# GridSeed_Rev04.net
KiCad netlist of a schematic drawn in Altium Designer
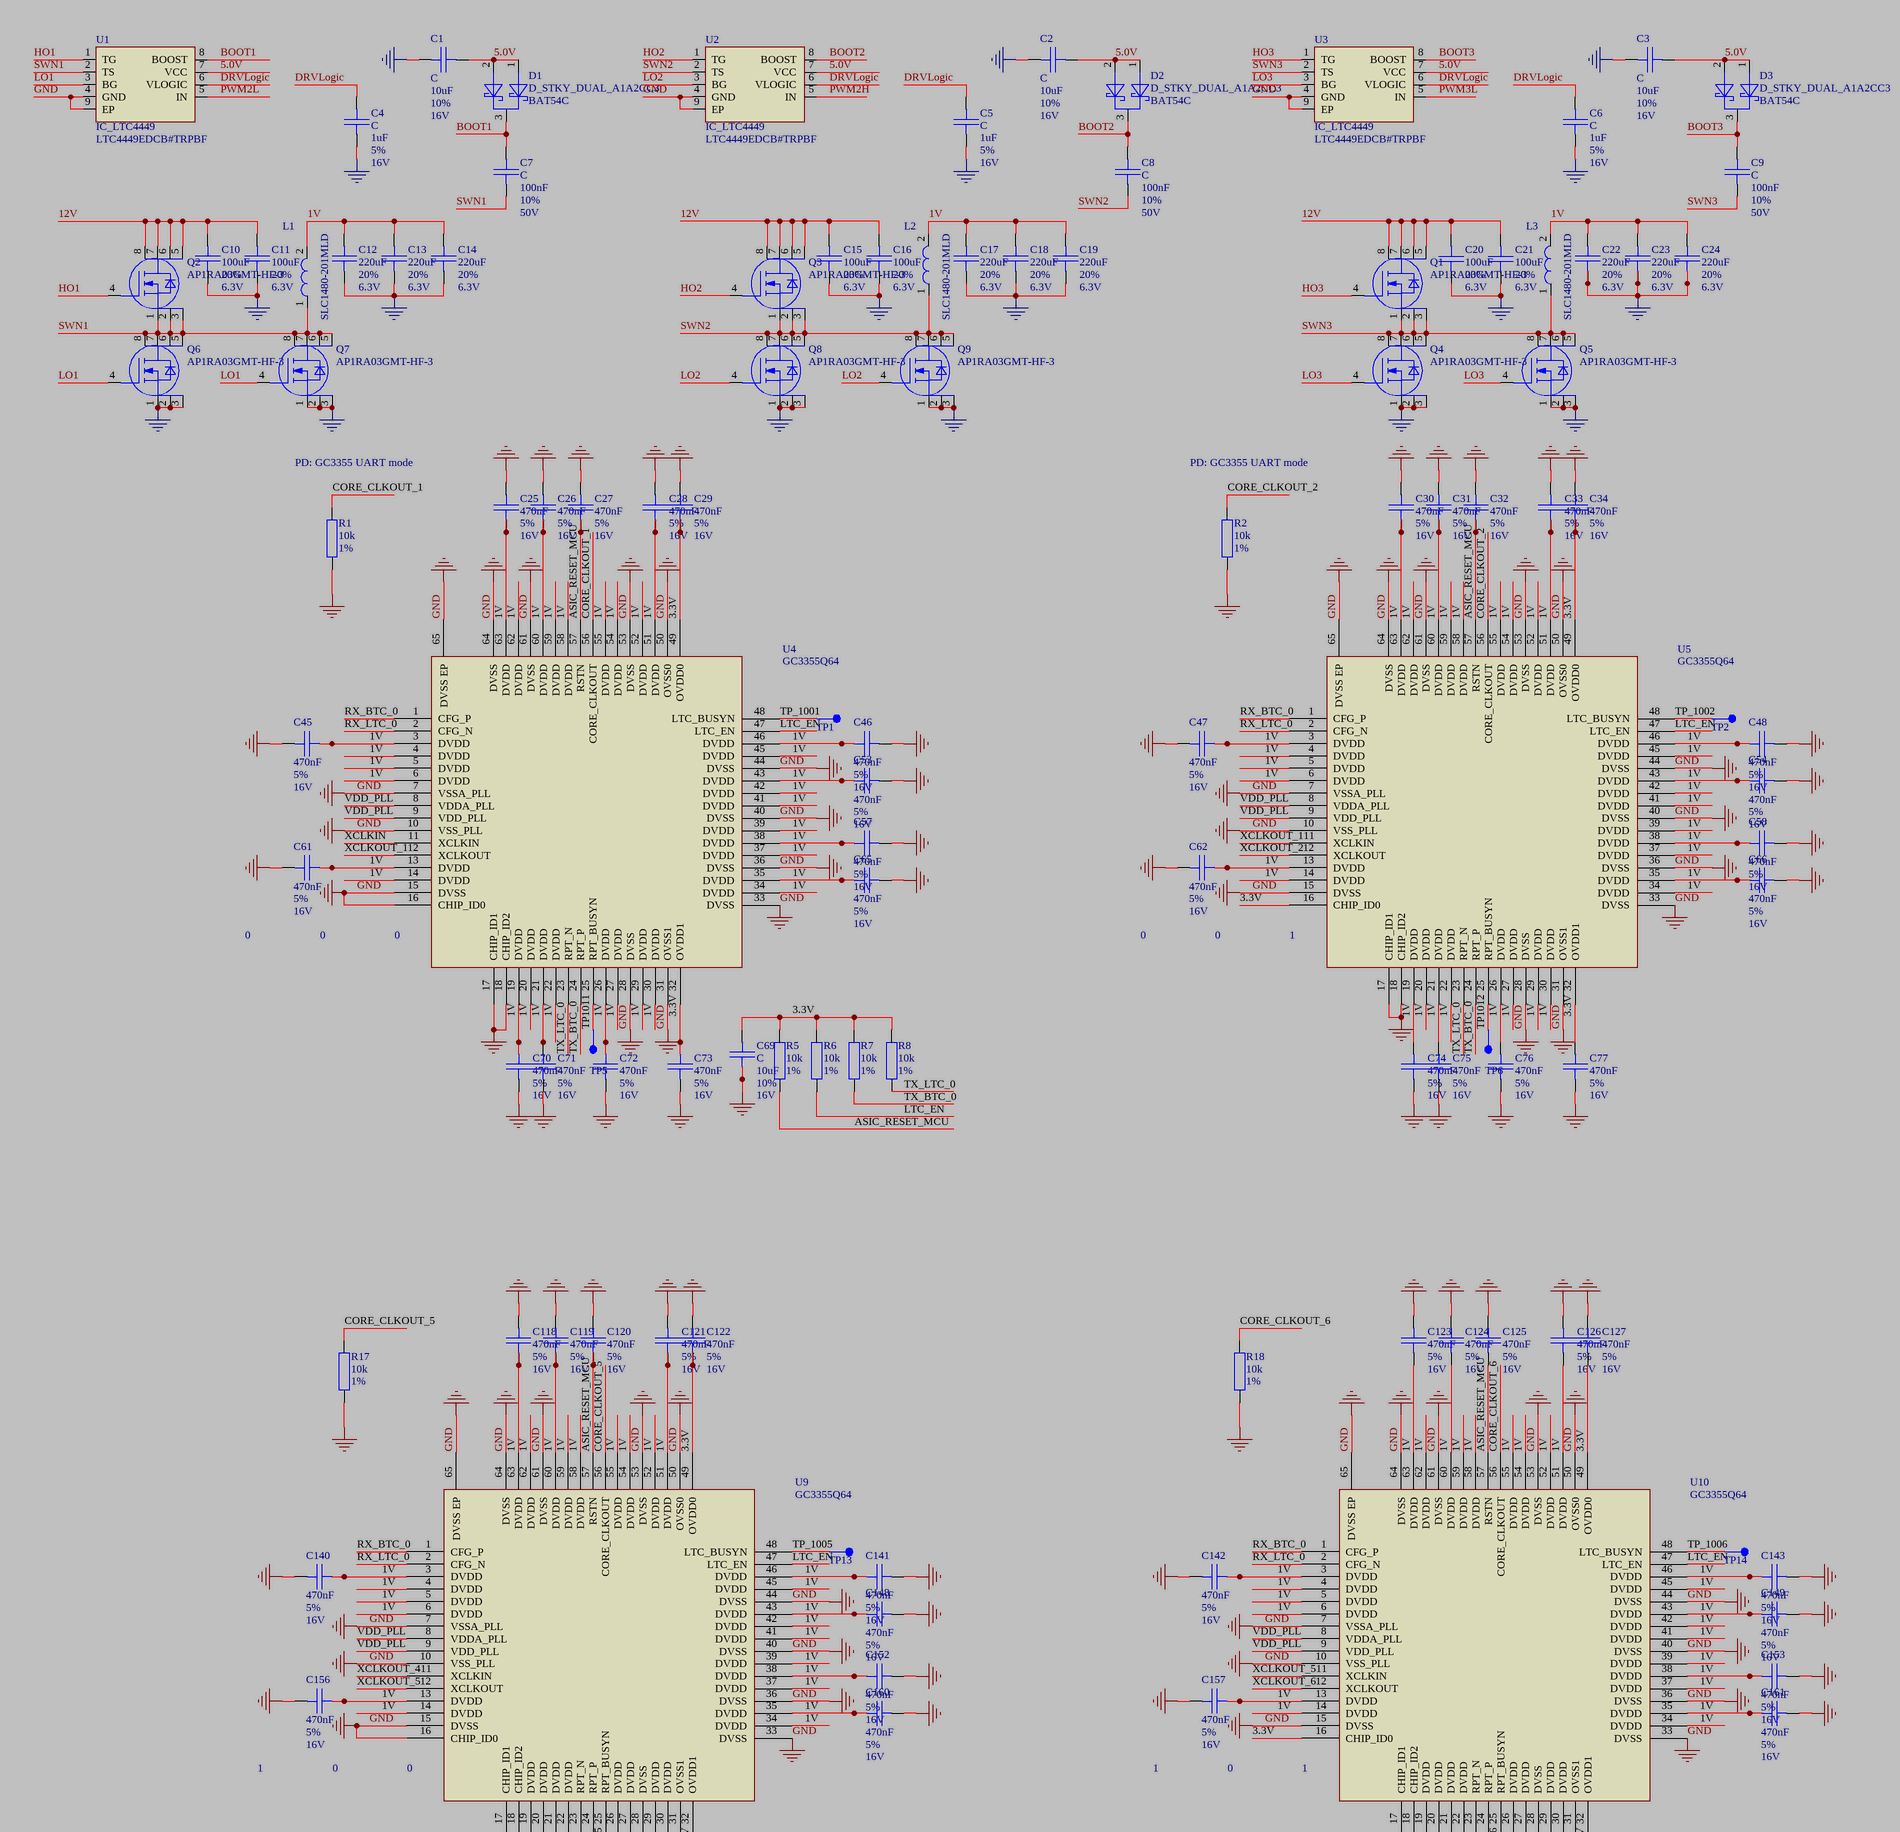
[diagram p0: GridSeed_Rev04.SchDoc, top left]
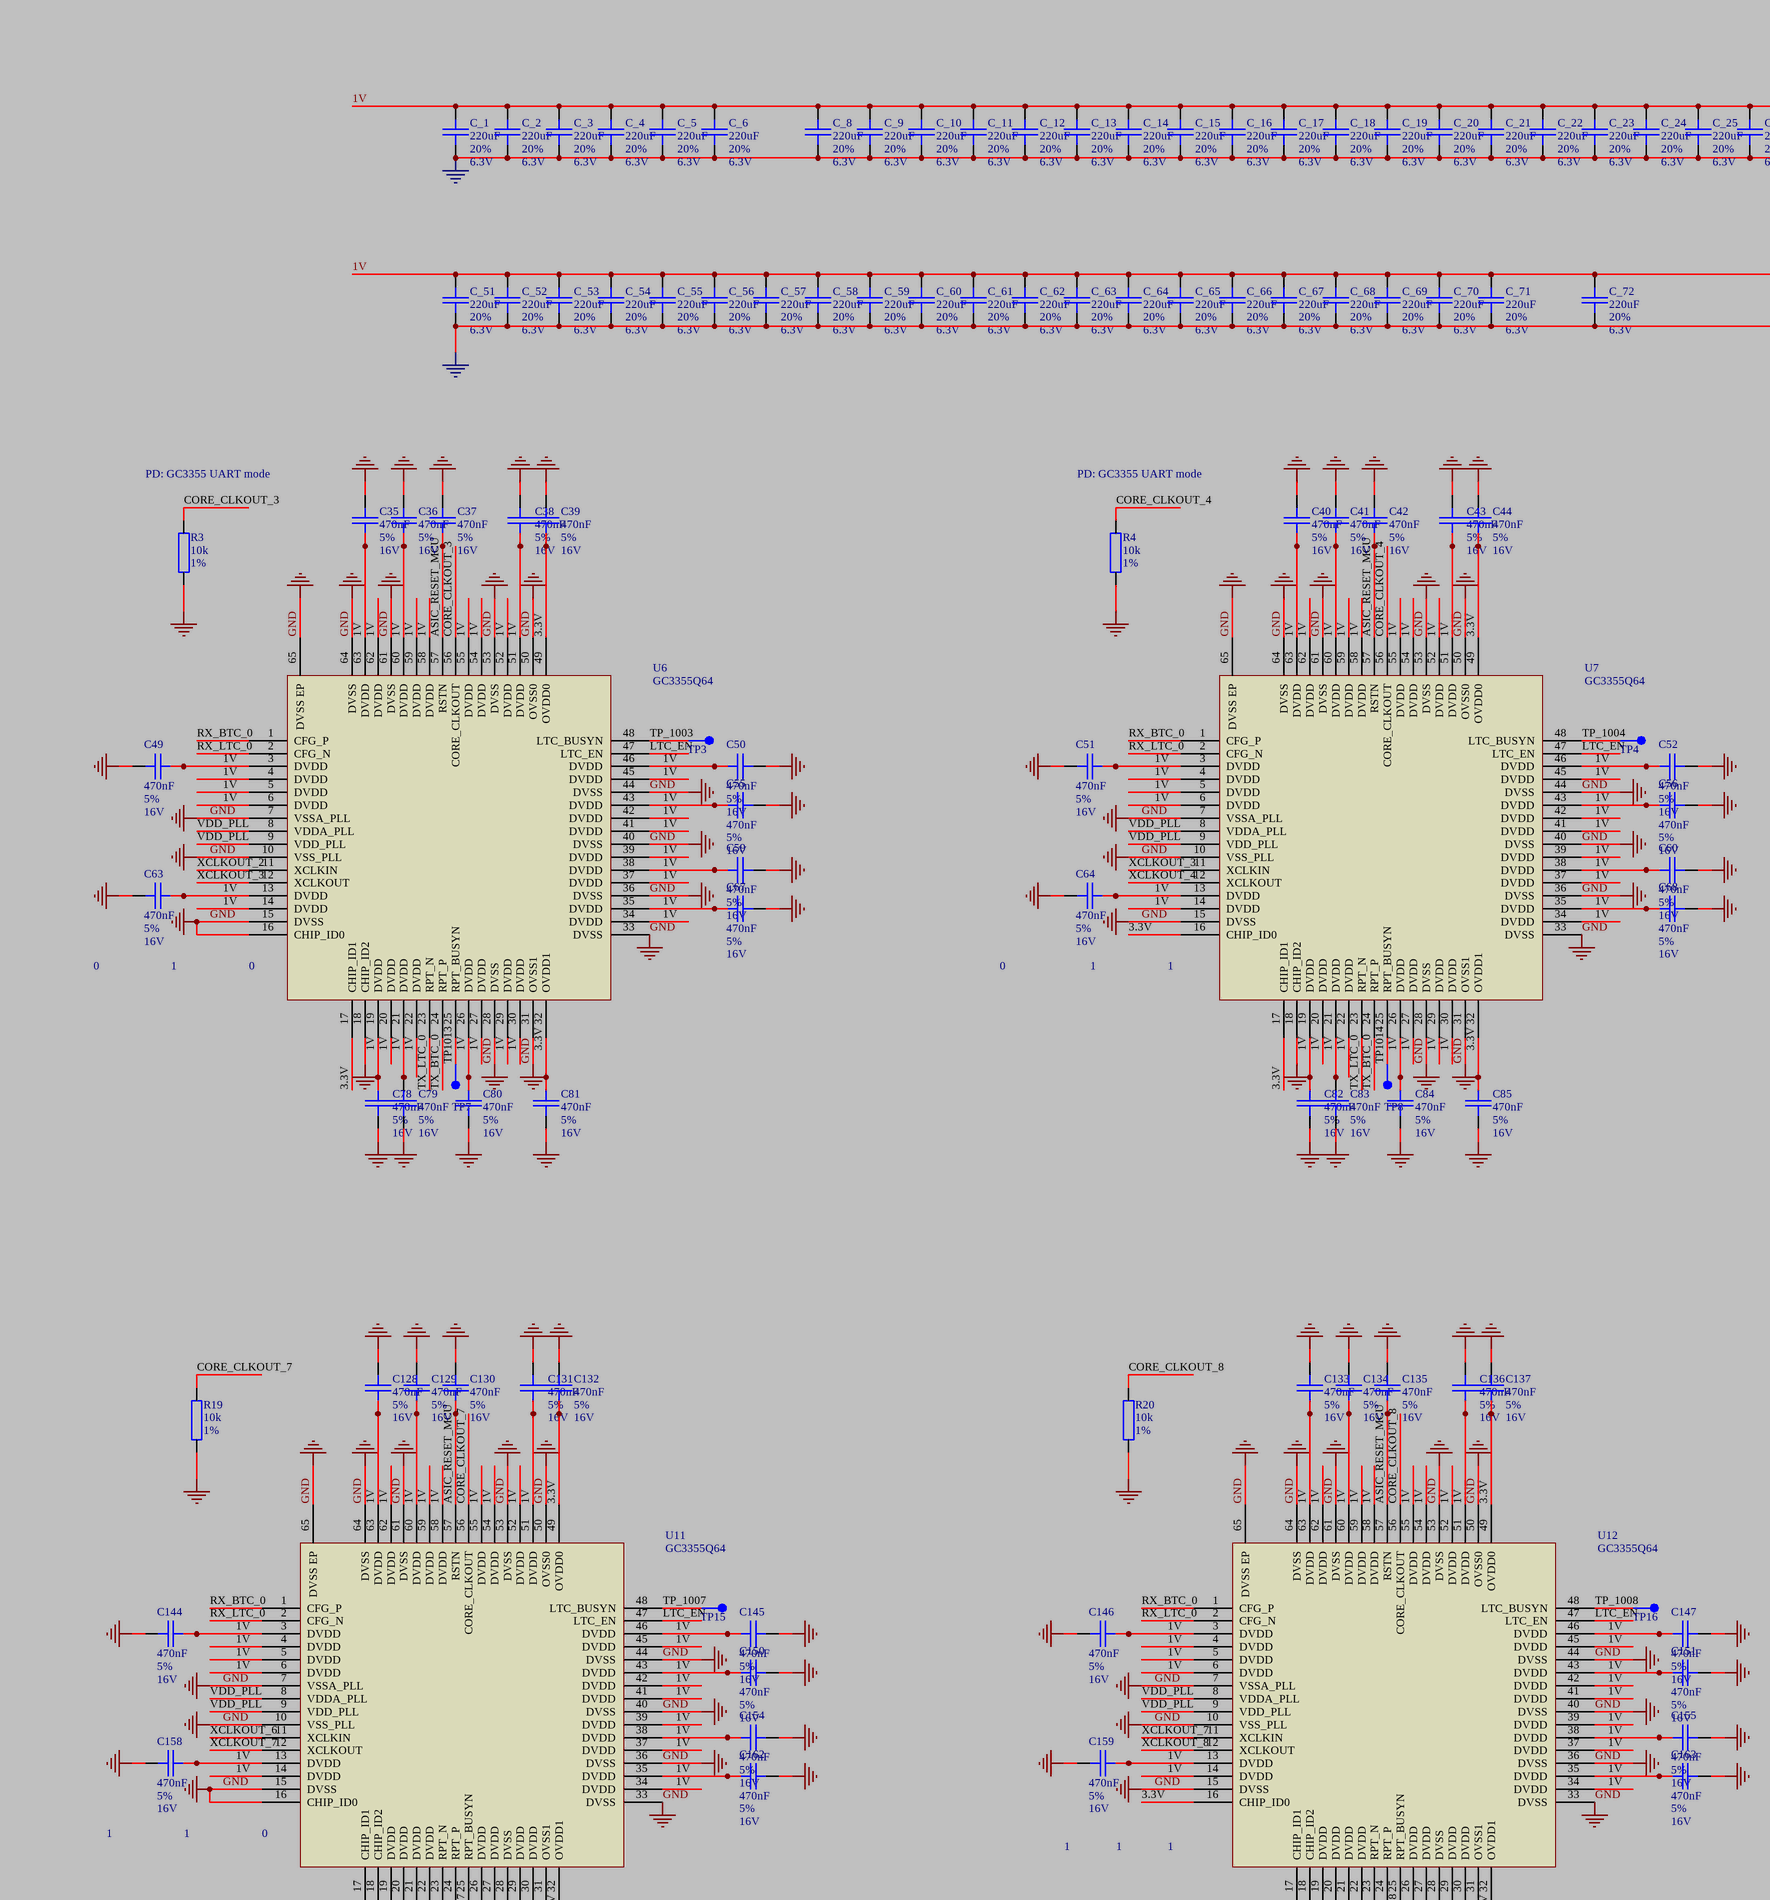
[diagram p1: GridSeed_Rev04.SchDoc, top middle]
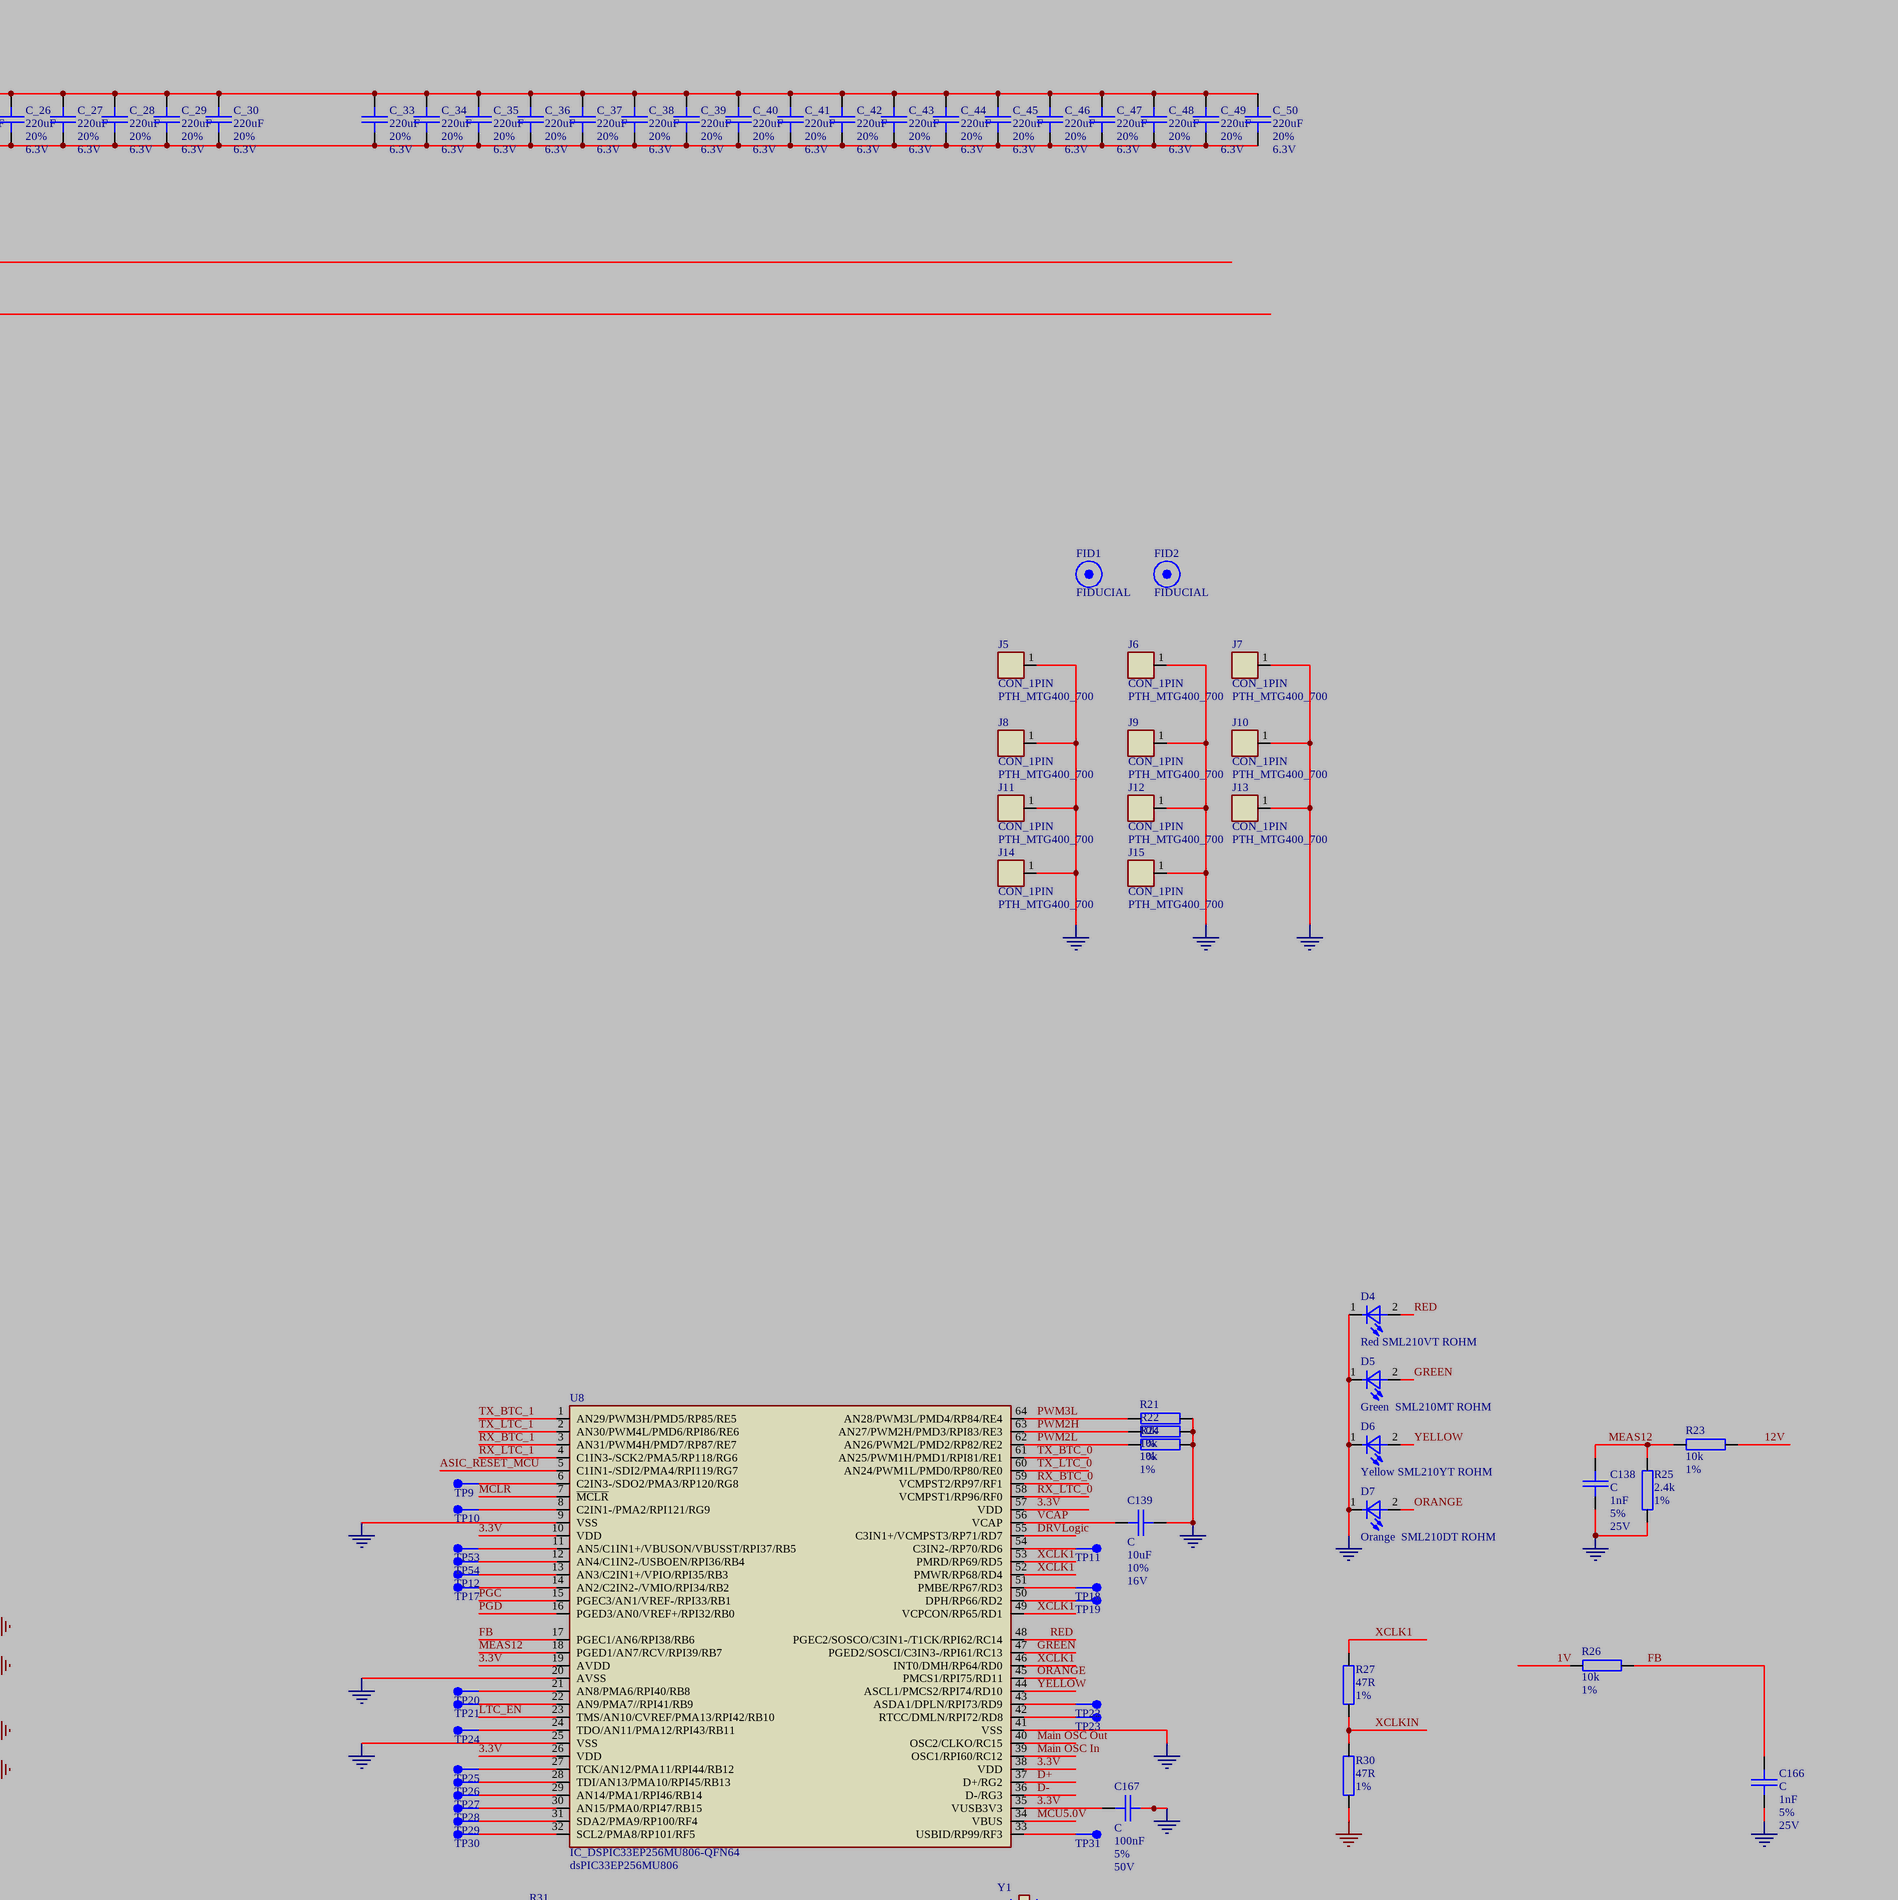
[diagram p2: GridSeed_Rev04.SchDoc, top right]
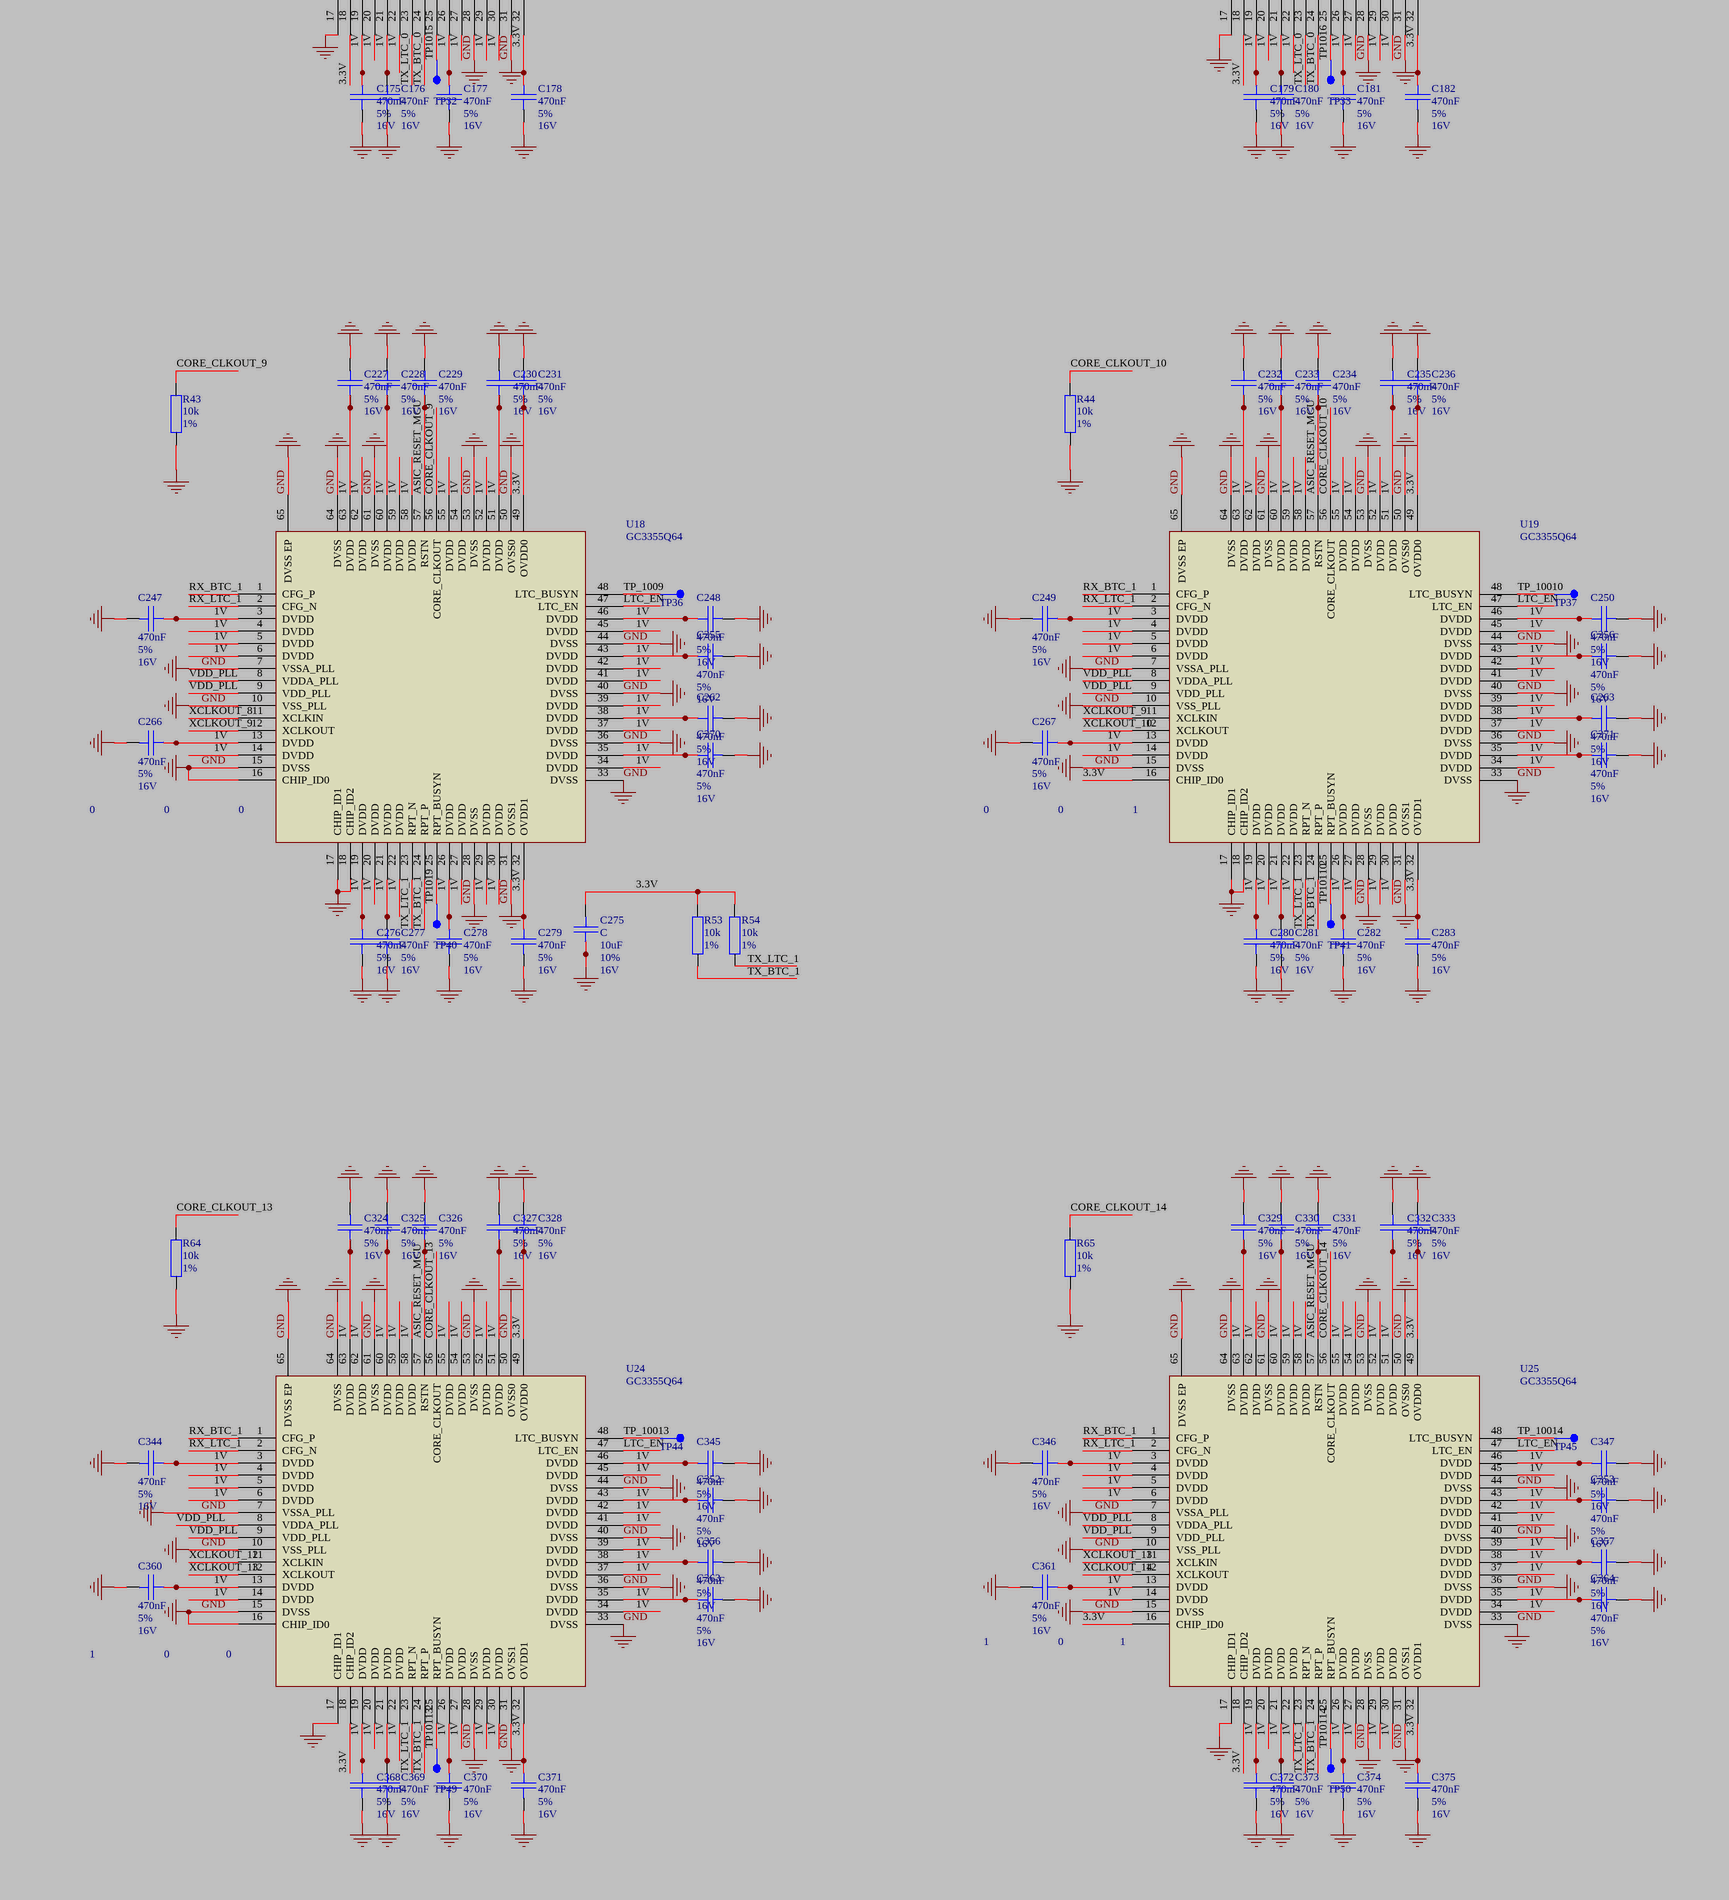
[diagram p3: GridSeed_Rev04.SchDoc, bottom left]
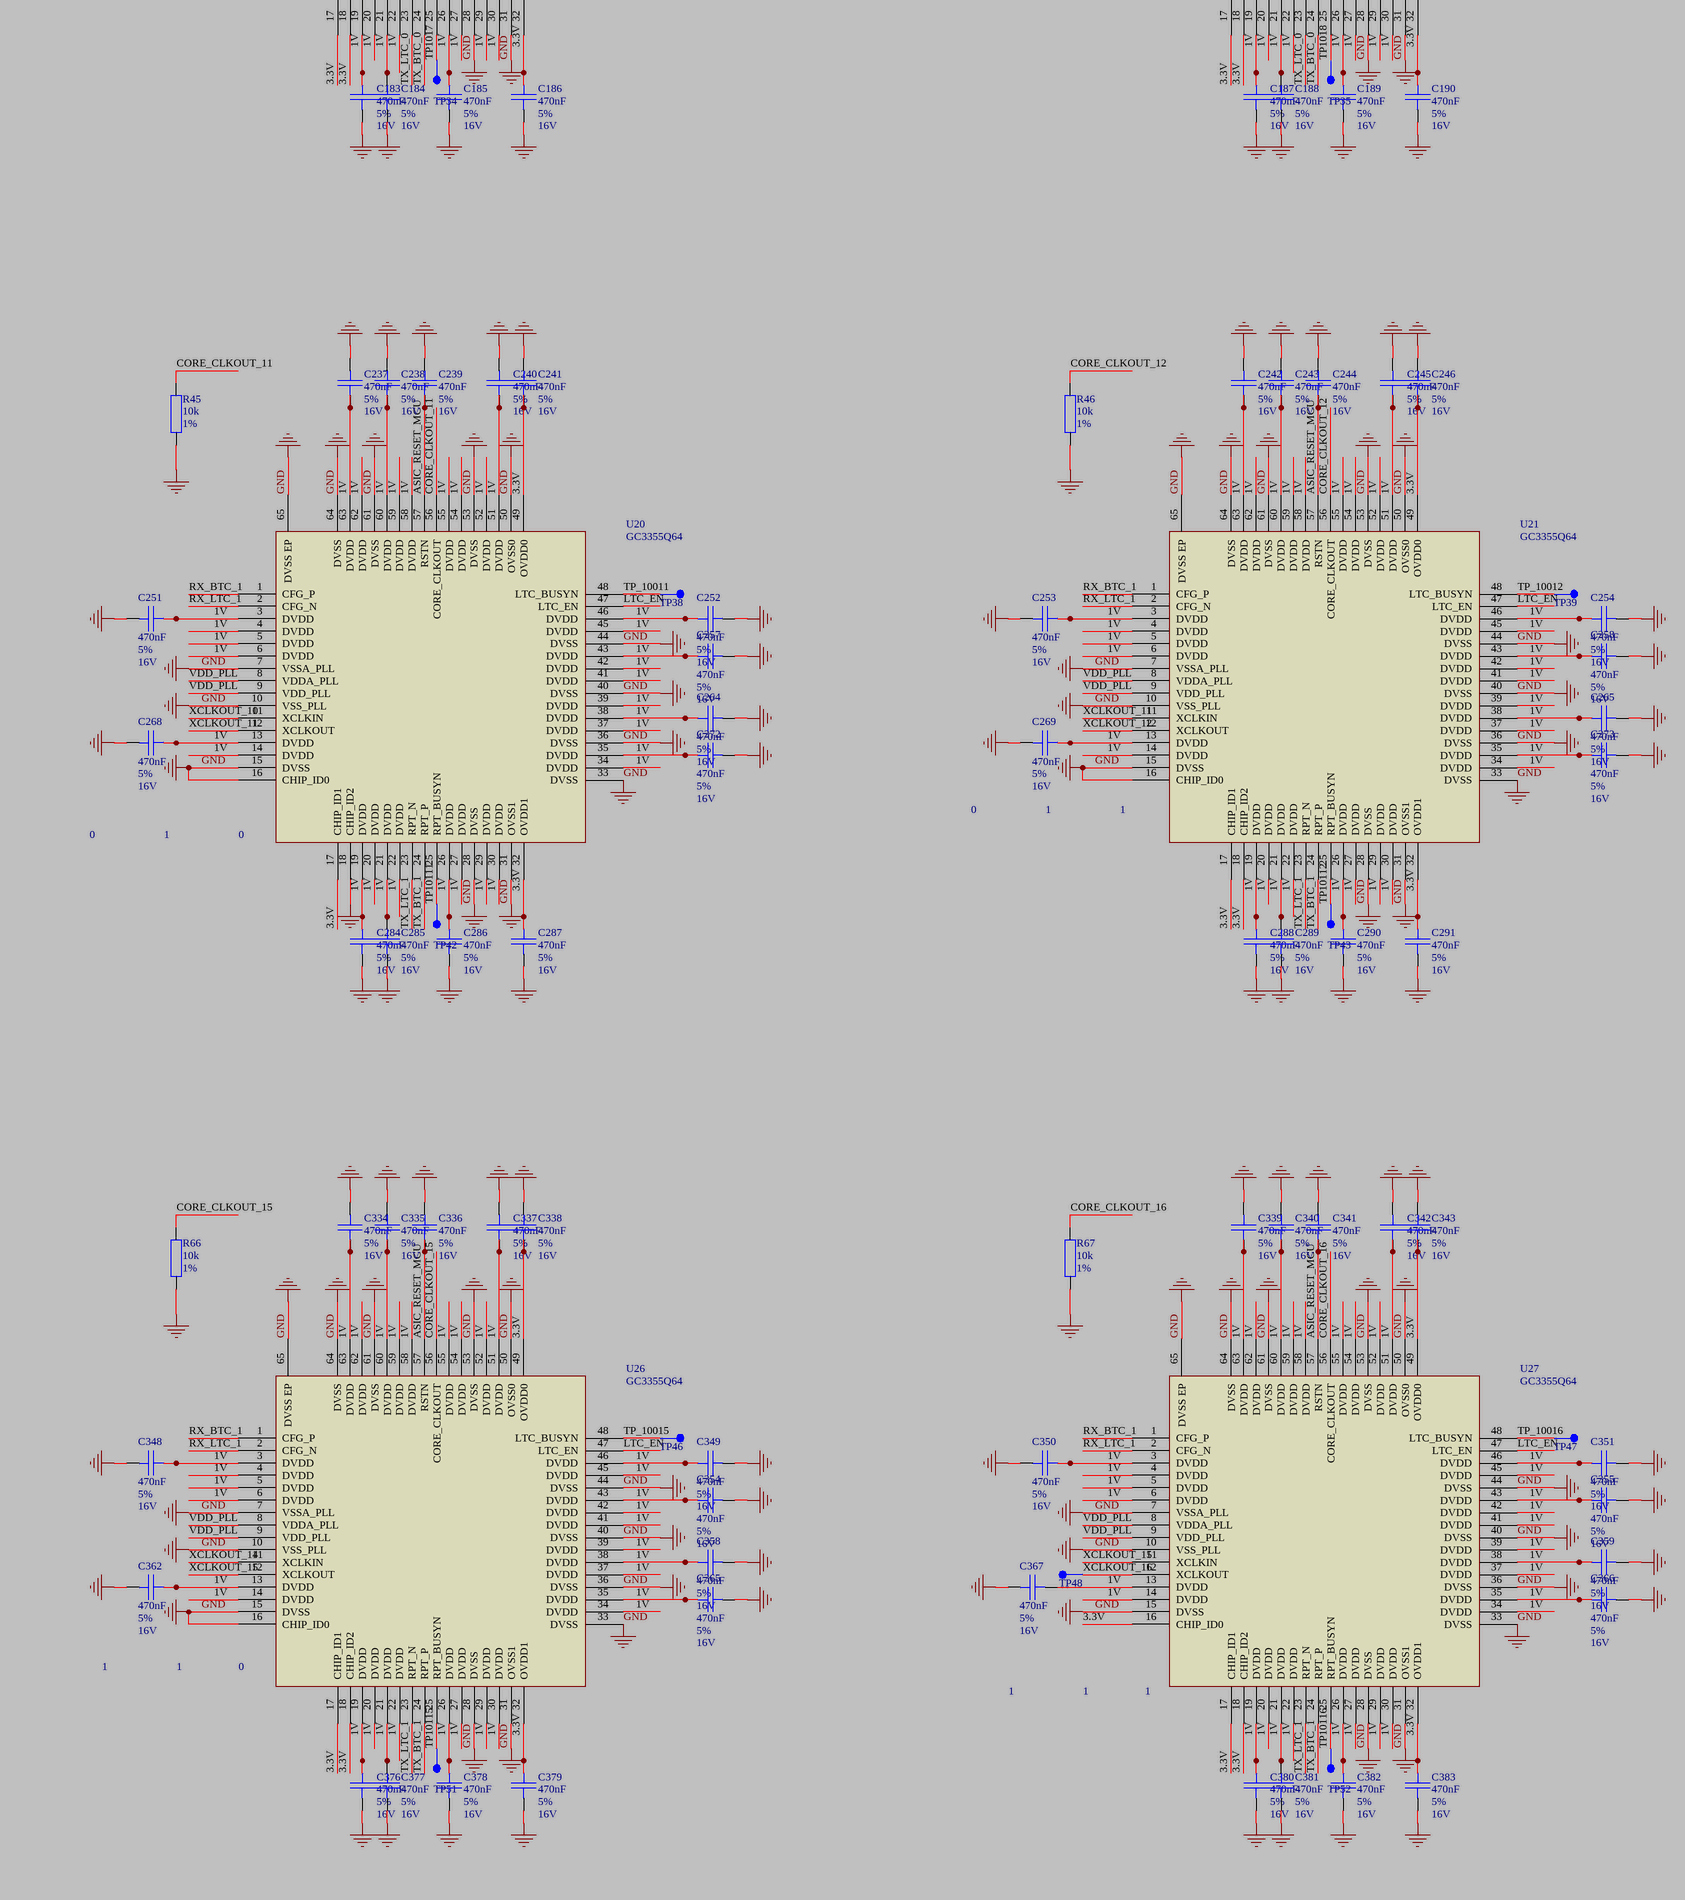
[diagram p4: GridSeed_Rev04.SchDoc, bottom middle]
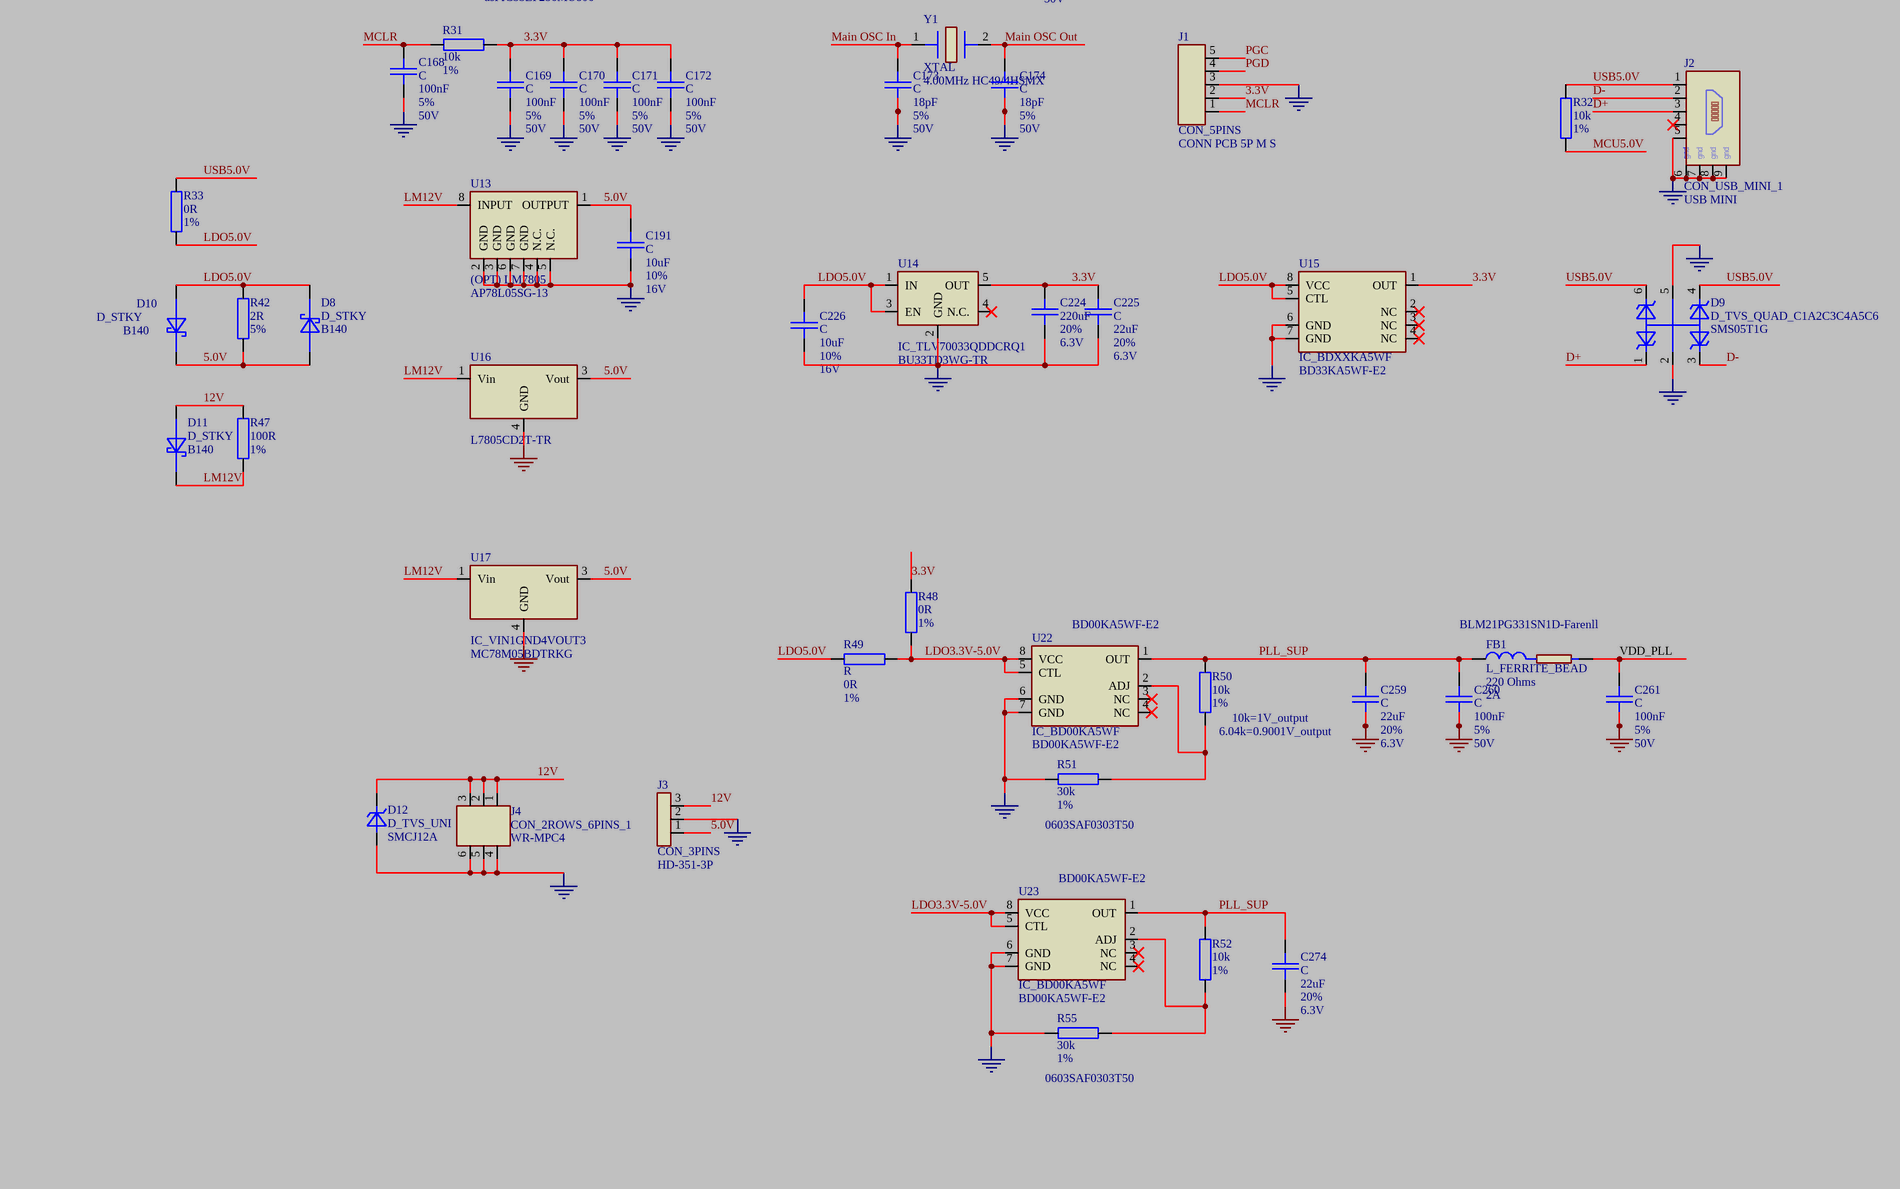
[diagram p5: GridSeed_Rev04.SchDoc, bottom right]

(export (version "E")
  (design (tool "Eeschema 10.0.6"))
  (components
    (comp (ref "C1")
      (value "C")
      (footprint "SMD_0805_CAPC2012X145N")
      (fields
        (field (name "DB_PART_NUMBER") "CAP000043636")
        (field (name "DB_VALUE") "10uF")
        (field (name "DB_TOLERANCE") "10%")
        (field (name "DB_VOLTAGE") "16V")
        (field (name "DB_MANUFACTURER_PART") "KEMET    C0805C106K4PAC")
        (field (name "DB_APPROVED_BY") "ISHIDDEN=T")
      )
      (libsource (lib "Database_Libs1") (part "C"))
    )
    (comp (ref "C2")
      (value "C")
      (footprint "SMD_0805_CAPC2012X145N")
      (fields
        (field (name "DB_PART_NUMBER") "CAP000043636")
        (field (name "DB_VALUE") "10uF")
        (field (name "DB_TOLERANCE") "10%")
        (field (name "DB_VOLTAGE") "16V")
        (field (name "DB_MANUFACTURER_PART") "KEMET    C0805C106K4PAC")
        (field (name "DB_APPROVED_BY") "ISHIDDEN=T")
      )
      (libsource (lib "Database_Libs1") (part "C"))
    )
    (comp (ref "C3")
      (value "C")
      (footprint "SMD_0805_CAPC2012X145N")
      (fields
        (field (name "DB_PART_NUMBER") "CAP000043636")
        (field (name "DB_VALUE") "10uF")
        (field (name "DB_TOLERANCE") "10%")
        (field (name "DB_VOLTAGE") "16V")
        (field (name "DB_MANUFACTURER_PART") "KEMET    C0805C106K4PAC")
        (field (name "DB_APPROVED_BY") "ISHIDDEN=T")
      )
      (libsource (lib "Database_Libs1") (part "C"))
    )
    (comp (ref "C4")
      (value "C")
      (footprint "SMD_0805_CAPC2012X145N")
      (fields
        (field (name "DB_PART_NUMBER") "CAP000028589")
        (field (name "DB_VALUE") "1uF")
        (field (name "DB_TOLERANCE") "5%")
        (field (name "DB_VOLTAGE") "16V")
        (field (name "DB_MANUFACTURER_PART") "KEMET    C0805C105J4RAC")
        (field (name "DB_APPROVED_BY") "ISHIDDEN=T")
      )
      (libsource (lib "Database_Libs1") (part "C"))
    )
    (comp (ref "C5")
      (value "C")
      (footprint "SMD_0805_CAPC2012X145N")
      (fields
        (field (name "DB_PART_NUMBER") "CAP000028589")
        (field (name "DB_VALUE") "1uF")
        (field (name "DB_TOLERANCE") "5%")
        (field (name "DB_VOLTAGE") "16V")
        (field (name "DB_MANUFACTURER_PART") "KEMET    C0805C105J4RAC")
        (field (name "DB_APPROVED_BY") "ISHIDDEN=T")
      )
      (libsource (lib "Database_Libs1") (part "C"))
    )
    (comp (ref "C6")
      (value "C")
      (footprint "SMD_0805_CAPC2012X145N")
      (fields
        (field (name "DB_PART_NUMBER") "CAP000028589")
        (field (name "DB_VALUE") "1uF")
        (field (name "DB_TOLERANCE") "5%")
        (field (name "DB_VOLTAGE") "16V")
        (field (name "DB_MANUFACTURER_PART") "KEMET    C0805C105J4RAC")
        (field (name "DB_APPROVED_BY") "ISHIDDEN=T")
      )
      (libsource (lib "Database_Libs1") (part "C"))
    )
    (comp (ref "C7")
      (value "C")
      (footprint "SMD_0805_CAPC2012X145N")
      (fields
        (field (name "DB_PART_NUMBER") "CAP000027193")
        (field (name "DB_VALUE") "100nF")
        (field (name "DB_TOLERANCE") "10%")
        (field (name "DB_VOLTAGE") "50V")
        (field (name "DB_MANUFACTURER_PART") "KEMET    C0805C104K5RAC")
        (field (name "DB_APPROVED_BY") "ISHIDDEN=T")
      )
      (libsource (lib "Database_Libs1") (part "C"))
    )
    (comp (ref "C8")
      (value "C")
      (footprint "SMD_0805_CAPC2012X145N")
      (fields
        (field (name "DB_PART_NUMBER") "CAP000027193")
        (field (name "DB_VALUE") "100nF")
        (field (name "DB_TOLERANCE") "10%")
        (field (name "DB_VOLTAGE") "50V")
        (field (name "DB_MANUFACTURER_PART") "KEMET    C0805C104K5RAC")
        (field (name "DB_APPROVED_BY") "ISHIDDEN=T")
      )
      (libsource (lib "Database_Libs1") (part "C"))
    )
    (comp (ref "C9")
      (value "C")
      (footprint "SMD_0805_CAPC2012X145N")
      (fields
        (field (name "DB_PART_NUMBER") "CAP000027193")
        (field (name "DB_VALUE") "100nF")
        (field (name "DB_TOLERANCE") "10%")
        (field (name "DB_VOLTAGE") "50V")
        (field (name "DB_MANUFACTURER_PART") "KEMET    C0805C104K5RAC")
        (field (name "DB_APPROVED_BY") "ISHIDDEN=T")
      )
      (libsource (lib "Database_Libs1") (part "C"))
    )
    (comp (ref "C10")
      (value "C")
      (footprint "SMD_1210_CAPC3225X270N")
      (fields
        (field (name "DB_PART_NUMBER") "CAP000043701")
        (field (name "DB_VALUE") "100uF")
        (field (name "DB_TOLERANCE") "20%")
        (field (name "DB_VOLTAGE") "6.3V")
        (field (name "DB_MANUFACTURER_PART") "KEMET    C1210C107M9PAC")
        (field (name "DB_APPROVED_BY") "ISHIDDEN=T")
      )
      (libsource (lib "Database_Libs1") (part "C"))
    )
    (comp (ref "C11")
      (value "C")
      (footprint "SMD_1210_CAPC3225X270N")
      (fields
        (field (name "DB_PART_NUMBER") "CAP000043701")
        (field (name "DB_VALUE") "100uF")
        (field (name "DB_TOLERANCE") "20%")
        (field (name "DB_VOLTAGE") "6.3V")
        (field (name "DB_MANUFACTURER_PART") "KEMET    C1210C107M9PAC")
        (field (name "DB_APPROVED_BY") "ISHIDDEN=T")
      )
      (libsource (lib "Database_Libs1") (part "C"))
    )
    (comp (ref "C12")
      (value "C")
      (footprint "SMD_1210_CAPC3225X279N")
      (fields
        (field (name "DB_PART_NUMBER") "CAP000047355")
        (field (name "DB_VALUE") "220uF")
        (field (name "DB_TOLERANCE") "20%")
        (field (name "DB_VOLTAGE") "6.3V")
        (field (name "DB_MANUFACTURER_PART") "SAMSUNG    CL32A227MQVNNNE")
        (field (name "DB_APPROVED_BY") "VSN")
      )
      (libsource (lib "Database_Libs1") (part "C"))
    )
    (comp (ref "C13")
      (value "C")
      (footprint "SMD_1210_CAPC3225X279N")
      (fields
        (field (name "DB_PART_NUMBER") "CAP000047355")
        (field (name "DB_VALUE") "220uF")
        (field (name "DB_TOLERANCE") "20%")
        (field (name "DB_VOLTAGE") "6.3V")
        (field (name "DB_MANUFACTURER_PART") "SAMSUNG    CL32A227MQVNNNE")
        (field (name "DB_APPROVED_BY") "VSN")
      )
      (libsource (lib "Database_Libs1") (part "C"))
    )
    (comp (ref "C14")
      (value "C")
      (footprint "SMD_1210_CAPC3225X279N")
      (fields
        (field (name "DB_PART_NUMBER") "CAP000047355")
        (field (name "DB_VALUE") "220uF")
        (field (name "DB_TOLERANCE") "20%")
        (field (name "DB_VOLTAGE") "6.3V")
        (field (name "DB_MANUFACTURER_PART") "SAMSUNG    CL32A227MQVNNNE")
        (field (name "DB_APPROVED_BY") "VSN")
      )
      (libsource (lib "Database_Libs1") (part "C"))
    )
    (comp (ref "C15")
      (value "C")
      (footprint "SMD_1210_CAPC3225X270N")
      (fields
        (field (name "DB_PART_NUMBER") "CAP000043701")
        (field (name "DB_VALUE") "100uF")
        (field (name "DB_TOLERANCE") "20%")
        (field (name "DB_VOLTAGE") "6.3V")
        (field (name "DB_MANUFACTURER_PART") "KEMET    C1210C107M9PAC")
        (field (name "DB_APPROVED_BY") "ISHIDDEN=T")
      )
      (libsource (lib "Database_Libs1") (part "C"))
    )
    (comp (ref "C16")
      (value "C")
      (footprint "SMD_1210_CAPC3225X270N")
      (fields
        (field (name "DB_PART_NUMBER") "CAP000043701")
        (field (name "DB_VALUE") "100uF")
        (field (name "DB_TOLERANCE") "20%")
        (field (name "DB_VOLTAGE") "6.3V")
        (field (name "DB_MANUFACTURER_PART") "KEMET    C1210C107M9PAC")
        (field (name "DB_APPROVED_BY") "ISHIDDEN=T")
      )
      (libsource (lib "Database_Libs1") (part "C"))
    )
    (comp (ref "C17")
      (value "C")
      (footprint "SMD_1210_CAPC3225X279N")
      (fields
        (field (name "DB_PART_NUMBER") "CAP000047355")
        (field (name "DB_VALUE") "220uF")
        (field (name "DB_TOLERANCE") "20%")
        (field (name "DB_VOLTAGE") "6.3V")
        (field (name "DB_MANUFACTURER_PART") "SAMSUNG    CL32A227MQVNNNE")
        (field (name "DB_APPROVED_BY") "VSN")
      )
      (libsource (lib "Database_Libs1") (part "C"))
    )
    (comp (ref "C18")
      (value "C")
      (footprint "SMD_1210_CAPC3225X279N")
      (fields
        (field (name "DB_PART_NUMBER") "CAP000047355")
        (field (name "DB_VALUE") "220uF")
        (field (name "DB_TOLERANCE") "20%")
        (field (name "DB_VOLTAGE") "6.3V")
        (field (name "DB_MANUFACTURER_PART") "SAMSUNG    CL32A227MQVNNNE")
        (field (name "DB_APPROVED_BY") "VSN")
      )
      (libsource (lib "Database_Libs1") (part "C"))
    )
    (comp (ref "C19")
      (value "C")
      (footprint "SMD_1210_CAPC3225X279N")
      (fields
        (field (name "DB_PART_NUMBER") "CAP000047355")
        (field (name "DB_VALUE") "220uF")
        (field (name "DB_TOLERANCE") "20%")
        (field (name "DB_VOLTAGE") "6.3V")
        (field (name "DB_MANUFACTURER_PART") "SAMSUNG    CL32A227MQVNNNE")
        (field (name "DB_APPROVED_BY") "VSN")
      )
      (libsource (lib "Database_Libs1") (part "C"))
    )
    (comp (ref "C20")
      (value "C")
      (footprint "SMD_1210_CAPC3225X270N")
      (fields
        (field (name "DB_PART_NUMBER") "CAP000043701")
        (field (name "DB_VALUE") "100uF")
        (field (name "DB_TOLERANCE") "20%")
        (field (name "DB_VOLTAGE") "6.3V")
        (field (name "DB_MANUFACTURER_PART") "KEMET    C1210C107M9PAC")
        (field (name "DB_APPROVED_BY") "ISHIDDEN=T")
      )
      (libsource (lib "Database_Libs1") (part "C"))
    )
    (comp (ref "C21")
      (value "C")
      (footprint "SMD_1210_CAPC3225X270N")
      (fields
        (field (name "DB_PART_NUMBER") "CAP000043701")
        (field (name "DB_VALUE") "100uF")
        (field (name "DB_TOLERANCE") "20%")
        (field (name "DB_VOLTAGE") "6.3V")
        (field (name "DB_MANUFACTURER_PART") "KEMET    C1210C107M9PAC")
        (field (name "DB_APPROVED_BY") "ISHIDDEN=T")
      )
      (libsource (lib "Database_Libs1") (part "C"))
    )
    (comp (ref "C22")
      (value "C")
      (footprint "SMD_1210_CAPC3225X279N")
      (fields
        (field (name "DB_PART_NUMBER") "CAP000047355")
        (field (name "DB_VALUE") "220uF")
        (field (name "DB_TOLERANCE") "20%")
        (field (name "DB_VOLTAGE") "6.3V")
        (field (name "DB_MANUFACTURER_PART") "SAMSUNG    CL32A227MQVNNNE")
        (field (name "DB_APPROVED_BY") "VSN")
      )
      (libsource (lib "Database_Libs1") (part "C"))
    )
    (comp (ref "C23")
      (value "C")
      (footprint "SMD_1210_CAPC3225X279N")
      (fields
        (field (name "DB_PART_NUMBER") "CAP000047355")
        (field (name "DB_VALUE") "220uF")
        (field (name "DB_TOLERANCE") "20%")
        (field (name "DB_VOLTAGE") "6.3V")
        (field (name "DB_MANUFACTURER_PART") "SAMSUNG    CL32A227MQVNNNE")
        (field (name "DB_APPROVED_BY") "VSN")
      )
      (libsource (lib "Database_Libs1") (part "C"))
    )
    (comp (ref "C24")
      (value "C")
      (footprint "SMD_1210_CAPC3225X279N")
      (fields
        (field (name "DB_PART_NUMBER") "CAP000047355")
        (field (name "DB_VALUE") "220uF")
        (field (name "DB_TOLERANCE") "20%")
        (field (name "DB_VOLTAGE") "6.3V")
        (field (name "DB_MANUFACTURER_PART") "SAMSUNG    CL32A227MQVNNNE")
        (field (name "DB_APPROVED_BY") "VSN")
      )
      (libsource (lib "Database_Libs1") (part "C"))
    )
    (comp (ref "C25")
      (value "C")
      (footprint "SMD_0603_CAPC1608X95N")
      (fields
        (field (name "DB_PART_NUMBER") "CAP000028169")
        (field (name "DB_VALUE") "470nF")
        (field (name "DB_TOLERANCE") "5%")
        (field (name "DB_VOLTAGE") "16V")
        (field (name "DB_MANUFACTURER_PART") "KEMET    C0603C474J4RAC")
        (field (name "DB_APPROVED_BY") "ISHIDDEN=T")
      )
      (libsource (lib "Database_Libs1") (part "C"))
    )
    (comp (ref "C26")
      (value "C")
      (footprint "SMD_0603_CAPC1608X95N")
      (fields
        (field (name "DB_PART_NUMBER") "CAP000028169")
        (field (name "DB_VALUE") "470nF")
        (field (name "DB_TOLERANCE") "5%")
        (field (name "DB_VOLTAGE") "16V")
        (field (name "DB_MANUFACTURER_PART") "KEMET    C0603C474J4RAC")
        (field (name "DB_APPROVED_BY") "ISHIDDEN=T")
      )
      (libsource (lib "Database_Libs1") (part "C"))
    )
    (comp (ref "C27")
      (value "C")
      (footprint "SMD_0603_CAPC1608X95N")
      (fields
        (field (name "DB_PART_NUMBER") "CAP000028169")
        (field (name "DB_VALUE") "470nF")
        (field (name "DB_TOLERANCE") "5%")
        (field (name "DB_VOLTAGE") "16V")
        (field (name "DB_MANUFACTURER_PART") "KEMET    C0603C474J4RAC")
        (field (name "DB_APPROVED_BY") "ISHIDDEN=T")
      )
      (libsource (lib "Database_Libs1") (part "C"))
    )
    (comp (ref "C28")
      (value "C")
      (footprint "SMD_0603_CAPC1608X95N")
      (fields
        (field (name "DB_PART_NUMBER") "CAP000028169")
        (field (name "DB_VALUE") "470nF")
        (field (name "DB_TOLERANCE") "5%")
        (field (name "DB_VOLTAGE") "16V")
        (field (name "DB_MANUFACTURER_PART") "KEMET    C0603C474J4RAC")
        (field (name "DB_APPROVED_BY") "ISHIDDEN=T")
      )
      (libsource (lib "Database_Libs1") (part "C"))
    )
    (comp (ref "C29")
      (value "C")
      (footprint "SMD_0603_CAPC1608X95N")
      (fields
        (field (name "DB_PART_NUMBER") "CAP000028169")
        (field (name "DB_VALUE") "470nF")
        (field (name "DB_TOLERANCE") "5%")
        (field (name "DB_VOLTAGE") "16V")
        (field (name "DB_MANUFACTURER_PART") "KEMET    C0603C474J4RAC")
        (field (name "DB_APPROVED_BY") "ISHIDDEN=T")
      )
      (libsource (lib "Database_Libs1") (part "C"))
    )
    (comp (ref "C30")
      (value "C")
      (footprint "SMD_0603_CAPC1608X95N")
      (fields
        (field (name "DB_PART_NUMBER") "CAP000028169")
        (field (name "DB_VALUE") "470nF")
        (field (name "DB_TOLERANCE") "5%")
        (field (name "DB_VOLTAGE") "16V")
        (field (name "DB_MANUFACTURER_PART") "KEMET    C0603C474J4RAC")
        (field (name "DB_APPROVED_BY") "ISHIDDEN=T")
      )
      (libsource (lib "Database_Libs1") (part "C"))
    )
    (comp (ref "C31")
      (value "C")
      (footprint "SMD_0603_CAPC1608X95N")
      (fields
        (field (name "DB_PART_NUMBER") "CAP000028169")
        (field (name "DB_VALUE") "470nF")
        (field (name "DB_TOLERANCE") "5%")
        (field (name "DB_VOLTAGE") "16V")
        (field (name "DB_MANUFACTURER_PART") "KEMET    C0603C474J4RAC")
        (field (name "DB_APPROVED_BY") "ISHIDDEN=T")
      )
      (libsource (lib "Database_Libs1") (part "C"))
    )
    (comp (ref "C32")
      (value "C")
      (footprint "SMD_0603_CAPC1608X95N")
      (fields
        (field (name "DB_PART_NUMBER") "CAP000028169")
        (field (name "DB_VALUE") "470nF")
        (field (name "DB_TOLERANCE") "5%")
        (field (name "DB_VOLTAGE") "16V")
        (field (name "DB_MANUFACTURER_PART") "KEMET    C0603C474J4RAC")
        (field (name "DB_APPROVED_BY") "ISHIDDEN=T")
      )
      (libsource (lib "Database_Libs1") (part "C"))
    )
    (comp (ref "C33")
      (value "C")
      (footprint "SMD_0603_CAPC1608X95N")
      (fields
        (field (name "DB_PART_NUMBER") "CAP000028169")
        (field (name "DB_VALUE") "470nF")
        (field (name "DB_TOLERANCE") "5%")
        (field (name "DB_VOLTAGE") "16V")
        (field (name "DB_MANUFACTURER_PART") "KEMET    C0603C474J4RAC")
        (field (name "DB_APPROVED_BY") "ISHIDDEN=T")
      )
      (libsource (lib "Database_Libs1") (part "C"))
    )
    (comp (ref "C34")
      (value "C")
      (footprint "SMD_0603_CAPC1608X95N")
      (fields
        (field (name "DB_PART_NUMBER") "CAP000028169")
        (field (name "DB_VALUE") "470nF")
        (field (name "DB_TOLERANCE") "5%")
        (field (name "DB_VOLTAGE") "16V")
        (field (name "DB_MANUFACTURER_PART") "KEMET    C0603C474J4RAC")
        (field (name "DB_APPROVED_BY") "ISHIDDEN=T")
      )
      (libsource (lib "Database_Libs1") (part "C"))
    )
    (comp (ref "C35")
      (value "C")
      (footprint "SMD_0603_CAPC1608X95N")
      (fields
        (field (name "DB_PART_NUMBER") "CAP000028169")
        (field (name "DB_VALUE") "470nF")
        (field (name "DB_TOLERANCE") "5%")
        (field (name "DB_VOLTAGE") "16V")
        (field (name "DB_MANUFACTURER_PART") "KEMET    C0603C474J4RAC")
        (field (name "DB_APPROVED_BY") "ISHIDDEN=T")
      )
      (libsource (lib "Database_Libs1") (part "C"))
    )
    (comp (ref "C36")
      (value "C")
      (footprint "SMD_0603_CAPC1608X95N")
      (fields
        (field (name "DB_PART_NUMBER") "CAP000028169")
        (field (name "DB_VALUE") "470nF")
        (field (name "DB_TOLERANCE") "5%")
        (field (name "DB_VOLTAGE") "16V")
        (field (name "DB_MANUFACTURER_PART") "KEMET    C0603C474J4RAC")
        (field (name "DB_APPROVED_BY") "ISHIDDEN=T")
      )
      (libsource (lib "Database_Libs1") (part "C"))
    )
    (comp (ref "C37")
      (value "C")
      (footprint "SMD_0603_CAPC1608X95N")
      (fields
        (field (name "DB_PART_NUMBER") "CAP000028169")
        (field (name "DB_VALUE") "470nF")
        (field (name "DB_TOLERANCE") "5%")
        (field (name "DB_VOLTAGE") "16V")
        (field (name "DB_MANUFACTURER_PART") "KEMET    C0603C474J4RAC")
        (field (name "DB_APPROVED_BY") "ISHIDDEN=T")
      )
      (libsource (lib "Database_Libs1") (part "C"))
    )
    (comp (ref "C38")
      (value "C")
      (footprint "SMD_0603_CAPC1608X95N")
      (fields
        (field (name "DB_PART_NUMBER") "CAP000028169")
        (field (name "DB_VALUE") "470nF")
        (field (name "DB_TOLERANCE") "5%")
        (field (name "DB_VOLTAGE") "16V")
        (field (name "DB_MANUFACTURER_PART") "KEMET    C0603C474J4RAC")
        (field (name "DB_APPROVED_BY") "ISHIDDEN=T")
      )
      (libsource (lib "Database_Libs1") (part "C"))
    )
    (comp (ref "C39")
      (value "C")
      (footprint "SMD_0603_CAPC1608X95N")
      (fields
        (field (name "DB_PART_NUMBER") "CAP000028169")
        (field (name "DB_VALUE") "470nF")
        (field (name "DB_TOLERANCE") "5%")
        (field (name "DB_VOLTAGE") "16V")
        (field (name "DB_MANUFACTURER_PART") "KEMET    C0603C474J4RAC")
        (field (name "DB_APPROVED_BY") "ISHIDDEN=T")
      )
      (libsource (lib "Database_Libs1") (part "C"))
    )
    (comp (ref "C40")
      (value "C")
      (footprint "SMD_0603_CAPC1608X95N")
      (fields
        (field (name "DB_PART_NUMBER") "CAP000028169")
        (field (name "DB_VALUE") "470nF")
        (field (name "DB_TOLERANCE") "5%")
        (field (name "DB_VOLTAGE") "16V")
        (field (name "DB_MANUFACTURER_PART") "KEMET    C0603C474J4RAC")
        (field (name "DB_APPROVED_BY") "ISHIDDEN=T")
      )
      (libsource (lib "Database_Libs1") (part "C"))
    )
    (comp (ref "C41")
      (value "C")
      (footprint "SMD_0603_CAPC1608X95N")
      (fields
        (field (name "DB_PART_NUMBER") "CAP000028169")
        (field (name "DB_VALUE") "470nF")
        (field (name "DB_TOLERANCE") "5%")
        (field (name "DB_VOLTAGE") "16V")
        (field (name "DB_MANUFACTURER_PART") "KEMET    C0603C474J4RAC")
        (field (name "DB_APPROVED_BY") "ISHIDDEN=T")
      )
      (libsource (lib "Database_Libs1") (part "C"))
    )
    (comp (ref "C42")
      (value "C")
      (footprint "SMD_0603_CAPC1608X95N")
      (fields
        (field (name "DB_PART_NUMBER") "CAP000028169")
        (field (name "DB_VALUE") "470nF")
        (field (name "DB_TOLERANCE") "5%")
        (field (name "DB_VOLTAGE") "16V")
        (field (name "DB_MANUFACTURER_PART") "KEMET    C0603C474J4RAC")
        (field (name "DB_APPROVED_BY") "ISHIDDEN=T")
      )
      (libsource (lib "Database_Libs1") (part "C"))
    )
    (comp (ref "C43")
      (value "C")
      (footprint "SMD_0603_CAPC1608X95N")
      (fields
        (field (name "DB_PART_NUMBER") "CAP000028169")
        (field (name "DB_VALUE") "470nF")
        (field (name "DB_TOLERANCE") "5%")
        (field (name "DB_VOLTAGE") "16V")
        (field (name "DB_MANUFACTURER_PART") "KEMET    C0603C474J4RAC")
        (field (name "DB_APPROVED_BY") "ISHIDDEN=T")
      )
      (libsource (lib "Database_Libs1") (part "C"))
    )
    (comp (ref "C44")
      (value "C")
      (footprint "SMD_0603_CAPC1608X95N")
      (fields
        (field (name "DB_PART_NUMBER") "CAP000028169")
        (field (name "DB_VALUE") "470nF")
        (field (name "DB_TOLERANCE") "5%")
        (field (name "DB_VOLTAGE") "16V")
        (field (name "DB_MANUFACTURER_PART") "KEMET    C0603C474J4RAC")
        (field (name "DB_APPROVED_BY") "ISHIDDEN=T")
      )
      (libsource (lib "Database_Libs1") (part "C"))
    )
    (comp (ref "C45")
      (value "C")
      (footprint "SMD_0603_CAPC1608X95N")
      (fields
        (field (name "DB_PART_NUMBER") "CAP000028169")
        (field (name "DB_VALUE") "470nF")
        (field (name "DB_TOLERANCE") "5%")
        (field (name "DB_VOLTAGE") "16V")
        (field (name "DB_MANUFACTURER_PART") "KEMET    C0603C474J4RAC")
        (field (name "DB_APPROVED_BY") "ISHIDDEN=T")
      )
      (libsource (lib "Database_Libs1") (part "C"))
    )
    (comp (ref "C46")
      (value "C")
      (footprint "SMD_0603_CAPC1608X95N")
      (fields
        (field (name "DB_PART_NUMBER") "CAP000028169")
        (field (name "DB_VALUE") "470nF")
        (field (name "DB_TOLERANCE") "5%")
        (field (name "DB_VOLTAGE") "16V")
        (field (name "DB_MANUFACTURER_PART") "KEMET    C0603C474J4RAC")
        (field (name "DB_APPROVED_BY") "ISHIDDEN=T")
      )
      (libsource (lib "Database_Libs1") (part "C"))
    )
    (comp (ref "C47")
      (value "C")
      (footprint "SMD_0603_CAPC1608X95N")
      (fields
        (field (name "DB_PART_NUMBER") "CAP000028169")
        (field (name "DB_VALUE") "470nF")
        (field (name "DB_TOLERANCE") "5%")
        (field (name "DB_VOLTAGE") "16V")
        (field (name "DB_MANUFACTURER_PART") "KEMET    C0603C474J4RAC")
        (field (name "DB_APPROVED_BY") "ISHIDDEN=T")
      )
      (libsource (lib "Database_Libs1") (part "C"))
    )
    (comp (ref "C48")
      (value "C")
      (footprint "SMD_0603_CAPC1608X95N")
      (fields
        (field (name "DB_PART_NUMBER") "CAP000028169")
        (field (name "DB_VALUE") "470nF")
        (field (name "DB_TOLERANCE") "5%")
        (field (name "DB_VOLTAGE") "16V")
        (field (name "DB_MANUFACTURER_PART") "KEMET    C0603C474J4RAC")
        (field (name "DB_APPROVED_BY") "ISHIDDEN=T")
      )
      (libsource (lib "Database_Libs1") (part "C"))
    )
    (comp (ref "C49")
      (value "C")
      (footprint "SMD_0603_CAPC1608X95N")
      (fields
        (field (name "DB_PART_NUMBER") "CAP000028169")
        (field (name "DB_VALUE") "470nF")
        (field (name "DB_TOLERANCE") "5%")
        (field (name "DB_VOLTAGE") "16V")
        (field (name "DB_MANUFACTURER_PART") "KEMET    C0603C474J4RAC")
        (field (name "DB_APPROVED_BY") "ISHIDDEN=T")
      )
      (libsource (lib "Database_Libs1") (part "C"))
    )
    (comp (ref "C50")
      (value "C")
      (footprint "SMD_0603_CAPC1608X95N")
      (fields
        (field (name "DB_PART_NUMBER") "CAP000028169")
        (field (name "DB_VALUE") "470nF")
        (field (name "DB_TOLERANCE") "5%")
        (field (name "DB_VOLTAGE") "16V")
        (field (name "DB_MANUFACTURER_PART") "KEMET    C0603C474J4RAC")
        (field (name "DB_APPROVED_BY") "ISHIDDEN=T")
      )
      (libsource (lib "Database_Libs1") (part "C"))
    )
    (comp (ref "C51")
      (value "C")
      (footprint "SMD_0603_CAPC1608X95N")
      (fields
        (field (name "DB_PART_NUMBER") "CAP000028169")
        (field (name "DB_VALUE") "470nF")
        (field (name "DB_TOLERANCE") "5%")
        (field (name "DB_VOLTAGE") "16V")
        (field (name "DB_MANUFACTURER_PART") "KEMET    C0603C474J4RAC")
        (field (name "DB_APPROVED_BY") "ISHIDDEN=T")
      )
      (libsource (lib "Database_Libs1") (part "C"))
    )
    (comp (ref "C52")
      (value "C")
      (footprint "SMD_0603_CAPC1608X95N")
      (fields
        (field (name "DB_PART_NUMBER") "CAP000028169")
        (field (name "DB_VALUE") "470nF")
        (field (name "DB_TOLERANCE") "5%")
        (field (name "DB_VOLTAGE") "16V")
        (field (name "DB_MANUFACTURER_PART") "KEMET    C0603C474J4RAC")
        (field (name "DB_APPROVED_BY") "ISHIDDEN=T")
      )
      (libsource (lib "Database_Libs1") (part "C"))
    )
    (comp (ref "C53")
      (value "C")
      (footprint "SMD_0603_CAPC1608X95N")
      (fields
        (field (name "DB_PART_NUMBER") "CAP000028169")
        (field (name "DB_VALUE") "470nF")
        (field (name "DB_TOLERANCE") "5%")
        (field (name "DB_VOLTAGE") "16V")
        (field (name "DB_MANUFACTURER_PART") "KEMET    C0603C474J4RAC")
        (field (name "DB_APPROVED_BY") "ISHIDDEN=T")
      )
      (libsource (lib "Database_Libs1") (part "C"))
    )
    (comp (ref "C54")
      (value "C")
      (footprint "SMD_0603_CAPC1608X95N")
      (fields
        (field (name "DB_PART_NUMBER") "CAP000028169")
        (field (name "DB_VALUE") "470nF")
        (field (name "DB_TOLERANCE") "5%")
        (field (name "DB_VOLTAGE") "16V")
        (field (name "DB_MANUFACTURER_PART") "KEMET    C0603C474J4RAC")
        (field (name "DB_APPROVED_BY") "ISHIDDEN=T")
      )
      (libsource (lib "Database_Libs1") (part "C"))
    )
    (comp (ref "C55")
      (value "C")
      (footprint "SMD_0603_CAPC1608X95N")
      (fields
        (field (name "DB_PART_NUMBER") "CAP000028169")
        (field (name "DB_VALUE") "470nF")
        (field (name "DB_TOLERANCE") "5%")
        (field (name "DB_VOLTAGE") "16V")
        (field (name "DB_MANUFACTURER_PART") "KEMET    C0603C474J4RAC")
        (field (name "DB_APPROVED_BY") "ISHIDDEN=T")
      )
      (libsource (lib "Database_Libs1") (part "C"))
    )
    (comp (ref "C56")
      (value "C")
      (footprint "SMD_0603_CAPC1608X95N")
      (fields
        (field (name "DB_PART_NUMBER") "CAP000028169")
        (field (name "DB_VALUE") "470nF")
        (field (name "DB_TOLERANCE") "5%")
        (field (name "DB_VOLTAGE") "16V")
        (field (name "DB_MANUFACTURER_PART") "KEMET    C0603C474J4RAC")
        (field (name "DB_APPROVED_BY") "ISHIDDEN=T")
      )
      (libsource (lib "Database_Libs1") (part "C"))
    )
    (comp (ref "C57")
      (value "C")
      (footprint "SMD_0603_CAPC1608X95N")
      (fields
        (field (name "DB_PART_NUMBER") "CAP000028169")
        (field (name "DB_VALUE") "470nF")
        (field (name "DB_TOLERANCE") "5%")
        (field (name "DB_VOLTAGE") "16V")
        (field (name "DB_MANUFACTURER_PART") "KEMET    C0603C474J4RAC")
        (field (name "DB_APPROVED_BY") "ISHIDDEN=T")
      )
      (libsource (lib "Database_Libs1") (part "C"))
    )
    (comp (ref "C58")
      (value "C")
      (footprint "SMD_0603_CAPC1608X95N")
      (fields
        (field (name "DB_PART_NUMBER") "CAP000028169")
        (field (name "DB_VALUE") "470nF")
        (field (name "DB_TOLERANCE") "5%")
        (field (name "DB_VOLTAGE") "16V")
        (field (name "DB_MANUFACTURER_PART") "KEMET    C0603C474J4RAC")
        (field (name "DB_APPROVED_BY") "ISHIDDEN=T")
      )
      (libsource (lib "Database_Libs1") (part "C"))
    )
    (comp (ref "C59")
      (value "C")
      (footprint "SMD_0603_CAPC1608X95N")
      (fields
        (field (name "DB_PART_NUMBER") "CAP000028169")
        (field (name "DB_VALUE") "470nF")
        (field (name "DB_TOLERANCE") "5%")
        (field (name "DB_VOLTAGE") "16V")
        (field (name "DB_MANUFACTURER_PART") "KEMET    C0603C474J4RAC")
        (field (name "DB_APPROVED_BY") "ISHIDDEN=T")
      )
      (libsource (lib "Database_Libs1") (part "C"))
    )
    (comp (ref "C60")
      (value "C")
      (footprint "SMD_0603_CAPC1608X95N")
      (fields
        (field (name "DB_PART_NUMBER") "CAP000028169")
        (field (name "DB_VALUE") "470nF")
        (field (name "DB_TOLERANCE") "5%")
        (field (name "DB_VOLTAGE") "16V")
        (field (name "DB_MANUFACTURER_PART") "KEMET    C0603C474J4RAC")
        (field (name "DB_APPROVED_BY") "ISHIDDEN=T")
      )
      (libsource (lib "Database_Libs1") (part "C"))
    )
    (comp (ref "C61")
      (value "C")
      (footprint "SMD_0603_CAPC1608X95N")
      (fields
        (field (name "DB_PART_NUMBER") "CAP000028169")
        (field (name "DB_VALUE") "470nF")
        (field (name "DB_TOLERANCE") "5%")
        (field (name "DB_VOLTAGE") "16V")
        (field (name "DB_MANUFACTURER_PART") "KEMET    C0603C474J4RAC")
        (field (name "DB_APPROVED_BY") "ISHIDDEN=T")
      )
      (libsource (lib "Database_Libs1") (part "C"))
    )
    (comp (ref "C62")
      (value "C")
      (footprint "SMD_0603_CAPC1608X95N")
      (fields
        (field (name "DB_PART_NUMBER") "CAP000028169")
        (field (name "DB_VALUE") "470nF")
        (field (name "DB_TOLERANCE") "5%")
        (field (name "DB_VOLTAGE") "16V")
        (field (name "DB_MANUFACTURER_PART") "KEMET    C0603C474J4RAC")
        (field (name "DB_APPROVED_BY") "ISHIDDEN=T")
      )
      (libsource (lib "Database_Libs1") (part "C"))
    )
    (comp (ref "C63")
      (value "C")
      (footprint "SMD_0603_CAPC1608X95N")
      (fields
        (field (name "DB_PART_NUMBER") "CAP000028169")
        (field (name "DB_VALUE") "470nF")
        (field (name "DB_TOLERANCE") "5%")
        (field (name "DB_VOLTAGE") "16V")
        (field (name "DB_MANUFACTURER_PART") "KEMET    C0603C474J4RAC")
        (field (name "DB_APPROVED_BY") "ISHIDDEN=T")
      )
      (libsource (lib "Database_Libs1") (part "C"))
    )
    (comp (ref "C64")
      (value "C")
      (footprint "SMD_0603_CAPC1608X95N")
      (fields
        (field (name "DB_PART_NUMBER") "CAP000028169")
        (field (name "DB_VALUE") "470nF")
        (field (name "DB_TOLERANCE") "5%")
        (field (name "DB_VOLTAGE") "16V")
        (field (name "DB_MANUFACTURER_PART") "KEMET    C0603C474J4RAC")
        (field (name "DB_APPROVED_BY") "ISHIDDEN=T")
      )
      (libsource (lib "Database_Libs1") (part "C"))
    )
    (comp (ref "C65")
      (value "C")
      (footprint "SMD_0603_CAPC1608X95N")
      (fields
        (field (name "DB_PART_NUMBER") "CAP000028169")
        (field (name "DB_VALUE") "470nF")
        (field (name "DB_TOLERANCE") "5%")
        (field (name "DB_VOLTAGE") "16V")
        (field (name "DB_MANUFACTURER_PART") "KEMET    C0603C474J4RAC")
        (field (name "DB_APPROVED_BY") "ISHIDDEN=T")
      )
      (libsource (lib "Database_Libs1") (part "C"))
    )
    (comp (ref "C66")
      (value "C")
      (footprint "SMD_0603_CAPC1608X95N")
      (fields
        (field (name "DB_PART_NUMBER") "CAP000028169")
        (field (name "DB_VALUE") "470nF")
        (field (name "DB_TOLERANCE") "5%")
        (field (name "DB_VOLTAGE") "16V")
        (field (name "DB_MANUFACTURER_PART") "KEMET    C0603C474J4RAC")
        (field (name "DB_APPROVED_BY") "ISHIDDEN=T")
      )
      (libsource (lib "Database_Libs1") (part "C"))
    )
    (comp (ref "C67")
      (value "C")
      (footprint "SMD_0603_CAPC1608X95N")
      (fields
        (field (name "DB_PART_NUMBER") "CAP000028169")
        (field (name "DB_VALUE") "470nF")
        (field (name "DB_TOLERANCE") "5%")
        (field (name "DB_VOLTAGE") "16V")
        (field (name "DB_MANUFACTURER_PART") "KEMET    C0603C474J4RAC")
        (field (name "DB_APPROVED_BY") "ISHIDDEN=T")
      )
      (libsource (lib "Database_Libs1") (part "C"))
    )
    (comp (ref "C68")
      (value "C")
      (footprint "SMD_0603_CAPC1608X95N")
      (fields
        (field (name "DB_PART_NUMBER") "CAP000028169")
        (field (name "DB_VALUE") "470nF")
        (field (name "DB_TOLERANCE") "5%")
        (field (name "DB_VOLTAGE") "16V")
        (field (name "DB_MANUFACTURER_PART") "KEMET    C0603C474J4RAC")
        (field (name "DB_APPROVED_BY") "ISHIDDEN=T")
      )
      (libsource (lib "Database_Libs1") (part "C"))
    )
    (comp (ref "C69")
      (value "C")
      (footprint "SMD_0805_CAPC2012X145N")
      (fields
        (field (name "DB_PART_NUMBER") "CAP000043636")
        (field (name "DB_VALUE") "10uF")
        (field (name "DB_TOLERANCE") "10%")
        (field (name "DB_VOLTAGE") "16V")
        (field (name "DB_MANUFACTURER_PART") "KEMET    C0805C106K4PAC")
        (field (name "DB_APPROVED_BY") "ISHIDDEN=T")
      )
      (libsource (lib "Database_Libs1") (part "C"))
    )
    (comp (ref "C70")
      (value "C")
      (footprint "SMD_0603_CAPC1608X95N")
      (fields
        (field (name "DB_PART_NUMBER") "CAP000028169")
        (field (name "DB_VALUE") "470nF")
        (field (name "DB_TOLERANCE") "5%")
        (field (name "DB_VOLTAGE") "16V")
        (field (name "DB_MANUFACTURER_PART") "KEMET    C0603C474J4RAC")
        (field (name "DB_APPROVED_BY") "ISHIDDEN=T")
      )
      (libsource (lib "Database_Libs1") (part "C"))
    )
    (comp (ref "C71")
      (value "C")
      (footprint "SMD_0603_CAPC1608X95N")
      (fields
        (field (name "DB_PART_NUMBER") "CAP000028169")
        (field (name "DB_VALUE") "470nF")
        (field (name "DB_TOLERANCE") "5%")
        (field (name "DB_VOLTAGE") "16V")
        (field (name "DB_MANUFACTURER_PART") "KEMET    C0603C474J4RAC")
        (field (name "DB_APPROVED_BY") "ISHIDDEN=T")
      )
      (libsource (lib "Database_Libs1") (part "C"))
    )
    (comp (ref "C72")
      (value "C")
      (footprint "SMD_0603_CAPC1608X95N")
      (fields
        (field (name "DB_PART_NUMBER") "CAP000028169")
        (field (name "DB_VALUE") "470nF")
        (field (name "DB_TOLERANCE") "5%")
        (field (name "DB_VOLTAGE") "16V")
        (field (name "DB_MANUFACTURER_PART") "KEMET    C0603C474J4RAC")
        (field (name "DB_APPROVED_BY") "ISHIDDEN=T")
      )
      (libsource (lib "Database_Libs1") (part "C"))
    )
    (comp (ref "C73")
      (value "C")
      (footprint "SMD_0603_CAPC1608X95N")
      (fields
        (field (name "DB_PART_NUMBER") "CAP000028169")
        (field (name "DB_VALUE") "470nF")
        (field (name "DB_TOLERANCE") "5%")
        (field (name "DB_VOLTAGE") "16V")
        (field (name "DB_MANUFACTURER_PART") "KEMET    C0603C474J4RAC")
        (field (name "DB_APPROVED_BY") "ISHIDDEN=T")
      )
      (libsource (lib "Database_Libs1") (part "C"))
    )
    (comp (ref "C74")
      (value "C")
      (footprint "SMD_0603_CAPC1608X95N")
      (fields
        (field (name "DB_PART_NUMBER") "CAP000028169")
        (field (name "DB_VALUE") "470nF")
        (field (name "DB_TOLERANCE") "5%")
        (field (name "DB_VOLTAGE") "16V")
        (field (name "DB_MANUFACTURER_PART") "KEMET    C0603C474J4RAC")
        (field (name "DB_APPROVED_BY") "ISHIDDEN=T")
      )
      (libsource (lib "Database_Libs1") (part "C"))
    )
    (comp (ref "C75")
      (value "C")
      (footprint "SMD_0603_CAPC1608X95N")
      (fields
        (field (name "DB_PART_NUMBER") "CAP000028169")
        (field (name "DB_VALUE") "470nF")
        (field (name "DB_TOLERANCE") "5%")
        (field (name "DB_VOLTAGE") "16V")
        (field (name "DB_MANUFACTURER_PART") "KEMET    C0603C474J4RAC")
        (field (name "DB_APPROVED_BY") "ISHIDDEN=T")
      )
      (libsource (lib "Database_Libs1") (part "C"))
    )
    (comp (ref "C76")
      (value "C")
      (footprint "SMD_0603_CAPC1608X95N")
      (fields
        (field (name "DB_PART_NUMBER") "CAP000028169")
        (field (name "DB_VALUE") "470nF")
        (field (name "DB_TOLERANCE") "5%")
        (field (name "DB_VOLTAGE") "16V")
        (field (name "DB_MANUFACTURER_PART") "KEMET    C0603C474J4RAC")
        (field (name "DB_APPROVED_BY") "ISHIDDEN=T")
      )
      (libsource (lib "Database_Libs1") (part "C"))
    )
    (comp (ref "C77")
      (value "C")
      (footprint "SMD_0603_CAPC1608X95N")
      (fields
        (field (name "DB_PART_NUMBER") "CAP000028169")
        (field (name "DB_VALUE") "470nF")
        (field (name "DB_TOLERANCE") "5%")
        (field (name "DB_VOLTAGE") "16V")
        (field (name "DB_MANUFACTURER_PART") "KEMET    C0603C474J4RAC")
        (field (name "DB_APPROVED_BY") "ISHIDDEN=T")
      )
      (libsource (lib "Database_Libs1") (part "C"))
    )
    (comp (ref "C78")
      (value "C")
      (footprint "SMD_0603_CAPC1608X95N")
      (fields
        (field (name "DB_PART_NUMBER") "CAP000028169")
        (field (name "DB_VALUE") "470nF")
        (field (name "DB_TOLERANCE") "5%")
        (field (name "DB_VOLTAGE") "16V")
        (field (name "DB_MANUFACTURER_PART") "KEMET    C0603C474J4RAC")
        (field (name "DB_APPROVED_BY") "ISHIDDEN=T")
      )
      (libsource (lib "Database_Libs1") (part "C"))
    )
    (comp (ref "C79")
      (value "C")
      (footprint "SMD_0603_CAPC1608X95N")
      (fields
        (field (name "DB_PART_NUMBER") "CAP000028169")
        (field (name "DB_VALUE") "470nF")
        (field (name "DB_TOLERANCE") "5%")
        (field (name "DB_VOLTAGE") "16V")
        (field (name "DB_MANUFACTURER_PART") "KEMET    C0603C474J4RAC")
        (field (name "DB_APPROVED_BY") "ISHIDDEN=T")
      )
      (libsource (lib "Database_Libs1") (part "C"))
    )
    (comp (ref "C80")
      (value "C")
      (footprint "SMD_0603_CAPC1608X95N")
      (fields
        (field (name "DB_PART_NUMBER") "CAP000028169")
        (field (name "DB_VALUE") "470nF")
        (field (name "DB_TOLERANCE") "5%")
        (field (name "DB_VOLTAGE") "16V")
        (field (name "DB_MANUFACTURER_PART") "KEMET    C0603C474J4RAC")
        (field (name "DB_APPROVED_BY") "ISHIDDEN=T")
      )
      (libsource (lib "Database_Libs1") (part "C"))
    )
    (comp (ref "C81")
      (value "C")
      (footprint "SMD_0603_CAPC1608X95N")
      (fields
        (field (name "DB_PART_NUMBER") "CAP000028169")
        (field (name "DB_VALUE") "470nF")
        (field (name "DB_TOLERANCE") "5%")
        (field (name "DB_VOLTAGE") "16V")
        (field (name "DB_MANUFACTURER_PART") "KEMET    C0603C474J4RAC")
        (field (name "DB_APPROVED_BY") "ISHIDDEN=T")
      )
      (libsource (lib "Database_Libs1") (part "C"))
    )
    (comp (ref "C82")
      (value "C")
      (footprint "SMD_0603_CAPC1608X95N")
      (fields
        (field (name "DB_PART_NUMBER") "CAP000028169")
        (field (name "DB_VALUE") "470nF")
        (field (name "DB_TOLERANCE") "5%")
        (field (name "DB_VOLTAGE") "16V")
        (field (name "DB_MANUFACTURER_PART") "KEMET    C0603C474J4RAC")
        (field (name "DB_APPROVED_BY") "ISHIDDEN=T")
      )
      (libsource (lib "Database_Libs1") (part "C"))
    )
    (comp (ref "C83")
      (value "C")
      (footprint "SMD_0603_CAPC1608X95N")
      (fields
        (field (name "DB_PART_NUMBER") "CAP000028169")
        (field (name "DB_VALUE") "470nF")
        (field (name "DB_TOLERANCE") "5%")
        (field (name "DB_VOLTAGE") "16V")
        (field (name "DB_MANUFACTURER_PART") "KEMET    C0603C474J4RAC")
        (field (name "DB_APPROVED_BY") "ISHIDDEN=T")
      )
      (libsource (lib "Database_Libs1") (part "C"))
    )
    (comp (ref "C84")
      (value "C")
      (footprint "SMD_0603_CAPC1608X95N")
      (fields
        (field (name "DB_PART_NUMBER") "CAP000028169")
        (field (name "DB_VALUE") "470nF")
        (field (name "DB_TOLERANCE") "5%")
        (field (name "DB_VOLTAGE") "16V")
        (field (name "DB_MANUFACTURER_PART") "KEMET    C0603C474J4RAC")
        (field (name "DB_APPROVED_BY") "ISHIDDEN=T")
      )
      (libsource (lib "Database_Libs1") (part "C"))
    )
    (comp (ref "C85")
      (value "C")
      (footprint "SMD_0603_CAPC1608X95N")
      (fields
        (field (name "DB_PART_NUMBER") "CAP000028169")
        (field (name "DB_VALUE") "470nF")
        (field (name "DB_TOLERANCE") "5%")
        (field (name "DB_VOLTAGE") "16V")
        (field (name "DB_MANUFACTURER_PART") "KEMET    C0603C474J4RAC")
        (field (name "DB_APPROVED_BY") "ISHIDDEN=T")
      )
      (libsource (lib "Database_Libs1") (part "C"))
    )
    (comp (ref "C118")
      (value "C")
      (footprint "SMD_0603_CAPC1608X95N")
      (fields
        (field (name "DB_PART_NUMBER") "CAP000028169")
        (field (name "DB_VALUE") "470nF")
        (field (name "DB_TOLERANCE") "5%")
        (field (name "DB_VOLTAGE") "16V")
        (field (name "DB_MANUFACTURER_PART") "KEMET    C0603C474J4RAC")
        (field (name "DB_APPROVED_BY") "ISHIDDEN=T")
      )
      (libsource (lib "Database_Libs1") (part "C"))
    )
    (comp (ref "C119")
      (value "C")
      (footprint "SMD_0603_CAPC1608X95N")
      (fields
        (field (name "DB_PART_NUMBER") "CAP000028169")
        (field (name "DB_VALUE") "470nF")
        (field (name "DB_TOLERANCE") "5%")
        (field (name "DB_VOLTAGE") "16V")
        (field (name "DB_MANUFACTURER_PART") "KEMET    C0603C474J4RAC")
        (field (name "DB_APPROVED_BY") "ISHIDDEN=T")
      )
      (libsource (lib "Database_Libs1") (part "C"))
    )
    (comp (ref "C120")
      (value "C")
      (footprint "SMD_0603_CAPC1608X95N")
      (fields
        (field (name "DB_PART_NUMBER") "CAP000028169")
        (field (name "DB_VALUE") "470nF")
        (field (name "DB_TOLERANCE") "5%")
        (field (name "DB_VOLTAGE") "16V")
        (field (name "DB_MANUFACTURER_PART") "KEMET    C0603C474J4RAC")
        (field (name "DB_APPROVED_BY") "ISHIDDEN=T")
      )
      (libsource (lib "Database_Libs1") (part "C"))
    )
    (comp (ref "C121")
      (value "C")
      (footprint "SMD_0603_CAPC1608X95N")
      (fields
        (field (name "DB_PART_NUMBER") "CAP000028169")
        (field (name "DB_VALUE") "470nF")
        (field (name "DB_TOLERANCE") "5%")
        (field (name "DB_VOLTAGE") "16V")
        (field (name "DB_MANUFACTURER_PART") "KEMET    C0603C474J4RAC")
        (field (name "DB_APPROVED_BY") "ISHIDDEN=T")
      )
      (libsource (lib "Database_Libs1") (part "C"))
    )
    (comp (ref "C122")
      (value "C")
      (footprint "SMD_0603_CAPC1608X95N")
      (fields
        (field (name "DB_PART_NUMBER") "CAP000028169")
        (field (name "DB_VALUE") "470nF")
        (field (name "DB_TOLERANCE") "5%")
        (field (name "DB_VOLTAGE") "16V")
        (field (name "DB_MANUFACTURER_PART") "KEMET    C0603C474J4RAC")
        (field (name "DB_APPROVED_BY") "ISHIDDEN=T")
      )
      (libsource (lib "Database_Libs1") (part "C"))
    )
    (comp (ref "C123")
      (value "C")
      (footprint "SMD_0603_CAPC1608X95N")
      (fields
        (field (name "DB_PART_NUMBER") "CAP000028169")
        (field (name "DB_VALUE") "470nF")
        (field (name "DB_TOLERANCE") "5%")
        (field (name "DB_VOLTAGE") "16V")
        (field (name "DB_MANUFACTURER_PART") "KEMET    C0603C474J4RAC")
        (field (name "DB_APPROVED_BY") "ISHIDDEN=T")
      )
      (libsource (lib "Database_Libs1") (part "C"))
    )
    (comp (ref "C124")
      (value "C")
      (footprint "SMD_0603_CAPC1608X95N")
      (fields
        (field (name "DB_PART_NUMBER") "CAP000028169")
        (field (name "DB_VALUE") "470nF")
        (field (name "DB_TOLERANCE") "5%")
        (field (name "DB_VOLTAGE") "16V")
        (field (name "DB_MANUFACTURER_PART") "KEMET    C0603C474J4RAC")
        (field (name "DB_APPROVED_BY") "ISHIDDEN=T")
      )
      (libsource (lib "Database_Libs1") (part "C"))
    )
    (comp (ref "C125")
      (value "C")
      (footprint "SMD_0603_CAPC1608X95N")
      (fields
        (field (name "DB_PART_NUMBER") "CAP000028169")
        (field (name "DB_VALUE") "470nF")
        (field (name "DB_TOLERANCE") "5%")
        (field (name "DB_VOLTAGE") "16V")
        (field (name "DB_MANUFACTURER_PART") "KEMET    C0603C474J4RAC")
        (field (name "DB_APPROVED_BY") "ISHIDDEN=T")
      )
      (libsource (lib "Database_Libs1") (part "C"))
    )
    (comp (ref "C126")
      (value "C")
      (footprint "SMD_0603_CAPC1608X95N")
      (fields
        (field (name "DB_PART_NUMBER") "CAP000028169")
        (field (name "DB_VALUE") "470nF")
        (field (name "DB_TOLERANCE") "5%")
        (field (name "DB_VOLTAGE") "16V")
        (field (name "DB_MANUFACTURER_PART") "KEMET    C0603C474J4RAC")
        (field (name "DB_APPROVED_BY") "ISHIDDEN=T")
      )
      (libsource (lib "Database_Libs1") (part "C"))
    )
    (comp (ref "C127")
      (value "C")
      (footprint "SMD_0603_CAPC1608X95N")
      (fields
        (field (name "DB_PART_NUMBER") "CAP000028169")
        (field (name "DB_VALUE") "470nF")
        (field (name "DB_TOLERANCE") "5%")
        (field (name "DB_VOLTAGE") "16V")
        (field (name "DB_MANUFACTURER_PART") "KEMET    C0603C474J4RAC")
        (field (name "DB_APPROVED_BY") "ISHIDDEN=T")
      )
      (libsource (lib "Database_Libs1") (part "C"))
    )
    (comp (ref "C128")
      (value "C")
      (footprint "SMD_0603_CAPC1608X95N")
      (fields
        (field (name "DB_PART_NUMBER") "CAP000028169")
        (field (name "DB_VALUE") "470nF")
        (field (name "DB_TOLERANCE") "5%")
        (field (name "DB_VOLTAGE") "16V")
        (field (name "DB_MANUFACTURER_PART") "KEMET    C0603C474J4RAC")
        (field (name "DB_APPROVED_BY") "ISHIDDEN=T")
      )
      (libsource (lib "Database_Libs1") (part "C"))
    )
    (comp (ref "C129")
      (value "C")
      (footprint "SMD_0603_CAPC1608X95N")
      (fields
        (field (name "DB_PART_NUMBER") "CAP000028169")
        (field (name "DB_VALUE") "470nF")
        (field (name "DB_TOLERANCE") "5%")
        (field (name "DB_VOLTAGE") "16V")
        (field (name "DB_MANUFACTURER_PART") "KEMET    C0603C474J4RAC")
        (field (name "DB_APPROVED_BY") "ISHIDDEN=T")
      )
      (libsource (lib "Database_Libs1") (part "C"))
    )
    (comp (ref "C130")
      (value "C")
      (footprint "SMD_0603_CAPC1608X95N")
      (fields
        (field (name "DB_PART_NUMBER") "CAP000028169")
        (field (name "DB_VALUE") "470nF")
        (field (name "DB_TOLERANCE") "5%")
        (field (name "DB_VOLTAGE") "16V")
        (field (name "DB_MANUFACTURER_PART") "KEMET    C0603C474J4RAC")
        (field (name "DB_APPROVED_BY") "ISHIDDEN=T")
      )
      (libsource (lib "Database_Libs1") (part "C"))
    )
    (comp (ref "C131")
      (value "C")
      (footprint "SMD_0603_CAPC1608X95N")
      (fields
        (field (name "DB_PART_NUMBER") "CAP000028169")
        (field (name "DB_VALUE") "470nF")
        (field (name "DB_TOLERANCE") "5%")
        (field (name "DB_VOLTAGE") "16V")
        (field (name "DB_MANUFACTURER_PART") "KEMET    C0603C474J4RAC")
        (field (name "DB_APPROVED_BY") "ISHIDDEN=T")
      )
      (libsource (lib "Database_Libs1") (part "C"))
    )
    (comp (ref "C132")
      (value "C")
      (footprint "SMD_0603_CAPC1608X95N")
      (fields
        (field (name "DB_PART_NUMBER") "CAP000028169")
        (field (name "DB_VALUE") "470nF")
        (field (name "DB_TOLERANCE") "5%")
        (field (name "DB_VOLTAGE") "16V")
        (field (name "DB_MANUFACTURER_PART") "KEMET    C0603C474J4RAC")
        (field (name "DB_APPROVED_BY") "ISHIDDEN=T")
      )
      (libsource (lib "Database_Libs1") (part "C"))
    )
    (comp (ref "C133")
      (value "C")
      (footprint "SMD_0603_CAPC1608X95N")
      (fields
        (field (name "DB_PART_NUMBER") "CAP000028169")
        (field (name "DB_VALUE") "470nF")
        (field (name "DB_TOLERANCE") "5%")
        (field (name "DB_VOLTAGE") "16V")
        (field (name "DB_MANUFACTURER_PART") "KEMET    C0603C474J4RAC")
        (field (name "DB_APPROVED_BY") "ISHIDDEN=T")
      )
      (libsource (lib "Database_Libs1") (part "C"))
    )
    (comp (ref "C134")
      (value "C")
      (footprint "SMD_0603_CAPC1608X95N")
      (fields
        (field (name "DB_PART_NUMBER") "CAP000028169")
        (field (name "DB_VALUE") "470nF")
        (field (name "DB_TOLERANCE") "5%")
        (field (name "DB_VOLTAGE") "16V")
        (field (name "DB_MANUFACTURER_PART") "KEMET    C0603C474J4RAC")
        (field (name "DB_APPROVED_BY") "ISHIDDEN=T")
      )
      (libsource (lib "Database_Libs1") (part "C"))
    )
    (comp (ref "C135")
      (value "C")
      (footprint "SMD_0603_CAPC1608X95N")
      (fields
        (field (name "DB_PART_NUMBER") "CAP000028169")
        (field (name "DB_VALUE") "470nF")
        (field (name "DB_TOLERANCE") "5%")
        (field (name "DB_VOLTAGE") "16V")
        (field (name "DB_MANUFACTURER_PART") "KEMET    C0603C474J4RAC")
        (field (name "DB_APPROVED_BY") "ISHIDDEN=T")
      )
      (libsource (lib "Database_Libs1") (part "C"))
    )
    (comp (ref "C136")
      (value "C")
      (footprint "SMD_0603_CAPC1608X95N")
      (fields
        (field (name "DB_PART_NUMBER") "CAP000028169")
        (field (name "DB_VALUE") "470nF")
        (field (name "DB_TOLERANCE") "5%")
        (field (name "DB_VOLTAGE") "16V")
        (field (name "DB_MANUFACTURER_PART") "KEMET    C0603C474J4RAC")
        (field (name "DB_APPROVED_BY") "ISHIDDEN=T")
      )
      (libsource (lib "Database_Libs1") (part "C"))
    )
    (comp (ref "C137")
      (value "C")
      (footprint "SMD_0603_CAPC1608X95N")
      (fields
        (field (name "DB_PART_NUMBER") "CAP000028169")
        (field (name "DB_VALUE") "470nF")
        (field (name "DB_TOLERANCE") "5%")
        (field (name "DB_VOLTAGE") "16V")
        (field (name "DB_MANUFACTURER_PART") "KEMET    C0603C474J4RAC")
        (field (name "DB_APPROVED_BY") "ISHIDDEN=T")
      )
      (libsource (lib "Database_Libs1") (part "C"))
    )
    (comp (ref "C138")
      (value "C")
      (footprint "SMD_0603_CAPC1608X95N")
      (fields
        (field (name "DB_PART_NUMBER") "CAP000024113")
        (field (name "DB_VALUE") "1nF")
        (field (name "DB_TOLERANCE") "5%")
        (field (name "DB_VOLTAGE") "25V")
        (field (name "DB_MANUFACTURER_PART") "KEMET    C0603C102J3RAC")
        (field (name "DB_APPROVED_BY") "ISHIDDEN=T")
      )
      (libsource (lib "Database_Libs1") (part "C"))
    )
    (comp (ref "C139")
      (value "C")
      (footprint "SMD_0805_CAPC2012X145N")
      (fields
        (field (name "DB_PART_NUMBER") "CAP000043636")
        (field (name "DB_VALUE") "10uF")
        (field (name "DB_TOLERANCE") "10%")
        (field (name "DB_VOLTAGE") "16V")
        (field (name "DB_MANUFACTURER_PART") "KEMET    C0805C106K4PAC")
        (field (name "DB_APPROVED_BY") "ISHIDDEN=T")
      )
      (libsource (lib "Database_Libs1") (part "C"))
    )
    (comp (ref "C140")
      (value "C")
      (footprint "SMD_0603_CAPC1608X95N")
      (fields
        (field (name "DB_PART_NUMBER") "CAP000028169")
        (field (name "DB_VALUE") "470nF")
        (field (name "DB_TOLERANCE") "5%")
        (field (name "DB_VOLTAGE") "16V")
        (field (name "DB_MANUFACTURER_PART") "KEMET    C0603C474J4RAC")
        (field (name "DB_APPROVED_BY") "ISHIDDEN=T")
      )
      (libsource (lib "Database_Libs1") (part "C"))
    )
    (comp (ref "C141")
      (value "C")
      (footprint "SMD_0603_CAPC1608X95N")
      (fields
        (field (name "DB_PART_NUMBER") "CAP000028169")
        (field (name "DB_VALUE") "470nF")
        (field (name "DB_TOLERANCE") "5%")
        (field (name "DB_VOLTAGE") "16V")
        (field (name "DB_MANUFACTURER_PART") "KEMET    C0603C474J4RAC")
        (field (name "DB_APPROVED_BY") "ISHIDDEN=T")
      )
      (libsource (lib "Database_Libs1") (part "C"))
    )
    (comp (ref "C142")
      (value "C")
      (footprint "SMD_0603_CAPC1608X95N")
      (fields
        (field (name "DB_PART_NUMBER") "CAP000028169")
        (field (name "DB_VALUE") "470nF")
        (field (name "DB_TOLERANCE") "5%")
        (field (name "DB_VOLTAGE") "16V")
        (field (name "DB_MANUFACTURER_PART") "KEMET    C0603C474J4RAC")
        (field (name "DB_APPROVED_BY") "ISHIDDEN=T")
      )
      (libsource (lib "Database_Libs1") (part "C"))
    )
    (comp (ref "C143")
      (value "C")
      (footprint "SMD_0603_CAPC1608X95N")
      (fields
        (field (name "DB_PART_NUMBER") "CAP000028169")
        (field (name "DB_VALUE") "470nF")
        (field (name "DB_TOLERANCE") "5%")
        (field (name "DB_VOLTAGE") "16V")
        (field (name "DB_MANUFACTURER_PART") "KEMET    C0603C474J4RAC")
        (field (name "DB_APPROVED_BY") "ISHIDDEN=T")
      )
      (libsource (lib "Database_Libs1") (part "C"))
    )
    (comp (ref "C144")
      (value "C")
      (footprint "SMD_0603_CAPC1608X95N")
      (fields
        (field (name "DB_PART_NUMBER") "CAP000028169")
        (field (name "DB_VALUE") "470nF")
        (field (name "DB_TOLERANCE") "5%")
        (field (name "DB_VOLTAGE") "16V")
        (field (name "DB_MANUFACTURER_PART") "KEMET    C0603C474J4RAC")
        (field (name "DB_APPROVED_BY") "ISHIDDEN=T")
      )
      (libsource (lib "Database_Libs1") (part "C"))
    )
    (comp (ref "C145")
      (value "C")
      (footprint "SMD_0603_CAPC1608X95N")
      (fields
        (field (name "DB_PART_NUMBER") "CAP000028169")
        (field (name "DB_VALUE") "470nF")
        (field (name "DB_TOLERANCE") "5%")
        (field (name "DB_VOLTAGE") "16V")
        (field (name "DB_MANUFACTURER_PART") "KEMET    C0603C474J4RAC")
        (field (name "DB_APPROVED_BY") "ISHIDDEN=T")
      )
      (libsource (lib "Database_Libs1") (part "C"))
    )
    (comp (ref "C146")
      (value "C")
      (footprint "SMD_0603_CAPC1608X95N")
      (fields
        (field (name "DB_PART_NUMBER") "CAP000028169")
        (field (name "DB_VALUE") "470nF")
        (field (name "DB_TOLERANCE") "5%")
        (field (name "DB_VOLTAGE") "16V")
        (field (name "DB_MANUFACTURER_PART") "KEMET    C0603C474J4RAC")
        (field (name "DB_APPROVED_BY") "ISHIDDEN=T")
      )
      (libsource (lib "Database_Libs1") (part "C"))
    )
    (comp (ref "C147")
      (value "C")
      (footprint "SMD_0603_CAPC1608X95N")
      (fields
        (field (name "DB_PART_NUMBER") "CAP000028169")
        (field (name "DB_VALUE") "470nF")
        (field (name "DB_TOLERANCE") "5%")
        (field (name "DB_VOLTAGE") "16V")
        (field (name "DB_MANUFACTURER_PART") "KEMET    C0603C474J4RAC")
        (field (name "DB_APPROVED_BY") "ISHIDDEN=T")
      )
      (libsource (lib "Database_Libs1") (part "C"))
    )
    (comp (ref "C148")
      (value "C")
      (footprint "SMD_0603_CAPC1608X95N")
      (fields
        (field (name "DB_PART_NUMBER") "CAP000028169")
        (field (name "DB_VALUE") "470nF")
        (field (name "DB_TOLERANCE") "5%")
        (field (name "DB_VOLTAGE") "16V")
        (field (name "DB_MANUFACTURER_PART") "KEMET    C0603C474J4RAC")
        (field (name "DB_APPROVED_BY") "ISHIDDEN=T")
      )
      (libsource (lib "Database_Libs1") (part "C"))
    )
    (comp (ref "C149")
      (value "C")
      (footprint "SMD_0603_CAPC1608X95N")
      (fields
        (field (name "DB_PART_NUMBER") "CAP000028169")
        (field (name "DB_VALUE") "470nF")
        (field (name "DB_TOLERANCE") "5%")
        (field (name "DB_VOLTAGE") "16V")
        (field (name "DB_MANUFACTURER_PART") "KEMET    C0603C474J4RAC")
        (field (name "DB_APPROVED_BY") "ISHIDDEN=T")
      )
      (libsource (lib "Database_Libs1") (part "C"))
    )
    (comp (ref "C150")
      (value "C")
      (footprint "SMD_0603_CAPC1608X95N")
      (fields
        (field (name "DB_PART_NUMBER") "CAP000028169")
        (field (name "DB_VALUE") "470nF")
        (field (name "DB_TOLERANCE") "5%")
        (field (name "DB_VOLTAGE") "16V")
        (field (name "DB_MANUFACTURER_PART") "KEMET    C0603C474J4RAC")
        (field (name "DB_APPROVED_BY") "ISHIDDEN=T")
      )
      (libsource (lib "Database_Libs1") (part "C"))
    )
    (comp (ref "C151")
      (value "C")
      (footprint "SMD_0603_CAPC1608X95N")
      (fields
        (field (name "DB_PART_NUMBER") "CAP000028169")
        (field (name "DB_VALUE") "470nF")
        (field (name "DB_TOLERANCE") "5%")
        (field (name "DB_VOLTAGE") "16V")
        (field (name "DB_MANUFACTURER_PART") "KEMET    C0603C474J4RAC")
        (field (name "DB_APPROVED_BY") "ISHIDDEN=T")
      )
      (libsource (lib "Database_Libs1") (part "C"))
    )
    (comp (ref "C152")
      (value "C")
      (footprint "SMD_0603_CAPC1608X95N")
      (fields
        (field (name "DB_PART_NUMBER") "CAP000028169")
        (field (name "DB_VALUE") "470nF")
        (field (name "DB_TOLERANCE") "5%")
        (field (name "DB_VOLTAGE") "16V")
        (field (name "DB_MANUFACTURER_PART") "KEMET    C0603C474J4RAC")
        (field (name "DB_APPROVED_BY") "ISHIDDEN=T")
      )
      (libsource (lib "Database_Libs1") (part "C"))
    )
    (comp (ref "C153")
      (value "C")
      (footprint "SMD_0603_CAPC1608X95N")
      (fields
        (field (name "DB_PART_NUMBER") "CAP000028169")
        (field (name "DB_VALUE") "470nF")
        (field (name "DB_TOLERANCE") "5%")
        (field (name "DB_VOLTAGE") "16V")
        (field (name "DB_MANUFACTURER_PART") "KEMET    C0603C474J4RAC")
        (field (name "DB_APPROVED_BY") "ISHIDDEN=T")
      )
      (libsource (lib "Database_Libs1") (part "C"))
    )
    (comp (ref "C154")
      (value "C")
      (footprint "SMD_0603_CAPC1608X95N")
      (fields
        (field (name "DB_PART_NUMBER") "CAP000028169")
        (field (name "DB_VALUE") "470nF")
        (field (name "DB_TOLERANCE") "5%")
        (field (name "DB_VOLTAGE") "16V")
        (field (name "DB_MANUFACTURER_PART") "KEMET    C0603C474J4RAC")
        (field (name "DB_APPROVED_BY") "ISHIDDEN=T")
      )
      (libsource (lib "Database_Libs1") (part "C"))
    )
    (comp (ref "C155")
      (value "C")
      (footprint "SMD_0603_CAPC1608X95N")
      (fields
        (field (name "DB_PART_NUMBER") "CAP000028169")
        (field (name "DB_VALUE") "470nF")
        (field (name "DB_TOLERANCE") "5%")
        (field (name "DB_VOLTAGE") "16V")
        (field (name "DB_MANUFACTURER_PART") "KEMET    C0603C474J4RAC")
        (field (name "DB_APPROVED_BY") "ISHIDDEN=T")
      )
      (libsource (lib "Database_Libs1") (part "C"))
    )
    (comp (ref "C156")
      (value "C")
      (footprint "SMD_0603_CAPC1608X95N")
      (fields
        (field (name "DB_PART_NUMBER") "CAP000028169")
        (field (name "DB_VALUE") "470nF")
        (field (name "DB_TOLERANCE") "5%")
        (field (name "DB_VOLTAGE") "16V")
        (field (name "DB_MANUFACTURER_PART") "KEMET    C0603C474J4RAC")
        (field (name "DB_APPROVED_BY") "ISHIDDEN=T")
      )
      (libsource (lib "Database_Libs1") (part "C"))
    )
    (comp (ref "C157")
      (value "C")
      (footprint "SMD_0603_CAPC1608X95N")
      (fields
        (field (name "DB_PART_NUMBER") "CAP000028169")
        (field (name "DB_VALUE") "470nF")
        (field (name "DB_TOLERANCE") "5%")
        (field (name "DB_VOLTAGE") "16V")
        (field (name "DB_MANUFACTURER_PART") "KEMET    C0603C474J4RAC")
        (field (name "DB_APPROVED_BY") "ISHIDDEN=T")
      )
      (libsource (lib "Database_Libs1") (part "C"))
    )
    (comp (ref "C158")
      (value "C")
      (footprint "SMD_0603_CAPC1608X95N")
      (fields
        (field (name "DB_PART_NUMBER") "CAP000028169")
        (field (name "DB_VALUE") "470nF")
        (field (name "DB_TOLERANCE") "5%")
        (field (name "DB_VOLTAGE") "16V")
        (field (name "DB_MANUFACTURER_PART") "KEMET    C0603C474J4RAC")
        (field (name "DB_APPROVED_BY") "ISHIDDEN=T")
      )
      (libsource (lib "Database_Libs1") (part "C"))
    )
    (comp (ref "C159")
      (value "C")
      (footprint "SMD_0603_CAPC1608X95N")
      (fields
        (field (name "DB_PART_NUMBER") "CAP000028169")
        (field (name "DB_VALUE") "470nF")
        (field (name "DB_TOLERANCE") "5%")
        (field (name "DB_VOLTAGE") "16V")
        (field (name "DB_MANUFACTURER_PART") "KEMET    C0603C474J4RAC")
        (field (name "DB_APPROVED_BY") "ISHIDDEN=T")
      )
      (libsource (lib "Database_Libs1") (part "C"))
    )
    (comp (ref "C160")
      (value "C")
      (footprint "SMD_0603_CAPC1608X95N")
      (fields
        (field (name "DB_PART_NUMBER") "CAP000028169")
        (field (name "DB_VALUE") "470nF")
        (field (name "DB_TOLERANCE") "5%")
        (field (name "DB_VOLTAGE") "16V")
        (field (name "DB_MANUFACTURER_PART") "KEMET    C0603C474J4RAC")
        (field (name "DB_APPROVED_BY") "ISHIDDEN=T")
      )
      (libsource (lib "Database_Libs1") (part "C"))
    )
    (comp (ref "C161")
      (value "C")
      (footprint "SMD_0603_CAPC1608X95N")
      (fields
        (field (name "DB_PART_NUMBER") "CAP000028169")
        (field (name "DB_VALUE") "470nF")
        (field (name "DB_TOLERANCE") "5%")
        (field (name "DB_VOLTAGE") "16V")
        (field (name "DB_MANUFACTURER_PART") "KEMET    C0603C474J4RAC")
        (field (name "DB_APPROVED_BY") "ISHIDDEN=T")
      )
      (libsource (lib "Database_Libs1") (part "C"))
    )
    (comp (ref "C162")
      (value "C")
      (footprint "SMD_0603_CAPC1608X95N")
      (fields
        (field (name "DB_PART_NUMBER") "CAP000028169")
        (field (name "DB_VALUE") "470nF")
        (field (name "DB_TOLERANCE") "5%")
        (field (name "DB_VOLTAGE") "16V")
        (field (name "DB_MANUFACTURER_PART") "KEMET    C0603C474J4RAC")
        (field (name "DB_APPROVED_BY") "ISHIDDEN=T")
      )
      (libsource (lib "Database_Libs1") (part "C"))
    )
    (comp (ref "C163")
      (value "C")
      (footprint "SMD_0603_CAPC1608X95N")
      (fields
        (field (name "DB_PART_NUMBER") "CAP000028169")
        (field (name "DB_VALUE") "470nF")
        (field (name "DB_TOLERANCE") "5%")
        (field (name "DB_VOLTAGE") "16V")
        (field (name "DB_MANUFACTURER_PART") "KEMET    C0603C474J4RAC")
        (field (name "DB_APPROVED_BY") "ISHIDDEN=T")
      )
      (libsource (lib "Database_Libs1") (part "C"))
    )
    (comp (ref "C166")
      (value "C")
      (footprint "SMD_0603_CAPC1608X95N")
      (fields
        (field (name "DB_PART_NUMBER") "CAP000024113")
        (field (name "DB_VALUE") "1nF")
        (field (name "DB_TOLERANCE") "5%")
        (field (name "DB_VOLTAGE") "25V")
        (field (name "DB_MANUFACTURER_PART") "KEMET    C0603C102J3RAC")
        (field (name "DB_APPROVED_BY") "ISHIDDEN=T")
      )
      (libsource (lib "Database_Libs1") (part "C"))
    )
    (comp (ref "C167")
      (value "C")
      (footprint "SMD_0603_CAPC1608X95N")
      (fields
        (field (name "DB_PART_NUMBER") "CAP000027136")
        (field (name "DB_VALUE") "100nF")
        (field (name "DB_TOLERANCE") "5%")
        (field (name "DB_VOLTAGE") "50V")
        (field (name "DB_MANUFACTURER_PART") "KEMET    C0603C104J5RAC")
        (field (name "DB_APPROVED_BY") "ISHIDDEN=T")
      )
      (libsource (lib "Database_Libs1") (part "C"))
    )
    (comp (ref "C168")
      (value "C")
      (footprint "SMD_0603_CAPC1608X95N")
      (fields
        (field (name "DB_PART_NUMBER") "CAP000027136")
        (field (name "DB_VALUE") "100nF")
        (field (name "DB_TOLERANCE") "5%")
        (field (name "DB_VOLTAGE") "50V")
        (field (name "DB_MANUFACTURER_PART") "KEMET    C0603C104J5RAC")
        (field (name "DB_APPROVED_BY") "ISHIDDEN=T")
      )
      (libsource (lib "Database_Libs1") (part "C"))
    )
    (comp (ref "C169")
      (value "C")
      (footprint "SMD_0603_CAPC1608X95N")
      (fields
        (field (name "DB_PART_NUMBER") "CAP000027136")
        (field (name "DB_VALUE") "100nF")
        (field (name "DB_TOLERANCE") "5%")
        (field (name "DB_VOLTAGE") "50V")
        (field (name "DB_MANUFACTURER_PART") "KEMET    C0603C104J5RAC")
        (field (name "DB_APPROVED_BY") "ISHIDDEN=T")
      )
      (libsource (lib "Database_Libs1") (part "C"))
    )
    (comp (ref "C170")
      (value "C")
      (footprint "SMD_0603_CAPC1608X95N")
      (fields
        (field (name "DB_PART_NUMBER") "CAP000027136")
        (field (name "DB_VALUE") "100nF")
        (field (name "DB_TOLERANCE") "5%")
        (field (name "DB_VOLTAGE") "50V")
        (field (name "DB_MANUFACTURER_PART") "KEMET    C0603C104J5RAC")
        (field (name "DB_APPROVED_BY") "ISHIDDEN=T")
      )
      (libsource (lib "Database_Libs1") (part "C"))
    )
    (comp (ref "C171")
      (value "C")
      (footprint "SMD_0603_CAPC1608X95N")
      (fields
        (field (name "DB_PART_NUMBER") "CAP000027136")
        (field (name "DB_VALUE") "100nF")
        (field (name "DB_TOLERANCE") "5%")
        (field (name "DB_VOLTAGE") "50V")
        (field (name "DB_MANUFACTURER_PART") "KEMET    C0603C104J5RAC")
        (field (name "DB_APPROVED_BY") "ISHIDDEN=T")
      )
      (libsource (lib "Database_Libs1") (part "C"))
    )
    (comp (ref "C172")
      (value "C")
      (footprint "SMD_0603_CAPC1608X95N")
      (fields
        (field (name "DB_PART_NUMBER") "CAP000027136")
        (field (name "DB_VALUE") "100nF")
        (field (name "DB_TOLERANCE") "5%")
        (field (name "DB_VOLTAGE") "50V")
        (field (name "DB_MANUFACTURER_PART") "KEMET    C0603C104J5RAC")
        (field (name "DB_APPROVED_BY") "ISHIDDEN=T")
      )
      (libsource (lib "Database_Libs1") (part "C"))
    )
    (comp (ref "C173")
      (value "C")
      (footprint "SMD_0603_CAPC1608X95N")
      (fields
        (field (name "DB_PART_NUMBER") "CAP000031922")
        (field (name "DB_VALUE") "18pF")
        (field (name "DB_TOLERANCE") "5%")
        (field (name "DB_VOLTAGE") "50V")
        (field (name "DB_MANUFACTURER_PART") "KEMET    C0603C180J5GAC")
        (field (name "DB_APPROVED_BY") "ISHIDDEN=T")
      )
      (libsource (lib "Database_Libs1") (part "C"))
    )
    (comp (ref "C174")
      (value "C")
      (footprint "SMD_0603_CAPC1608X95N")
      (fields
        (field (name "DB_PART_NUMBER") "CAP000031922")
        (field (name "DB_VALUE") "18pF")
        (field (name "DB_TOLERANCE") "5%")
        (field (name "DB_VOLTAGE") "50V")
        (field (name "DB_MANUFACTURER_PART") "KEMET    C0603C180J5GAC")
        (field (name "DB_APPROVED_BY") "ISHIDDEN=T")
      )
      (libsource (lib "Database_Libs1") (part "C"))
    )
    (comp (ref "C175")
      (value "C")
      (footprint "SMD_0603_CAPC1608X95N")
      (fields
        (field (name "DB_PART_NUMBER") "CAP000028169")
        (field (name "DB_VALUE") "470nF")
        (field (name "DB_TOLERANCE") "5%")
        (field (name "DB_VOLTAGE") "16V")
        (field (name "DB_MANUFACTURER_PART") "KEMET    C0603C474J4RAC")
        (field (name "DB_APPROVED_BY") "ISHIDDEN=T")
      )
      (libsource (lib "Database_Libs1") (part "C"))
    )
    (comp (ref "C176")
      (value "C")
      (footprint "SMD_0603_CAPC1608X95N")
      (fields
        (field (name "DB_PART_NUMBER") "CAP000028169")
        (field (name "DB_VALUE") "470nF")
        (field (name "DB_TOLERANCE") "5%")
        (field (name "DB_VOLTAGE") "16V")
        (field (name "DB_MANUFACTURER_PART") "KEMET    C0603C474J4RAC")
        (field (name "DB_APPROVED_BY") "ISHIDDEN=T")
      )
      (libsource (lib "Database_Libs1") (part "C"))
    )
    (comp (ref "C177")
      (value "C")
      (footprint "SMD_0603_CAPC1608X95N")
      (fields
        (field (name "DB_PART_NUMBER") "CAP000028169")
        (field (name "DB_VALUE") "470nF")
        (field (name "DB_TOLERANCE") "5%")
        (field (name "DB_VOLTAGE") "16V")
        (field (name "DB_MANUFACTURER_PART") "KEMET    C0603C474J4RAC")
        (field (name "DB_APPROVED_BY") "ISHIDDEN=T")
      )
      (libsource (lib "Database_Libs1") (part "C"))
    )
    (comp (ref "C178")
      (value "C")
      (footprint "SMD_0603_CAPC1608X95N")
      (fields
        (field (name "DB_PART_NUMBER") "CAP000028169")
        (field (name "DB_VALUE") "470nF")
        (field (name "DB_TOLERANCE") "5%")
        (field (name "DB_VOLTAGE") "16V")
        (field (name "DB_MANUFACTURER_PART") "KEMET    C0603C474J4RAC")
        (field (name "DB_APPROVED_BY") "ISHIDDEN=T")
      )
      (libsource (lib "Database_Libs1") (part "C"))
    )
    (comp (ref "C179")
      (value "C")
      (footprint "SMD_0603_CAPC1608X95N")
      (fields
        (field (name "DB_PART_NUMBER") "CAP000028169")
        (field (name "DB_VALUE") "470nF")
        (field (name "DB_TOLERANCE") "5%")
        (field (name "DB_VOLTAGE") "16V")
        (field (name "DB_MANUFACTURER_PART") "KEMET    C0603C474J4RAC")
        (field (name "DB_APPROVED_BY") "ISHIDDEN=T")
      )
      (libsource (lib "Database_Libs1") (part "C"))
    )
    (comp (ref "C180")
      (value "C")
      (footprint "SMD_0603_CAPC1608X95N")
      (fields
        (field (name "DB_PART_NUMBER") "CAP000028169")
        (field (name "DB_VALUE") "470nF")
        (field (name "DB_TOLERANCE") "5%")
        (field (name "DB_VOLTAGE") "16V")
        (field (name "DB_MANUFACTURER_PART") "KEMET    C0603C474J4RAC")
        (field (name "DB_APPROVED_BY") "ISHIDDEN=T")
      )
      (libsource (lib "Database_Libs1") (part "C"))
    )
    (comp (ref "C181")
      (value "C")
      (footprint "SMD_0603_CAPC1608X95N")
      (fields
        (field (name "DB_PART_NUMBER") "CAP000028169")
        (field (name "DB_VALUE") "470nF")
        (field (name "DB_TOLERANCE") "5%")
        (field (name "DB_VOLTAGE") "16V")
        (field (name "DB_MANUFACTURER_PART") "KEMET    C0603C474J4RAC")
        (field (name "DB_APPROVED_BY") "ISHIDDEN=T")
      )
      (libsource (lib "Database_Libs1") (part "C"))
    )
    (comp (ref "C182")
      (value "C")
      (footprint "SMD_0603_CAPC1608X95N")
      (fields
        (field (name "DB_PART_NUMBER") "CAP000028169")
        (field (name "DB_VALUE") "470nF")
        (field (name "DB_TOLERANCE") "5%")
        (field (name "DB_VOLTAGE") "16V")
        (field (name "DB_MANUFACTURER_PART") "KEMET    C0603C474J4RAC")
        (field (name "DB_APPROVED_BY") "ISHIDDEN=T")
      )
      (libsource (lib "Database_Libs1") (part "C"))
    )
    (comp (ref "C183")
      (value "C")
      (footprint "SMD_0603_CAPC1608X95N")
      (fields
        (field (name "DB_PART_NUMBER") "CAP000028169")
        (field (name "DB_VALUE") "470nF")
        (field (name "DB_TOLERANCE") "5%")
        (field (name "DB_VOLTAGE") "16V")
        (field (name "DB_MANUFACTURER_PART") "KEMET    C0603C474J4RAC")
        (field (name "DB_APPROVED_BY") "ISHIDDEN=T")
      )
      (libsource (lib "Database_Libs1") (part "C"))
    )
    (comp (ref "C184")
      (value "C")
      (footprint "SMD_0603_CAPC1608X95N")
      (fields
        (field (name "DB_PART_NUMBER") "CAP000028169")
        (field (name "DB_VALUE") "470nF")
        (field (name "DB_TOLERANCE") "5%")
        (field (name "DB_VOLTAGE") "16V")
        (field (name "DB_MANUFACTURER_PART") "KEMET    C0603C474J4RAC")
        (field (name "DB_APPROVED_BY") "ISHIDDEN=T")
      )
      (libsource (lib "Database_Libs1") (part "C"))
    )
    (comp (ref "C185")
      (value "C")
      (footprint "SMD_0603_CAPC1608X95N")
      (fields
        (field (name "DB_PART_NUMBER") "CAP000028169")
        (field (name "DB_VALUE") "470nF")
        (field (name "DB_TOLERANCE") "5%")
        (field (name "DB_VOLTAGE") "16V")
        (field (name "DB_MANUFACTURER_PART") "KEMET    C0603C474J4RAC")
        (field (name "DB_APPROVED_BY") "ISHIDDEN=T")
      )
      (libsource (lib "Database_Libs1") (part "C"))
    )
    (comp (ref "C186")
      (value "C")
      (footprint "SMD_0603_CAPC1608X95N")
      (fields
        (field (name "DB_PART_NUMBER") "CAP000028169")
        (field (name "DB_VALUE") "470nF")
        (field (name "DB_TOLERANCE") "5%")
        (field (name "DB_VOLTAGE") "16V")
        (field (name "DB_MANUFACTURER_PART") "KEMET    C0603C474J4RAC")
        (field (name "DB_APPROVED_BY") "ISHIDDEN=T")
      )
      (libsource (lib "Database_Libs1") (part "C"))
    )
    (comp (ref "C187")
      (value "C")
      (footprint "SMD_0603_CAPC1608X95N")
      (fields
        (field (name "DB_PART_NUMBER") "CAP000028169")
        (field (name "DB_VALUE") "470nF")
        (field (name "DB_TOLERANCE") "5%")
        (field (name "DB_VOLTAGE") "16V")
        (field (name "DB_MANUFACTURER_PART") "KEMET    C0603C474J4RAC")
        (field (name "DB_APPROVED_BY") "ISHIDDEN=T")
      )
      (libsource (lib "Database_Libs1") (part "C"))
    )
    (comp (ref "C188")
      (value "C")
      (footprint "SMD_0603_CAPC1608X95N")
      (fields
        (field (name "DB_PART_NUMBER") "CAP000028169")
        (field (name "DB_VALUE") "470nF")
        (field (name "DB_TOLERANCE") "5%")
        (field (name "DB_VOLTAGE") "16V")
        (field (name "DB_MANUFACTURER_PART") "KEMET    C0603C474J4RAC")
        (field (name "DB_APPROVED_BY") "ISHIDDEN=T")
      )
      (libsource (lib "Database_Libs1") (part "C"))
    )
    (comp (ref "C189")
      (value "C")
      (footprint "SMD_0603_CAPC1608X95N")
      (fields
        (field (name "DB_PART_NUMBER") "CAP000028169")
        (field (name "DB_VALUE") "470nF")
        (field (name "DB_TOLERANCE") "5%")
        (field (name "DB_VOLTAGE") "16V")
        (field (name "DB_MANUFACTURER_PART") "KEMET    C0603C474J4RAC")
        (field (name "DB_APPROVED_BY") "ISHIDDEN=T")
      )
      (libsource (lib "Database_Libs1") (part "C"))
    )
    (comp (ref "C190")
      (value "C")
      (footprint "SMD_0603_CAPC1608X95N")
      (fields
        (field (name "DB_PART_NUMBER") "CAP000028169")
        (field (name "DB_VALUE") "470nF")
        (field (name "DB_TOLERANCE") "5%")
        (field (name "DB_VOLTAGE") "16V")
        (field (name "DB_MANUFACTURER_PART") "KEMET    C0603C474J4RAC")
        (field (name "DB_APPROVED_BY") "ISHIDDEN=T")
      )
      (libsource (lib "Database_Libs1") (part "C"))
    )
    (comp (ref "C191")
      (value "C")
      (footprint "SMD_0805_CAPC2012X145N")
      (fields
        (field (name "DB_PART_NUMBER") "CAP000043636")
        (field (name "DB_VALUE") "10uF")
        (field (name "DB_TOLERANCE") "10%")
        (field (name "DB_VOLTAGE") "16V")
        (field (name "DB_MANUFACTURER_PART") "KEMET    C0805C106K4PAC")
        (field (name "DB_APPROVED_BY") "ISHIDDEN=T")
      )
      (libsource (lib "Database_Libs1") (part "C"))
    )
    (comp (ref "C224")
      (value "C")
      (footprint "SMD_1210_CAPC3225X279N")
      (fields
        (field (name "DB_PART_NUMBER") "CAP000047355")
        (field (name "DB_VALUE") "220uF")
        (field (name "DB_TOLERANCE") "20%")
        (field (name "DB_VOLTAGE") "6.3V")
        (field (name "DB_MANUFACTURER_PART") "SAMSUNG    CL32A227MQVNNNE")
        (field (name "DB_APPROVED_BY") "VSN")
      )
      (libsource (lib "Database_Libs1") (part "C"))
    )
    (comp (ref "C225")
      (value "C")
      (footprint "SMD_0805_CAPC2012X145N")
      (fields
        (field (name "DB_PART_NUMBER") "CAP000043686")
        (field (name "DB_VALUE") "22uF")
        (field (name "DB_TOLERANCE") "20%")
        (field (name "DB_VOLTAGE") "6.3V")
        (field (name "DB_MANUFACTURER_PART") "KEMET    C0805C226M9PAC")
        (field (name "DB_APPROVED_BY") "ISHIDDEN=T")
      )
      (libsource (lib "Database_Libs1") (part "C"))
    )
    (comp (ref "C226")
      (value "C")
      (footprint "SMD_0805_CAPC2012X145N")
      (fields
        (field (name "DB_PART_NUMBER") "CAP000043636")
        (field (name "DB_VALUE") "10uF")
        (field (name "DB_TOLERANCE") "10%")
        (field (name "DB_VOLTAGE") "16V")
        (field (name "DB_MANUFACTURER_PART") "KEMET    C0805C106K4PAC")
        (field (name "DB_APPROVED_BY") "ISHIDDEN=T")
      )
      (libsource (lib "Database_Libs1") (part "C"))
    )
    (comp (ref "C227")
      (value "C")
      (footprint "SMD_0603_CAPC1608X95N")
      (fields
        (field (name "DB_PART_NUMBER") "CAP000028169")
        (field (name "DB_VALUE") "470nF")
        (field (name "DB_TOLERANCE") "5%")
        (field (name "DB_VOLTAGE") "16V")
        (field (name "DB_MANUFACTURER_PART") "KEMET    C0603C474J4RAC")
        (field (name "DB_APPROVED_BY") "ISHIDDEN=T")
      )
      (libsource (lib "Database_Libs1") (part "C"))
    )
    (comp (ref "C228")
      (value "C")
      (footprint "SMD_0603_CAPC1608X95N")
      (fields
        (field (name "DB_PART_NUMBER") "CAP000028169")
        (field (name "DB_VALUE") "470nF")
        (field (name "DB_TOLERANCE") "5%")
        (field (name "DB_VOLTAGE") "16V")
        (field (name "DB_MANUFACTURER_PART") "KEMET    C0603C474J4RAC")
        (field (name "DB_APPROVED_BY") "ISHIDDEN=T")
      )
      (libsource (lib "Database_Libs1") (part "C"))
    )
    (comp (ref "C229")
      (value "C")
      (footprint "SMD_0603_CAPC1608X95N")
      (fields
        (field (name "DB_PART_NUMBER") "CAP000028169")
        (field (name "DB_VALUE") "470nF")
        (field (name "DB_TOLERANCE") "5%")
        (field (name "DB_VOLTAGE") "16V")
        (field (name "DB_MANUFACTURER_PART") "KEMET    C0603C474J4RAC")
        (field (name "DB_APPROVED_BY") "ISHIDDEN=T")
      )
      (libsource (lib "Database_Libs1") (part "C"))
    )
    (comp (ref "C230")
      (value "C")
      (footprint "SMD_0603_CAPC1608X95N")
      (fields
        (field (name "DB_PART_NUMBER") "CAP000028169")
        (field (name "DB_VALUE") "470nF")
        (field (name "DB_TOLERANCE") "5%")
        (field (name "DB_VOLTAGE") "16V")
        (field (name "DB_MANUFACTURER_PART") "KEMET    C0603C474J4RAC")
        (field (name "DB_APPROVED_BY") "ISHIDDEN=T")
      )
      (libsource (lib "Database_Libs1") (part "C"))
    )
    (comp (ref "C231")
      (value "C")
      (footprint "SMD_0603_CAPC1608X95N")
      (fields
        (field (name "DB_PART_NUMBER") "CAP000028169")
        (field (name "DB_VALUE") "470nF")
        (field (name "DB_TOLERANCE") "5%")
        (field (name "DB_VOLTAGE") "16V")
        (field (name "DB_MANUFACTURER_PART") "KEMET    C0603C474J4RAC")
        (field (name "DB_APPROVED_BY") "ISHIDDEN=T")
      )
      (libsource (lib "Database_Libs1") (part "C"))
    )
    (comp (ref "C232")
      (value "C")
      (footprint "SMD_0603_CAPC1608X95N")
      (fields
        (field (name "DB_PART_NUMBER") "CAP000028169")
        (field (name "DB_VALUE") "470nF")
        (field (name "DB_TOLERANCE") "5%")
        (field (name "DB_VOLTAGE") "16V")
        (field (name "DB_MANUFACTURER_PART") "KEMET    C0603C474J4RAC")
        (field (name "DB_APPROVED_BY") "ISHIDDEN=T")
      )
      (libsource (lib "Database_Libs1") (part "C"))
    )
    (comp (ref "C233")
      (value "C")
      (footprint "SMD_0603_CAPC1608X95N")
      (fields
        (field (name "DB_PART_NUMBER") "CAP000028169")
        (field (name "DB_VALUE") "470nF")
        (field (name "DB_TOLERANCE") "5%")
        (field (name "DB_VOLTAGE") "16V")
        (field (name "DB_MANUFACTURER_PART") "KEMET    C0603C474J4RAC")
        (field (name "DB_APPROVED_BY") "ISHIDDEN=T")
      )
      (libsource (lib "Database_Libs1") (part "C"))
    )
    (comp (ref "C234")
      (value "C")
      (footprint "SMD_0603_CAPC1608X95N")
      (fields
        (field (name "DB_PART_NUMBER") "CAP000028169")
        (field (name "DB_VALUE") "470nF")
        (field (name "DB_TOLERANCE") "5%")
        (field (name "DB_VOLTAGE") "16V")
        (field (name "DB_MANUFACTURER_PART") "KEMET    C0603C474J4RAC")
        (field (name "DB_APPROVED_BY") "ISHIDDEN=T")
      )
      (libsource (lib "Database_Libs1") (part "C"))
    )
    (comp (ref "C235")
      (value "C")
      (footprint "SMD_0603_CAPC1608X95N")
      (fields
        (field (name "DB_PART_NUMBER") "CAP000028169")
        (field (name "DB_VALUE") "470nF")
        (field (name "DB_TOLERANCE") "5%")
        (field (name "DB_VOLTAGE") "16V")
        (field (name "DB_MANUFACTURER_PART") "KEMET    C0603C474J4RAC")
        (field (name "DB_APPROVED_BY") "ISHIDDEN=T")
      )
      (libsource (lib "Database_Libs1") (part "C"))
    )
    (comp (ref "C236")
      (value "C")
      (footprint "SMD_0603_CAPC1608X95N")
      (fields
        (field (name "DB_PART_NUMBER") "CAP000028169")
        (field (name "DB_VALUE") "470nF")
        (field (name "DB_TOLERANCE") "5%")
        (field (name "DB_VOLTAGE") "16V")
        (field (name "DB_MANUFACTURER_PART") "KEMET    C0603C474J4RAC")
        (field (name "DB_APPROVED_BY") "ISHIDDEN=T")
      )
      (libsource (lib "Database_Libs1") (part "C"))
    )
    (comp (ref "C237")
      (value "C")
      (footprint "SMD_0603_CAPC1608X95N")
      (fields
        (field (name "DB_PART_NUMBER") "CAP000028169")
        (field (name "DB_VALUE") "470nF")
        (field (name "DB_TOLERANCE") "5%")
        (field (name "DB_VOLTAGE") "16V")
        (field (name "DB_MANUFACTURER_PART") "KEMET    C0603C474J4RAC")
        (field (name "DB_APPROVED_BY") "ISHIDDEN=T")
      )
      (libsource (lib "Database_Libs1") (part "C"))
    )
    (comp (ref "C238")
      (value "C")
      (footprint "SMD_0603_CAPC1608X95N")
      (fields
        (field (name "DB_PART_NUMBER") "CAP000028169")
        (field (name "DB_VALUE") "470nF")
        (field (name "DB_TOLERANCE") "5%")
        (field (name "DB_VOLTAGE") "16V")
        (field (name "DB_MANUFACTURER_PART") "KEMET    C0603C474J4RAC")
        (field (name "DB_APPROVED_BY") "ISHIDDEN=T")
      )
      (libsource (lib "Database_Libs1") (part "C"))
    )
    (comp (ref "C239")
      (value "C")
      (footprint "SMD_0603_CAPC1608X95N")
      (fields
        (field (name "DB_PART_NUMBER") "CAP000028169")
        (field (name "DB_VALUE") "470nF")
        (field (name "DB_TOLERANCE") "5%")
        (field (name "DB_VOLTAGE") "16V")
        (field (name "DB_MANUFACTURER_PART") "KEMET    C0603C474J4RAC")
        (field (name "DB_APPROVED_BY") "ISHIDDEN=T")
      )
      (libsource (lib "Database_Libs1") (part "C"))
    )
    (comp (ref "C240")
      (value "C")
      (footprint "SMD_0603_CAPC1608X95N")
      (fields
        (field (name "DB_PART_NUMBER") "CAP000028169")
        (field (name "DB_VALUE") "470nF")
        (field (name "DB_TOLERANCE") "5%")
        (field (name "DB_VOLTAGE") "16V")
        (field (name "DB_MANUFACTURER_PART") "KEMET    C0603C474J4RAC")
        (field (name "DB_APPROVED_BY") "ISHIDDEN=T")
      )
      (libsource (lib "Database_Libs1") (part "C"))
    )
    (comp (ref "C241")
      (value "C")
      (footprint "SMD_0603_CAPC1608X95N")
      (fields
        (field (name "DB_PART_NUMBER") "CAP000028169")
        (field (name "DB_VALUE") "470nF")
        (field (name "DB_TOLERANCE") "5%")
        (field (name "DB_VOLTAGE") "16V")
        (field (name "DB_MANUFACTURER_PART") "KEMET    C0603C474J4RAC")
        (field (name "DB_APPROVED_BY") "ISHIDDEN=T")
      )
      (libsource (lib "Database_Libs1") (part "C"))
    )
    (comp (ref "C242")
      (value "C")
      (footprint "SMD_0603_CAPC1608X95N")
      (fields
        (field (name "DB_PART_NUMBER") "CAP000028169")
        (field (name "DB_VALUE") "470nF")
        (field (name "DB_TOLERANCE") "5%")
        (field (name "DB_VOLTAGE") "16V")
        (field (name "DB_MANUFACTURER_PART") "KEMET    C0603C474J4RAC")
        (field (name "DB_APPROVED_BY") "ISHIDDEN=T")
      )
      (libsource (lib "Database_Libs1") (part "C"))
    )
    (comp (ref "C243")
      (value "C")
      (footprint "SMD_0603_CAPC1608X95N")
      (fields
        (field (name "DB_PART_NUMBER") "CAP000028169")
        (field (name "DB_VALUE") "470nF")
        (field (name "DB_TOLERANCE") "5%")
        (field (name "DB_VOLTAGE") "16V")
        (field (name "DB_MANUFACTURER_PART") "KEMET    C0603C474J4RAC")
        (field (name "DB_APPROVED_BY") "ISHIDDEN=T")
      )
      (libsource (lib "Database_Libs1") (part "C"))
    )
    (comp (ref "C244")
      (value "C")
      (footprint "SMD_0603_CAPC1608X95N")
      (fields
        (field (name "DB_PART_NUMBER") "CAP000028169")
        (field (name "DB_VALUE") "470nF")
        (field (name "DB_TOLERANCE") "5%")
        (field (name "DB_VOLTAGE") "16V")
        (field (name "DB_MANUFACTURER_PART") "KEMET    C0603C474J4RAC")
        (field (name "DB_APPROVED_BY") "ISHIDDEN=T")
      )
      (libsource (lib "Database_Libs1") (part "C"))
    )
    (comp (ref "C245")
      (value "C")
      (footprint "SMD_0603_CAPC1608X95N")
      (fields
        (field (name "DB_PART_NUMBER") "CAP000028169")
        (field (name "DB_VALUE") "470nF")
        (field (name "DB_TOLERANCE") "5%")
        (field (name "DB_VOLTAGE") "16V")
        (field (name "DB_MANUFACTURER_PART") "KEMET    C0603C474J4RAC")
        (field (name "DB_APPROVED_BY") "ISHIDDEN=T")
      )
      (libsource (lib "Database_Libs1") (part "C"))
    )
    (comp (ref "C246")
      (value "C")
      (footprint "SMD_0603_CAPC1608X95N")
      (fields
        (field (name "DB_PART_NUMBER") "CAP000028169")
        (field (name "DB_VALUE") "470nF")
        (field (name "DB_TOLERANCE") "5%")
        (field (name "DB_VOLTAGE") "16V")
        (field (name "DB_MANUFACTURER_PART") "KEMET    C0603C474J4RAC")
        (field (name "DB_APPROVED_BY") "ISHIDDEN=T")
      )
      (libsource (lib "Database_Libs1") (part "C"))
    )
    (comp (ref "C247")
      (value "C")
      (footprint "SMD_0603_CAPC1608X95N")
      (fields
        (field (name "DB_PART_NUMBER") "CAP000028169")
        (field (name "DB_VALUE") "470nF")
        (field (name "DB_TOLERANCE") "5%")
        (field (name "DB_VOLTAGE") "16V")
        (field (name "DB_MANUFACTURER_PART") "KEMET    C0603C474J4RAC")
        (field (name "DB_APPROVED_BY") "ISHIDDEN=T")
      )
      (libsource (lib "Database_Libs1") (part "C"))
    )
    (comp (ref "C248")
      (value "C")
      (footprint "SMD_0603_CAPC1608X95N")
      (fields
        (field (name "DB_PART_NUMBER") "CAP000028169")
        (field (name "DB_VALUE") "470nF")
        (field (name "DB_TOLERANCE") "5%")
        (field (name "DB_VOLTAGE") "16V")
        (field (name "DB_MANUFACTURER_PART") "KEMET    C0603C474J4RAC")
        (field (name "DB_APPROVED_BY") "ISHIDDEN=T")
      )
      (libsource (lib "Database_Libs1") (part "C"))
    )
    (comp (ref "C249")
      (value "C")
      (footprint "SMD_0603_CAPC1608X95N")
      (fields
        (field (name "DB_PART_NUMBER") "CAP000028169")
        (field (name "DB_VALUE") "470nF")
        (field (name "DB_TOLERANCE") "5%")
        (field (name "DB_VOLTAGE") "16V")
        (field (name "DB_MANUFACTURER_PART") "KEMET    C0603C474J4RAC")
        (field (name "DB_APPROVED_BY") "ISHIDDEN=T")
      )
      (libsource (lib "Database_Libs1") (part "C"))
    )
    (comp (ref "C250")
      (value "C")
      (footprint "SMD_0603_CAPC1608X95N")
      (fields
        (field (name "DB_PART_NUMBER") "CAP000028169")
        (field (name "DB_VALUE") "470nF")
        (field (name "DB_TOLERANCE") "5%")
        (field (name "DB_VOLTAGE") "16V")
        (field (name "DB_MANUFACTURER_PART") "KEMET    C0603C474J4RAC")
        (field (name "DB_APPROVED_BY") "ISHIDDEN=T")
      )
      (libsource (lib "Database_Libs1") (part "C"))
    )
    (comp (ref "C251")
      (value "C")
      (footprint "SMD_0603_CAPC1608X95N")
      (fields
        (field (name "DB_PART_NUMBER") "CAP000028169")
        (field (name "DB_VALUE") "470nF")
        (field (name "DB_TOLERANCE") "5%")
        (field (name "DB_VOLTAGE") "16V")
        (field (name "DB_MANUFACTURER_PART") "KEMET    C0603C474J4RAC")
        (field (name "DB_APPROVED_BY") "ISHIDDEN=T")
      )
      (libsource (lib "Database_Libs1") (part "C"))
    )
    (comp (ref "C252")
      (value "C")
      (footprint "SMD_0603_CAPC1608X95N")
      (fields
        (field (name "DB_PART_NUMBER") "CAP000028169")
        (field (name "DB_VALUE") "470nF")
        (field (name "DB_TOLERANCE") "5%")
        (field (name "DB_VOLTAGE") "16V")
        (field (name "DB_MANUFACTURER_PART") "KEMET    C0603C474J4RAC")
        (field (name "DB_APPROVED_BY") "ISHIDDEN=T")
      )
      (libsource (lib "Database_Libs1") (part "C"))
    )
    (comp (ref "C253")
      (value "C")
      (footprint "SMD_0603_CAPC1608X95N")
      (fields
        (field (name "DB_PART_NUMBER") "CAP000028169")
        (field (name "DB_VALUE") "470nF")
        (field (name "DB_TOLERANCE") "5%")
        (field (name "DB_VOLTAGE") "16V")
        (field (name "DB_MANUFACTURER_PART") "KEMET    C0603C474J4RAC")
        (field (name "DB_APPROVED_BY") "ISHIDDEN=T")
      )
      (libsource (lib "Database_Libs1") (part "C"))
    )
    (comp (ref "C254")
      (value "C")
      (footprint "SMD_0603_CAPC1608X95N")
      (fields
        (field (name "DB_PART_NUMBER") "CAP000028169")
        (field (name "DB_VALUE") "470nF")
        (field (name "DB_TOLERANCE") "5%")
        (field (name "DB_VOLTAGE") "16V")
        (field (name "DB_MANUFACTURER_PART") "KEMET    C0603C474J4RAC")
        (field (name "DB_APPROVED_BY") "ISHIDDEN=T")
      )
      (libsource (lib "Database_Libs1") (part "C"))
    )
    (comp (ref "C255")
      (value "C")
      (footprint "SMD_0603_CAPC1608X95N")
      (fields
        (field (name "DB_PART_NUMBER") "CAP000028169")
        (field (name "DB_VALUE") "470nF")
        (field (name "DB_TOLERANCE") "5%")
        (field (name "DB_VOLTAGE") "16V")
        (field (name "DB_MANUFACTURER_PART") "KEMET    C0603C474J4RAC")
        (field (name "DB_APPROVED_BY") "ISHIDDEN=T")
      )
      (libsource (lib "Database_Libs1") (part "C"))
    )
    (comp (ref "C256")
      (value "C")
      (footprint "SMD_0603_CAPC1608X95N")
      (fields
        (field (name "DB_PART_NUMBER") "CAP000028169")
        (field (name "DB_VALUE") "470nF")
        (field (name "DB_TOLERANCE") "5%")
        (field (name "DB_VOLTAGE") "16V")
        (field (name "DB_MANUFACTURER_PART") "KEMET    C0603C474J4RAC")
        (field (name "DB_APPROVED_BY") "ISHIDDEN=T")
      )
      (libsource (lib "Database_Libs1") (part "C"))
    )
    (comp (ref "C257")
      (value "C")
      (footprint "SMD_0603_CAPC1608X95N")
      (fields
        (field (name "DB_PART_NUMBER") "CAP000028169")
        (field (name "DB_VALUE") "470nF")
        (field (name "DB_TOLERANCE") "5%")
        (field (name "DB_VOLTAGE") "16V")
        (field (name "DB_MANUFACTURER_PART") "KEMET    C0603C474J4RAC")
        (field (name "DB_APPROVED_BY") "ISHIDDEN=T")
      )
      (libsource (lib "Database_Libs1") (part "C"))
    )
    (comp (ref "C258")
      (value "C")
      (footprint "SMD_0603_CAPC1608X95N")
      (fields
        (field (name "DB_PART_NUMBER") "CAP000028169")
        (field (name "DB_VALUE") "470nF")
        (field (name "DB_TOLERANCE") "5%")
        (field (name "DB_VOLTAGE") "16V")
        (field (name "DB_MANUFACTURER_PART") "KEMET    C0603C474J4RAC")
        (field (name "DB_APPROVED_BY") "ISHIDDEN=T")
      )
      (libsource (lib "Database_Libs1") (part "C"))
    )
    (comp (ref "C259")
      (value "C")
      (footprint "SMD_0805_CAPC2012X145N")
      (fields
        (field (name "DB_PART_NUMBER") "CAP000043686")
        (field (name "DB_VALUE") "22uF")
        (field (name "DB_TOLERANCE") "20%")
        (field (name "DB_VOLTAGE") "6.3V")
        (field (name "DB_MANUFACTURER_PART") "KEMET    C0805C226M9PAC")
        (field (name "DB_APPROVED_BY") "ISHIDDEN=T")
      )
      (libsource (lib "Database_Libs1") (part "C"))
    )
    (comp (ref "C260")
      (value "C")
      (footprint "SMD_0603_CAPC1608X95N")
      (fields
        (field (name "DB_PART_NUMBER") "CAP000027136")
        (field (name "DB_VALUE") "100nF")
        (field (name "DB_TOLERANCE") "5%")
        (field (name "DB_VOLTAGE") "50V")
        (field (name "DB_MANUFACTURER_PART") "KEMET    C0603C104J5RAC")
        (field (name "DB_APPROVED_BY") "ISHIDDEN=T")
      )
      (libsource (lib "Database_Libs1") (part "C"))
    )
    (comp (ref "C261")
      (value "C")
      (footprint "SMD_0603_CAPC1608X95N")
      (fields
        (field (name "DB_PART_NUMBER") "CAP000027136")
        (field (name "DB_VALUE") "100nF")
        (field (name "DB_TOLERANCE") "5%")
        (field (name "DB_VOLTAGE") "50V")
        (field (name "DB_MANUFACTURER_PART") "KEMET    C0603C104J5RAC")
        (field (name "DB_APPROVED_BY") "ISHIDDEN=T")
      )
      (libsource (lib "Database_Libs1") (part "C"))
    )
    (comp (ref "C262")
      (value "C")
      (footprint "SMD_0603_CAPC1608X95N")
      (fields
        (field (name "DB_PART_NUMBER") "CAP000028169")
        (field (name "DB_VALUE") "470nF")
        (field (name "DB_TOLERANCE") "5%")
        (field (name "DB_VOLTAGE") "16V")
        (field (name "DB_MANUFACTURER_PART") "KEMET    C0603C474J4RAC")
        (field (name "DB_APPROVED_BY") "ISHIDDEN=T")
      )
      (libsource (lib "Database_Libs1") (part "C"))
    )
    (comp (ref "C263")
      (value "C")
      (footprint "SMD_0603_CAPC1608X95N")
      (fields
        (field (name "DB_PART_NUMBER") "CAP000028169")
        (field (name "DB_VALUE") "470nF")
        (field (name "DB_TOLERANCE") "5%")
        (field (name "DB_VOLTAGE") "16V")
        (field (name "DB_MANUFACTURER_PART") "KEMET    C0603C474J4RAC")
        (field (name "DB_APPROVED_BY") "ISHIDDEN=T")
      )
      (libsource (lib "Database_Libs1") (part "C"))
    )
    (comp (ref "C264")
      (value "C")
      (footprint "SMD_0603_CAPC1608X95N")
      (fields
        (field (name "DB_PART_NUMBER") "CAP000028169")
        (field (name "DB_VALUE") "470nF")
        (field (name "DB_TOLERANCE") "5%")
        (field (name "DB_VOLTAGE") "16V")
        (field (name "DB_MANUFACTURER_PART") "KEMET    C0603C474J4RAC")
        (field (name "DB_APPROVED_BY") "ISHIDDEN=T")
      )
      (libsource (lib "Database_Libs1") (part "C"))
    )
    (comp (ref "C265")
      (value "C")
      (footprint "SMD_0603_CAPC1608X95N")
      (fields
        (field (name "DB_PART_NUMBER") "CAP000028169")
        (field (name "DB_VALUE") "470nF")
        (field (name "DB_TOLERANCE") "5%")
        (field (name "DB_VOLTAGE") "16V")
        (field (name "DB_MANUFACTURER_PART") "KEMET    C0603C474J4RAC")
        (field (name "DB_APPROVED_BY") "ISHIDDEN=T")
      )
      (libsource (lib "Database_Libs1") (part "C"))
    )
    (comp (ref "C266")
      (value "C")
      (footprint "SMD_0603_CAPC1608X95N")
      (fields
        (field (name "DB_PART_NUMBER") "CAP000028169")
        (field (name "DB_VALUE") "470nF")
        (field (name "DB_TOLERANCE") "5%")
        (field (name "DB_VOLTAGE") "16V")
        (field (name "DB_MANUFACTURER_PART") "KEMET    C0603C474J4RAC")
        (field (name "DB_APPROVED_BY") "ISHIDDEN=T")
      )
      (libsource (lib "Database_Libs1") (part "C"))
    )
    (comp (ref "C267")
      (value "C")
      (footprint "SMD_0603_CAPC1608X95N")
      (fields
        (field (name "DB_PART_NUMBER") "CAP000028169")
        (field (name "DB_VALUE") "470nF")
        (field (name "DB_TOLERANCE") "5%")
        (field (name "DB_VOLTAGE") "16V")
        (field (name "DB_MANUFACTURER_PART") "KEMET    C0603C474J4RAC")
        (field (name "DB_APPROVED_BY") "ISHIDDEN=T")
      )
      (libsource (lib "Database_Libs1") (part "C"))
    )
    (comp (ref "C268")
      (value "C")
      (footprint "SMD_0603_CAPC1608X95N")
      (fields
        (field (name "DB_PART_NUMBER") "CAP000028169")
        (field (name "DB_VALUE") "470nF")
        (field (name "DB_TOLERANCE") "5%")
        (field (name "DB_VOLTAGE") "16V")
        (field (name "DB_MANUFACTURER_PART") "KEMET    C0603C474J4RAC")
        (field (name "DB_APPROVED_BY") "ISHIDDEN=T")
      )
      (libsource (lib "Database_Libs1") (part "C"))
    )
    (comp (ref "C269")
      (value "C")
      (footprint "SMD_0603_CAPC1608X95N")
      (fields
        (field (name "DB_PART_NUMBER") "CAP000028169")
        (field (name "DB_VALUE") "470nF")
        (field (name "DB_TOLERANCE") "5%")
        (field (name "DB_VOLTAGE") "16V")
        (field (name "DB_MANUFACTURER_PART") "KEMET    C0603C474J4RAC")
        (field (name "DB_APPROVED_BY") "ISHIDDEN=T")
      )
      (libsource (lib "Database_Libs1") (part "C"))
    )
    (comp (ref "C270")
      (value "C")
      (footprint "SMD_0603_CAPC1608X95N")
      (fields
        (field (name "DB_PART_NUMBER") "CAP000028169")
        (field (name "DB_VALUE") "470nF")
        (field (name "DB_TOLERANCE") "5%")
        (field (name "DB_VOLTAGE") "16V")
        (field (name "DB_MANUFACTURER_PART") "KEMET    C0603C474J4RAC")
        (field (name "DB_APPROVED_BY") "ISHIDDEN=T")
      )
      (libsource (lib "Database_Libs1") (part "C"))
    )
    (comp (ref "C271")
      (value "C")
      (footprint "SMD_0603_CAPC1608X95N")
      (fields
        (field (name "DB_PART_NUMBER") "CAP000028169")
        (field (name "DB_VALUE") "470nF")
        (field (name "DB_TOLERANCE") "5%")
        (field (name "DB_VOLTAGE") "16V")
        (field (name "DB_MANUFACTURER_PART") "KEMET    C0603C474J4RAC")
        (field (name "DB_APPROVED_BY") "ISHIDDEN=T")
      )
      (libsource (lib "Database_Libs1") (part "C"))
    )
    (comp (ref "C272")
      (value "C")
      (footprint "SMD_0603_CAPC1608X95N")
      (fields
        (field (name "DB_PART_NUMBER") "CAP000028169")
        (field (name "DB_VALUE") "470nF")
        (field (name "DB_TOLERANCE") "5%")
        (field (name "DB_VOLTAGE") "16V")
        (field (name "DB_MANUFACTURER_PART") "KEMET    C0603C474J4RAC")
        (field (name "DB_APPROVED_BY") "ISHIDDEN=T")
      )
      (libsource (lib "Database_Libs1") (part "C"))
    )
    (comp (ref "C273")
      (value "C")
      (footprint "SMD_0603_CAPC1608X95N")
      (fields
        (field (name "DB_PART_NUMBER") "CAP000028169")
        (field (name "DB_VALUE") "470nF")
        (field (name "DB_TOLERANCE") "5%")
        (field (name "DB_VOLTAGE") "16V")
        (field (name "DB_MANUFACTURER_PART") "KEMET    C0603C474J4RAC")
        (field (name "DB_APPROVED_BY") "ISHIDDEN=T")
      )
      (libsource (lib "Database_Libs1") (part "C"))
    )
    (comp (ref "C274")
      (value "C")
      (footprint "SMD_0805_CAPC2012X145N")
      (fields
        (field (name "DB_PART_NUMBER") "CAP000043686")
        (field (name "DB_VALUE") "22uF")
        (field (name "DB_TOLERANCE") "20%")
        (field (name "DB_VOLTAGE") "6.3V")
        (field (name "DB_MANUFACTURER_PART") "KEMET    C0805C226M9PAC")
        (field (name "DB_APPROVED_BY") "ISHIDDEN=T")
      )
      (libsource (lib "Database_Libs1") (part "C"))
    )
    (comp (ref "C275")
      (value "C")
      (footprint "SMD_0805_CAPC2012X145N")
      (fields
        (field (name "DB_PART_NUMBER") "CAP000043636")
        (field (name "DB_VALUE") "10uF")
        (field (name "DB_TOLERANCE") "10%")
        (field (name "DB_VOLTAGE") "16V")
        (field (name "DB_MANUFACTURER_PART") "KEMET    C0805C106K4PAC")
        (field (name "DB_APPROVED_BY") "ISHIDDEN=T")
      )
      (libsource (lib "Database_Libs1") (part "C"))
    )
    (comp (ref "C276")
      (value "C")
      (footprint "SMD_0603_CAPC1608X95N")
      (fields
        (field (name "DB_PART_NUMBER") "CAP000028169")
        (field (name "DB_VALUE") "470nF")
        (field (name "DB_TOLERANCE") "5%")
        (field (name "DB_VOLTAGE") "16V")
        (field (name "DB_MANUFACTURER_PART") "KEMET    C0603C474J4RAC")
        (field (name "DB_APPROVED_BY") "ISHIDDEN=T")
      )
      (libsource (lib "Database_Libs1") (part "C"))
    )
    (comp (ref "C277")
      (value "C")
      (footprint "SMD_0603_CAPC1608X95N")
      (fields
        (field (name "DB_PART_NUMBER") "CAP000028169")
        (field (name "DB_VALUE") "470nF")
        (field (name "DB_TOLERANCE") "5%")
        (field (name "DB_VOLTAGE") "16V")
        (field (name "DB_MANUFACTURER_PART") "KEMET    C0603C474J4RAC")
        (field (name "DB_APPROVED_BY") "ISHIDDEN=T")
      )
      (libsource (lib "Database_Libs1") (part "C"))
    )
    (comp (ref "C278")
      (value "C")
      (footprint "SMD_0603_CAPC1608X95N")
      (fields
        (field (name "DB_PART_NUMBER") "CAP000028169")
        (field (name "DB_VALUE") "470nF")
        (field (name "DB_TOLERANCE") "5%")
        (field (name "DB_VOLTAGE") "16V")
        (field (name "DB_MANUFACTURER_PART") "KEMET    C0603C474J4RAC")
        (field (name "DB_APPROVED_BY") "ISHIDDEN=T")
      )
      (libsource (lib "Database_Libs1") (part "C"))
    )
    (comp (ref "C279")
      (value "C")
      (footprint "SMD_0603_CAPC1608X95N")
      (fields
        (field (name "DB_PART_NUMBER") "CAP000028169")
        (field (name "DB_VALUE") "470nF")
        (field (name "DB_TOLERANCE") "5%")
        (field (name "DB_VOLTAGE") "16V")
        (field (name "DB_MANUFACTURER_PART") "KEMET    C0603C474J4RAC")
        (field (name "DB_APPROVED_BY") "ISHIDDEN=T")
      )
      (libsource (lib "Database_Libs1") (part "C"))
    )
    (comp (ref "C280")
      (value "C")
      (footprint "SMD_0603_CAPC1608X95N")
      (fields
        (field (name "DB_PART_NUMBER") "CAP000028169")
        (field (name "DB_VALUE") "470nF")
        (field (name "DB_TOLERANCE") "5%")
        (field (name "DB_VOLTAGE") "16V")
        (field (name "DB_MANUFACTURER_PART") "KEMET    C0603C474J4RAC")
        (field (name "DB_APPROVED_BY") "ISHIDDEN=T")
      )
      (libsource (lib "Database_Libs1") (part "C"))
    )
    (comp (ref "C281")
      (value "C")
      (footprint "SMD_0603_CAPC1608X95N")
      (fields
        (field (name "DB_PART_NUMBER") "CAP000028169")
        (field (name "DB_VALUE") "470nF")
        (field (name "DB_TOLERANCE") "5%")
        (field (name "DB_VOLTAGE") "16V")
        (field (name "DB_MANUFACTURER_PART") "KEMET    C0603C474J4RAC")
        (field (name "DB_APPROVED_BY") "ISHIDDEN=T")
      )
      (libsource (lib "Database_Libs1") (part "C"))
    )
    (comp (ref "C282")
      (value "C")
      (footprint "SMD_0603_CAPC1608X95N")
      (fields
        (field (name "DB_PART_NUMBER") "CAP000028169")
        (field (name "DB_VALUE") "470nF")
        (field (name "DB_TOLERANCE") "5%")
        (field (name "DB_VOLTAGE") "16V")
        (field (name "DB_MANUFACTURER_PART") "KEMET    C0603C474J4RAC")
        (field (name "DB_APPROVED_BY") "ISHIDDEN=T")
      )
      (libsource (lib "Database_Libs1") (part "C"))
    )
    (comp (ref "C283")
      (value "C")
      (footprint "SMD_0603_CAPC1608X95N")
      (fields
        (field (name "DB_PART_NUMBER") "CAP000028169")
        (field (name "DB_VALUE") "470nF")
        (field (name "DB_TOLERANCE") "5%")
        (field (name "DB_VOLTAGE") "16V")
        (field (name "DB_MANUFACTURER_PART") "KEMET    C0603C474J4RAC")
        (field (name "DB_APPROVED_BY") "ISHIDDEN=T")
      )
      (libsource (lib "Database_Libs1") (part "C"))
    )
    (comp (ref "C284")
      (value "C")
      (footprint "SMD_0603_CAPC1608X95N")
      (fields
        (field (name "DB_PART_NUMBER") "CAP000028169")
        (field (name "DB_VALUE") "470nF")
        (field (name "DB_TOLERANCE") "5%")
        (field (name "DB_VOLTAGE") "16V")
        (field (name "DB_MANUFACTURER_PART") "KEMET    C0603C474J4RAC")
        (field (name "DB_APPROVED_BY") "ISHIDDEN=T")
      )
      (libsource (lib "Database_Libs1") (part "C"))
    )
    (comp (ref "C285")
      (value "C")
      (footprint "SMD_0603_CAPC1608X95N")
      (fields
        (field (name "DB_PART_NUMBER") "CAP000028169")
        (field (name "DB_VALUE") "470nF")
        (field (name "DB_TOLERANCE") "5%")
        (field (name "DB_VOLTAGE") "16V")
        (field (name "DB_MANUFACTURER_PART") "KEMET    C0603C474J4RAC")
        (field (name "DB_APPROVED_BY") "ISHIDDEN=T")
      )
      (libsource (lib "Database_Libs1") (part "C"))
    )
    (comp (ref "C286")
      (value "C")
      (footprint "SMD_0603_CAPC1608X95N")
      (fields
        (field (name "DB_PART_NUMBER") "CAP000028169")
        (field (name "DB_VALUE") "470nF")
        (field (name "DB_TOLERANCE") "5%")
        (field (name "DB_VOLTAGE") "16V")
        (field (name "DB_MANUFACTURER_PART") "KEMET    C0603C474J4RAC")
        (field (name "DB_APPROVED_BY") "ISHIDDEN=T")
      )
      (libsource (lib "Database_Libs1") (part "C"))
    )
    (comp (ref "C287")
      (value "C")
      (footprint "SMD_0603_CAPC1608X95N")
      (fields
        (field (name "DB_PART_NUMBER") "CAP000028169")
        (field (name "DB_VALUE") "470nF")
        (field (name "DB_TOLERANCE") "5%")
        (field (name "DB_VOLTAGE") "16V")
        (field (name "DB_MANUFACTURER_PART") "KEMET    C0603C474J4RAC")
        (field (name "DB_APPROVED_BY") "ISHIDDEN=T")
      )
      (libsource (lib "Database_Libs1") (part "C"))
    )
    (comp (ref "C288")
      (value "C")
      (footprint "SMD_0603_CAPC1608X95N")
      (fields
        (field (name "DB_PART_NUMBER") "CAP000028169")
        (field (name "DB_VALUE") "470nF")
        (field (name "DB_TOLERANCE") "5%")
        (field (name "DB_VOLTAGE") "16V")
        (field (name "DB_MANUFACTURER_PART") "KEMET    C0603C474J4RAC")
        (field (name "DB_APPROVED_BY") "ISHIDDEN=T")
      )
      (libsource (lib "Database_Libs1") (part "C"))
    )
    (comp (ref "C289")
      (value "C")
      (footprint "SMD_0603_CAPC1608X95N")
      (fields
        (field (name "DB_PART_NUMBER") "CAP000028169")
        (field (name "DB_VALUE") "470nF")
        (field (name "DB_TOLERANCE") "5%")
        (field (name "DB_VOLTAGE") "16V")
        (field (name "DB_MANUFACTURER_PART") "KEMET    C0603C474J4RAC")
        (field (name "DB_APPROVED_BY") "ISHIDDEN=T")
      )
      (libsource (lib "Database_Libs1") (part "C"))
    )
    (comp (ref "C290")
      (value "C")
      (footprint "SMD_0603_CAPC1608X95N")
      (fields
        (field (name "DB_PART_NUMBER") "CAP000028169")
        (field (name "DB_VALUE") "470nF")
        (field (name "DB_TOLERANCE") "5%")
        (field (name "DB_VOLTAGE") "16V")
        (field (name "DB_MANUFACTURER_PART") "KEMET    C0603C474J4RAC")
        (field (name "DB_APPROVED_BY") "ISHIDDEN=T")
      )
      (libsource (lib "Database_Libs1") (part "C"))
    )
    (comp (ref "C291")
      (value "C")
      (footprint "SMD_0603_CAPC1608X95N")
      (fields
        (field (name "DB_PART_NUMBER") "CAP000028169")
        (field (name "DB_VALUE") "470nF")
        (field (name "DB_TOLERANCE") "5%")
        (field (name "DB_VOLTAGE") "16V")
        (field (name "DB_MANUFACTURER_PART") "KEMET    C0603C474J4RAC")
        (field (name "DB_APPROVED_BY") "ISHIDDEN=T")
      )
      (libsource (lib "Database_Libs1") (part "C"))
    )
    (comp (ref "C324")
      (value "C")
      (footprint "SMD_0603_CAPC1608X95N")
      (fields
        (field (name "DB_PART_NUMBER") "CAP000028169")
        (field (name "DB_VALUE") "470nF")
        (field (name "DB_TOLERANCE") "5%")
        (field (name "DB_VOLTAGE") "16V")
        (field (name "DB_MANUFACTURER_PART") "KEMET    C0603C474J4RAC")
        (field (name "DB_APPROVED_BY") "ISHIDDEN=T")
      )
      (libsource (lib "Database_Libs1") (part "C"))
    )
    (comp (ref "C325")
      (value "C")
      (footprint "SMD_0603_CAPC1608X95N")
      (fields
        (field (name "DB_PART_NUMBER") "CAP000028169")
        (field (name "DB_VALUE") "470nF")
        (field (name "DB_TOLERANCE") "5%")
        (field (name "DB_VOLTAGE") "16V")
        (field (name "DB_MANUFACTURER_PART") "KEMET    C0603C474J4RAC")
        (field (name "DB_APPROVED_BY") "ISHIDDEN=T")
      )
      (libsource (lib "Database_Libs1") (part "C"))
    )
    (comp (ref "C326")
      (value "C")
      (footprint "SMD_0603_CAPC1608X95N")
      (fields
        (field (name "DB_PART_NUMBER") "CAP000028169")
        (field (name "DB_VALUE") "470nF")
        (field (name "DB_TOLERANCE") "5%")
        (field (name "DB_VOLTAGE") "16V")
        (field (name "DB_MANUFACTURER_PART") "KEMET    C0603C474J4RAC")
        (field (name "DB_APPROVED_BY") "ISHIDDEN=T")
      )
      (libsource (lib "Database_Libs1") (part "C"))
    )
    (comp (ref "C327")
      (value "C")
      (footprint "SMD_0603_CAPC1608X95N")
      (fields
        (field (name "DB_PART_NUMBER") "CAP000028169")
        (field (name "DB_VALUE") "470nF")
        (field (name "DB_TOLERANCE") "5%")
        (field (name "DB_VOLTAGE") "16V")
        (field (name "DB_MANUFACTURER_PART") "KEMET    C0603C474J4RAC")
        (field (name "DB_APPROVED_BY") "ISHIDDEN=T")
      )
      (libsource (lib "Database_Libs1") (part "C"))
    )
    (comp (ref "C328")
      (value "C")
      (footprint "SMD_0603_CAPC1608X95N")
      (fields
        (field (name "DB_PART_NUMBER") "CAP000028169")
        (field (name "DB_VALUE") "470nF")
        (field (name "DB_TOLERANCE") "5%")
        (field (name "DB_VOLTAGE") "16V")
        (field (name "DB_MANUFACTURER_PART") "KEMET    C0603C474J4RAC")
        (field (name "DB_APPROVED_BY") "ISHIDDEN=T")
      )
      (libsource (lib "Database_Libs1") (part "C"))
    )
    (comp (ref "C329")
      (value "C")
      (footprint "SMD_0603_CAPC1608X95N")
      (fields
        (field (name "DB_PART_NUMBER") "CAP000028169")
        (field (name "DB_VALUE") "470nF")
        (field (name "DB_TOLERANCE") "5%")
        (field (name "DB_VOLTAGE") "16V")
        (field (name "DB_MANUFACTURER_PART") "KEMET    C0603C474J4RAC")
        (field (name "DB_APPROVED_BY") "ISHIDDEN=T")
      )
      (libsource (lib "Database_Libs1") (part "C"))
    )
    (comp (ref "C330")
      (value "C")
      (footprint "SMD_0603_CAPC1608X95N")
      (fields
        (field (name "DB_PART_NUMBER") "CAP000028169")
        (field (name "DB_VALUE") "470nF")
        (field (name "DB_TOLERANCE") "5%")
        (field (name "DB_VOLTAGE") "16V")
        (field (name "DB_MANUFACTURER_PART") "KEMET    C0603C474J4RAC")
        (field (name "DB_APPROVED_BY") "ISHIDDEN=T")
      )
      (libsource (lib "Database_Libs1") (part "C"))
    )
    (comp (ref "C331")
      (value "C")
      (footprint "SMD_0603_CAPC1608X95N")
      (fields
        (field (name "DB_PART_NUMBER") "CAP000028169")
        (field (name "DB_VALUE") "470nF")
        (field (name "DB_TOLERANCE") "5%")
        (field (name "DB_VOLTAGE") "16V")
        (field (name "DB_MANUFACTURER_PART") "KEMET    C0603C474J4RAC")
        (field (name "DB_APPROVED_BY") "ISHIDDEN=T")
      )
      (libsource (lib "Database_Libs1") (part "C"))
    )
    (comp (ref "C332")
      (value "C")
      (footprint "SMD_0603_CAPC1608X95N")
      (fields
        (field (name "DB_PART_NUMBER") "CAP000028169")
        (field (name "DB_VALUE") "470nF")
        (field (name "DB_TOLERANCE") "5%")
        (field (name "DB_VOLTAGE") "16V")
        (field (name "DB_MANUFACTURER_PART") "KEMET    C0603C474J4RAC")
        (field (name "DB_APPROVED_BY") "ISHIDDEN=T")
      )
      (libsource (lib "Database_Libs1") (part "C"))
    )
    (comp (ref "C333")
      (value "C")
      (footprint "SMD_0603_CAPC1608X95N")
      (fields
        (field (name "DB_PART_NUMBER") "CAP000028169")
        (field (name "DB_VALUE") "470nF")
        (field (name "DB_TOLERANCE") "5%")
        (field (name "DB_VOLTAGE") "16V")
        (field (name "DB_MANUFACTURER_PART") "KEMET    C0603C474J4RAC")
        (field (name "DB_APPROVED_BY") "ISHIDDEN=T")
      )
      (libsource (lib "Database_Libs1") (part "C"))
    )
    (comp (ref "C334")
      (value "C")
      (footprint "SMD_0603_CAPC1608X95N")
      (fields
        (field (name "DB_PART_NUMBER") "CAP000028169")
        (field (name "DB_VALUE") "470nF")
        (field (name "DB_TOLERANCE") "5%")
        (field (name "DB_VOLTAGE") "16V")
        (field (name "DB_MANUFACTURER_PART") "KEMET    C0603C474J4RAC")
        (field (name "DB_APPROVED_BY") "ISHIDDEN=T")
      )
      (libsource (lib "Database_Libs1") (part "C"))
    )
    (comp (ref "C335")
      (value "C")
      (footprint "SMD_0603_CAPC1608X95N")
      (fields
        (field (name "DB_PART_NUMBER") "CAP000028169")
        (field (name "DB_VALUE") "470nF")
        (field (name "DB_TOLERANCE") "5%")
        (field (name "DB_VOLTAGE") "16V")
        (field (name "DB_MANUFACTURER_PART") "KEMET    C0603C474J4RAC")
        (field (name "DB_APPROVED_BY") "ISHIDDEN=T")
      )
      (libsource (lib "Database_Libs1") (part "C"))
    )
    (comp (ref "C336")
      (value "C")
      (footprint "SMD_0603_CAPC1608X95N")
      (fields
        (field (name "DB_PART_NUMBER") "CAP000028169")
        (field (name "DB_VALUE") "470nF")
        (field (name "DB_TOLERANCE") "5%")
        (field (name "DB_VOLTAGE") "16V")
        (field (name "DB_MANUFACTURER_PART") "KEMET    C0603C474J4RAC")
        (field (name "DB_APPROVED_BY") "ISHIDDEN=T")
      )
      (libsource (lib "Database_Libs1") (part "C"))
    )
    (comp (ref "C337")
      (value "C")
      (footprint "SMD_0603_CAPC1608X95N")
      (fields
        (field (name "DB_PART_NUMBER") "CAP000028169")
        (field (name "DB_VALUE") "470nF")
        (field (name "DB_TOLERANCE") "5%")
        (field (name "DB_VOLTAGE") "16V")
        (field (name "DB_MANUFACTURER_PART") "KEMET    C0603C474J4RAC")
        (field (name "DB_APPROVED_BY") "ISHIDDEN=T")
      )
      (libsource (lib "Database_Libs1") (part "C"))
    )
    (comp (ref "C338")
      (value "C")
      (footprint "SMD_0603_CAPC1608X95N")
      (fields
        (field (name "DB_PART_NUMBER") "CAP000028169")
        (field (name "DB_VALUE") "470nF")
        (field (name "DB_TOLERANCE") "5%")
        (field (name "DB_VOLTAGE") "16V")
        (field (name "DB_MANUFACTURER_PART") "KEMET    C0603C474J4RAC")
        (field (name "DB_APPROVED_BY") "ISHIDDEN=T")
      )
      (libsource (lib "Database_Libs1") (part "C"))
    )
    (comp (ref "C339")
      (value "C")
      (footprint "SMD_0603_CAPC1608X95N")
      (fields
        (field (name "DB_PART_NUMBER") "CAP000028169")
        (field (name "DB_VALUE") "470nF")
        (field (name "DB_TOLERANCE") "5%")
        (field (name "DB_VOLTAGE") "16V")
        (field (name "DB_MANUFACTURER_PART") "KEMET    C0603C474J4RAC")
        (field (name "DB_APPROVED_BY") "ISHIDDEN=T")
      )
      (libsource (lib "Database_Libs1") (part "C"))
    )
    (comp (ref "C340")
      (value "C")
      (footprint "SMD_0603_CAPC1608X95N")
      (fields
        (field (name "DB_PART_NUMBER") "CAP000028169")
        (field (name "DB_VALUE") "470nF")
        (field (name "DB_TOLERANCE") "5%")
        (field (name "DB_VOLTAGE") "16V")
        (field (name "DB_MANUFACTURER_PART") "KEMET    C0603C474J4RAC")
        (field (name "DB_APPROVED_BY") "ISHIDDEN=T")
      )
      (libsource (lib "Database_Libs1") (part "C"))
    )
    (comp (ref "C341")
      (value "C")
      (footprint "SMD_0603_CAPC1608X95N")
      (fields
        (field (name "DB_PART_NUMBER") "CAP000028169")
        (field (name "DB_VALUE") "470nF")
        (field (name "DB_TOLERANCE") "5%")
        (field (name "DB_VOLTAGE") "16V")
        (field (name "DB_MANUFACTURER_PART") "KEMET    C0603C474J4RAC")
        (field (name "DB_APPROVED_BY") "ISHIDDEN=T")
      )
      (libsource (lib "Database_Libs1") (part "C"))
    )
    (comp (ref "C342")
      (value "C")
      (footprint "SMD_0603_CAPC1608X95N")
      (fields
        (field (name "DB_PART_NUMBER") "CAP000028169")
        (field (name "DB_VALUE") "470nF")
        (field (name "DB_TOLERANCE") "5%")
        (field (name "DB_VOLTAGE") "16V")
        (field (name "DB_MANUFACTURER_PART") "KEMET    C0603C474J4RAC")
        (field (name "DB_APPROVED_BY") "ISHIDDEN=T")
      )
      (libsource (lib "Database_Libs1") (part "C"))
    )
    (comp (ref "C343")
      (value "C")
      (footprint "SMD_0603_CAPC1608X95N")
      (fields
        (field (name "DB_PART_NUMBER") "CAP000028169")
        (field (name "DB_VALUE") "470nF")
        (field (name "DB_TOLERANCE") "5%")
        (field (name "DB_VOLTAGE") "16V")
        (field (name "DB_MANUFACTURER_PART") "KEMET    C0603C474J4RAC")
        (field (name "DB_APPROVED_BY") "ISHIDDEN=T")
      )
      (libsource (lib "Database_Libs1") (part "C"))
    )
    (comp (ref "C344")
      (value "C")
      (footprint "SMD_0603_CAPC1608X95N")
      (fields
        (field (name "DB_PART_NUMBER") "CAP000028169")
        (field (name "DB_VALUE") "470nF")
        (field (name "DB_TOLERANCE") "5%")
        (field (name "DB_VOLTAGE") "16V")
        (field (name "DB_MANUFACTURER_PART") "KEMET    C0603C474J4RAC")
        (field (name "DB_APPROVED_BY") "ISHIDDEN=T")
      )
      (libsource (lib "Database_Libs1") (part "C"))
    )
    (comp (ref "C345")
      (value "C")
      (footprint "SMD_0603_CAPC1608X95N")
      (fields
        (field (name "DB_PART_NUMBER") "CAP000028169")
        (field (name "DB_VALUE") "470nF")
        (field (name "DB_TOLERANCE") "5%")
        (field (name "DB_VOLTAGE") "16V")
        (field (name "DB_MANUFACTURER_PART") "KEMET    C0603C474J4RAC")
        (field (name "DB_APPROVED_BY") "ISHIDDEN=T")
      )
      (libsource (lib "Database_Libs1") (part "C"))
    )
    (comp (ref "C346")
      (value "C")
      (footprint "SMD_0603_CAPC1608X95N")
      (fields
        (field (name "DB_PART_NUMBER") "CAP000028169")
        (field (name "DB_VALUE") "470nF")
        (field (name "DB_TOLERANCE") "5%")
        (field (name "DB_VOLTAGE") "16V")
        (field (name "DB_MANUFACTURER_PART") "KEMET    C0603C474J4RAC")
        (field (name "DB_APPROVED_BY") "ISHIDDEN=T")
      )
      (libsource (lib "Database_Libs1") (part "C"))
    )
    (comp (ref "C347")
      (value "C")
      (footprint "SMD_0603_CAPC1608X95N")
      (fields
        (field (name "DB_PART_NUMBER") "CAP000028169")
        (field (name "DB_VALUE") "470nF")
        (field (name "DB_TOLERANCE") "5%")
        (field (name "DB_VOLTAGE") "16V")
        (field (name "DB_MANUFACTURER_PART") "KEMET    C0603C474J4RAC")
        (field (name "DB_APPROVED_BY") "ISHIDDEN=T")
      )
      (libsource (lib "Database_Libs1") (part "C"))
    )
    (comp (ref "C348")
      (value "C")
      (footprint "SMD_0603_CAPC1608X95N")
      (fields
        (field (name "DB_PART_NUMBER") "CAP000028169")
        (field (name "DB_VALUE") "470nF")
        (field (name "DB_TOLERANCE") "5%")
        (field (name "DB_VOLTAGE") "16V")
        (field (name "DB_MANUFACTURER_PART") "KEMET    C0603C474J4RAC")
        (field (name "DB_APPROVED_BY") "ISHIDDEN=T")
      )
      (libsource (lib "Database_Libs1") (part "C"))
    )
    (comp (ref "C349")
      (value "C")
      (footprint "SMD_0603_CAPC1608X95N")
      (fields
        (field (name "DB_PART_NUMBER") "CAP000028169")
        (field (name "DB_VALUE") "470nF")
        (field (name "DB_TOLERANCE") "5%")
        (field (name "DB_VOLTAGE") "16V")
        (field (name "DB_MANUFACTURER_PART") "KEMET    C0603C474J4RAC")
        (field (name "DB_APPROVED_BY") "ISHIDDEN=T")
      )
      (libsource (lib "Database_Libs1") (part "C"))
    )
    (comp (ref "C350")
      (value "C")
      (footprint "SMD_0603_CAPC1608X95N")
      (fields
        (field (name "DB_PART_NUMBER") "CAP000028169")
        (field (name "DB_VALUE") "470nF")
        (field (name "DB_TOLERANCE") "5%")
        (field (name "DB_VOLTAGE") "16V")
        (field (name "DB_MANUFACTURER_PART") "KEMET    C0603C474J4RAC")
        (field (name "DB_APPROVED_BY") "ISHIDDEN=T")
      )
      (libsource (lib "Database_Libs1") (part "C"))
    )
    (comp (ref "C351")
      (value "C")
      (footprint "SMD_0603_CAPC1608X95N")
      (fields
        (field (name "DB_PART_NUMBER") "CAP000028169")
        (field (name "DB_VALUE") "470nF")
        (field (name "DB_TOLERANCE") "5%")
        (field (name "DB_VOLTAGE") "16V")
        (field (name "DB_MANUFACTURER_PART") "KEMET    C0603C474J4RAC")
        (field (name "DB_APPROVED_BY") "ISHIDDEN=T")
      )
      (libsource (lib "Database_Libs1") (part "C"))
    )
    (comp (ref "C352")
      (value "C")
      (footprint "SMD_0603_CAPC1608X95N")
      (fields
        (field (name "DB_PART_NUMBER") "CAP000028169")
        (field (name "DB_VALUE") "470nF")
        (field (name "DB_TOLERANCE") "5%")
        (field (name "DB_VOLTAGE") "16V")
        (field (name "DB_MANUFACTURER_PART") "KEMET    C0603C474J4RAC")
        (field (name "DB_APPROVED_BY") "ISHIDDEN=T")
      )
      (libsource (lib "Database_Libs1") (part "C"))
    )
    (comp (ref "C353")
      (value "C")
      (footprint "SMD_0603_CAPC1608X95N")
      (fields
        (field (name "DB_PART_NUMBER") "CAP000028169")
        (field (name "DB_VALUE") "470nF")
        (field (name "DB_TOLERANCE") "5%")
        (field (name "DB_VOLTAGE") "16V")
        (field (name "DB_MANUFACTURER_PART") "KEMET    C0603C474J4RAC")
        (field (name "DB_APPROVED_BY") "ISHIDDEN=T")
      )
      (libsource (lib "Database_Libs1") (part "C"))
    )
    (comp (ref "C354")
      (value "C")
      (footprint "SMD_0603_CAPC1608X95N")
      (fields
        (field (name "DB_PART_NUMBER") "CAP000028169")
        (field (name "DB_VALUE") "470nF")
        (field (name "DB_TOLERANCE") "5%")
        (field (name "DB_VOLTAGE") "16V")
        (field (name "DB_MANUFACTURER_PART") "KEMET    C0603C474J4RAC")
        (field (name "DB_APPROVED_BY") "ISHIDDEN=T")
      )
      (libsource (lib "Database_Libs1") (part "C"))
    )
    (comp (ref "C355")
      (value "C")
      (footprint "SMD_0603_CAPC1608X95N")
      (fields
        (field (name "DB_PART_NUMBER") "CAP000028169")
        (field (name "DB_VALUE") "470nF")
        (field (name "DB_TOLERANCE") "5%")
        (field (name "DB_VOLTAGE") "16V")
        (field (name "DB_MANUFACTURER_PART") "KEMET    C0603C474J4RAC")
        (field (name "DB_APPROVED_BY") "ISHIDDEN=T")
      )
      (libsource (lib "Database_Libs1") (part "C"))
    )
    (comp (ref "C356")
      (value "C")
      (footprint "SMD_0603_CAPC1608X95N")
      (fields
        (field (name "DB_PART_NUMBER") "CAP000028169")
        (field (name "DB_VALUE") "470nF")
        (field (name "DB_TOLERANCE") "5%")
        (field (name "DB_VOLTAGE") "16V")
        (field (name "DB_MANUFACTURER_PART") "KEMET    C0603C474J4RAC")
        (field (name "DB_APPROVED_BY") "ISHIDDEN=T")
      )
      (libsource (lib "Database_Libs1") (part "C"))
    )
    (comp (ref "C357")
      (value "C")
      (footprint "SMD_0603_CAPC1608X95N")
      (fields
        (field (name "DB_PART_NUMBER") "CAP000028169")
        (field (name "DB_VALUE") "470nF")
        (field (name "DB_TOLERANCE") "5%")
        (field (name "DB_VOLTAGE") "16V")
        (field (name "DB_MANUFACTURER_PART") "KEMET    C0603C474J4RAC")
        (field (name "DB_APPROVED_BY") "ISHIDDEN=T")
      )
      (libsource (lib "Database_Libs1") (part "C"))
    )
    (comp (ref "C358")
      (value "C")
      (footprint "SMD_0603_CAPC1608X95N")
      (fields
        (field (name "DB_PART_NUMBER") "CAP000028169")
        (field (name "DB_VALUE") "470nF")
        (field (name "DB_TOLERANCE") "5%")
        (field (name "DB_VOLTAGE") "16V")
        (field (name "DB_MANUFACTURER_PART") "KEMET    C0603C474J4RAC")
        (field (name "DB_APPROVED_BY") "ISHIDDEN=T")
      )
      (libsource (lib "Database_Libs1") (part "C"))
    )
    (comp (ref "C359")
      (value "C")
      (footprint "SMD_0603_CAPC1608X95N")
      (fields
        (field (name "DB_PART_NUMBER") "CAP000028169")
        (field (name "DB_VALUE") "470nF")
        (field (name "DB_TOLERANCE") "5%")
        (field (name "DB_VOLTAGE") "16V")
        (field (name "DB_MANUFACTURER_PART") "KEMET    C0603C474J4RAC")
        (field (name "DB_APPROVED_BY") "ISHIDDEN=T")
      )
      (libsource (lib "Database_Libs1") (part "C"))
    )
    (comp (ref "C360")
      (value "C")
      (footprint "SMD_0603_CAPC1608X95N")
      (fields
        (field (name "DB_PART_NUMBER") "CAP000028169")
        (field (name "DB_VALUE") "470nF")
        (field (name "DB_TOLERANCE") "5%")
        (field (name "DB_VOLTAGE") "16V")
        (field (name "DB_MANUFACTURER_PART") "KEMET    C0603C474J4RAC")
        (field (name "DB_APPROVED_BY") "ISHIDDEN=T")
      )
      (libsource (lib "Database_Libs1") (part "C"))
    )
    (comp (ref "C361")
      (value "C")
      (footprint "SMD_0603_CAPC1608X95N")
      (fields
        (field (name "DB_PART_NUMBER") "CAP000028169")
        (field (name "DB_VALUE") "470nF")
        (field (name "DB_TOLERANCE") "5%")
        (field (name "DB_VOLTAGE") "16V")
        (field (name "DB_MANUFACTURER_PART") "KEMET    C0603C474J4RAC")
        (field (name "DB_APPROVED_BY") "ISHIDDEN=T")
      )
      (libsource (lib "Database_Libs1") (part "C"))
    )
    (comp (ref "C362")
      (value "C")
      (footprint "SMD_0603_CAPC1608X95N")
      (fields
        (field (name "DB_PART_NUMBER") "CAP000028169")
        (field (name "DB_VALUE") "470nF")
        (field (name "DB_TOLERANCE") "5%")
        (field (name "DB_VOLTAGE") "16V")
        (field (name "DB_MANUFACTURER_PART") "KEMET    C0603C474J4RAC")
        (field (name "DB_APPROVED_BY") "ISHIDDEN=T")
      )
      (libsource (lib "Database_Libs1") (part "C"))
    )
    (comp (ref "C363")
      (value "C")
      (footprint "SMD_0603_CAPC1608X95N")
      (fields
        (field (name "DB_PART_NUMBER") "CAP000028169")
        (field (name "DB_VALUE") "470nF")
        (field (name "DB_TOLERANCE") "5%")
        (field (name "DB_VOLTAGE") "16V")
        (field (name "DB_MANUFACTURER_PART") "KEMET    C0603C474J4RAC")
        (field (name "DB_APPROVED_BY") "ISHIDDEN=T")
      )
      (libsource (lib "Database_Libs1") (part "C"))
    )
    (comp (ref "C364")
      (value "C")
      (footprint "SMD_0603_CAPC1608X95N")
      (fields
        (field (name "DB_PART_NUMBER") "CAP000028169")
        (field (name "DB_VALUE") "470nF")
        (field (name "DB_TOLERANCE") "5%")
        (field (name "DB_VOLTAGE") "16V")
        (field (name "DB_MANUFACTURER_PART") "KEMET    C0603C474J4RAC")
        (field (name "DB_APPROVED_BY") "ISHIDDEN=T")
      )
      (libsource (lib "Database_Libs1") (part "C"))
    )
    (comp (ref "C365")
      (value "C")
      (footprint "SMD_0603_CAPC1608X95N")
      (fields
        (field (name "DB_PART_NUMBER") "CAP000028169")
        (field (name "DB_VALUE") "470nF")
        (field (name "DB_TOLERANCE") "5%")
        (field (name "DB_VOLTAGE") "16V")
        (field (name "DB_MANUFACTURER_PART") "KEMET    C0603C474J4RAC")
        (field (name "DB_APPROVED_BY") "ISHIDDEN=T")
      )
      (libsource (lib "Database_Libs1") (part "C"))
    )
    (comp (ref "C366")
      (value "C")
      (footprint "SMD_0603_CAPC1608X95N")
      (fields
        (field (name "DB_PART_NUMBER") "CAP000028169")
        (field (name "DB_VALUE") "470nF")
        (field (name "DB_TOLERANCE") "5%")
        (field (name "DB_VOLTAGE") "16V")
        (field (name "DB_MANUFACTURER_PART") "KEMET    C0603C474J4RAC")
        (field (name "DB_APPROVED_BY") "ISHIDDEN=T")
      )
      (libsource (lib "Database_Libs1") (part "C"))
    )
    (comp (ref "C367")
      (value "C")
      (footprint "SMD_0603_CAPC1608X95N")
      (fields
        (field (name "DB_PART_NUMBER") "CAP000028169")
        (field (name "DB_VALUE") "470nF")
        (field (name "DB_TOLERANCE") "5%")
        (field (name "DB_VOLTAGE") "16V")
        (field (name "DB_MANUFACTURER_PART") "KEMET    C0603C474J4RAC")
        (field (name "DB_APPROVED_BY") "ISHIDDEN=T")
      )
      (libsource (lib "Database_Libs1") (part "C"))
    )
    (comp (ref "C368")
      (value "C")
      (footprint "SMD_0603_CAPC1608X95N")
      (fields
        (field (name "DB_PART_NUMBER") "CAP000028169")
        (field (name "DB_VALUE") "470nF")
        (field (name "DB_TOLERANCE") "5%")
        (field (name "DB_VOLTAGE") "16V")
        (field (name "DB_MANUFACTURER_PART") "KEMET    C0603C474J4RAC")
        (field (name "DB_APPROVED_BY") "ISHIDDEN=T")
      )
      (libsource (lib "Database_Libs1") (part "C"))
    )
    (comp (ref "C369")
      (value "C")
      (footprint "SMD_0603_CAPC1608X95N")
      (fields
        (field (name "DB_PART_NUMBER") "CAP000028169")
        (field (name "DB_VALUE") "470nF")
        (field (name "DB_TOLERANCE") "5%")
        (field (name "DB_VOLTAGE") "16V")
        (field (name "DB_MANUFACTURER_PART") "KEMET    C0603C474J4RAC")
        (field (name "DB_APPROVED_BY") "ISHIDDEN=T")
      )
      (libsource (lib "Database_Libs1") (part "C"))
    )
    (comp (ref "C370")
      (value "C")
      (footprint "SMD_0603_CAPC1608X95N")
      (fields
        (field (name "DB_PART_NUMBER") "CAP000028169")
        (field (name "DB_VALUE") "470nF")
        (field (name "DB_TOLERANCE") "5%")
        (field (name "DB_VOLTAGE") "16V")
        (field (name "DB_MANUFACTURER_PART") "KEMET    C0603C474J4RAC")
        (field (name "DB_APPROVED_BY") "ISHIDDEN=T")
      )
      (libsource (lib "Database_Libs1") (part "C"))
    )
    (comp (ref "C371")
      (value "C")
      (footprint "SMD_0603_CAPC1608X95N")
      (fields
        (field (name "DB_PART_NUMBER") "CAP000028169")
        (field (name "DB_VALUE") "470nF")
        (field (name "DB_TOLERANCE") "5%")
        (field (name "DB_VOLTAGE") "16V")
        (field (name "DB_MANUFACTURER_PART") "KEMET    C0603C474J4RAC")
        (field (name "DB_APPROVED_BY") "ISHIDDEN=T")
      )
      (libsource (lib "Database_Libs1") (part "C"))
    )
    (comp (ref "C372")
      (value "C")
      (footprint "SMD_0603_CAPC1608X95N")
      (fields
        (field (name "DB_PART_NUMBER") "CAP000028169")
        (field (name "DB_VALUE") "470nF")
        (field (name "DB_TOLERANCE") "5%")
        (field (name "DB_VOLTAGE") "16V")
        (field (name "DB_MANUFACTURER_PART") "KEMET    C0603C474J4RAC")
        (field (name "DB_APPROVED_BY") "ISHIDDEN=T")
      )
      (libsource (lib "Database_Libs1") (part "C"))
    )
    (comp (ref "C373")
      (value "C")
      (footprint "SMD_0603_CAPC1608X95N")
      (fields
        (field (name "DB_PART_NUMBER") "CAP000028169")
        (field (name "DB_VALUE") "470nF")
        (field (name "DB_TOLERANCE") "5%")
        (field (name "DB_VOLTAGE") "16V")
        (field (name "DB_MANUFACTURER_PART") "KEMET    C0603C474J4RAC")
        (field (name "DB_APPROVED_BY") "ISHIDDEN=T")
      )
      (libsource (lib "Database_Libs1") (part "C"))
    )
    (comp (ref "C374")
      (value "C")
      (footprint "SMD_0603_CAPC1608X95N")
      (fields
        (field (name "DB_PART_NUMBER") "CAP000028169")
        (field (name "DB_VALUE") "470nF")
        (field (name "DB_TOLERANCE") "5%")
        (field (name "DB_VOLTAGE") "16V")
        (field (name "DB_MANUFACTURER_PART") "KEMET    C0603C474J4RAC")
        (field (name "DB_APPROVED_BY") "ISHIDDEN=T")
      )
      (libsource (lib "Database_Libs1") (part "C"))
    )
    (comp (ref "C375")
      (value "C")
      (footprint "SMD_0603_CAPC1608X95N")
      (fields
        (field (name "DB_PART_NUMBER") "CAP000028169")
        (field (name "DB_VALUE") "470nF")
        (field (name "DB_TOLERANCE") "5%")
        (field (name "DB_VOLTAGE") "16V")
        (field (name "DB_MANUFACTURER_PART") "KEMET    C0603C474J4RAC")
        (field (name "DB_APPROVED_BY") "ISHIDDEN=T")
      )
      (libsource (lib "Database_Libs1") (part "C"))
    )
    (comp (ref "C376")
      (value "C")
      (footprint "SMD_0603_CAPC1608X95N")
      (fields
        (field (name "DB_PART_NUMBER") "CAP000028169")
        (field (name "DB_VALUE") "470nF")
        (field (name "DB_TOLERANCE") "5%")
        (field (name "DB_VOLTAGE") "16V")
        (field (name "DB_MANUFACTURER_PART") "KEMET    C0603C474J4RAC")
        (field (name "DB_APPROVED_BY") "ISHIDDEN=T")
      )
      (libsource (lib "Database_Libs1") (part "C"))
    )
    (comp (ref "C377")
      (value "C")
      (footprint "SMD_0603_CAPC1608X95N")
      (fields
        (field (name "DB_PART_NUMBER") "CAP000028169")
        (field (name "DB_VALUE") "470nF")
        (field (name "DB_TOLERANCE") "5%")
        (field (name "DB_VOLTAGE") "16V")
        (field (name "DB_MANUFACTURER_PART") "KEMET    C0603C474J4RAC")
        (field (name "DB_APPROVED_BY") "ISHIDDEN=T")
      )
      (libsource (lib "Database_Libs1") (part "C"))
    )
    (comp (ref "C378")
      (value "C")
      (footprint "SMD_0603_CAPC1608X95N")
      (fields
        (field (name "DB_PART_NUMBER") "CAP000028169")
        (field (name "DB_VALUE") "470nF")
        (field (name "DB_TOLERANCE") "5%")
        (field (name "DB_VOLTAGE") "16V")
        (field (name "DB_MANUFACTURER_PART") "KEMET    C0603C474J4RAC")
        (field (name "DB_APPROVED_BY") "ISHIDDEN=T")
      )
      (libsource (lib "Database_Libs1") (part "C"))
    )
    (comp (ref "C379")
      (value "C")
      (footprint "SMD_0603_CAPC1608X95N")
      (fields
        (field (name "DB_PART_NUMBER") "CAP000028169")
        (field (name "DB_VALUE") "470nF")
        (field (name "DB_TOLERANCE") "5%")
        (field (name "DB_VOLTAGE") "16V")
        (field (name "DB_MANUFACTURER_PART") "KEMET    C0603C474J4RAC")
        (field (name "DB_APPROVED_BY") "ISHIDDEN=T")
      )
      (libsource (lib "Database_Libs1") (part "C"))
    )
    (comp (ref "C380")
      (value "C")
      (footprint "SMD_0603_CAPC1608X95N")
      (fields
        (field (name "DB_PART_NUMBER") "CAP000028169")
        (field (name "DB_VALUE") "470nF")
        (field (name "DB_TOLERANCE") "5%")
        (field (name "DB_VOLTAGE") "16V")
        (field (name "DB_MANUFACTURER_PART") "KEMET    C0603C474J4RAC")
        (field (name "DB_APPROVED_BY") "ISHIDDEN=T")
      )
      (libsource (lib "Database_Libs1") (part "C"))
    )
    (comp (ref "C381")
      (value "C")
      (footprint "SMD_0603_CAPC1608X95N")
      (fields
        (field (name "DB_PART_NUMBER") "CAP000028169")
        (field (name "DB_VALUE") "470nF")
        (field (name "DB_TOLERANCE") "5%")
        (field (name "DB_VOLTAGE") "16V")
        (field (name "DB_MANUFACTURER_PART") "KEMET    C0603C474J4RAC")
        (field (name "DB_APPROVED_BY") "ISHIDDEN=T")
      )
      (libsource (lib "Database_Libs1") (part "C"))
    )
    (comp (ref "C382")
      (value "C")
      (footprint "SMD_0603_CAPC1608X95N")
      (fields
        (field (name "DB_PART_NUMBER") "CAP000028169")
        (field (name "DB_VALUE") "470nF")
        (field (name "DB_TOLERANCE") "5%")
        (field (name "DB_VOLTAGE") "16V")
        (field (name "DB_MANUFACTURER_PART") "KEMET    C0603C474J4RAC")
        (field (name "DB_APPROVED_BY") "ISHIDDEN=T")
      )
      (libsource (lib "Database_Libs1") (part "C"))
    )
    (comp (ref "C383")
      (value "C")
      (footprint "SMD_0603_CAPC1608X95N")
      (fields
        (field (name "DB_PART_NUMBER") "CAP000028169")
        (field (name "DB_VALUE") "470nF")
        (field (name "DB_TOLERANCE") "5%")
        (field (name "DB_VOLTAGE") "16V")
        (field (name "DB_MANUFACTURER_PART") "KEMET    C0603C474J4RAC")
        (field (name "DB_APPROVED_BY") "ISHIDDEN=T")
      )
      (libsource (lib "Database_Libs1") (part "C"))
    )
    (comp (ref "C_1")
      (value "C")
      (footprint "SMD_1210_CAPC3225X279N")
      (fields
        (field (name "DB_PART_NUMBER") "CAP000047355")
        (field (name "DB_VALUE") "220uF")
        (field (name "DB_TOLERANCE") "20%")
        (field (name "DB_VOLTAGE") "6.3V")
        (field (name "DB_MANUFACTURER_PART") "SAMSUNG    CL32A227MQVNNNE")
        (field (name "DB_APPROVED_BY") "VSN")
      )
      (libsource (lib "Database_Libs1") (part "C"))
    )
    (comp (ref "C_2")
      (value "C")
      (footprint "SMD_1210_CAPC3225X279N")
      (fields
        (field (name "DB_PART_NUMBER") "CAP000047355")
        (field (name "DB_VALUE") "220uF")
        (field (name "DB_TOLERANCE") "20%")
        (field (name "DB_VOLTAGE") "6.3V")
        (field (name "DB_MANUFACTURER_PART") "SAMSUNG    CL32A227MQVNNNE")
        (field (name "DB_APPROVED_BY") "VSN")
      )
      (libsource (lib "Database_Libs1") (part "C"))
    )
    (comp (ref "C_3")
      (value "C")
      (footprint "SMD_1210_CAPC3225X279N")
      (fields
        (field (name "DB_PART_NUMBER") "CAP000047355")
        (field (name "DB_VALUE") "220uF")
        (field (name "DB_TOLERANCE") "20%")
        (field (name "DB_VOLTAGE") "6.3V")
        (field (name "DB_MANUFACTURER_PART") "SAMSUNG    CL32A227MQVNNNE")
        (field (name "DB_APPROVED_BY") "VSN")
      )
      (libsource (lib "Database_Libs1") (part "C"))
    )
    (comp (ref "C_4")
      (value "C")
      (footprint "SMD_1210_CAPC3225X279N")
      (fields
        (field (name "DB_PART_NUMBER") "CAP000047355")
        (field (name "DB_VALUE") "220uF")
        (field (name "DB_TOLERANCE") "20%")
        (field (name "DB_VOLTAGE") "6.3V")
        (field (name "DB_MANUFACTURER_PART") "SAMSUNG    CL32A227MQVNNNE")
        (field (name "DB_APPROVED_BY") "VSN")
      )
      (libsource (lib "Database_Libs1") (part "C"))
    )
    (comp (ref "C_5")
      (value "C")
      (footprint "SMD_1210_CAPC3225X279N")
      (fields
        (field (name "DB_PART_NUMBER") "CAP000047355")
        (field (name "DB_VALUE") "220uF")
        (field (name "DB_TOLERANCE") "20%")
        (field (name "DB_VOLTAGE") "6.3V")
        (field (name "DB_MANUFACTURER_PART") "SAMSUNG    CL32A227MQVNNNE")
        (field (name "DB_APPROVED_BY") "VSN")
      )
      (libsource (lib "Database_Libs1") (part "C"))
    )
    (comp (ref "C_6")
      (value "C")
      (footprint "SMD_1210_CAPC3225X279N")
      (fields
        (field (name "DB_PART_NUMBER") "CAP000047355")
        (field (name "DB_VALUE") "220uF")
        (field (name "DB_TOLERANCE") "20%")
        (field (name "DB_VOLTAGE") "6.3V")
        (field (name "DB_MANUFACTURER_PART") "SAMSUNG    CL32A227MQVNNNE")
        (field (name "DB_APPROVED_BY") "VSN")
      )
      (libsource (lib "Database_Libs1") (part "C"))
    )
    (comp (ref "C_8")
      (value "C")
      (footprint "SMD_1210_CAPC3225X279N")
      (fields
        (field (name "DB_PART_NUMBER") "CAP000047355")
        (field (name "DB_VALUE") "220uF")
        (field (name "DB_TOLERANCE") "20%")
        (field (name "DB_VOLTAGE") "6.3V")
        (field (name "DB_MANUFACTURER_PART") "SAMSUNG    CL32A227MQVNNNE")
        (field (name "DB_APPROVED_BY") "VSN")
      )
      (libsource (lib "Database_Libs1") (part "C"))
    )
    (comp (ref "C_9")
      (value "C")
      (footprint "SMD_1210_CAPC3225X279N")
      (fields
        (field (name "DB_PART_NUMBER") "CAP000047355")
        (field (name "DB_VALUE") "220uF")
        (field (name "DB_TOLERANCE") "20%")
        (field (name "DB_VOLTAGE") "6.3V")
        (field (name "DB_MANUFACTURER_PART") "SAMSUNG    CL32A227MQVNNNE")
        (field (name "DB_APPROVED_BY") "VSN")
      )
      (libsource (lib "Database_Libs1") (part "C"))
    )
    (comp (ref "C_10")
      (value "C")
      (footprint "SMD_1210_CAPC3225X279N")
      (fields
        (field (name "DB_PART_NUMBER") "CAP000047355")
        (field (name "DB_VALUE") "220uF")
        (field (name "DB_TOLERANCE") "20%")
        (field (name "DB_VOLTAGE") "6.3V")
        (field (name "DB_MANUFACTURER_PART") "SAMSUNG    CL32A227MQVNNNE")
        (field (name "DB_APPROVED_BY") "VSN")
      )
      (libsource (lib "Database_Libs1") (part "C"))
    )
    (comp (ref "C_11")
      (value "C")
      (footprint "SMD_1210_CAPC3225X279N")
      (fields
        (field (name "DB_PART_NUMBER") "CAP000047355")
        (field (name "DB_VALUE") "220uF")
        (field (name "DB_TOLERANCE") "20%")
        (field (name "DB_VOLTAGE") "6.3V")
        (field (name "DB_MANUFACTURER_PART") "SAMSUNG    CL32A227MQVNNNE")
        (field (name "DB_APPROVED_BY") "VSN")
      )
      (libsource (lib "Database_Libs1") (part "C"))
    )
    (comp (ref "C_12")
      (value "C")
      (footprint "SMD_1210_CAPC3225X279N")
      (fields
        (field (name "DB_PART_NUMBER") "CAP000047355")
        (field (name "DB_VALUE") "220uF")
        (field (name "DB_TOLERANCE") "20%")
        (field (name "DB_VOLTAGE") "6.3V")
        (field (name "DB_MANUFACTURER_PART") "SAMSUNG    CL32A227MQVNNNE")
        (field (name "DB_APPROVED_BY") "VSN")
      )
      (libsource (lib "Database_Libs1") (part "C"))
    )
    (comp (ref "C_13")
      (value "C")
      (footprint "SMD_1210_CAPC3225X279N")
      (fields
        (field (name "DB_PART_NUMBER") "CAP000047355")
        (field (name "DB_VALUE") "220uF")
        (field (name "DB_TOLERANCE") "20%")
        (field (name "DB_VOLTAGE") "6.3V")
        (field (name "DB_MANUFACTURER_PART") "SAMSUNG    CL32A227MQVNNNE")
        (field (name "DB_APPROVED_BY") "VSN")
      )
      (libsource (lib "Database_Libs1") (part "C"))
    )
    (comp (ref "C_14")
      (value "C")
      (footprint "SMD_1210_CAPC3225X279N")
      (fields
        (field (name "DB_PART_NUMBER") "CAP000047355")
        (field (name "DB_VALUE") "220uF")
        (field (name "DB_TOLERANCE") "20%")
        (field (name "DB_VOLTAGE") "6.3V")
        (field (name "DB_MANUFACTURER_PART") "SAMSUNG    CL32A227MQVNNNE")
        (field (name "DB_APPROVED_BY") "VSN")
      )
      (libsource (lib "Database_Libs1") (part "C"))
    )
    (comp (ref "C_15")
      (value "C")
      (footprint "SMD_1210_CAPC3225X279N")
      (fields
        (field (name "DB_PART_NUMBER") "CAP000047355")
        (field (name "DB_VALUE") "220uF")
        (field (name "DB_TOLERANCE") "20%")
        (field (name "DB_VOLTAGE") "6.3V")
        (field (name "DB_MANUFACTURER_PART") "SAMSUNG    CL32A227MQVNNNE")
        (field (name "DB_APPROVED_BY") "VSN")
      )
      (libsource (lib "Database_Libs1") (part "C"))
    )
    (comp (ref "C_16")
      (value "C")
      (footprint "SMD_1210_CAPC3225X279N")
      (fields
        (field (name "DB_PART_NUMBER") "CAP000047355")
        (field (name "DB_VALUE") "220uF")
        (field (name "DB_TOLERANCE") "20%")
        (field (name "DB_VOLTAGE") "6.3V")
        (field (name "DB_MANUFACTURER_PART") "SAMSUNG    CL32A227MQVNNNE")
        (field (name "DB_APPROVED_BY") "VSN")
      )
      (libsource (lib "Database_Libs1") (part "C"))
    )
    (comp (ref "C_17")
      (value "C")
      (footprint "SMD_1210_CAPC3225X279N")
      (fields
        (field (name "DB_PART_NUMBER") "CAP000047355")
        (field (name "DB_VALUE") "220uF")
        (field (name "DB_TOLERANCE") "20%")
        (field (name "DB_VOLTAGE") "6.3V")
        (field (name "DB_MANUFACTURER_PART") "SAMSUNG    CL32A227MQVNNNE")
        (field (name "DB_APPROVED_BY") "VSN")
      )
      (libsource (lib "Database_Libs1") (part "C"))
    )
    (comp (ref "C_18")
      (value "C")
      (footprint "SMD_1210_CAPC3225X279N")
      (fields
        (field (name "DB_PART_NUMBER") "CAP000047355")
        (field (name "DB_VALUE") "220uF")
        (field (name "DB_TOLERANCE") "20%")
        (field (name "DB_VOLTAGE") "6.3V")
        (field (name "DB_MANUFACTURER_PART") "SAMSUNG    CL32A227MQVNNNE")
        (field (name "DB_APPROVED_BY") "VSN")
      )
      (libsource (lib "Database_Libs1") (part "C"))
    )
    (comp (ref "C_19")
      (value "C")
      (footprint "SMD_1210_CAPC3225X279N")
      (fields
        (field (name "DB_PART_NUMBER") "CAP000047355")
        (field (name "DB_VALUE") "220uF")
        (field (name "DB_TOLERANCE") "20%")
        (field (name "DB_VOLTAGE") "6.3V")
        (field (name "DB_MANUFACTURER_PART") "SAMSUNG    CL32A227MQVNNNE")
        (field (name "DB_APPROVED_BY") "VSN")
      )
      (libsource (lib "Database_Libs1") (part "C"))
    )
    (comp (ref "C_20")
      (value "C")
      (footprint "SMD_1210_CAPC3225X279N")
      (fields
        (field (name "DB_PART_NUMBER") "CAP000047355")
        (field (name "DB_VALUE") "220uF")
        (field (name "DB_TOLERANCE") "20%")
        (field (name "DB_VOLTAGE") "6.3V")
        (field (name "DB_MANUFACTURER_PART") "SAMSUNG    CL32A227MQVNNNE")
        (field (name "DB_APPROVED_BY") "VSN")
      )
      (libsource (lib "Database_Libs1") (part "C"))
    )
    (comp (ref "C_21")
      (value "C")
      (footprint "SMD_1210_CAPC3225X279N")
      (fields
        (field (name "DB_PART_NUMBER") "CAP000047355")
        (field (name "DB_VALUE") "220uF")
        (field (name "DB_TOLERANCE") "20%")
        (field (name "DB_VOLTAGE") "6.3V")
        (field (name "DB_MANUFACTURER_PART") "SAMSUNG    CL32A227MQVNNNE")
        (field (name "DB_APPROVED_BY") "VSN")
      )
      (libsource (lib "Database_Libs1") (part "C"))
    )
    (comp (ref "C_22")
      (value "C")
      (footprint "SMD_1210_CAPC3225X279N")
      (fields
        (field (name "DB_PART_NUMBER") "CAP000047355")
        (field (name "DB_VALUE") "220uF")
        (field (name "DB_TOLERANCE") "20%")
        (field (name "DB_VOLTAGE") "6.3V")
        (field (name "DB_MANUFACTURER_PART") "SAMSUNG    CL32A227MQVNNNE")
        (field (name "DB_APPROVED_BY") "VSN")
      )
      (libsource (lib "Database_Libs1") (part "C"))
    )
    (comp (ref "C_23")
      (value "C")
      (footprint "SMD_1210_CAPC3225X279N")
      (fields
        (field (name "DB_PART_NUMBER") "CAP000047355")
        (field (name "DB_VALUE") "220uF")
        (field (name "DB_TOLERANCE") "20%")
        (field (name "DB_VOLTAGE") "6.3V")
        (field (name "DB_MANUFACTURER_PART") "SAMSUNG    CL32A227MQVNNNE")
        (field (name "DB_APPROVED_BY") "VSN")
      )
      (libsource (lib "Database_Libs1") (part "C"))
    )
    (comp (ref "C_24")
      (value "C")
      (footprint "SMD_1210_CAPC3225X279N")
      (fields
        (field (name "DB_PART_NUMBER") "CAP000047355")
        (field (name "DB_VALUE") "220uF")
        (field (name "DB_TOLERANCE") "20%")
        (field (name "DB_VOLTAGE") "6.3V")
        (field (name "DB_MANUFACTURER_PART") "SAMSUNG    CL32A227MQVNNNE")
        (field (name "DB_APPROVED_BY") "VSN")
      )
      (libsource (lib "Database_Libs1") (part "C"))
    )
    (comp (ref "C_25")
      (value "C")
      (footprint "SMD_1210_CAPC3225X279N")
      (fields
        (field (name "DB_PART_NUMBER") "CAP000047355")
        (field (name "DB_VALUE") "220uF")
        (field (name "DB_TOLERANCE") "20%")
        (field (name "DB_VOLTAGE") "6.3V")
        (field (name "DB_MANUFACTURER_PART") "SAMSUNG    CL32A227MQVNNNE")
        (field (name "DB_APPROVED_BY") "VSN")
      )
      (libsource (lib "Database_Libs1") (part "C"))
    )
    (comp (ref "C_26")
      (value "C")
      (footprint "SMD_1210_CAPC3225X279N")
      (fields
        (field (name "DB_PART_NUMBER") "CAP000047355")
        (field (name "DB_VALUE") "220uF")
        (field (name "DB_TOLERANCE") "20%")
        (field (name "DB_VOLTAGE") "6.3V")
        (field (name "DB_MANUFACTURER_PART") "SAMSUNG    CL32A227MQVNNNE")
        (field (name "DB_APPROVED_BY") "VSN")
      )
      (libsource (lib "Database_Libs1") (part "C"))
    )
    (comp (ref "C_27")
      (value "C")
      (footprint "SMD_1210_CAPC3225X279N")
      (fields
        (field (name "DB_PART_NUMBER") "CAP000047355")
        (field (name "DB_VALUE") "220uF")
        (field (name "DB_TOLERANCE") "20%")
        (field (name "DB_VOLTAGE") "6.3V")
        (field (name "DB_MANUFACTURER_PART") "SAMSUNG    CL32A227MQVNNNE")
        (field (name "DB_APPROVED_BY") "VSN")
      )
      (libsource (lib "Database_Libs1") (part "C"))
    )
    (comp (ref "C_28")
      (value "C")
      (footprint "SMD_1210_CAPC3225X279N")
      (fields
        (field (name "DB_PART_NUMBER") "CAP000047355")
        (field (name "DB_VALUE") "220uF")
        (field (name "DB_TOLERANCE") "20%")
        (field (name "DB_VOLTAGE") "6.3V")
        (field (name "DB_MANUFACTURER_PART") "SAMSUNG    CL32A227MQVNNNE")
        (field (name "DB_APPROVED_BY") "VSN")
      )
      (libsource (lib "Database_Libs1") (part "C"))
    )
    (comp (ref "C_29")
      (value "C")
      (footprint "SMD_1210_CAPC3225X279N")
      (fields
        (field (name "DB_PART_NUMBER") "CAP000047355")
        (field (name "DB_VALUE") "220uF")
        (field (name "DB_TOLERANCE") "20%")
        (field (name "DB_VOLTAGE") "6.3V")
        (field (name "DB_MANUFACTURER_PART") "SAMSUNG    CL32A227MQVNNNE")
        (field (name "DB_APPROVED_BY") "VSN")
      )
      (libsource (lib "Database_Libs1") (part "C"))
    )
    (comp (ref "C_30")
      (value "C")
      (footprint "SMD_1210_CAPC3225X279N")
      (fields
        (field (name "DB_PART_NUMBER") "CAP000047355")
        (field (name "DB_VALUE") "220uF")
        (field (name "DB_TOLERANCE") "20%")
        (field (name "DB_VOLTAGE") "6.3V")
        (field (name "DB_MANUFACTURER_PART") "SAMSUNG    CL32A227MQVNNNE")
        (field (name "DB_APPROVED_BY") "VSN")
      )
      (libsource (lib "Database_Libs1") (part "C"))
    )
    (comp (ref "C_33")
      (value "C")
      (footprint "SMD_1210_CAPC3225X279N")
      (fields
        (field (name "DB_PART_NUMBER") "CAP000047355")
        (field (name "DB_VALUE") "220uF")
        (field (name "DB_TOLERANCE") "20%")
        (field (name "DB_VOLTAGE") "6.3V")
        (field (name "DB_MANUFACTURER_PART") "SAMSUNG    CL32A227MQVNNNE")
        (field (name "DB_APPROVED_BY") "VSN")
      )
      (libsource (lib "Database_Libs1") (part "C"))
    )
    (comp (ref "C_34")
      (value "C")
      (footprint "SMD_1210_CAPC3225X279N")
      (fields
        (field (name "DB_PART_NUMBER") "CAP000047355")
        (field (name "DB_VALUE") "220uF")
        (field (name "DB_TOLERANCE") "20%")
        (field (name "DB_VOLTAGE") "6.3V")
        (field (name "DB_MANUFACTURER_PART") "SAMSUNG    CL32A227MQVNNNE")
        (field (name "DB_APPROVED_BY") "VSN")
      )
      (libsource (lib "Database_Libs1") (part "C"))
    )
    (comp (ref "C_35")
      (value "C")
      (footprint "SMD_1210_CAPC3225X279N")
      (fields
        (field (name "DB_PART_NUMBER") "CAP000047355")
        (field (name "DB_VALUE") "220uF")
        (field (name "DB_TOLERANCE") "20%")
        (field (name "DB_VOLTAGE") "6.3V")
        (field (name "DB_MANUFACTURER_PART") "SAMSUNG    CL32A227MQVNNNE")
        (field (name "DB_APPROVED_BY") "VSN")
      )
      (libsource (lib "Database_Libs1") (part "C"))
    )
    (comp (ref "C_36")
      (value "C")
      (footprint "SMD_1210_CAPC3225X279N")
      (fields
        (field (name "DB_PART_NUMBER") "CAP000047355")
        (field (name "DB_VALUE") "220uF")
        (field (name "DB_TOLERANCE") "20%")
        (field (name "DB_VOLTAGE") "6.3V")
        (field (name "DB_MANUFACTURER_PART") "SAMSUNG    CL32A227MQVNNNE")
        (field (name "DB_APPROVED_BY") "VSN")
      )
      (libsource (lib "Database_Libs1") (part "C"))
    )
    (comp (ref "C_37")
      (value "C")
      (footprint "SMD_1210_CAPC3225X279N")
      (fields
        (field (name "DB_PART_NUMBER") "CAP000047355")
        (field (name "DB_VALUE") "220uF")
        (field (name "DB_TOLERANCE") "20%")
        (field (name "DB_VOLTAGE") "6.3V")
        (field (name "DB_MANUFACTURER_PART") "SAMSUNG    CL32A227MQVNNNE")
        (field (name "DB_APPROVED_BY") "VSN")
      )
      (libsource (lib "Database_Libs1") (part "C"))
    )
    (comp (ref "C_38")
      (value "C")
      (footprint "SMD_1210_CAPC3225X279N")
      (fields
        (field (name "DB_PART_NUMBER") "CAP000047355")
        (field (name "DB_VALUE") "220uF")
        (field (name "DB_TOLERANCE") "20%")
        (field (name "DB_VOLTAGE") "6.3V")
        (field (name "DB_MANUFACTURER_PART") "SAMSUNG    CL32A227MQVNNNE")
        (field (name "DB_APPROVED_BY") "VSN")
      )
      (libsource (lib "Database_Libs1") (part "C"))
    )
    (comp (ref "C_39")
      (value "C")
      (footprint "SMD_1210_CAPC3225X279N")
      (fields
        (field (name "DB_PART_NUMBER") "CAP000047355")
        (field (name "DB_VALUE") "220uF")
        (field (name "DB_TOLERANCE") "20%")
        (field (name "DB_VOLTAGE") "6.3V")
        (field (name "DB_MANUFACTURER_PART") "SAMSUNG    CL32A227MQVNNNE")
        (field (name "DB_APPROVED_BY") "VSN")
      )
      (libsource (lib "Database_Libs1") (part "C"))
    )
    (comp (ref "C_40")
      (value "C")
      (footprint "SMD_1210_CAPC3225X279N")
      (fields
        (field (name "DB_PART_NUMBER") "CAP000047355")
        (field (name "DB_VALUE") "220uF")
        (field (name "DB_TOLERANCE") "20%")
        (field (name "DB_VOLTAGE") "6.3V")
        (field (name "DB_MANUFACTURER_PART") "SAMSUNG    CL32A227MQVNNNE")
        (field (name "DB_APPROVED_BY") "VSN")
      )
      (libsource (lib "Database_Libs1") (part "C"))
    )
    (comp (ref "C_41")
      (value "C")
      (footprint "SMD_1210_CAPC3225X279N")
      (fields
        (field (name "DB_PART_NUMBER") "CAP000047355")
        (field (name "DB_VALUE") "220uF")
        (field (name "DB_TOLERANCE") "20%")
        (field (name "DB_VOLTAGE") "6.3V")
        (field (name "DB_MANUFACTURER_PART") "SAMSUNG    CL32A227MQVNNNE")
        (field (name "DB_APPROVED_BY") "VSN")
      )
      (libsource (lib "Database_Libs1") (part "C"))
    )
    (comp (ref "C_42")
      (value "C")
      (footprint "SMD_1210_CAPC3225X279N")
      (fields
        (field (name "DB_PART_NUMBER") "CAP000047355")
        (field (name "DB_VALUE") "220uF")
        (field (name "DB_TOLERANCE") "20%")
        (field (name "DB_VOLTAGE") "6.3V")
        (field (name "DB_MANUFACTURER_PART") "SAMSUNG    CL32A227MQVNNNE")
        (field (name "DB_APPROVED_BY") "VSN")
      )
      (libsource (lib "Database_Libs1") (part "C"))
    )
    (comp (ref "C_43")
      (value "C")
      (footprint "SMD_1210_CAPC3225X279N")
      (fields
        (field (name "DB_PART_NUMBER") "CAP000047355")
        (field (name "DB_VALUE") "220uF")
        (field (name "DB_TOLERANCE") "20%")
        (field (name "DB_VOLTAGE") "6.3V")
        (field (name "DB_MANUFACTURER_PART") "SAMSUNG    CL32A227MQVNNNE")
        (field (name "DB_APPROVED_BY") "VSN")
      )
      (libsource (lib "Database_Libs1") (part "C"))
    )
    (comp (ref "C_44")
      (value "C")
      (footprint "SMD_1210_CAPC3225X279N")
      (fields
        (field (name "DB_PART_NUMBER") "CAP000047355")
        (field (name "DB_VALUE") "220uF")
        (field (name "DB_TOLERANCE") "20%")
        (field (name "DB_VOLTAGE") "6.3V")
        (field (name "DB_MANUFACTURER_PART") "SAMSUNG    CL32A227MQVNNNE")
        (field (name "DB_APPROVED_BY") "VSN")
      )
      (libsource (lib "Database_Libs1") (part "C"))
    )
    (comp (ref "C_45")
      (value "C")
      (footprint "SMD_1210_CAPC3225X279N")
      (fields
        (field (name "DB_PART_NUMBER") "CAP000047355")
        (field (name "DB_VALUE") "220uF")
        (field (name "DB_TOLERANCE") "20%")
        (field (name "DB_VOLTAGE") "6.3V")
        (field (name "DB_MANUFACTURER_PART") "SAMSUNG    CL32A227MQVNNNE")
        (field (name "DB_APPROVED_BY") "VSN")
      )
      (libsource (lib "Database_Libs1") (part "C"))
    )
    (comp (ref "C_46")
      (value "C")
      (footprint "SMD_1210_CAPC3225X279N")
      (fields
        (field (name "DB_PART_NUMBER") "CAP000047355")
        (field (name "DB_VALUE") "220uF")
        (field (name "DB_TOLERANCE") "20%")
        (field (name "DB_VOLTAGE") "6.3V")
        (field (name "DB_MANUFACTURER_PART") "SAMSUNG    CL32A227MQVNNNE")
        (field (name "DB_APPROVED_BY") "VSN")
      )
      (libsource (lib "Database_Libs1") (part "C"))
    )
    (comp (ref "C_47")
      (value "C")
      (footprint "SMD_1210_CAPC3225X279N")
      (fields
        (field (name "DB_PART_NUMBER") "CAP000047355")
        (field (name "DB_VALUE") "220uF")
        (field (name "DB_TOLERANCE") "20%")
        (field (name "DB_VOLTAGE") "6.3V")
        (field (name "DB_MANUFACTURER_PART") "SAMSUNG    CL32A227MQVNNNE")
        (field (name "DB_APPROVED_BY") "VSN")
      )
      (libsource (lib "Database_Libs1") (part "C"))
    )
    (comp (ref "C_48")
      (value "C")
      (footprint "SMD_1210_CAPC3225X279N")
      (fields
        (field (name "DB_PART_NUMBER") "CAP000047355")
        (field (name "DB_VALUE") "220uF")
        (field (name "DB_TOLERANCE") "20%")
        (field (name "DB_VOLTAGE") "6.3V")
        (field (name "DB_MANUFACTURER_PART") "SAMSUNG    CL32A227MQVNNNE")
        (field (name "DB_APPROVED_BY") "VSN")
      )
      (libsource (lib "Database_Libs1") (part "C"))
    )
    (comp (ref "C_49")
      (value "C")
      (footprint "SMD_1210_CAPC3225X279N")
      (fields
        (field (name "DB_PART_NUMBER") "CAP000047355")
        (field (name "DB_VALUE") "220uF")
        (field (name "DB_TOLERANCE") "20%")
        (field (name "DB_VOLTAGE") "6.3V")
        (field (name "DB_MANUFACTURER_PART") "SAMSUNG    CL32A227MQVNNNE")
        (field (name "DB_APPROVED_BY") "VSN")
      )
      (libsource (lib "Database_Libs1") (part "C"))
    )
    (comp (ref "C_50")
      (value "C")
      (footprint "SMD_1210_CAPC3225X279N")
      (fields
        (field (name "DB_PART_NUMBER") "CAP000047355")
        (field (name "DB_VALUE") "220uF")
        (field (name "DB_TOLERANCE") "20%")
        (field (name "DB_VOLTAGE") "6.3V")
        (field (name "DB_MANUFACTURER_PART") "SAMSUNG    CL32A227MQVNNNE")
        (field (name "DB_APPROVED_BY") "VSN")
      )
      (libsource (lib "Database_Libs1") (part "C"))
    )
    (comp (ref "C_51")
      (value "C")
      (footprint "SMD_1210_CAPC3225X279N")
      (fields
        (field (name "DB_PART_NUMBER") "CAP000047355")
        (field (name "DB_VALUE") "220uF")
        (field (name "DB_TOLERANCE") "20%")
        (field (name "DB_VOLTAGE") "6.3V")
        (field (name "DB_MANUFACTURER_PART") "SAMSUNG    CL32A227MQVNNNE")
        (field (name "DB_APPROVED_BY") "VSN")
      )
      (libsource (lib "Database_Libs1") (part "C"))
    )
    (comp (ref "C_52")
      (value "C")
      (footprint "SMD_1210_CAPC3225X279N")
      (fields
        (field (name "DB_PART_NUMBER") "CAP000047355")
        (field (name "DB_VALUE") "220uF")
        (field (name "DB_TOLERANCE") "20%")
        (field (name "DB_VOLTAGE") "6.3V")
        (field (name "DB_MANUFACTURER_PART") "SAMSUNG    CL32A227MQVNNNE")
        (field (name "DB_APPROVED_BY") "VSN")
      )
      (libsource (lib "Database_Libs1") (part "C"))
    )
    (comp (ref "C_53")
      (value "C")
      (footprint "SMD_1210_CAPC3225X279N")
      (fields
        (field (name "DB_PART_NUMBER") "CAP000047355")
        (field (name "DB_VALUE") "220uF")
        (field (name "DB_TOLERANCE") "20%")
        (field (name "DB_VOLTAGE") "6.3V")
        (field (name "DB_MANUFACTURER_PART") "SAMSUNG    CL32A227MQVNNNE")
        (field (name "DB_APPROVED_BY") "VSN")
      )
      (libsource (lib "Database_Libs1") (part "C"))
    )
    (comp (ref "C_54")
      (value "C")
      (footprint "SMD_1210_CAPC3225X279N")
      (fields
        (field (name "DB_PART_NUMBER") "CAP000047355")
        (field (name "DB_VALUE") "220uF")
        (field (name "DB_TOLERANCE") "20%")
        (field (name "DB_VOLTAGE") "6.3V")
        (field (name "DB_MANUFACTURER_PART") "SAMSUNG    CL32A227MQVNNNE")
        (field (name "DB_APPROVED_BY") "VSN")
      )
      (libsource (lib "Database_Libs1") (part "C"))
    )
    (comp (ref "C_55")
      (value "C")
      (footprint "SMD_1210_CAPC3225X279N")
      (fields
        (field (name "DB_PART_NUMBER") "CAP000047355")
        (field (name "DB_VALUE") "220uF")
        (field (name "DB_TOLERANCE") "20%")
        (field (name "DB_VOLTAGE") "6.3V")
        (field (name "DB_MANUFACTURER_PART") "SAMSUNG    CL32A227MQVNNNE")
        (field (name "DB_APPROVED_BY") "VSN")
      )
      (libsource (lib "Database_Libs1") (part "C"))
    )
    (comp (ref "C_56")
      (value "C")
      (footprint "SMD_1210_CAPC3225X279N")
      (fields
        (field (name "DB_PART_NUMBER") "CAP000047355")
        (field (name "DB_VALUE") "220uF")
        (field (name "DB_TOLERANCE") "20%")
        (field (name "DB_VOLTAGE") "6.3V")
        (field (name "DB_MANUFACTURER_PART") "SAMSUNG    CL32A227MQVNNNE")
        (field (name "DB_APPROVED_BY") "VSN")
      )
      (libsource (lib "Database_Libs1") (part "C"))
    )
    (comp (ref "C_57")
      (value "C")
      (footprint "SMD_1210_CAPC3225X279N")
      (fields
        (field (name "DB_PART_NUMBER") "CAP000047355")
        (field (name "DB_VALUE") "220uF")
        (field (name "DB_TOLERANCE") "20%")
        (field (name "DB_VOLTAGE") "6.3V")
        (field (name "DB_MANUFACTURER_PART") "SAMSUNG    CL32A227MQVNNNE")
        (field (name "DB_APPROVED_BY") "VSN")
      )
      (libsource (lib "Database_Libs1") (part "C"))
    )
    (comp (ref "C_58")
      (value "C")
      (footprint "SMD_1210_CAPC3225X279N")
      (fields
        (field (name "DB_PART_NUMBER") "CAP000047355")
        (field (name "DB_VALUE") "220uF")
        (field (name "DB_TOLERANCE") "20%")
        (field (name "DB_VOLTAGE") "6.3V")
        (field (name "DB_MANUFACTURER_PART") "SAMSUNG    CL32A227MQVNNNE")
        (field (name "DB_APPROVED_BY") "VSN")
      )
      (libsource (lib "Database_Libs1") (part "C"))
    )
    (comp (ref "C_59")
      (value "C")
      (footprint "SMD_1210_CAPC3225X279N")
      (fields
        (field (name "DB_PART_NUMBER") "CAP000047355")
        (field (name "DB_VALUE") "220uF")
        (field (name "DB_TOLERANCE") "20%")
        (field (name "DB_VOLTAGE") "6.3V")
        (field (name "DB_MANUFACTURER_PART") "SAMSUNG    CL32A227MQVNNNE")
        (field (name "DB_APPROVED_BY") "VSN")
      )
      (libsource (lib "Database_Libs1") (part "C"))
    )
    (comp (ref "C_60")
      (value "C")
      (footprint "SMD_1210_CAPC3225X279N")
      (fields
        (field (name "DB_PART_NUMBER") "CAP000047355")
        (field (name "DB_VALUE") "220uF")
        (field (name "DB_TOLERANCE") "20%")
        (field (name "DB_VOLTAGE") "6.3V")
        (field (name "DB_MANUFACTURER_PART") "SAMSUNG    CL32A227MQVNNNE")
        (field (name "DB_APPROVED_BY") "VSN")
      )
      (libsource (lib "Database_Libs1") (part "C"))
    )
    (comp (ref "C_61")
      (value "C")
      (footprint "SMD_1210_CAPC3225X279N")
      (fields
        (field (name "DB_PART_NUMBER") "CAP000047355")
        (field (name "DB_VALUE") "220uF")
        (field (name "DB_TOLERANCE") "20%")
        (field (name "DB_VOLTAGE") "6.3V")
        (field (name "DB_MANUFACTURER_PART") "SAMSUNG    CL32A227MQVNNNE")
        (field (name "DB_APPROVED_BY") "VSN")
      )
      (libsource (lib "Database_Libs1") (part "C"))
    )
    (comp (ref "C_62")
      (value "C")
      (footprint "SMD_1210_CAPC3225X279N")
      (fields
        (field (name "DB_PART_NUMBER") "CAP000047355")
        (field (name "DB_VALUE") "220uF")
        (field (name "DB_TOLERANCE") "20%")
        (field (name "DB_VOLTAGE") "6.3V")
        (field (name "DB_MANUFACTURER_PART") "SAMSUNG    CL32A227MQVNNNE")
        (field (name "DB_APPROVED_BY") "VSN")
      )
      (libsource (lib "Database_Libs1") (part "C"))
    )
    (comp (ref "C_63")
      (value "C")
      (footprint "SMD_1210_CAPC3225X279N")
      (fields
        (field (name "DB_PART_NUMBER") "CAP000047355")
        (field (name "DB_VALUE") "220uF")
        (field (name "DB_TOLERANCE") "20%")
        (field (name "DB_VOLTAGE") "6.3V")
        (field (name "DB_MANUFACTURER_PART") "SAMSUNG    CL32A227MQVNNNE")
        (field (name "DB_APPROVED_BY") "VSN")
      )
      (libsource (lib "Database_Libs1") (part "C"))
    )
    (comp (ref "C_64")
      (value "C")
      (footprint "SMD_1210_CAPC3225X279N")
      (fields
        (field (name "DB_PART_NUMBER") "CAP000047355")
        (field (name "DB_VALUE") "220uF")
        (field (name "DB_TOLERANCE") "20%")
        (field (name "DB_VOLTAGE") "6.3V")
        (field (name "DB_MANUFACTURER_PART") "SAMSUNG    CL32A227MQVNNNE")
        (field (name "DB_APPROVED_BY") "VSN")
      )
      (libsource (lib "Database_Libs1") (part "C"))
    )
    (comp (ref "C_65")
      (value "C")
      (footprint "SMD_1210_CAPC3225X279N")
      (fields
        (field (name "DB_PART_NUMBER") "CAP000047355")
        (field (name "DB_VALUE") "220uF")
        (field (name "DB_TOLERANCE") "20%")
        (field (name "DB_VOLTAGE") "6.3V")
        (field (name "DB_MANUFACTURER_PART") "SAMSUNG    CL32A227MQVNNNE")
        (field (name "DB_APPROVED_BY") "VSN")
      )
      (libsource (lib "Database_Libs1") (part "C"))
    )
    (comp (ref "C_66")
      (value "C")
      (footprint "SMD_1210_CAPC3225X279N")
      (fields
        (field (name "DB_PART_NUMBER") "CAP000047355")
        (field (name "DB_VALUE") "220uF")
        (field (name "DB_TOLERANCE") "20%")
        (field (name "DB_VOLTAGE") "6.3V")
        (field (name "DB_MANUFACTURER_PART") "SAMSUNG    CL32A227MQVNNNE")
        (field (name "DB_APPROVED_BY") "VSN")
      )
      (libsource (lib "Database_Libs1") (part "C"))
    )
    (comp (ref "C_67")
      (value "C")
      (footprint "SMD_1210_CAPC3225X279N")
      (fields
        (field (name "DB_PART_NUMBER") "CAP000047355")
        (field (name "DB_VALUE") "220uF")
        (field (name "DB_TOLERANCE") "20%")
        (field (name "DB_VOLTAGE") "6.3V")
        (field (name "DB_MANUFACTURER_PART") "SAMSUNG    CL32A227MQVNNNE")
        (field (name "DB_APPROVED_BY") "VSN")
      )
      (libsource (lib "Database_Libs1") (part "C"))
    )
    (comp (ref "C_68")
      (value "C")
      (footprint "SMD_1210_CAPC3225X279N")
      (fields
        (field (name "DB_PART_NUMBER") "CAP000047355")
        (field (name "DB_VALUE") "220uF")
        (field (name "DB_TOLERANCE") "20%")
        (field (name "DB_VOLTAGE") "6.3V")
        (field (name "DB_MANUFACTURER_PART") "SAMSUNG    CL32A227MQVNNNE")
        (field (name "DB_APPROVED_BY") "VSN")
      )
      (libsource (lib "Database_Libs1") (part "C"))
    )
    (comp (ref "C_69")
      (value "C")
      (footprint "SMD_1210_CAPC3225X279N")
      (fields
        (field (name "DB_PART_NUMBER") "CAP000047355")
        (field (name "DB_VALUE") "220uF")
        (field (name "DB_TOLERANCE") "20%")
        (field (name "DB_VOLTAGE") "6.3V")
        (field (name "DB_MANUFACTURER_PART") "SAMSUNG    CL32A227MQVNNNE")
        (field (name "DB_APPROVED_BY") "VSN")
      )
      (libsource (lib "Database_Libs1") (part "C"))
    )
    (comp (ref "C_70")
      (value "C")
      (footprint "SMD_1210_CAPC3225X279N")
      (fields
        (field (name "DB_PART_NUMBER") "CAP000047355")
        (field (name "DB_VALUE") "220uF")
        (field (name "DB_TOLERANCE") "20%")
        (field (name "DB_VOLTAGE") "6.3V")
        (field (name "DB_MANUFACTURER_PART") "SAMSUNG    CL32A227MQVNNNE")
        (field (name "DB_APPROVED_BY") "VSN")
      )
      (libsource (lib "Database_Libs1") (part "C"))
    )
    (comp (ref "C_71")
      (value "C")
      (footprint "SMD_1210_CAPC3225X279N")
      (fields
        (field (name "DB_PART_NUMBER") "CAP000047355")
        (field (name "DB_VALUE") "220uF")
        (field (name "DB_TOLERANCE") "20%")
        (field (name "DB_VOLTAGE") "6.3V")
        (field (name "DB_MANUFACTURER_PART") "SAMSUNG    CL32A227MQVNNNE")
        (field (name "DB_APPROVED_BY") "VSN")
      )
      (libsource (lib "Database_Libs1") (part "C"))
    )
    (comp (ref "C_72")
      (value "C")
      (footprint "SMD_1210_CAPC3225X279N")
      (fields
        (field (name "DB_PART_NUMBER") "CAP000047355")
        (field (name "DB_VALUE") "220uF")
        (field (name "DB_TOLERANCE") "20%")
        (field (name "DB_VOLTAGE") "6.3V")
        (field (name "DB_MANUFACTURER_PART") "SAMSUNG    CL32A227MQVNNNE")
        (field (name "DB_APPROVED_BY") "VSN")
      )
      (libsource (lib "Database_Libs1") (part "C"))
    )
    (comp (ref "D1")
      (value "D_STKY_DUAL_A1A2CC3")
      (footprint "SMD_SOT23_SOT95P240X120-3N")
      (fields
        (field (name "DB_PART_NUMBER") "DDE000000490")
        (field (name "DB_VALUE") "BAT54C")
        (field (name "DB_MANUFACTURER_PART") "Diodes        BAT54C")
        (field (name "DB_APPROVED_BY") "ISHIDDEN=T")
      )
      (libsource (lib "Database_Libs1") (part "D_STKY_DUAL_A1A2CC3"))
    )
    (comp (ref "D2")
      (value "D_STKY_DUAL_A1A2CC3")
      (footprint "SMD_SOT23_SOT95P240X120-3N")
      (fields
        (field (name "DB_PART_NUMBER") "DDE000000490")
        (field (name "DB_VALUE") "BAT54C")
        (field (name "DB_MANUFACTURER_PART") "Diodes        BAT54C")
        (field (name "DB_APPROVED_BY") "ISHIDDEN=T")
      )
      (libsource (lib "Database_Libs1") (part "D_STKY_DUAL_A1A2CC3"))
    )
    (comp (ref "D3")
      (value "D_STKY_DUAL_A1A2CC3")
      (footprint "SMD_SOT23_SOT95P240X120-3N")
      (fields
        (field (name "DB_PART_NUMBER") "DDE000000490")
        (field (name "DB_VALUE") "BAT54C")
        (field (name "DB_MANUFACTURER_PART") "Diodes        BAT54C")
        (field (name "DB_APPROVED_BY") "ISHIDDEN=T")
      )
      (libsource (lib "Database_Libs1") (part "D_STKY_DUAL_A1A2CC3"))
    )
    (comp (ref "D4")
      (value "Red SML210VT ROHM")
      (footprint "SMD_0805_LED2012X100N")
      (libsource (lib "EPIQ_DND_CIS_Library") (part "LED_2"))
    )
    (comp (ref "D5")
      (value "Green 	SML210MT ROHM")
      (footprint "SMD_0805_LED2012X100N")
      (libsource (lib "EPIQ_DND_CIS_Library") (part "LED_2"))
    )
    (comp (ref "D6")
      (value "Yellow SML210YT ROHM")
      (footprint "SMD_0805_LED2012X100N")
      (libsource (lib "EPIQ_DND_CIS_Library") (part "LED_2"))
    )
    (comp (ref "D7")
      (value "Orange 	SML210DT ROHM")
      (footprint "SMD_0805_LED2012X100N")
      (libsource (lib "EPIQ_DND_CIS_Library") (part "LED_2"))
    )
    (comp (ref "D8")
      (value "D_STKY")
      (footprint "SMD_DO214AC_SMA")
      (fields
        (field (name "DB_PART_NUMBER") "DDE000000580")
        (field (name "DB_VALUE") "B140")
        (field (name "DB_MANUFACTURER_PART") "Diodes        B140")
        (field (name "DB_APPROVED_BY") "ISHIDDEN=T")
      )
      (libsource (lib "Database_Libs1") (part "D_STKY"))
    )
    (comp (ref "D9")
      (value "D_TVS_QUAD_C1A2C3C4A5C6")
      (footprint "SMD_SOT457_SOT95P275X110-6N")
      (fields
        (field (name "DB_PART_NUMBER") "DDE000002846")
        (field (name "DB_VALUE") "SMS05T1G")
        (field (name "DB_MANUFACTURER_PART") "ON SEMICONDUCTOR        SMS05T1G")
        (field (name "DB_APPROVED_BY") "VSN")
      )
      (libsource (lib "Database_Libs1") (part "D_TVS_QUAD_C1A2C3C4A5C6"))
    )
    (comp (ref "D10")
      (value "D_STKY")
      (footprint "SMD_DO214AC_SMA")
      (fields
        (field (name "DB_PART_NUMBER") "DDE000000580")
        (field (name "DB_VALUE") "B140")
        (field (name "DB_MANUFACTURER_PART") "Diodes        B140")
        (field (name "DB_APPROVED_BY") "ISHIDDEN=T")
      )
      (libsource (lib "Database_Libs1") (part "D_STKY"))
    )
    (comp (ref "D11")
      (value "D_STKY")
      (footprint "SMD_DO214AC_SMA")
      (fields
        (field (name "DB_PART_NUMBER") "DDE000000580")
        (field (name "DB_VALUE") "B140")
        (field (name "DB_MANUFACTURER_PART") "Diodes        B140")
        (field (name "DB_APPROVED_BY") "ISHIDDEN=T")
      )
      (libsource (lib "Database_Libs1") (part "D_STKY"))
    )
    (comp (ref "D12")
      (value "D_TVS_UNI")
      (footprint "SMD_DO214AC_SMC")
      (fields
        (field (name "DB_PART_NUMBER") "DDE000001725")
        (field (name "DB_VALUE") "SMCJ12A")
        (field (name "DB_MANUFACTURER_PART") "Diodes        SMCJ12A")
        (field (name "DB_APPROVED_BY") "ISHIDDEN=T")
      )
      (libsource (lib "Database_Libs1") (part "D_TVS_UNI"))
    )
    (comp (ref "FB1")
      (value "L_FERRITE_BEAD")
      (footprint "SMD_0805_INDC2012X105N")
      (fields
        (field (name "DB_PART_NUMBER") "IND000000029")
        (field (name "DB_VALUE") "220 Ohms")
        (field (name "DB_CURRENT") "2A")
        (field (name "DB_MANUFACTURER_PART") "MURATA       BLM21PG221SN1D")
        (field (name "DB_APPROVED_BY") "VSN")
      )
      (libsource (lib "Database_Libs1") (part "L_FERRITE_BEAD"))
    )
    (comp (ref "FID1")
      (value "FIDUCIAL")
      (footprint "FID100X200")
      (fields
        (field (name "DB_PART_NUMBER") "FID000000001")
        (field (name "DB_MANUFACTURER_PART") "ISHIDDEN=T")
        (field (name "DB_APPROVED_BY") "ISHIDDEN=T")
      )
      (libsource (lib "Database_Libs1") (part "FIDUCIAL"))
    )
    (comp (ref "FID2")
      (value "FIDUCIAL")
      (footprint "FID100X200")
      (fields
        (field (name "DB_PART_NUMBER") "FID000000001")
        (field (name "DB_MANUFACTURER_PART") "ISHIDDEN=T")
        (field (name "DB_APPROVED_BY") "ISHIDDEN=T")
      )
      (libsource (lib "Database_Libs1") (part "FIDUCIAL"))
    )
    (comp (ref "J1")
      (value "CON_5PINS")
      (footprint "PTH_HDRV05W64P254_1X05")
      (fields
        (field (name "DB_PART_NUMBER") "CON000000006")
        (field (name "DB_VALUE") "CONN PCB 5P M S")
        (field (name "DB_MANUFACTURER_PART") "W+P        143-12-005-00")
        (field (name "DB_APPROVED_BY") "VSN")
      )
      (libsource (lib "Database_Libs1") (part "CON_5PINS"))
    )
    (comp (ref "J2")
      (value "CON_USB_MINI_1")
      (footprint "SMD_CON-CVILUX-CU04-SCM15B0")
      (fields
        (field (name "DB_PART_NUMBER") "CON000000048")
        (field (name "DB_VALUE") "USB MINI")
        (field (name "DB_MANUFACTURER_PART") "CVILUX       CU04-SCM15B0-R0-LF")
        (field (name "DB_APPROVED_BY") "VSN")
      )
      (libsource (lib "Database_Libs1") (part "CON_USB_MINI_1"))
    )
    (comp (ref "J3")
      (value "CON_3PINS")
      (footprint "PTH_CON_HD-351-3P")
      (fields
        (field (name "DB_PART_NUMBER") "CON000000272")
        (field (name "DB_VALUE") "HD-351-3P")
        (field (name "DB_MANUFACTURER_PART") "HOW DER      HD-351-3P")
        (field (name "DB_APPROVED_BY") "VSN")
      )
      (libsource (lib "Database_Libs1") (part "CON_3PINS"))
    )
    (comp (ref "J4")
      (value "CON_2ROWS_6PINS_1")
      (footprint "PTH_CON_WR-MRC4-6P")
      (fields
        (field (name "DB_PART_NUMBER") "CON000000271")
        (field (name "DB_VALUE") "WR-MPC4")
        (field (name "DB_MANUFACTURER_PART") "WE         649 006 295 22")
        (field (name "DB_APPROVED_BY") "VSN")
      )
      (libsource (lib "Database_Libs1") (part "CON_2ROWS_6PINS_1"))
    )
    (comp (ref "J5")
      (value "CON_1PIN")
      (footprint "PTH_MTG400_700")
      (fields
        (field (name "DB_PART_NUMBER") "MTH000000030")
        (field (name "DB_VALUE") "PTH_MTG400_700")
        (field (name "DB_APPROVED_BY") "VSN")
      )
      (libsource (lib "Database_Libs1") (part "CON_1PIN"))
    )
    (comp (ref "J6")
      (value "CON_1PIN")
      (footprint "PTH_MTG400_700")
      (fields
        (field (name "DB_PART_NUMBER") "MTH000000030")
        (field (name "DB_VALUE") "PTH_MTG400_700")
        (field (name "DB_APPROVED_BY") "VSN")
      )
      (libsource (lib "Database_Libs1") (part "CON_1PIN"))
    )
    (comp (ref "J7")
      (value "CON_1PIN")
      (footprint "PTH_MTG400_700")
      (fields
        (field (name "DB_PART_NUMBER") "MTH000000030")
        (field (name "DB_VALUE") "PTH_MTG400_700")
        (field (name "DB_APPROVED_BY") "VSN")
      )
      (libsource (lib "Database_Libs1") (part "CON_1PIN"))
    )
    (comp (ref "J8")
      (value "CON_1PIN")
      (footprint "PTH_MTG400_700")
      (fields
        (field (name "DB_PART_NUMBER") "MTH000000030")
        (field (name "DB_VALUE") "PTH_MTG400_700")
        (field (name "DB_APPROVED_BY") "VSN")
      )
      (libsource (lib "Database_Libs1") (part "CON_1PIN"))
    )
    (comp (ref "J9")
      (value "CON_1PIN")
      (footprint "PTH_MTG400_700")
      (fields
        (field (name "DB_PART_NUMBER") "MTH000000030")
        (field (name "DB_VALUE") "PTH_MTG400_700")
        (field (name "DB_APPROVED_BY") "VSN")
      )
      (libsource (lib "Database_Libs1") (part "CON_1PIN"))
    )
    (comp (ref "J10")
      (value "CON_1PIN")
      (footprint "PTH_MTG400_700")
      (fields
        (field (name "DB_PART_NUMBER") "MTH000000030")
        (field (name "DB_VALUE") "PTH_MTG400_700")
        (field (name "DB_APPROVED_BY") "VSN")
      )
      (libsource (lib "Database_Libs1") (part "CON_1PIN"))
    )
    (comp (ref "J11")
      (value "CON_1PIN")
      (footprint "PTH_MTG400_700")
      (fields
        (field (name "DB_PART_NUMBER") "MTH000000030")
        (field (name "DB_VALUE") "PTH_MTG400_700")
        (field (name "DB_APPROVED_BY") "VSN")
      )
      (libsource (lib "Database_Libs1") (part "CON_1PIN"))
    )
    (comp (ref "J12")
      (value "CON_1PIN")
      (footprint "PTH_MTG400_700")
      (fields
        (field (name "DB_PART_NUMBER") "MTH000000030")
        (field (name "DB_VALUE") "PTH_MTG400_700")
        (field (name "DB_APPROVED_BY") "VSN")
      )
      (libsource (lib "Database_Libs1") (part "CON_1PIN"))
    )
    (comp (ref "J13")
      (value "CON_1PIN")
      (footprint "PTH_MTG400_700")
      (fields
        (field (name "DB_PART_NUMBER") "MTH000000030")
        (field (name "DB_VALUE") "PTH_MTG400_700")
        (field (name "DB_APPROVED_BY") "VSN")
      )
      (libsource (lib "Database_Libs1") (part "CON_1PIN"))
    )
    (comp (ref "J14")
      (value "CON_1PIN")
      (footprint "PTH_MTG400_700")
      (fields
        (field (name "DB_PART_NUMBER") "MTH000000030")
        (field (name "DB_VALUE") "PTH_MTG400_700")
        (field (name "DB_APPROVED_BY") "VSN")
      )
      (libsource (lib "Database_Libs1") (part "CON_1PIN"))
    )
    (comp (ref "J15")
      (value "CON_1PIN")
      (footprint "PTH_MTG400_700")
      (fields
        (field (name "DB_PART_NUMBER") "MTH000000030")
        (field (name "DB_VALUE") "PTH_MTG400_700")
        (field (name "DB_APPROVED_BY") "VSN")
      )
      (libsource (lib "Database_Libs1") (part "CON_1PIN"))
    )
    (comp (ref "L1")
      (value "SLC1480-201MLD")
      (footprint "SMT_INDM135130X800N")
      (libsource (lib "EPIQ_DND_CIS_Library") (part "L"))
    )
    (comp (ref "L2")
      (value "SLC1480-201MLD")
      (footprint "SMT_INDM135130X800N")
      (libsource (lib "EPIQ_DND_CIS_Library") (part "L"))
    )
    (comp (ref "L3")
      (value "SLC1480-201MLD")
      (footprint "SMT_INDM135130X800N")
      (libsource (lib "EPIQ_DND_CIS_Library") (part "L"))
    )
    (comp (ref "Q1")
      (value "MOS_N_D1_S1S2S3G4D5D6D7D8")
      (footprint "SMD_SOIC127P600X110-9AN")
      (fields
        (field (name "DB_PART_NUMBER") "TRA000001604")
        (field (name "DB_VALUE") "AP1RA03GMT-HF-3")
        (field (name "DB_MANUFACTURER_PART") "ADVANCED POWER ELECTRONICS CORP      AP1RA03GMT-HF-3")
        (field (name "DB_APPROVED_BY") "VSN")
      )
      (libsource (lib "Database_Libs1") (part "MOS_N_D1_S1S2S3G4D5D6D7D8"))
    )
    (comp (ref "Q2")
      (value "MOS_N_D1_S1S2S3G4D5D6D7D8")
      (footprint "SMD_SOIC127P600X110-9AN")
      (fields
        (field (name "DB_PART_NUMBER") "TRA000001604")
        (field (name "DB_VALUE") "AP1RA03GMT-HF-3")
        (field (name "DB_MANUFACTURER_PART") "ADVANCED POWER ELECTRONICS CORP      AP1RA03GMT-HF-3")
        (field (name "DB_APPROVED_BY") "VSN")
      )
      (libsource (lib "Database_Libs1") (part "MOS_N_D1_S1S2S3G4D5D6D7D8"))
    )
    (comp (ref "Q3")
      (value "MOS_N_D1_S1S2S3G4D5D6D7D8")
      (footprint "SMD_SOIC127P600X110-9AN")
      (fields
        (field (name "DB_PART_NUMBER") "TRA000001604")
        (field (name "DB_VALUE") "AP1RA03GMT-HF-3")
        (field (name "DB_MANUFACTURER_PART") "ADVANCED POWER ELECTRONICS CORP      AP1RA03GMT-HF-3")
        (field (name "DB_APPROVED_BY") "VSN")
      )
      (libsource (lib "Database_Libs1") (part "MOS_N_D1_S1S2S3G4D5D6D7D8"))
    )
    (comp (ref "Q4")
      (value "MOS_N_D1_S1S2S3G4D5D6D7D8")
      (footprint "SMD_SOIC127P600X110-9AN")
      (fields
        (field (name "DB_PART_NUMBER") "TRA000001604")
        (field (name "DB_VALUE") "AP1RA03GMT-HF-3")
        (field (name "DB_MANUFACTURER_PART") "ADVANCED POWER ELECTRONICS CORP      AP1RA03GMT-HF-3")
        (field (name "DB_APPROVED_BY") "VSN")
      )
      (libsource (lib "Database_Libs1") (part "MOS_N_D1_S1S2S3G4D5D6D7D8"))
    )
    (comp (ref "Q5")
      (value "MOS_N_D1_S1S2S3G4D5D6D7D8")
      (footprint "SMD_SOIC127P600X110-9AN")
      (fields
        (field (name "DB_PART_NUMBER") "TRA000001604")
        (field (name "DB_VALUE") "AP1RA03GMT-HF-3")
        (field (name "DB_MANUFACTURER_PART") "ADVANCED POWER ELECTRONICS CORP      AP1RA03GMT-HF-3")
        (field (name "DB_APPROVED_BY") "VSN")
      )
      (libsource (lib "Database_Libs1") (part "MOS_N_D1_S1S2S3G4D5D6D7D8"))
    )
    (comp (ref "Q6")
      (value "MOS_N_D1_S1S2S3G4D5D6D7D8")
      (footprint "SMD_SOIC127P600X110-9AN")
      (fields
        (field (name "DB_PART_NUMBER") "TRA000001604")
        (field (name "DB_VALUE") "AP1RA03GMT-HF-3")
        (field (name "DB_MANUFACTURER_PART") "ADVANCED POWER ELECTRONICS CORP      AP1RA03GMT-HF-3")
        (field (name "DB_APPROVED_BY") "VSN")
      )
      (libsource (lib "Database_Libs1") (part "MOS_N_D1_S1S2S3G4D5D6D7D8"))
    )
    (comp (ref "Q7")
      (value "MOS_N_D1_S1S2S3G4D5D6D7D8")
      (footprint "SMD_SOIC127P600X110-9AN")
      (fields
        (field (name "DB_PART_NUMBER") "TRA000001604")
        (field (name "DB_VALUE") "AP1RA03GMT-HF-3")
        (field (name "DB_MANUFACTURER_PART") "ADVANCED POWER ELECTRONICS CORP      AP1RA03GMT-HF-3")
        (field (name "DB_APPROVED_BY") "VSN")
      )
      (libsource (lib "Database_Libs1") (part "MOS_N_D1_S1S2S3G4D5D6D7D8"))
    )
    (comp (ref "Q8")
      (value "MOS_N_D1_S1S2S3G4D5D6D7D8")
      (footprint "SMD_SOIC127P600X110-9AN")
      (fields
        (field (name "DB_PART_NUMBER") "TRA000001604")
        (field (name "DB_VALUE") "AP1RA03GMT-HF-3")
        (field (name "DB_MANUFACTURER_PART") "ADVANCED POWER ELECTRONICS CORP      AP1RA03GMT-HF-3")
        (field (name "DB_APPROVED_BY") "VSN")
      )
      (libsource (lib "Database_Libs1") (part "MOS_N_D1_S1S2S3G4D5D6D7D8"))
    )
    (comp (ref "Q9")
      (value "MOS_N_D1_S1S2S3G4D5D6D7D8")
      (footprint "SMD_SOIC127P600X110-9AN")
      (fields
        (field (name "DB_PART_NUMBER") "TRA000001604")
        (field (name "DB_VALUE") "AP1RA03GMT-HF-3")
        (field (name "DB_MANUFACTURER_PART") "ADVANCED POWER ELECTRONICS CORP      AP1RA03GMT-HF-3")
        (field (name "DB_APPROVED_BY") "VSN")
      )
      (libsource (lib "Database_Libs1") (part "MOS_N_D1_S1S2S3G4D5D6D7D8"))
    )
    (comp (ref "R1")
      (value "R")
      (footprint "SMD_0603_RESC1608X55N")
      (fields
        (field (name "DB_PART_NUMBER") "RES000008663")
        (field (name "DB_VALUE") "10k")
        (field (name "DB_TOLERANCE") "1%")
        (field (name "DB_MANUFACTURER_PART") "YAGEO    RC0603FR-0710KL")
        (field (name "DB_APPROVED_BY") "VSN")
      )
      (libsource (lib "Database_Libs1") (part "R"))
    )
    (comp (ref "R2")
      (value "R")
      (footprint "SMD_0603_RESC1608X55N")
      (fields
        (field (name "DB_PART_NUMBER") "RES000008663")
        (field (name "DB_VALUE") "10k")
        (field (name "DB_TOLERANCE") "1%")
        (field (name "DB_MANUFACTURER_PART") "YAGEO    RC0603FR-0710KL")
        (field (name "DB_APPROVED_BY") "VSN")
      )
      (libsource (lib "Database_Libs1") (part "R"))
    )
    (comp (ref "R3")
      (value "R")
      (footprint "SMD_0603_RESC1608X55N")
      (fields
        (field (name "DB_PART_NUMBER") "RES000008663")
        (field (name "DB_VALUE") "10k")
        (field (name "DB_TOLERANCE") "1%")
        (field (name "DB_MANUFACTURER_PART") "YAGEO    RC0603FR-0710KL")
        (field (name "DB_APPROVED_BY") "VSN")
      )
      (libsource (lib "Database_Libs1") (part "R"))
    )
    (comp (ref "R4")
      (value "R")
      (footprint "SMD_0603_RESC1608X55N")
      (fields
        (field (name "DB_PART_NUMBER") "RES000008663")
        (field (name "DB_VALUE") "10k")
        (field (name "DB_TOLERANCE") "1%")
        (field (name "DB_MANUFACTURER_PART") "YAGEO    RC0603FR-0710KL")
        (field (name "DB_APPROVED_BY") "VSN")
      )
      (libsource (lib "Database_Libs1") (part "R"))
    )
    (comp (ref "R5")
      (value "R")
      (footprint "SMD_0603_RESC1608X55N")
      (fields
        (field (name "DB_PART_NUMBER") "RES000008663")
        (field (name "DB_VALUE") "10k")
        (field (name "DB_TOLERANCE") "1%")
        (field (name "DB_MANUFACTURER_PART") "YAGEO    RC0603FR-0710KL")
        (field (name "DB_APPROVED_BY") "VSN")
      )
      (libsource (lib "Database_Libs1") (part "R"))
    )
    (comp (ref "R6")
      (value "R")
      (footprint "SMD_0603_RESC1608X55N")
      (fields
        (field (name "DB_PART_NUMBER") "RES000008663")
        (field (name "DB_VALUE") "10k")
        (field (name "DB_TOLERANCE") "1%")
        (field (name "DB_MANUFACTURER_PART") "YAGEO    RC0603FR-0710KL")
        (field (name "DB_APPROVED_BY") "VSN")
      )
      (libsource (lib "Database_Libs1") (part "R"))
    )
    (comp (ref "R7")
      (value "R")
      (footprint "SMD_0603_RESC1608X55N")
      (fields
        (field (name "DB_PART_NUMBER") "RES000008663")
        (field (name "DB_VALUE") "10k")
        (field (name "DB_TOLERANCE") "1%")
        (field (name "DB_MANUFACTURER_PART") "YAGEO    RC0603FR-0710KL")
        (field (name "DB_APPROVED_BY") "VSN")
      )
      (libsource (lib "Database_Libs1") (part "R"))
    )
    (comp (ref "R8")
      (value "R")
      (footprint "SMD_0603_RESC1608X55N")
      (fields
        (field (name "DB_PART_NUMBER") "RES000008663")
        (field (name "DB_VALUE") "10k")
        (field (name "DB_TOLERANCE") "1%")
        (field (name "DB_MANUFACTURER_PART") "YAGEO    RC0603FR-0710KL")
        (field (name "DB_APPROVED_BY") "VSN")
      )
      (libsource (lib "Database_Libs1") (part "R"))
    )
    (comp (ref "R17")
      (value "R")
      (footprint "SMD_0603_RESC1608X55N")
      (fields
        (field (name "DB_PART_NUMBER") "RES000008663")
        (field (name "DB_VALUE") "10k")
        (field (name "DB_TOLERANCE") "1%")
        (field (name "DB_MANUFACTURER_PART") "YAGEO    RC0603FR-0710KL")
        (field (name "DB_APPROVED_BY") "VSN")
      )
      (libsource (lib "Database_Libs1") (part "R"))
    )
    (comp (ref "R18")
      (value "R")
      (footprint "SMD_0603_RESC1608X55N")
      (fields
        (field (name "DB_PART_NUMBER") "RES000008663")
        (field (name "DB_VALUE") "10k")
        (field (name "DB_TOLERANCE") "1%")
        (field (name "DB_MANUFACTURER_PART") "YAGEO    RC0603FR-0710KL")
        (field (name "DB_APPROVED_BY") "VSN")
      )
      (libsource (lib "Database_Libs1") (part "R"))
    )
    (comp (ref "R19")
      (value "R")
      (footprint "SMD_0603_RESC1608X55N")
      (fields
        (field (name "DB_PART_NUMBER") "RES000008663")
        (field (name "DB_VALUE") "10k")
        (field (name "DB_TOLERANCE") "1%")
        (field (name "DB_MANUFACTURER_PART") "YAGEO    RC0603FR-0710KL")
        (field (name "DB_APPROVED_BY") "VSN")
      )
      (libsource (lib "Database_Libs1") (part "R"))
    )
    (comp (ref "R20")
      (value "R")
      (footprint "SMD_0603_RESC1608X55N")
      (fields
        (field (name "DB_PART_NUMBER") "RES000008663")
        (field (name "DB_VALUE") "10k")
        (field (name "DB_TOLERANCE") "1%")
        (field (name "DB_MANUFACTURER_PART") "YAGEO    RC0603FR-0710KL")
        (field (name "DB_APPROVED_BY") "VSN")
      )
      (libsource (lib "Database_Libs1") (part "R"))
    )
    (comp (ref "R21")
      (value "R")
      (footprint "SMD_0603_RESC1608X55N")
      (fields
        (field (name "DB_PART_NUMBER") "RES000008663")
        (field (name "DB_VALUE") "10k")
        (field (name "DB_TOLERANCE") "1%")
        (field (name "DB_MANUFACTURER_PART") "YAGEO    RC0603FR-0710KL")
        (field (name "DB_APPROVED_BY") "VSN")
      )
      (libsource (lib "Database_Libs1") (part "R"))
    )
    (comp (ref "R22")
      (value "R")
      (footprint "SMD_0603_RESC1608X55N")
      (fields
        (field (name "DB_PART_NUMBER") "RES000008663")
        (field (name "DB_VALUE") "10k")
        (field (name "DB_TOLERANCE") "1%")
        (field (name "DB_MANUFACTURER_PART") "YAGEO    RC0603FR-0710KL")
        (field (name "DB_APPROVED_BY") "VSN")
      )
      (libsource (lib "Database_Libs1") (part "R"))
    )
    (comp (ref "R23")
      (value "R")
      (footprint "SMD_0603_RESC1608X55N")
      (fields
        (field (name "DB_PART_NUMBER") "RES000008663")
        (field (name "DB_VALUE") "10k")
        (field (name "DB_TOLERANCE") "1%")
        (field (name "DB_MANUFACTURER_PART") "YAGEO    RC0603FR-0710KL")
        (field (name "DB_APPROVED_BY") "VSN")
      )
      (libsource (lib "Database_Libs1") (part "R"))
    )
    (comp (ref "R24")
      (value "R")
      (footprint "SMD_0603_RESC1608X55N")
      (fields
        (field (name "DB_PART_NUMBER") "RES000008663")
        (field (name "DB_VALUE") "10k")
        (field (name "DB_TOLERANCE") "1%")
        (field (name "DB_MANUFACTURER_PART") "YAGEO    RC0603FR-0710KL")
        (field (name "DB_APPROVED_BY") "VSN")
      )
      (libsource (lib "Database_Libs1") (part "R"))
    )
    (comp (ref "R25")
      (value "R")
      (footprint "SMD_0603_RESC1608X55N")
      (fields
        (field (name "DB_PART_NUMBER") "RES000006261")
        (field (name "DB_VALUE") "2.4k")
        (field (name "DB_TOLERANCE") "1%")
        (field (name "DB_MANUFACTURER_PART") "YAGEO    RC0603FR-072K4")
        (field (name "DB_APPROVED_BY") "ISHIDDEN=T")
      )
      (libsource (lib "Database_Libs1") (part "R"))
    )
    (comp (ref "R26")
      (value "R")
      (footprint "SMD_0603_RESC1608X55N")
      (fields
        (field (name "DB_PART_NUMBER") "RES000008663")
        (field (name "DB_VALUE") "10k")
        (field (name "DB_TOLERANCE") "1%")
        (field (name "DB_MANUFACTURER_PART") "YAGEO    RC0603FR-0710KL")
        (field (name "DB_APPROVED_BY") "VSN")
      )
      (libsource (lib "Database_Libs1") (part "R"))
    )
    (comp (ref "R27")
      (value "R")
      (footprint "SMD_0603_RESC1608X55N")
      (fields
        (field (name "DB_PART_NUMBER") "RES000006220")
        (field (name "DB_VALUE") "47R")
        (field (name "DB_TOLERANCE") "1%")
        (field (name "DB_MANUFACTURER_PART") "YAGEO    RC0603FR-0747R")
        (field (name "DB_APPROVED_BY") "ISHIDDEN=T")
      )
      (libsource (lib "Database_Libs1") (part "R"))
    )
    (comp (ref "R30")
      (value "R")
      (footprint "SMD_0603_RESC1608X55N")
      (fields
        (field (name "DB_PART_NUMBER") "RES000006220")
        (field (name "DB_VALUE") "47R")
        (field (name "DB_TOLERANCE") "1%")
        (field (name "DB_MANUFACTURER_PART") "YAGEO    RC0603FR-0747R")
        (field (name "DB_APPROVED_BY") "ISHIDDEN=T")
      )
      (libsource (lib "Database_Libs1") (part "R"))
    )
    (comp (ref "R31")
      (value "R")
      (footprint "SMD_0603_RESC1608X55N")
      (fields
        (field (name "DB_PART_NUMBER") "RES000008663")
        (field (name "DB_VALUE") "10k")
        (field (name "DB_TOLERANCE") "1%")
        (field (name "DB_MANUFACTURER_PART") "YAGEO    RC0603FR-0710KL")
        (field (name "DB_APPROVED_BY") "VSN")
      )
      (libsource (lib "Database_Libs1") (part "R"))
    )
    (comp (ref "R32")
      (value "R")
      (footprint "SMD_0603_RESC1608X55N")
      (fields
        (field (name "DB_PART_NUMBER") "RES000008663")
        (field (name "DB_VALUE") "10k")
        (field (name "DB_TOLERANCE") "1%")
        (field (name "DB_MANUFACTURER_PART") "YAGEO    RC0603FR-0710KL")
        (field (name "DB_APPROVED_BY") "VSN")
      )
      (libsource (lib "Database_Libs1") (part "R"))
    )
    (comp (ref "R33")
      (value "R")
      (footprint "SMD_0603_RESC1608X55N")
      (fields
        (field (name "DB_PART_NUMBER") "RES000008926")
        (field (name "DB_VALUE") "0R")
        (field (name "DB_TOLERANCE") "1%")
        (field (name "DB_MANUFACTURER_PART") "YAGEO    AC0603FR-070RL")
        (field (name "DB_APPROVED_BY") "VSN")
      )
      (libsource (lib "Database_Libs1") (part "R"))
    )
    (comp (ref "R42")
      (value "R")
      (footprint "SMD_1206_RESC3216X65N")
      (fields
        (field (name "DB_PART_NUMBER") "RES000007051")
        (field (name "DB_VALUE") "2R")
        (field (name "DB_TOLERANCE") "5%")
        (field (name "DB_MANUFACTURER_PART") "YAGEO    RC1206JR-072R")
        (field (name "DB_APPROVED_BY") "ISHIDDEN=T")
      )
      (libsource (lib "Database_Libs1") (part "R"))
    )
    (comp (ref "R43")
      (value "R")
      (footprint "SMD_0603_RESC1608X55N")
      (fields
        (field (name "DB_PART_NUMBER") "RES000008663")
        (field (name "DB_VALUE") "10k")
        (field (name "DB_TOLERANCE") "1%")
        (field (name "DB_MANUFACTURER_PART") "YAGEO    RC0603FR-0710KL")
        (field (name "DB_APPROVED_BY") "VSN")
      )
      (libsource (lib "Database_Libs1") (part "R"))
    )
    (comp (ref "R44")
      (value "R")
      (footprint "SMD_0603_RESC1608X55N")
      (fields
        (field (name "DB_PART_NUMBER") "RES000008663")
        (field (name "DB_VALUE") "10k")
        (field (name "DB_TOLERANCE") "1%")
        (field (name "DB_MANUFACTURER_PART") "YAGEO    RC0603FR-0710KL")
        (field (name "DB_APPROVED_BY") "VSN")
      )
      (libsource (lib "Database_Libs1") (part "R"))
    )
    (comp (ref "R45")
      (value "R")
      (footprint "SMD_0603_RESC1608X55N")
      (fields
        (field (name "DB_PART_NUMBER") "RES000008663")
        (field (name "DB_VALUE") "10k")
        (field (name "DB_TOLERANCE") "1%")
        (field (name "DB_MANUFACTURER_PART") "YAGEO    RC0603FR-0710KL")
        (field (name "DB_APPROVED_BY") "VSN")
      )
      (libsource (lib "Database_Libs1") (part "R"))
    )
    (comp (ref "R46")
      (value "R")
      (footprint "SMD_0603_RESC1608X55N")
      (fields
        (field (name "DB_PART_NUMBER") "RES000008663")
        (field (name "DB_VALUE") "10k")
        (field (name "DB_TOLERANCE") "1%")
        (field (name "DB_MANUFACTURER_PART") "YAGEO    RC0603FR-0710KL")
        (field (name "DB_APPROVED_BY") "VSN")
      )
      (libsource (lib "Database_Libs1") (part "R"))
    )
    (comp (ref "R47")
      (value "R")
      (footprint "SMD_1206_RESC3216X65N")
      (fields
        (field (name "DB_PART_NUMBER") "RES000006922")
        (field (name "DB_VALUE") "100R")
        (field (name "DB_TOLERANCE") "1%")
        (field (name "DB_MANUFACTURER_PART") "YAGEO    RC1206FR-07100R")
        (field (name "DB_APPROVED_BY") "ISHIDDEN=T")
      )
      (libsource (lib "Database_Libs1") (part "R"))
    )
    (comp (ref "R48")
      (value "R")
      (footprint "SMD_1206_RESC3216X65N")
      (fields
        (field (name "DB_PART_NUMBER") "RES000008756")
        (field (name "DB_VALUE") "0R")
        (field (name "DB_TOLERANCE") "1%")
        (field (name "DB_MANUFACTURER_PART") "YAGEO    AC1206FR-070RL")
        (field (name "DB_APPROVED_BY") "VSN")
      )
      (libsource (lib "Database_Libs1") (part "R"))
    )
    (comp (ref "R49")
      (value "R")
      (footprint "SMD_1206_RESC3216X65N")
      (fields
        (field (name "DB_PART_NUMBER") "RES000008756")
        (field (name "DB_VALUE") "0R")
        (field (name "DB_TOLERANCE") "1%")
        (field (name "DB_MANUFACTURER_PART") "YAGEO    AC1206FR-070RL")
        (field (name "DB_APPROVED_BY") "VSN")
      )
      (libsource (lib "Database_Libs1") (part "R"))
    )
    (comp (ref "R50")
      (value "R")
      (footprint "SMD_0603_RESC1608X55N")
      (fields
        (field (name "DB_PART_NUMBER") "RES000008663")
        (field (name "DB_VALUE") "10k")
        (field (name "DB_TOLERANCE") "1%")
        (field (name "DB_MANUFACTURER_PART") "YAGEO    RC0603FR-0710KL")
        (field (name "DB_APPROVED_BY") "VSN")
      )
      (libsource (lib "Database_Libs1") (part "R"))
    )
    (comp (ref "R51")
      (value "R")
      (footprint "SMD_0603_RESC1608X55N")
      (fields
        (field (name "DB_PART_NUMBER") "RES000006287")
        (field (name "DB_VALUE") "30k")
        (field (name "DB_TOLERANCE") "1%")
        (field (name "DB_MANUFACTURER_PART") "YAGEO    RC0603FR-0730K")
        (field (name "DB_APPROVED_BY") "ISHIDDEN=T")
      )
      (libsource (lib "Database_Libs1") (part "R"))
    )
    (comp (ref "R52")
      (value "R")
      (footprint "SMD_0603_RESC1608X55N")
      (fields
        (field (name "DB_PART_NUMBER") "RES000008663")
        (field (name "DB_VALUE") "10k")
        (field (name "DB_TOLERANCE") "1%")
        (field (name "DB_MANUFACTURER_PART") "YAGEO    RC0603FR-0710KL")
        (field (name "DB_APPROVED_BY") "VSN")
      )
      (libsource (lib "Database_Libs1") (part "R"))
    )
    (comp (ref "R53")
      (value "R")
      (footprint "SMD_0603_RESC1608X55N")
      (fields
        (field (name "DB_PART_NUMBER") "RES000008663")
        (field (name "DB_VALUE") "10k")
        (field (name "DB_TOLERANCE") "1%")
        (field (name "DB_MANUFACTURER_PART") "YAGEO    RC0603FR-0710KL")
        (field (name "DB_APPROVED_BY") "VSN")
      )
      (libsource (lib "Database_Libs1") (part "R"))
    )
    (comp (ref "R54")
      (value "R")
      (footprint "SMD_0603_RESC1608X55N")
      (fields
        (field (name "DB_PART_NUMBER") "RES000008663")
        (field (name "DB_VALUE") "10k")
        (field (name "DB_TOLERANCE") "1%")
        (field (name "DB_MANUFACTURER_PART") "YAGEO    RC0603FR-0710KL")
        (field (name "DB_APPROVED_BY") "VSN")
      )
      (libsource (lib "Database_Libs1") (part "R"))
    )
    (comp (ref "R55")
      (value "R")
      (footprint "SMD_0603_RESC1608X55N")
      (fields
        (field (name "DB_PART_NUMBER") "RES000006287")
        (field (name "DB_VALUE") "30k")
        (field (name "DB_TOLERANCE") "1%")
        (field (name "DB_MANUFACTURER_PART") "YAGEO    RC0603FR-0730K")
        (field (name "DB_APPROVED_BY") "ISHIDDEN=T")
      )
      (libsource (lib "Database_Libs1") (part "R"))
    )
    (comp (ref "R64")
      (value "R")
      (footprint "SMD_0603_RESC1608X55N")
      (fields
        (field (name "DB_PART_NUMBER") "RES000008663")
        (field (name "DB_VALUE") "10k")
        (field (name "DB_TOLERANCE") "1%")
        (field (name "DB_MANUFACTURER_PART") "YAGEO    RC0603FR-0710KL")
        (field (name "DB_APPROVED_BY") "VSN")
      )
      (libsource (lib "Database_Libs1") (part "R"))
    )
    (comp (ref "R65")
      (value "R")
      (footprint "SMD_0603_RESC1608X55N")
      (fields
        (field (name "DB_PART_NUMBER") "RES000008663")
        (field (name "DB_VALUE") "10k")
        (field (name "DB_TOLERANCE") "1%")
        (field (name "DB_MANUFACTURER_PART") "YAGEO    RC0603FR-0710KL")
        (field (name "DB_APPROVED_BY") "VSN")
      )
      (libsource (lib "Database_Libs1") (part "R"))
    )
    (comp (ref "R66")
      (value "R")
      (footprint "SMD_0603_RESC1608X55N")
      (fields
        (field (name "DB_PART_NUMBER") "RES000008663")
        (field (name "DB_VALUE") "10k")
        (field (name "DB_TOLERANCE") "1%")
        (field (name "DB_MANUFACTURER_PART") "YAGEO    RC0603FR-0710KL")
        (field (name "DB_APPROVED_BY") "VSN")
      )
      (libsource (lib "Database_Libs1") (part "R"))
    )
    (comp (ref "R67")
      (value "R")
      (footprint "SMD_0603_RESC1608X55N")
      (fields
        (field (name "DB_PART_NUMBER") "RES000008663")
        (field (name "DB_VALUE") "10k")
        (field (name "DB_TOLERANCE") "1%")
        (field (name "DB_MANUFACTURER_PART") "YAGEO    RC0603FR-0710KL")
        (field (name "DB_APPROVED_BY") "VSN")
      )
      (libsource (lib "Database_Libs1") (part "R"))
    )
    (comp (ref "TP1")
      (value "TEST_POINT_1")
      (footprint "SMD_TP_100-254")
      (fields
        (field (name "DB_PART_NUMBER") "TPO000000001")
        (field (name "DB_MANUFACTURER_PART") "ISHIDDEN=T")
        (field (name "DB_APPROVED_BY") "ISHIDDEN=T")
      )
      (libsource (lib "Database_Libs1") (part "TEST_POINT_1"))
    )
    (comp (ref "TP2")
      (value "TEST_POINT_1")
      (footprint "SMD_TP_100-254")
      (fields
        (field (name "DB_PART_NUMBER") "TPO000000001")
        (field (name "DB_MANUFACTURER_PART") "ISHIDDEN=T")
        (field (name "DB_APPROVED_BY") "ISHIDDEN=T")
      )
      (libsource (lib "Database_Libs1") (part "TEST_POINT_1"))
    )
    (comp (ref "TP3")
      (value "TEST_POINT_1")
      (footprint "SMD_TP_100-254")
      (fields
        (field (name "DB_PART_NUMBER") "TPO000000001")
        (field (name "DB_MANUFACTURER_PART") "ISHIDDEN=T")
        (field (name "DB_APPROVED_BY") "ISHIDDEN=T")
      )
      (libsource (lib "Database_Libs1") (part "TEST_POINT_1"))
    )
    (comp (ref "TP4")
      (value "TEST_POINT_1")
      (footprint "SMD_TP_100-254")
      (fields
        (field (name "DB_PART_NUMBER") "TPO000000001")
        (field (name "DB_MANUFACTURER_PART") "ISHIDDEN=T")
        (field (name "DB_APPROVED_BY") "ISHIDDEN=T")
      )
      (libsource (lib "Database_Libs1") (part "TEST_POINT_1"))
    )
    (comp (ref "TP5")
      (value "TEST_POINT_1")
      (footprint "SMD_TP_100-254")
      (fields
        (field (name "DB_PART_NUMBER") "TPO000000001")
        (field (name "DB_MANUFACTURER_PART") "ISHIDDEN=T")
        (field (name "DB_APPROVED_BY") "ISHIDDEN=T")
      )
      (libsource (lib "Database_Libs1") (part "TEST_POINT_1"))
    )
    (comp (ref "TP6")
      (value "TEST_POINT_1")
      (footprint "SMD_TP_100-254")
      (fields
        (field (name "DB_PART_NUMBER") "TPO000000001")
        (field (name "DB_MANUFACTURER_PART") "ISHIDDEN=T")
        (field (name "DB_APPROVED_BY") "ISHIDDEN=T")
      )
      (libsource (lib "Database_Libs1") (part "TEST_POINT_1"))
    )
    (comp (ref "TP7")
      (value "TEST_POINT_1")
      (footprint "SMD_TP_100-254")
      (fields
        (field (name "DB_PART_NUMBER") "TPO000000001")
        (field (name "DB_MANUFACTURER_PART") "ISHIDDEN=T")
        (field (name "DB_APPROVED_BY") "ISHIDDEN=T")
      )
      (libsource (lib "Database_Libs1") (part "TEST_POINT_1"))
    )
    (comp (ref "TP8")
      (value "TEST_POINT_1")
      (footprint "SMD_TP_100-254")
      (fields
        (field (name "DB_PART_NUMBER") "TPO000000001")
        (field (name "DB_MANUFACTURER_PART") "ISHIDDEN=T")
        (field (name "DB_APPROVED_BY") "ISHIDDEN=T")
      )
      (libsource (lib "Database_Libs1") (part "TEST_POINT_1"))
    )
    (comp (ref "TP9")
      (value "TEST_POINT_1")
      (footprint "SMD_TP_100-254")
      (fields
        (field (name "DB_PART_NUMBER") "TPO000000001")
        (field (name "DB_MANUFACTURER_PART") "ISHIDDEN=T")
        (field (name "DB_APPROVED_BY") "ISHIDDEN=T")
      )
      (libsource (lib "Database_Libs1") (part "TEST_POINT_1"))
    )
    (comp (ref "TP10")
      (value "TEST_POINT_1")
      (footprint "SMD_TP_100-254")
      (fields
        (field (name "DB_PART_NUMBER") "TPO000000001")
        (field (name "DB_MANUFACTURER_PART") "ISHIDDEN=T")
        (field (name "DB_APPROVED_BY") "ISHIDDEN=T")
      )
      (libsource (lib "Database_Libs1") (part "TEST_POINT_1"))
    )
    (comp (ref "TP11")
      (value "TEST_POINT_1")
      (footprint "SMD_TP_100-254")
      (fields
        (field (name "DB_PART_NUMBER") "TPO000000001")
        (field (name "DB_MANUFACTURER_PART") "ISHIDDEN=T")
        (field (name "DB_APPROVED_BY") "ISHIDDEN=T")
      )
      (libsource (lib "Database_Libs1") (part "TEST_POINT_1"))
    )
    (comp (ref "TP12")
      (value "TEST_POINT_1")
      (footprint "SMD_TP_100-254")
      (fields
        (field (name "DB_PART_NUMBER") "TPO000000001")
        (field (name "DB_MANUFACTURER_PART") "ISHIDDEN=T")
        (field (name "DB_APPROVED_BY") "ISHIDDEN=T")
      )
      (libsource (lib "Database_Libs1") (part "TEST_POINT_1"))
    )
    (comp (ref "TP13")
      (value "TEST_POINT_1")
      (footprint "SMD_TP_100-254")
      (fields
        (field (name "DB_PART_NUMBER") "TPO000000001")
        (field (name "DB_MANUFACTURER_PART") "ISHIDDEN=T")
        (field (name "DB_APPROVED_BY") "ISHIDDEN=T")
      )
      (libsource (lib "Database_Libs1") (part "TEST_POINT_1"))
    )
    (comp (ref "TP14")
      (value "TEST_POINT_1")
      (footprint "SMD_TP_100-254")
      (fields
        (field (name "DB_PART_NUMBER") "TPO000000001")
        (field (name "DB_MANUFACTURER_PART") "ISHIDDEN=T")
        (field (name "DB_APPROVED_BY") "ISHIDDEN=T")
      )
      (libsource (lib "Database_Libs1") (part "TEST_POINT_1"))
    )
    (comp (ref "TP15")
      (value "TEST_POINT_1")
      (footprint "SMD_TP_100-254")
      (fields
        (field (name "DB_PART_NUMBER") "TPO000000001")
        (field (name "DB_MANUFACTURER_PART") "ISHIDDEN=T")
        (field (name "DB_APPROVED_BY") "ISHIDDEN=T")
      )
      (libsource (lib "Database_Libs1") (part "TEST_POINT_1"))
    )
    (comp (ref "TP16")
      (value "TEST_POINT_1")
      (footprint "SMD_TP_100-254")
      (fields
        (field (name "DB_PART_NUMBER") "TPO000000001")
        (field (name "DB_MANUFACTURER_PART") "ISHIDDEN=T")
        (field (name "DB_APPROVED_BY") "ISHIDDEN=T")
      )
      (libsource (lib "Database_Libs1") (part "TEST_POINT_1"))
    )
    (comp (ref "TP17")
      (value "TEST_POINT_1")
      (footprint "SMD_TP_100-254")
      (fields
        (field (name "DB_PART_NUMBER") "TPO000000001")
        (field (name "DB_MANUFACTURER_PART") "ISHIDDEN=T")
        (field (name "DB_APPROVED_BY") "ISHIDDEN=T")
      )
      (libsource (lib "Database_Libs1") (part "TEST_POINT_1"))
    )
    (comp (ref "TP18")
      (value "TEST_POINT_1")
      (footprint "SMD_TP_100-254")
      (fields
        (field (name "DB_PART_NUMBER") "TPO000000001")
        (field (name "DB_MANUFACTURER_PART") "ISHIDDEN=T")
        (field (name "DB_APPROVED_BY") "ISHIDDEN=T")
      )
      (libsource (lib "Database_Libs1") (part "TEST_POINT_1"))
    )
    (comp (ref "TP19")
      (value "TEST_POINT_1")
      (footprint "SMD_TP_100-254")
      (fields
        (field (name "DB_PART_NUMBER") "TPO000000001")
        (field (name "DB_MANUFACTURER_PART") "ISHIDDEN=T")
        (field (name "DB_APPROVED_BY") "ISHIDDEN=T")
      )
      (libsource (lib "Database_Libs1") (part "TEST_POINT_1"))
    )
    (comp (ref "TP20")
      (value "TEST_POINT_1")
      (footprint "SMD_TP_100-254")
      (fields
        (field (name "DB_PART_NUMBER") "TPO000000001")
        (field (name "DB_MANUFACTURER_PART") "ISHIDDEN=T")
        (field (name "DB_APPROVED_BY") "ISHIDDEN=T")
      )
      (libsource (lib "Database_Libs1") (part "TEST_POINT_1"))
    )
    (comp (ref "TP21")
      (value "TEST_POINT_1")
      (footprint "SMD_TP_100-254")
      (fields
        (field (name "DB_PART_NUMBER") "TPO000000001")
        (field (name "DB_MANUFACTURER_PART") "ISHIDDEN=T")
        (field (name "DB_APPROVED_BY") "ISHIDDEN=T")
      )
      (libsource (lib "Database_Libs1") (part "TEST_POINT_1"))
    )
    (comp (ref "TP22")
      (value "TEST_POINT_1")
      (footprint "SMD_TP_100-254")
      (fields
        (field (name "DB_PART_NUMBER") "TPO000000001")
        (field (name "DB_MANUFACTURER_PART") "ISHIDDEN=T")
        (field (name "DB_APPROVED_BY") "ISHIDDEN=T")
      )
      (libsource (lib "Database_Libs1") (part "TEST_POINT_1"))
    )
    (comp (ref "TP23")
      (value "TEST_POINT_1")
      (footprint "SMD_TP_100-254")
      (fields
        (field (name "DB_PART_NUMBER") "TPO000000001")
        (field (name "DB_MANUFACTURER_PART") "ISHIDDEN=T")
        (field (name "DB_APPROVED_BY") "ISHIDDEN=T")
      )
      (libsource (lib "Database_Libs1") (part "TEST_POINT_1"))
    )
    (comp (ref "TP24")
      (value "TEST_POINT_1")
      (footprint "SMD_TP_100-254")
      (fields
        (field (name "DB_PART_NUMBER") "TPO000000001")
        (field (name "DB_MANUFACTURER_PART") "ISHIDDEN=T")
        (field (name "DB_APPROVED_BY") "ISHIDDEN=T")
      )
      (libsource (lib "Database_Libs1") (part "TEST_POINT_1"))
    )
    (comp (ref "TP25")
      (value "TEST_POINT_1")
      (footprint "SMD_TP_100-254")
      (fields
        (field (name "DB_PART_NUMBER") "TPO000000001")
        (field (name "DB_MANUFACTURER_PART") "ISHIDDEN=T")
        (field (name "DB_APPROVED_BY") "ISHIDDEN=T")
      )
      (libsource (lib "Database_Libs1") (part "TEST_POINT_1"))
    )
    (comp (ref "TP26")
      (value "TEST_POINT_1")
      (footprint "SMD_TP_100-254")
      (fields
        (field (name "DB_PART_NUMBER") "TPO000000001")
        (field (name "DB_MANUFACTURER_PART") "ISHIDDEN=T")
        (field (name "DB_APPROVED_BY") "ISHIDDEN=T")
      )
      (libsource (lib "Database_Libs1") (part "TEST_POINT_1"))
    )
    (comp (ref "TP27")
      (value "TEST_POINT_1")
      (footprint "SMD_TP_100-254")
      (fields
        (field (name "DB_PART_NUMBER") "TPO000000001")
        (field (name "DB_MANUFACTURER_PART") "ISHIDDEN=T")
        (field (name "DB_APPROVED_BY") "ISHIDDEN=T")
      )
      (libsource (lib "Database_Libs1") (part "TEST_POINT_1"))
    )
    (comp (ref "TP28")
      (value "TEST_POINT_1")
      (footprint "SMD_TP_100-254")
      (fields
        (field (name "DB_PART_NUMBER") "TPO000000001")
        (field (name "DB_MANUFACTURER_PART") "ISHIDDEN=T")
        (field (name "DB_APPROVED_BY") "ISHIDDEN=T")
      )
      (libsource (lib "Database_Libs1") (part "TEST_POINT_1"))
    )
    (comp (ref "TP29")
      (value "TEST_POINT_1")
      (footprint "SMD_TP_100-254")
      (fields
        (field (name "DB_PART_NUMBER") "TPO000000001")
        (field (name "DB_MANUFACTURER_PART") "ISHIDDEN=T")
        (field (name "DB_APPROVED_BY") "ISHIDDEN=T")
      )
      (libsource (lib "Database_Libs1") (part "TEST_POINT_1"))
    )
    (comp (ref "TP30")
      (value "TEST_POINT_1")
      (footprint "SMD_TP_100-254")
      (fields
        (field (name "DB_PART_NUMBER") "TPO000000001")
        (field (name "DB_MANUFACTURER_PART") "ISHIDDEN=T")
        (field (name "DB_APPROVED_BY") "ISHIDDEN=T")
      )
      (libsource (lib "Database_Libs1") (part "TEST_POINT_1"))
    )
    (comp (ref "TP31")
      (value "TEST_POINT_1")
      (footprint "SMD_TP_100-254")
      (fields
        (field (name "DB_PART_NUMBER") "TPO000000001")
        (field (name "DB_MANUFACTURER_PART") "ISHIDDEN=T")
        (field (name "DB_APPROVED_BY") "ISHIDDEN=T")
      )
      (libsource (lib "Database_Libs1") (part "TEST_POINT_1"))
    )
    (comp (ref "TP32")
      (value "TEST_POINT_1")
      (footprint "SMD_TP_100-254")
      (fields
        (field (name "DB_PART_NUMBER") "TPO000000001")
        (field (name "DB_MANUFACTURER_PART") "ISHIDDEN=T")
        (field (name "DB_APPROVED_BY") "ISHIDDEN=T")
      )
      (libsource (lib "Database_Libs1") (part "TEST_POINT_1"))
    )
    (comp (ref "TP33")
      (value "TEST_POINT_1")
      (footprint "SMD_TP_100-254")
      (fields
        (field (name "DB_PART_NUMBER") "TPO000000001")
        (field (name "DB_MANUFACTURER_PART") "ISHIDDEN=T")
        (field (name "DB_APPROVED_BY") "ISHIDDEN=T")
      )
      (libsource (lib "Database_Libs1") (part "TEST_POINT_1"))
    )
    (comp (ref "TP34")
      (value "TEST_POINT_1")
      (footprint "SMD_TP_100-254")
      (fields
        (field (name "DB_PART_NUMBER") "TPO000000001")
        (field (name "DB_MANUFACTURER_PART") "ISHIDDEN=T")
        (field (name "DB_APPROVED_BY") "ISHIDDEN=T")
      )
      (libsource (lib "Database_Libs1") (part "TEST_POINT_1"))
    )
    (comp (ref "TP35")
      (value "TEST_POINT_1")
      (footprint "SMD_TP_100-254")
      (fields
        (field (name "DB_PART_NUMBER") "TPO000000001")
        (field (name "DB_MANUFACTURER_PART") "ISHIDDEN=T")
        (field (name "DB_APPROVED_BY") "ISHIDDEN=T")
      )
      (libsource (lib "Database_Libs1") (part "TEST_POINT_1"))
    )
    (comp (ref "TP36")
      (value "TEST_POINT_1")
      (footprint "SMD_TP_100-254")
      (fields
        (field (name "DB_PART_NUMBER") "TPO000000001")
        (field (name "DB_MANUFACTURER_PART") "ISHIDDEN=T")
        (field (name "DB_APPROVED_BY") "ISHIDDEN=T")
      )
      (libsource (lib "Database_Libs1") (part "TEST_POINT_1"))
    )
    (comp (ref "TP37")
      (value "TEST_POINT_1")
      (footprint "SMD_TP_100-254")
      (fields
        (field (name "DB_PART_NUMBER") "TPO000000001")
        (field (name "DB_MANUFACTURER_PART") "ISHIDDEN=T")
        (field (name "DB_APPROVED_BY") "ISHIDDEN=T")
      )
      (libsource (lib "Database_Libs1") (part "TEST_POINT_1"))
    )
    (comp (ref "TP38")
      (value "TEST_POINT_1")
      (footprint "SMD_TP_100-254")
      (fields
        (field (name "DB_PART_NUMBER") "TPO000000001")
        (field (name "DB_MANUFACTURER_PART") "ISHIDDEN=T")
        (field (name "DB_APPROVED_BY") "ISHIDDEN=T")
      )
      (libsource (lib "Database_Libs1") (part "TEST_POINT_1"))
    )
    (comp (ref "TP39")
      (value "TEST_POINT_1")
      (footprint "SMD_TP_100-254")
      (fields
        (field (name "DB_PART_NUMBER") "TPO000000001")
        (field (name "DB_MANUFACTURER_PART") "ISHIDDEN=T")
        (field (name "DB_APPROVED_BY") "ISHIDDEN=T")
      )
      (libsource (lib "Database_Libs1") (part "TEST_POINT_1"))
    )
    (comp (ref "TP40")
      (value "TEST_POINT_1")
      (footprint "SMD_TP_100-254")
      (fields
        (field (name "DB_PART_NUMBER") "TPO000000001")
        (field (name "DB_MANUFACTURER_PART") "ISHIDDEN=T")
        (field (name "DB_APPROVED_BY") "ISHIDDEN=T")
      )
      (libsource (lib "Database_Libs1") (part "TEST_POINT_1"))
    )
    (comp (ref "TP41")
      (value "TEST_POINT_1")
      (footprint "SMD_TP_100-254")
      (fields
        (field (name "DB_PART_NUMBER") "TPO000000001")
        (field (name "DB_MANUFACTURER_PART") "ISHIDDEN=T")
        (field (name "DB_APPROVED_BY") "ISHIDDEN=T")
      )
      (libsource (lib "Database_Libs1") (part "TEST_POINT_1"))
    )
    (comp (ref "TP42")
      (value "TEST_POINT_1")
      (footprint "SMD_TP_100-254")
      (fields
        (field (name "DB_PART_NUMBER") "TPO000000001")
        (field (name "DB_MANUFACTURER_PART") "ISHIDDEN=T")
        (field (name "DB_APPROVED_BY") "ISHIDDEN=T")
      )
      (libsource (lib "Database_Libs1") (part "TEST_POINT_1"))
    )
    (comp (ref "TP43")
      (value "TEST_POINT_1")
      (footprint "SMD_TP_100-254")
      (fields
        (field (name "DB_PART_NUMBER") "TPO000000001")
        (field (name "DB_MANUFACTURER_PART") "ISHIDDEN=T")
        (field (name "DB_APPROVED_BY") "ISHIDDEN=T")
      )
      (libsource (lib "Database_Libs1") (part "TEST_POINT_1"))
    )
    (comp (ref "TP44")
      (value "TEST_POINT_1")
      (footprint "SMD_TP_100-254")
      (fields
        (field (name "DB_PART_NUMBER") "TPO000000001")
        (field (name "DB_MANUFACTURER_PART") "ISHIDDEN=T")
        (field (name "DB_APPROVED_BY") "ISHIDDEN=T")
      )
      (libsource (lib "Database_Libs1") (part "TEST_POINT_1"))
    )
    (comp (ref "TP45")
      (value "TEST_POINT_1")
      (footprint "SMD_TP_100-254")
      (fields
        (field (name "DB_PART_NUMBER") "TPO000000001")
        (field (name "DB_MANUFACTURER_PART") "ISHIDDEN=T")
        (field (name "DB_APPROVED_BY") "ISHIDDEN=T")
      )
      (libsource (lib "Database_Libs1") (part "TEST_POINT_1"))
    )
    (comp (ref "TP46")
      (value "TEST_POINT_1")
      (footprint "SMD_TP_100-254")
      (fields
        (field (name "DB_PART_NUMBER") "TPO000000001")
        (field (name "DB_MANUFACTURER_PART") "ISHIDDEN=T")
        (field (name "DB_APPROVED_BY") "ISHIDDEN=T")
      )
      (libsource (lib "Database_Libs1") (part "TEST_POINT_1"))
    )
    (comp (ref "TP47")
      (value "TEST_POINT_1")
      (footprint "SMD_TP_100-254")
      (fields
        (field (name "DB_PART_NUMBER") "TPO000000001")
        (field (name "DB_MANUFACTURER_PART") "ISHIDDEN=T")
        (field (name "DB_APPROVED_BY") "ISHIDDEN=T")
      )
      (libsource (lib "Database_Libs1") (part "TEST_POINT_1"))
    )
    (comp (ref "TP48")
      (value "TEST_POINT_1")
      (footprint "SMD_TP_100-254")
      (fields
        (field (name "DB_PART_NUMBER") "TPO000000001")
        (field (name "DB_MANUFACTURER_PART") "ISHIDDEN=T")
        (field (name "DB_APPROVED_BY") "ISHIDDEN=T")
      )
      (libsource (lib "Database_Libs1") (part "TEST_POINT_1"))
    )
    (comp (ref "TP49")
      (value "TEST_POINT_1")
      (footprint "SMD_TP_100-254")
      (fields
        (field (name "DB_PART_NUMBER") "TPO000000001")
        (field (name "DB_MANUFACTURER_PART") "ISHIDDEN=T")
        (field (name "DB_APPROVED_BY") "ISHIDDEN=T")
      )
      (libsource (lib "Database_Libs1") (part "TEST_POINT_1"))
    )
    (comp (ref "TP50")
      (value "TEST_POINT_1")
      (footprint "SMD_TP_100-254")
      (fields
        (field (name "DB_PART_NUMBER") "TPO000000001")
        (field (name "DB_MANUFACTURER_PART") "ISHIDDEN=T")
        (field (name "DB_APPROVED_BY") "ISHIDDEN=T")
      )
      (libsource (lib "Database_Libs1") (part "TEST_POINT_1"))
    )
    (comp (ref "TP51")
      (value "TEST_POINT_1")
      (footprint "SMD_TP_100-254")
      (fields
        (field (name "DB_PART_NUMBER") "TPO000000001")
        (field (name "DB_MANUFACTURER_PART") "ISHIDDEN=T")
        (field (name "DB_APPROVED_BY") "ISHIDDEN=T")
      )
      (libsource (lib "Database_Libs1") (part "TEST_POINT_1"))
    )
    (comp (ref "TP52")
      (value "TEST_POINT_1")
      (footprint "SMD_TP_100-254")
      (fields
        (field (name "DB_PART_NUMBER") "TPO000000001")
        (field (name "DB_MANUFACTURER_PART") "ISHIDDEN=T")
        (field (name "DB_APPROVED_BY") "ISHIDDEN=T")
      )
      (libsource (lib "Database_Libs1") (part "TEST_POINT_1"))
    )
    (comp (ref "TP53")
      (value "TEST_POINT_1")
      (footprint "SMD_TP_100-254")
      (fields
        (field (name "DB_PART_NUMBER") "TPO000000001")
        (field (name "DB_MANUFACTURER_PART") "ISHIDDEN=T")
        (field (name "DB_APPROVED_BY") "ISHIDDEN=T")
      )
      (libsource (lib "Database_Libs1") (part "TEST_POINT_1"))
    )
    (comp (ref "TP54")
      (value "TEST_POINT_1")
      (footprint "SMD_TP_100-254")
      (fields
        (field (name "DB_PART_NUMBER") "TPO000000001")
        (field (name "DB_MANUFACTURER_PART") "ISHIDDEN=T")
        (field (name "DB_APPROVED_BY") "ISHIDDEN=T")
      )
      (libsource (lib "Database_Libs1") (part "TEST_POINT_1"))
    )
    (comp (ref "U1")
      (value "IC_LTC4449")
      (footprint "SMD_SON45P300X200X80-9N")
      (fields
        (field (name "DB_PART_NUMBER") "DRV000000079")
        (field (name "DB_VALUE") "LTC4449EDCB#TRPBF")
        (field (name "DB_MANUFACTURER_PART") "LINEAR       LTC4449EDCB#TRPBF")
        (field (name "DB_APPROVED_BY") "VSN")
      )
      (libsource (lib "Database_Libs1") (part "IC_LTC4449"))
    )
    (comp (ref "U2")
      (value "IC_LTC4449")
      (footprint "SMD_SON45P300X200X80-9N")
      (fields
        (field (name "DB_PART_NUMBER") "DRV000000079")
        (field (name "DB_VALUE") "LTC4449EDCB#TRPBF")
        (field (name "DB_MANUFACTURER_PART") "LINEAR       LTC4449EDCB#TRPBF")
        (field (name "DB_APPROVED_BY") "VSN")
      )
      (libsource (lib "Database_Libs1") (part "IC_LTC4449"))
    )
    (comp (ref "U3")
      (value "IC_LTC4449")
      (footprint "SMD_SON45P300X200X80-9N")
      (fields
        (field (name "DB_PART_NUMBER") "DRV000000079")
        (field (name "DB_VALUE") "LTC4449EDCB#TRPBF")
        (field (name "DB_MANUFACTURER_PART") "LINEAR       LTC4449EDCB#TRPBF")
        (field (name "DB_APPROVED_BY") "VSN")
      )
      (libsource (lib "Database_Libs1") (part "IC_LTC4449"))
    )
    (comp (ref "U4")
      (value "GC3355Q64")
      (footprint "SMT_QFN40P800X800X90-65N")
      (description "GridSeed")
      (libsource (lib "altium-import") (part "root_0__*"))
    )
    (comp (ref "U5")
      (value "GC3355Q64")
      (footprint "SMT_QFN40P800X800X90-65N")
      (description "GridSeed")
      (libsource (lib "altium-import") (part "root_0__*"))
    )
    (comp (ref "U6")
      (value "GC3355Q64")
      (footprint "SMT_QFN40P800X800X90-65N")
      (description "GridSeed")
      (libsource (lib "altium-import") (part "root_0__*"))
    )
    (comp (ref "U7")
      (value "GC3355Q64")
      (footprint "SMT_QFN40P800X800X90-65N")
      (description "GridSeed")
      (libsource (lib "altium-import") (part "root_0__*"))
    )
    (comp (ref "U8")
      (value "IC_DSPIC33EP256MU806-QFN64")
      (footprint "SMD_QFP50P1200X1200X120-64N")
      (fields
        (field (name "DB_PART_NUMBER") "MCU000000070")
        (field (name "DB_VALUE") "dsPIC33EP256MU806")
        (field (name "DB_MANUFACTURER_PART") "MICROCHIP        DSPIC33EP256MU806-E/PT")
        (field (name "DB_APPROVED_BY") "VSN")
      )
      (libsource (lib "Database_Libs1") (part "IC_DSPIC33EP256MU806-QFN64"))
    )
    (comp (ref "U9")
      (value "GC3355Q64")
      (footprint "SMT_QFN40P800X800X90-65N")
      (description "GridSeed")
      (libsource (lib "altium-import") (part "root_0__*"))
    )
    (comp (ref "U10")
      (value "GC3355Q64")
      (footprint "SMT_QFN40P800X800X90-65N")
      (description "GridSeed")
      (libsource (lib "altium-import") (part "root_0__*"))
    )
    (comp (ref "U11")
      (value "GC3355Q64")
      (footprint "SMT_QFN40P800X800X90-65N")
      (description "GridSeed")
      (libsource (lib "altium-import") (part "root_0__*"))
    )
    (comp (ref "U12")
      (value "GC3355Q64")
      (footprint "SMT_QFN40P800X800X90-65N")
      (description "GridSeed")
      (libsource (lib "altium-import") (part "root_0__*"))
    )
    (comp (ref "U13")
      (value "(OPT) LM7805")
      (footprint "SMD_SOIC127P600X175-8N")
      (fields
        (field (name "DB_PART_NUMBER") "PSU000000125")
        (field (name "DB_VALUE") "AP78L05SG-13")
        (field (name "DB_MANUFACTURER_PART") "DIODES        AP78L05SG-13")
        (field (name "DB_APPROVED_BY") "VSN")
      )
      (libsource (lib "Database_Libs1") (part "IC_LM2931AD-5.0R2G_SO-8"))
    )
    (comp (ref "U14")
      (value "IC_TLV70033QDDCRQ1")
      (footprint "SMD_SOT95P280X135-5N")
      (fields
        (field (name "DB_PART_NUMBER") "PSU000000126")
        (field (name "DB_VALUE") "BU33TD3WG-TR")
        (field (name "DB_MANUFACTURER_PART") "ROHM     BU33TD3WG-TR")
        (field (name "DB_APPROVED_BY") "VSN")
      )
      (libsource (lib "Database_Libs1") (part "IC_TLV70033QDDCRQ1"))
    )
    (comp (ref "U15")
      (value "IC_BDXXKA5WF")
      (footprint "SMD_SOIC127P620X160-8N")
      (fields
        (field (name "DB_PART_NUMBER") "PSU000000127")
        (field (name "DB_VALUE") "BD33KA5WF-E2")
        (field (name "DB_MANUFACTURER_PART") "ROHM        BD33KA5WF-E2")
        (field (name "DB_APPROVED_BY") "VSN")
      )
      (libsource (lib "Database_Libs1") (part "IC_BDXXKA5WF"))
    )
    (comp (ref "U16")
      (value "IC_IN1OUT3GND4")
      (footprint "SMD_TO254P1542X460-3_4N")
      (fields
        (field (name "DB_PART_NUMBER") "PSU000000129")
        (field (name "DB_VALUE") "L7805CD2T-TR")
        (field (name "DB_MANUFACTURER_PART") "ST       L7805CD2T-TR")
        (field (name "DB_APPROVED_BY") "VSN")
      )
      (libsource (lib "Database_Libs1") (part "IC_IN1OUT3GND4"))
    )
    (comp (ref "U17")
      (value "IC_VIN1GND4VOUT3")
      (footprint "SMD_TO229P991X239-4N_DPAK")
      (fields
        (field (name "DB_PART_NUMBER") "PSU000000031")
        (field (name "DB_VALUE") "MC78M05BDTRKG")
        (field (name "DB_MANUFACTURER_PART") "ON Semiconductor       MC78M05BDTRKG")
        (field (name "DB_APPROVED_BY") "VSN")
      )
      (libsource (lib "Database_Libs1") (part "IC_VIN1GND4VOUT3"))
    )
    (comp (ref "U18")
      (value "GC3355Q64")
      (footprint "SMT_QFN40P800X800X90-65N")
      (description "GridSeed")
      (libsource (lib "altium-import") (part "root_0__*"))
    )
    (comp (ref "U19")
      (value "GC3355Q64")
      (footprint "SMT_QFN40P800X800X90-65N")
      (description "GridSeed")
      (libsource (lib "altium-import") (part "root_0__*"))
    )
    (comp (ref "U20")
      (value "GC3355Q64")
      (footprint "SMT_QFN40P800X800X90-65N")
      (description "GridSeed")
      (libsource (lib "altium-import") (part "root_0__*"))
    )
    (comp (ref "U21")
      (value "GC3355Q64")
      (footprint "SMT_QFN40P800X800X90-65N")
      (description "GridSeed")
      (libsource (lib "altium-import") (part "root_0__*"))
    )
    (comp (ref "U22")
      (value "IC_BD00KA5WF")
      (footprint "SMD_SOIC127P620X160-8N")
      (fields
        (field (name "DB_PART_NUMBER") "PSU000000128")
        (field (name "DB_VALUE") "BD00KA5WF-E2")
        (field (name "DB_MANUFACTURER_PART") "ROHM        BD00KA5WF-E2")
        (field (name "DB_APPROVED_BY") "VSN")
      )
      (libsource (lib "Database_Libs1") (part "IC_BD00KA5WF"))
    )
    (comp (ref "U23")
      (value "IC_BD00KA5WF")
      (footprint "SMD_SOIC127P620X160-8N")
      (fields
        (field (name "DB_PART_NUMBER") "PSU000000128")
        (field (name "DB_VALUE") "BD00KA5WF-E2")
        (field (name "DB_MANUFACTURER_PART") "ROHM        BD00KA5WF-E2")
        (field (name "DB_APPROVED_BY") "VSN")
      )
      (libsource (lib "Database_Libs1") (part "IC_BD00KA5WF"))
    )
    (comp (ref "U24")
      (value "GC3355Q64")
      (footprint "SMT_QFN40P800X800X90-65N")
      (description "GridSeed")
      (libsource (lib "altium-import") (part "root_0__*"))
    )
    (comp (ref "U25")
      (value "GC3355Q64")
      (footprint "SMT_QFN40P800X800X90-65N")
      (description "GridSeed")
      (libsource (lib "altium-import") (part "root_0__*"))
    )
    (comp (ref "U26")
      (value "GC3355Q64")
      (footprint "SMT_QFN40P800X800X90-65N")
      (description "GridSeed")
      (libsource (lib "altium-import") (part "root_0__*"))
    )
    (comp (ref "U27")
      (value "GC3355Q64")
      (footprint "SMT_QFN40P800X800X90-65N")
      (description "GridSeed")
      (libsource (lib "altium-import") (part "root_0__*"))
    )
    (comp (ref "Y1")
      (value "XTAL")
      (footprint "SMD_HC49_XTAL1140X480X420N")
      (fields
        (field (name "DB_PART_NUMBER") "OSC000000012")
        (field (name "DB_VALUE") "4.00MHz HC49/4HSMX")
        (field (name "DB_MANUFACTURER_PART") "IQD       4.00MHz HC49/4HSMX")
        (field (name "DB_APPROVED_BY") "VSN")
      )
      (libsource (lib "Database_Libs1") (part "XTAL"))
    )
  )
  (nets
    (net (code "1") (name "/1V") (class "Default")
      (node (ref "C118") (pin "2") (pinfunction "2_2") (pintype "passive"))
      (node (ref "C119") (pin "2") (pinfunction "2_2") (pintype "passive"))
      (node (ref "C12") (pin "2") (pinfunction "2_2") (pintype "passive"))
      (node (ref "C121") (pin "2") (pinfunction "2_2") (pintype "passive"))
      (node (ref "C123") (pin "2") (pinfunction "2_2") (pintype "passive"))
      (node (ref "C124") (pin "2") (pinfunction "2_2") (pintype "passive"))
      (node (ref "C126") (pin "2") (pinfunction "2_2") (pintype "passive"))
      (node (ref "C128") (pin "2") (pinfunction "2_2") (pintype "passive"))
      (node (ref "C129") (pin "2") (pinfunction "2_2") (pintype "passive"))
      (node (ref "C13") (pin "2") (pinfunction "2_2") (pintype "passive"))
      (node (ref "C131") (pin "2") (pinfunction "2_2") (pintype "passive"))
      (node (ref "C133") (pin "2") (pinfunction "2_2") (pintype "passive"))
      (node (ref "C134") (pin "2") (pinfunction "2_2") (pintype "passive"))
      (node (ref "C136") (pin "2") (pinfunction "2_2") (pintype "passive"))
      (node (ref "C14") (pin "2") (pinfunction "2_2") (pintype "passive"))
      (node (ref "C140") (pin "2") (pinfunction "2_2") (pintype "passive"))
      (node (ref "C141") (pin "2") (pinfunction "2_2") (pintype "passive"))
      (node (ref "C142") (pin "2") (pinfunction "2_2") (pintype "passive"))
      (node (ref "C143") (pin "2") (pinfunction "2_2") (pintype "passive"))
      (node (ref "C144") (pin "2") (pinfunction "2_2") (pintype "passive"))
      (node (ref "C145") (pin "2") (pinfunction "2_2") (pintype "passive"))
      (node (ref "C146") (pin "2") (pinfunction "2_2") (pintype "passive"))
      (node (ref "C147") (pin "2") (pinfunction "2_2") (pintype "passive"))
      (node (ref "C148") (pin "2") (pinfunction "2_2") (pintype "passive"))
      (node (ref "C149") (pin "2") (pinfunction "2_2") (pintype "passive"))
      (node (ref "C150") (pin "2") (pinfunction "2_2") (pintype "passive"))
      (node (ref "C151") (pin "2") (pinfunction "2_2") (pintype "passive"))
      (node (ref "C152") (pin "2") (pinfunction "2_2") (pintype "passive"))
      (node (ref "C153") (pin "2") (pinfunction "2_2") (pintype "passive"))
      (node (ref "C154") (pin "2") (pinfunction "2_2") (pintype "passive"))
      (node (ref "C155") (pin "2") (pinfunction "2_2") (pintype "passive"))
      (node (ref "C156") (pin "2") (pinfunction "2_2") (pintype "passive"))
      (node (ref "C157") (pin "2") (pinfunction "2_2") (pintype "passive"))
      (node (ref "C158") (pin "2") (pinfunction "2_2") (pintype "passive"))
      (node (ref "C159") (pin "2") (pinfunction "2_2") (pintype "passive"))
      (node (ref "C160") (pin "2") (pinfunction "2_2") (pintype "passive"))
      (node (ref "C161") (pin "2") (pinfunction "2_2") (pintype "passive"))
      (node (ref "C162") (pin "2") (pinfunction "2_2") (pintype "passive"))
      (node (ref "C163") (pin "2") (pinfunction "2_2") (pintype "passive"))
      (node (ref "C17") (pin "2") (pinfunction "2_2") (pintype "passive"))
      (node (ref "C175") (pin "2") (pinfunction "2_2") (pintype "passive"))
      (node (ref "C176") (pin "2") (pinfunction "2_2") (pintype "passive"))
      (node (ref "C177") (pin "2") (pinfunction "2_2") (pintype "passive"))
      (node (ref "C179") (pin "2") (pinfunction "2_2") (pintype "passive"))
      (node (ref "C18") (pin "2") (pinfunction "2_2") (pintype "passive"))
      (node (ref "C180") (pin "2") (pinfunction "2_2") (pintype "passive"))
      (node (ref "C181") (pin "2") (pinfunction "2_2") (pintype "passive"))
      (node (ref "C183") (pin "2") (pinfunction "2_2") (pintype "passive"))
      (node (ref "C184") (pin "2") (pinfunction "2_2") (pintype "passive"))
      (node (ref "C185") (pin "2") (pinfunction "2_2") (pintype "passive"))
      (node (ref "C187") (pin "2") (pinfunction "2_2") (pintype "passive"))
      (node (ref "C188") (pin "2") (pinfunction "2_2") (pintype "passive"))
      (node (ref "C189") (pin "2") (pinfunction "2_2") (pintype "passive"))
      (node (ref "C19") (pin "2") (pinfunction "2_2") (pintype "passive"))
      (node (ref "C22") (pin "2") (pinfunction "2_2") (pintype "passive"))
      (node (ref "C227") (pin "2") (pinfunction "2_2") (pintype "passive"))
      (node (ref "C228") (pin "2") (pinfunction "2_2") (pintype "passive"))
      (node (ref "C23") (pin "2") (pinfunction "2_2") (pintype "passive"))
      (node (ref "C230") (pin "2") (pinfunction "2_2") (pintype "passive"))
      (node (ref "C232") (pin "2") (pinfunction "2_2") (pintype "passive"))
      (node (ref "C233") (pin "2") (pinfunction "2_2") (pintype "passive"))
      (node (ref "C235") (pin "2") (pinfunction "2_2") (pintype "passive"))
      (node (ref "C237") (pin "2") (pinfunction "2_2") (pintype "passive"))
      (node (ref "C238") (pin "2") (pinfunction "2_2") (pintype "passive"))
      (node (ref "C24") (pin "2") (pinfunction "2_2") (pintype "passive"))
      (node (ref "C240") (pin "2") (pinfunction "2_2") (pintype "passive"))
      (node (ref "C242") (pin "2") (pinfunction "2_2") (pintype "passive"))
      (node (ref "C243") (pin "2") (pinfunction "2_2") (pintype "passive"))
      (node (ref "C245") (pin "2") (pinfunction "2_2") (pintype "passive"))
      (node (ref "C247") (pin "2") (pinfunction "2_2") (pintype "passive"))
      (node (ref "C248") (pin "2") (pinfunction "2_2") (pintype "passive"))
      (node (ref "C249") (pin "2") (pinfunction "2_2") (pintype "passive"))
      (node (ref "C25") (pin "2") (pinfunction "2_2") (pintype "passive"))
      (node (ref "C250") (pin "2") (pinfunction "2_2") (pintype "passive"))
      (node (ref "C251") (pin "2") (pinfunction "2_2") (pintype "passive"))
      (node (ref "C252") (pin "2") (pinfunction "2_2") (pintype "passive"))
      (node (ref "C253") (pin "2") (pinfunction "2_2") (pintype "passive"))
      (node (ref "C254") (pin "2") (pinfunction "2_2") (pintype "passive"))
      (node (ref "C255") (pin "2") (pinfunction "2_2") (pintype "passive"))
      (node (ref "C256") (pin "2") (pinfunction "2_2") (pintype "passive"))
      (node (ref "C257") (pin "2") (pinfunction "2_2") (pintype "passive"))
      (node (ref "C258") (pin "2") (pinfunction "2_2") (pintype "passive"))
      (node (ref "C26") (pin "2") (pinfunction "2_2") (pintype "passive"))
      (node (ref "C262") (pin "2") (pinfunction "2_2") (pintype "passive"))
      (node (ref "C263") (pin "2") (pinfunction "2_2") (pintype "passive"))
      (node (ref "C264") (pin "2") (pinfunction "2_2") (pintype "passive"))
      (node (ref "C265") (pin "2") (pinfunction "2_2") (pintype "passive"))
      (node (ref "C266") (pin "2") (pinfunction "2_2") (pintype "passive"))
      (node (ref "C267") (pin "2") (pinfunction "2_2") (pintype "passive"))
      (node (ref "C268") (pin "2") (pinfunction "2_2") (pintype "passive"))
      (node (ref "C269") (pin "2") (pinfunction "2_2") (pintype "passive"))
      (node (ref "C270") (pin "2") (pinfunction "2_2") (pintype "passive"))
      (node (ref "C271") (pin "2") (pinfunction "2_2") (pintype "passive"))
      (node (ref "C272") (pin "2") (pinfunction "2_2") (pintype "passive"))
      (node (ref "C273") (pin "2") (pinfunction "2_2") (pintype "passive"))
      (node (ref "C276") (pin "2") (pinfunction "2_2") (pintype "passive"))
      (node (ref "C277") (pin "2") (pinfunction "2_2") (pintype "passive"))
      (node (ref "C278") (pin "2") (pinfunction "2_2") (pintype "passive"))
      (node (ref "C28") (pin "2") (pinfunction "2_2") (pintype "passive"))
      (node (ref "C280") (pin "2") (pinfunction "2_2") (pintype "passive"))
      (node (ref "C281") (pin "2") (pinfunction "2_2") (pintype "passive"))
      (node (ref "C282") (pin "2") (pinfunction "2_2") (pintype "passive"))
      (node (ref "C284") (pin "2") (pinfunction "2_2") (pintype "passive"))
      (node (ref "C285") (pin "2") (pinfunction "2_2") (pintype "passive"))
      (node (ref "C286") (pin "2") (pinfunction "2_2") (pintype "passive"))
      (node (ref "C288") (pin "2") (pinfunction "2_2") (pintype "passive"))
      (node (ref "C289") (pin "2") (pinfunction "2_2") (pintype "passive"))
      (node (ref "C290") (pin "2") (pinfunction "2_2") (pintype "passive"))
      (node (ref "C30") (pin "2") (pinfunction "2_2") (pintype "passive"))
      (node (ref "C31") (pin "2") (pinfunction "2_2") (pintype "passive"))
      (node (ref "C324") (pin "2") (pinfunction "2_2") (pintype "passive"))
      (node (ref "C325") (pin "2") (pinfunction "2_2") (pintype "passive"))
      (node (ref "C327") (pin "2") (pinfunction "2_2") (pintype "passive"))
      (node (ref "C329") (pin "2") (pinfunction "2_2") (pintype "passive"))
      (node (ref "C33") (pin "2") (pinfunction "2_2") (pintype "passive"))
      (node (ref "C330") (pin "2") (pinfunction "2_2") (pintype "passive"))
      (node (ref "C332") (pin "2") (pinfunction "2_2") (pintype "passive"))
      (node (ref "C334") (pin "2") (pinfunction "2_2") (pintype "passive"))
      (node (ref "C335") (pin "2") (pinfunction "2_2") (pintype "passive"))
      (node (ref "C337") (pin "2") (pinfunction "2_2") (pintype "passive"))
      (node (ref "C339") (pin "2") (pinfunction "2_2") (pintype "passive"))
      (node (ref "C340") (pin "2") (pinfunction "2_2") (pintype "passive"))
      (node (ref "C342") (pin "2") (pinfunction "2_2") (pintype "passive"))
      (node (ref "C344") (pin "2") (pinfunction "2_2") (pintype "passive"))
      (node (ref "C345") (pin "2") (pinfunction "2_2") (pintype "passive"))
      (node (ref "C346") (pin "2") (pinfunction "2_2") (pintype "passive"))
      (node (ref "C347") (pin "2") (pinfunction "2_2") (pintype "passive"))
      (node (ref "C348") (pin "2") (pinfunction "2_2") (pintype "passive"))
      (node (ref "C349") (pin "2") (pinfunction "2_2") (pintype "passive"))
      (node (ref "C35") (pin "2") (pinfunction "2_2") (pintype "passive"))
      (node (ref "C350") (pin "2") (pinfunction "2_2") (pintype "passive"))
      (node (ref "C351") (pin "2") (pinfunction "2_2") (pintype "passive"))
      (node (ref "C352") (pin "2") (pinfunction "2_2") (pintype "passive"))
      (node (ref "C353") (pin "2") (pinfunction "2_2") (pintype "passive"))
      (node (ref "C354") (pin "2") (pinfunction "2_2") (pintype "passive"))
      (node (ref "C355") (pin "2") (pinfunction "2_2") (pintype "passive"))
      (node (ref "C356") (pin "2") (pinfunction "2_2") (pintype "passive"))
      (node (ref "C357") (pin "2") (pinfunction "2_2") (pintype "passive"))
      (node (ref "C358") (pin "2") (pinfunction "2_2") (pintype "passive"))
      (node (ref "C359") (pin "2") (pinfunction "2_2") (pintype "passive"))
      (node (ref "C36") (pin "2") (pinfunction "2_2") (pintype "passive"))
      (node (ref "C360") (pin "2") (pinfunction "2_2") (pintype "passive"))
      (node (ref "C361") (pin "2") (pinfunction "2_2") (pintype "passive"))
      (node (ref "C362") (pin "2") (pinfunction "2_2") (pintype "passive"))
      (node (ref "C363") (pin "2") (pinfunction "2_2") (pintype "passive"))
      (node (ref "C364") (pin "2") (pinfunction "2_2") (pintype "passive"))
      (node (ref "C365") (pin "2") (pinfunction "2_2") (pintype "passive"))
      (node (ref "C366") (pin "2") (pinfunction "2_2") (pintype "passive"))
      (node (ref "C367") (pin "2") (pinfunction "2_2") (pintype "passive"))
      (node (ref "C368") (pin "2") (pinfunction "2_2") (pintype "passive"))
      (node (ref "C369") (pin "2") (pinfunction "2_2") (pintype "passive"))
      (node (ref "C370") (pin "2") (pinfunction "2_2") (pintype "passive"))
      (node (ref "C372") (pin "2") (pinfunction "2_2") (pintype "passive"))
      (node (ref "C373") (pin "2") (pinfunction "2_2") (pintype "passive"))
      (node (ref "C374") (pin "2") (pinfunction "2_2") (pintype "passive"))
      (node (ref "C376") (pin "2") (pinfunction "2_2") (pintype "passive"))
      (node (ref "C377") (pin "2") (pinfunction "2_2") (pintype "passive"))
      (node (ref "C378") (pin "2") (pinfunction "2_2") (pintype "passive"))
      (node (ref "C38") (pin "2") (pinfunction "2_2") (pintype "passive"))
      (node (ref "C380") (pin "2") (pinfunction "2_2") (pintype "passive"))
      (node (ref "C381") (pin "2") (pinfunction "2_2") (pintype "passive"))
      (node (ref "C382") (pin "2") (pinfunction "2_2") (pintype "passive"))
      (node (ref "C40") (pin "2") (pinfunction "2_2") (pintype "passive"))
      (node (ref "C41") (pin "2") (pinfunction "2_2") (pintype "passive"))
      (node (ref "C43") (pin "2") (pinfunction "2_2") (pintype "passive"))
      (node (ref "C45") (pin "2") (pinfunction "2_2") (pintype "passive"))
      (node (ref "C46") (pin "2") (pinfunction "2_2") (pintype "passive"))
      (node (ref "C47") (pin "2") (pinfunction "2_2") (pintype "passive"))
      (node (ref "C48") (pin "2") (pinfunction "2_2") (pintype "passive"))
      (node (ref "C49") (pin "2") (pinfunction "2_2") (pintype "passive"))
      (node (ref "C50") (pin "2") (pinfunction "2_2") (pintype "passive"))
      (node (ref "C51") (pin "2") (pinfunction "2_2") (pintype "passive"))
      (node (ref "C52") (pin "2") (pinfunction "2_2") (pintype "passive"))
      (node (ref "C53") (pin "2") (pinfunction "2_2") (pintype "passive"))
      (node (ref "C54") (pin "2") (pinfunction "2_2") (pintype "passive"))
      (node (ref "C55") (pin "2") (pinfunction "2_2") (pintype "passive"))
      (node (ref "C56") (pin "2") (pinfunction "2_2") (pintype "passive"))
      (node (ref "C57") (pin "2") (pinfunction "2_2") (pintype "passive"))
      (node (ref "C58") (pin "2") (pinfunction "2_2") (pintype "passive"))
      (node (ref "C59") (pin "2") (pinfunction "2_2") (pintype "passive"))
      (node (ref "C60") (pin "2") (pinfunction "2_2") (pintype "passive"))
      (node (ref "C61") (pin "2") (pinfunction "2_2") (pintype "passive"))
      (node (ref "C62") (pin "2") (pinfunction "2_2") (pintype "passive"))
      (node (ref "C63") (pin "2") (pinfunction "2_2") (pintype "passive"))
      (node (ref "C64") (pin "2") (pinfunction "2_2") (pintype "passive"))
      (node (ref "C65") (pin "2") (pinfunction "2_2") (pintype "passive"))
      (node (ref "C66") (pin "2") (pinfunction "2_2") (pintype "passive"))
      (node (ref "C67") (pin "2") (pinfunction "2_2") (pintype "passive"))
      (node (ref "C68") (pin "2") (pinfunction "2_2") (pintype "passive"))
      (node (ref "C70") (pin "2") (pinfunction "2_2") (pintype "passive"))
      (node (ref "C71") (pin "2") (pinfunction "2_2") (pintype "passive"))
      (node (ref "C72") (pin "2") (pinfunction "2_2") (pintype "passive"))
      (node (ref "C74") (pin "2") (pinfunction "2_2") (pintype "passive"))
      (node (ref "C75") (pin "2") (pinfunction "2_2") (pintype "passive"))
      (node (ref "C76") (pin "2") (pinfunction "2_2") (pintype "passive"))
      (node (ref "C78") (pin "2") (pinfunction "2_2") (pintype "passive"))
      (node (ref "C79") (pin "2") (pinfunction "2_2") (pintype "passive"))
      (node (ref "C80") (pin "2") (pinfunction "2_2") (pintype "passive"))
      (node (ref "C82") (pin "2") (pinfunction "2_2") (pintype "passive"))
      (node (ref "C83") (pin "2") (pinfunction "2_2") (pintype "passive"))
      (node (ref "C84") (pin "2") (pinfunction "2_2") (pintype "passive"))
      (node (ref "C_1") (pin "1") (pinfunction "1_1") (pintype "passive"))
      (node (ref "C_10") (pin "1") (pinfunction "1_1") (pintype "passive"))
      (node (ref "C_11") (pin "1") (pinfunction "1_1") (pintype "passive"))
      (node (ref "C_12") (pin "1") (pinfunction "1_1") (pintype "passive"))
      (node (ref "C_13") (pin "1") (pinfunction "1_1") (pintype "passive"))
      (node (ref "C_14") (pin "1") (pinfunction "1_1") (pintype "passive"))
      (node (ref "C_15") (pin "1") (pinfunction "1_1") (pintype "passive"))
      (node (ref "C_16") (pin "1") (pinfunction "1_1") (pintype "passive"))
      (node (ref "C_17") (pin "1") (pinfunction "1_1") (pintype "passive"))
      (node (ref "C_18") (pin "1") (pinfunction "1_1") (pintype "passive"))
      (node (ref "C_19") (pin "1") (pinfunction "1_1") (pintype "passive"))
      (node (ref "C_2") (pin "1") (pinfunction "1_1") (pintype "passive"))
      (node (ref "C_20") (pin "1") (pinfunction "1_1") (pintype "passive"))
      (node (ref "C_21") (pin "1") (pinfunction "1_1") (pintype "passive"))
      (node (ref "C_22") (pin "1") (pinfunction "1_1") (pintype "passive"))
      (node (ref "C_23") (pin "1") (pinfunction "1_1") (pintype "passive"))
      (node (ref "C_24") (pin "1") (pinfunction "1_1") (pintype "passive"))
      (node (ref "C_25") (pin "1") (pinfunction "1_1") (pintype "passive"))
      (node (ref "C_26") (pin "1") (pinfunction "1_1") (pintype "passive"))
      (node (ref "C_27") (pin "1") (pinfunction "1_1") (pintype "passive"))
      (node (ref "C_28") (pin "1") (pinfunction "1_1") (pintype "passive"))
      (node (ref "C_29") (pin "1") (pinfunction "1_1") (pintype "passive"))
      (node (ref "C_3") (pin "1") (pinfunction "1_1") (pintype "passive"))
      (node (ref "C_30") (pin "1") (pinfunction "1_1") (pintype "passive"))
      (node (ref "C_33") (pin "1") (pinfunction "1_1") (pintype "passive"))
      (node (ref "C_34") (pin "1") (pinfunction "1_1") (pintype "passive"))
      (node (ref "C_35") (pin "1") (pinfunction "1_1") (pintype "passive"))
      (node (ref "C_36") (pin "1") (pinfunction "1_1") (pintype "passive"))
      (node (ref "C_37") (pin "1") (pinfunction "1_1") (pintype "passive"))
      (node (ref "C_38") (pin "1") (pinfunction "1_1") (pintype "passive"))
      (node (ref "C_39") (pin "1") (pinfunction "1_1") (pintype "passive"))
      (node (ref "C_4") (pin "1") (pinfunction "1_1") (pintype "passive"))
      (node (ref "C_40") (pin "1") (pinfunction "1_1") (pintype "passive"))
      (node (ref "C_41") (pin "1") (pinfunction "1_1") (pintype "passive"))
      (node (ref "C_42") (pin "1") (pinfunction "1_1") (pintype "passive"))
      (node (ref "C_43") (pin "1") (pinfunction "1_1") (pintype "passive"))
      (node (ref "C_44") (pin "1") (pinfunction "1_1") (pintype "passive"))
      (node (ref "C_45") (pin "1") (pinfunction "1_1") (pintype "passive"))
      (node (ref "C_46") (pin "1") (pinfunction "1_1") (pintype "passive"))
      (node (ref "C_47") (pin "1") (pinfunction "1_1") (pintype "passive"))
      (node (ref "C_48") (pin "1") (pinfunction "1_1") (pintype "passive"))
      (node (ref "C_49") (pin "1") (pinfunction "1_1") (pintype "passive"))
      (node (ref "C_5") (pin "1") (pinfunction "1_1") (pintype "passive"))
      (node (ref "C_50") (pin "1") (pinfunction "1_1") (pintype "passive"))
      (node (ref "C_51") (pin "1") (pinfunction "1_1") (pintype "passive"))
      (node (ref "C_52") (pin "1") (pinfunction "1_1") (pintype "passive"))
      (node (ref "C_53") (pin "1") (pinfunction "1_1") (pintype "passive"))
      (node (ref "C_54") (pin "1") (pinfunction "1_1") (pintype "passive"))
      (node (ref "C_55") (pin "1") (pinfunction "1_1") (pintype "passive"))
      (node (ref "C_56") (pin "1") (pinfunction "1_1") (pintype "passive"))
      (node (ref "C_57") (pin "1") (pinfunction "1_1") (pintype "passive"))
      (node (ref "C_58") (pin "1") (pinfunction "1_1") (pintype "passive"))
      (node (ref "C_59") (pin "1") (pinfunction "1_1") (pintype "passive"))
      (node (ref "C_6") (pin "1") (pinfunction "1_1") (pintype "passive"))
      (node (ref "C_60") (pin "1") (pinfunction "1_1") (pintype "passive"))
      (node (ref "C_61") (pin "1") (pinfunction "1_1") (pintype "passive"))
      (node (ref "C_62") (pin "1") (pinfunction "1_1") (pintype "passive"))
      (node (ref "C_63") (pin "1") (pinfunction "1_1") (pintype "passive"))
      (node (ref "C_64") (pin "1") (pinfunction "1_1") (pintype "passive"))
      (node (ref "C_65") (pin "1") (pinfunction "1_1") (pintype "passive"))
      (node (ref "C_66") (pin "1") (pinfunction "1_1") (pintype "passive"))
      (node (ref "C_67") (pin "1") (pinfunction "1_1") (pintype "passive"))
      (node (ref "C_68") (pin "1") (pinfunction "1_1") (pintype "passive"))
      (node (ref "C_69") (pin "1") (pinfunction "1_1") (pintype "passive"))
      (node (ref "C_70") (pin "1") (pinfunction "1_1") (pintype "passive"))
      (node (ref "C_71") (pin "1") (pinfunction "1_1") (pintype "passive"))
      (node (ref "C_72") (pin "1") (pinfunction "1_1") (pintype "passive"))
      (node (ref "C_8") (pin "1") (pinfunction "1_1") (pintype "passive"))
      (node (ref "C_9") (pin "1") (pinfunction "1_1") (pintype "passive"))
      (node (ref "L1") (pin "2") (pinfunction "2_2") (pintype "passive"))
      (node (ref "L2") (pin "2") (pinfunction "2_2") (pintype "passive"))
      (node (ref "L3") (pin "2") (pinfunction "2_2") (pintype "passive"))
      (node (ref "R26") (pin "2") (pinfunction "2_2") (pintype "passive"))
      (node (ref "U10") (pin "13") (pinfunction "DVDD_13") (pintype "passive"))
      (node (ref "U10") (pin "14") (pinfunction "DVDD_14") (pintype "passive"))
      (node (ref "U10") (pin "19") (pinfunction "DVDD_19") (pintype "passive"))
      (node (ref "U10") (pin "20") (pinfunction "DVDD_20") (pintype "passive"))
      (node (ref "U10") (pin "21") (pinfunction "DVDD_21") (pintype "passive"))
      (node (ref "U10") (pin "22") (pinfunction "DVDD_22") (pintype "passive"))
      (node (ref "U10") (pin "26") (pinfunction "DVDD_26") (pintype "passive"))
      (node (ref "U10") (pin "27") (pinfunction "DVDD_27") (pintype "passive"))
      (node (ref "U10") (pin "29") (pinfunction "DVDD_29") (pintype "passive"))
      (node (ref "U10") (pin "3") (pinfunction "DVDD_3") (pintype "passive"))
      (node (ref "U10") (pin "30") (pinfunction "DVDD_30") (pintype "passive"))
      (node (ref "U10") (pin "34") (pinfunction "DVDD_34") (pintype "passive"))
      (node (ref "U10") (pin "35") (pinfunction "DVDD_35") (pintype "passive"))
      (node (ref "U10") (pin "37") (pinfunction "DVDD_37") (pintype "passive"))
      (node (ref "U10") (pin "38") (pinfunction "DVDD_38") (pintype "passive"))
      (node (ref "U10") (pin "39") (pinfunction "DVDD_39") (pintype "passive"))
      (node (ref "U10") (pin "4") (pinfunction "DVDD_4") (pintype "passive"))
      (node (ref "U10") (pin "41") (pinfunction "DVDD_41") (pintype "passive"))
      (node (ref "U10") (pin "42") (pinfunction "DVDD_42") (pintype "passive"))
      (node (ref "U10") (pin "43") (pinfunction "DVDD_43") (pintype "passive"))
      (node (ref "U10") (pin "45") (pinfunction "DVDD_45") (pintype "passive"))
      (node (ref "U10") (pin "46") (pinfunction "DVDD_46") (pintype "passive"))
      (node (ref "U10") (pin "5") (pinfunction "DVDD_5") (pintype "passive"))
      (node (ref "U10") (pin "51") (pinfunction "DVDD_51") (pintype "passive"))
      (node (ref "U10") (pin "52") (pinfunction "DVDD_52") (pintype "passive"))
      (node (ref "U10") (pin "54") (pinfunction "DVDD_54") (pintype "passive"))
      (node (ref "U10") (pin "55") (pinfunction "DVDD_55") (pintype "passive"))
      (node (ref "U10") (pin "58") (pinfunction "DVDD_58") (pintype "passive"))
      (node (ref "U10") (pin "59") (pinfunction "DVDD_59") (pintype "passive"))
      (node (ref "U10") (pin "6") (pinfunction "DVDD_6") (pintype "passive"))
      (node (ref "U10") (pin "60") (pinfunction "DVDD_60") (pintype "passive"))
      (node (ref "U10") (pin "62") (pinfunction "DVDD_62") (pintype "passive"))
      (node (ref "U10") (pin "63") (pinfunction "DVDD_63") (pintype "passive"))
      (node (ref "U11") (pin "13") (pinfunction "DVDD_13") (pintype "passive"))
      (node (ref "U11") (pin "14") (pinfunction "DVDD_14") (pintype "passive"))
      (node (ref "U11") (pin "19") (pinfunction "DVDD_19") (pintype "passive"))
      (node (ref "U11") (pin "20") (pinfunction "DVDD_20") (pintype "passive"))
      (node (ref "U11") (pin "21") (pinfunction "DVDD_21") (pintype "passive"))
      (node (ref "U11") (pin "22") (pinfunction "DVDD_22") (pintype "passive"))
      (node (ref "U11") (pin "26") (pinfunction "DVDD_26") (pintype "passive"))
      (node (ref "U11") (pin "27") (pinfunction "DVDD_27") (pintype "passive"))
      (node (ref "U11") (pin "29") (pinfunction "DVDD_29") (pintype "passive"))
      (node (ref "U11") (pin "3") (pinfunction "DVDD_3") (pintype "passive"))
      (node (ref "U11") (pin "30") (pinfunction "DVDD_30") (pintype "passive"))
      (node (ref "U11") (pin "34") (pinfunction "DVDD_34") (pintype "passive"))
      (node (ref "U11") (pin "35") (pinfunction "DVDD_35") (pintype "passive"))
      (node (ref "U11") (pin "37") (pinfunction "DVDD_37") (pintype "passive"))
      (node (ref "U11") (pin "38") (pinfunction "DVDD_38") (pintype "passive"))
      (node (ref "U11") (pin "39") (pinfunction "DVDD_39") (pintype "passive"))
      (node (ref "U11") (pin "4") (pinfunction "DVDD_4") (pintype "passive"))
      (node (ref "U11") (pin "41") (pinfunction "DVDD_41") (pintype "passive"))
      (node (ref "U11") (pin "42") (pinfunction "DVDD_42") (pintype "passive"))
      (node (ref "U11") (pin "43") (pinfunction "DVDD_43") (pintype "passive"))
      (node (ref "U11") (pin "45") (pinfunction "DVDD_45") (pintype "passive"))
      (node (ref "U11") (pin "46") (pinfunction "DVDD_46") (pintype "passive"))
      (node (ref "U11") (pin "5") (pinfunction "DVDD_5") (pintype "passive"))
      (node (ref "U11") (pin "51") (pinfunction "DVDD_51") (pintype "passive"))
      (node (ref "U11") (pin "52") (pinfunction "DVDD_52") (pintype "passive"))
      (node (ref "U11") (pin "54") (pinfunction "DVDD_54") (pintype "passive"))
      (node (ref "U11") (pin "55") (pinfunction "DVDD_55") (pintype "passive"))
      (node (ref "U11") (pin "58") (pinfunction "DVDD_58") (pintype "passive"))
      (node (ref "U11") (pin "59") (pinfunction "DVDD_59") (pintype "passive"))
      (node (ref "U11") (pin "6") (pinfunction "DVDD_6") (pintype "passive"))
      (node (ref "U11") (pin "60") (pinfunction "DVDD_60") (pintype "passive"))
      (node (ref "U11") (pin "62") (pinfunction "DVDD_62") (pintype "passive"))
      (node (ref "U11") (pin "63") (pinfunction "DVDD_63") (pintype "passive"))
      (node (ref "U12") (pin "13") (pinfunction "DVDD_13") (pintype "passive"))
      (node (ref "U12") (pin "14") (pinfunction "DVDD_14") (pintype "passive"))
      (node (ref "U12") (pin "19") (pinfunction "DVDD_19") (pintype "passive"))
      (node (ref "U12") (pin "20") (pinfunction "DVDD_20") (pintype "passive"))
      (node (ref "U12") (pin "21") (pinfunction "DVDD_21") (pintype "passive"))
      (node (ref "U12") (pin "22") (pinfunction "DVDD_22") (pintype "passive"))
      (node (ref "U12") (pin "26") (pinfunction "DVDD_26") (pintype "passive"))
      (node (ref "U12") (pin "27") (pinfunction "DVDD_27") (pintype "passive"))
      (node (ref "U12") (pin "29") (pinfunction "DVDD_29") (pintype "passive"))
      (node (ref "U12") (pin "3") (pinfunction "DVDD_3") (pintype "passive"))
      (node (ref "U12") (pin "30") (pinfunction "DVDD_30") (pintype "passive"))
      (node (ref "U12") (pin "34") (pinfunction "DVDD_34") (pintype "passive"))
      (node (ref "U12") (pin "35") (pinfunction "DVDD_35") (pintype "passive"))
      (node (ref "U12") (pin "37") (pinfunction "DVDD_37") (pintype "passive"))
      (node (ref "U12") (pin "38") (pinfunction "DVDD_38") (pintype "passive"))
      (node (ref "U12") (pin "39") (pinfunction "DVDD_39") (pintype "passive"))
      (node (ref "U12") (pin "4") (pinfunction "DVDD_4") (pintype "passive"))
      (node (ref "U12") (pin "41") (pinfunction "DVDD_41") (pintype "passive"))
      (node (ref "U12") (pin "42") (pinfunction "DVDD_42") (pintype "passive"))
      (node (ref "U12") (pin "43") (pinfunction "DVDD_43") (pintype "passive"))
      (node (ref "U12") (pin "45") (pinfunction "DVDD_45") (pintype "passive"))
      (node (ref "U12") (pin "46") (pinfunction "DVDD_46") (pintype "passive"))
      (node (ref "U12") (pin "5") (pinfunction "DVDD_5") (pintype "passive"))
      (node (ref "U12") (pin "51") (pinfunction "DVDD_51") (pintype "passive"))
      (node (ref "U12") (pin "52") (pinfunction "DVDD_52") (pintype "passive"))
      (node (ref "U12") (pin "54") (pinfunction "DVDD_54") (pintype "passive"))
      (node (ref "U12") (pin "55") (pinfunction "DVDD_55") (pintype "passive"))
      (node (ref "U12") (pin "58") (pinfunction "DVDD_58") (pintype "passive"))
      (node (ref "U12") (pin "59") (pinfunction "DVDD_59") (pintype "passive"))
      (node (ref "U12") (pin "6") (pinfunction "DVDD_6") (pintype "passive"))
      (node (ref "U12") (pin "60") (pinfunction "DVDD_60") (pintype "passive"))
      (node (ref "U12") (pin "62") (pinfunction "DVDD_62") (pintype "passive"))
      (node (ref "U12") (pin "63") (pinfunction "DVDD_63") (pintype "passive"))
      (node (ref "U18") (pin "13") (pinfunction "DVDD_13") (pintype "passive"))
      (node (ref "U18") (pin "14") (pinfunction "DVDD_14") (pintype "passive"))
      (node (ref "U18") (pin "19") (pinfunction "DVDD_19") (pintype "passive"))
      (node (ref "U18") (pin "20") (pinfunction "DVDD_20") (pintype "passive"))
      (node (ref "U18") (pin "21") (pinfunction "DVDD_21") (pintype "passive"))
      (node (ref "U18") (pin "22") (pinfunction "DVDD_22") (pintype "passive"))
      (node (ref "U18") (pin "26") (pinfunction "DVDD_26") (pintype "passive"))
      (node (ref "U18") (pin "27") (pinfunction "DVDD_27") (pintype "passive"))
      (node (ref "U18") (pin "29") (pinfunction "DVDD_29") (pintype "passive"))
      (node (ref "U18") (pin "3") (pinfunction "DVDD_3") (pintype "passive"))
      (node (ref "U18") (pin "30") (pinfunction "DVDD_30") (pintype "passive"))
      (node (ref "U18") (pin "34") (pinfunction "DVDD_34") (pintype "passive"))
      (node (ref "U18") (pin "35") (pinfunction "DVDD_35") (pintype "passive"))
      (node (ref "U18") (pin "37") (pinfunction "DVDD_37") (pintype "passive"))
      (node (ref "U18") (pin "38") (pinfunction "DVDD_38") (pintype "passive"))
      (node (ref "U18") (pin "39") (pinfunction "DVDD_39") (pintype "passive"))
      (node (ref "U18") (pin "4") (pinfunction "DVDD_4") (pintype "passive"))
      (node (ref "U18") (pin "41") (pinfunction "DVDD_41") (pintype "passive"))
      (node (ref "U18") (pin "42") (pinfunction "DVDD_42") (pintype "passive"))
      (node (ref "U18") (pin "43") (pinfunction "DVDD_43") (pintype "passive"))
      (node (ref "U18") (pin "45") (pinfunction "DVDD_45") (pintype "passive"))
      (node (ref "U18") (pin "46") (pinfunction "DVDD_46") (pintype "passive"))
      (node (ref "U18") (pin "5") (pinfunction "DVDD_5") (pintype "passive"))
      (node (ref "U18") (pin "51") (pinfunction "DVDD_51") (pintype "passive"))
      (node (ref "U18") (pin "52") (pinfunction "DVDD_52") (pintype "passive"))
      (node (ref "U18") (pin "54") (pinfunction "DVDD_54") (pintype "passive"))
      (node (ref "U18") (pin "55") (pinfunction "DVDD_55") (pintype "passive"))
      (node (ref "U18") (pin "58") (pinfunction "DVDD_58") (pintype "passive"))
      (node (ref "U18") (pin "59") (pinfunction "DVDD_59") (pintype "passive"))
      (node (ref "U18") (pin "6") (pinfunction "DVDD_6") (pintype "passive"))
      (node (ref "U18") (pin "60") (pinfunction "DVDD_60") (pintype "passive"))
      (node (ref "U18") (pin "62") (pinfunction "DVDD_62") (pintype "passive"))
      (node (ref "U18") (pin "63") (pinfunction "DVDD_63") (pintype "passive"))
      (node (ref "U19") (pin "13") (pinfunction "DVDD_13") (pintype "passive"))
      (node (ref "U19") (pin "14") (pinfunction "DVDD_14") (pintype "passive"))
      (node (ref "U19") (pin "19") (pinfunction "DVDD_19") (pintype "passive"))
      (node (ref "U19") (pin "20") (pinfunction "DVDD_20") (pintype "passive"))
      (node (ref "U19") (pin "21") (pinfunction "DVDD_21") (pintype "passive"))
      (node (ref "U19") (pin "22") (pinfunction "DVDD_22") (pintype "passive"))
      (node (ref "U19") (pin "26") (pinfunction "DVDD_26") (pintype "passive"))
      (node (ref "U19") (pin "27") (pinfunction "DVDD_27") (pintype "passive"))
      (node (ref "U19") (pin "29") (pinfunction "DVDD_29") (pintype "passive"))
      (node (ref "U19") (pin "3") (pinfunction "DVDD_3") (pintype "passive"))
      (node (ref "U19") (pin "30") (pinfunction "DVDD_30") (pintype "passive"))
      (node (ref "U19") (pin "34") (pinfunction "DVDD_34") (pintype "passive"))
      (node (ref "U19") (pin "35") (pinfunction "DVDD_35") (pintype "passive"))
      (node (ref "U19") (pin "37") (pinfunction "DVDD_37") (pintype "passive"))
      (node (ref "U19") (pin "38") (pinfunction "DVDD_38") (pintype "passive"))
      (node (ref "U19") (pin "39") (pinfunction "DVDD_39") (pintype "passive"))
      (node (ref "U19") (pin "4") (pinfunction "DVDD_4") (pintype "passive"))
      (node (ref "U19") (pin "41") (pinfunction "DVDD_41") (pintype "passive"))
      (node (ref "U19") (pin "42") (pinfunction "DVDD_42") (pintype "passive"))
      (node (ref "U19") (pin "43") (pinfunction "DVDD_43") (pintype "passive"))
      (node (ref "U19") (pin "45") (pinfunction "DVDD_45") (pintype "passive"))
      (node (ref "U19") (pin "46") (pinfunction "DVDD_46") (pintype "passive"))
      (node (ref "U19") (pin "5") (pinfunction "DVDD_5") (pintype "passive"))
      (node (ref "U19") (pin "51") (pinfunction "DVDD_51") (pintype "passive"))
      (node (ref "U19") (pin "52") (pinfunction "DVDD_52") (pintype "passive"))
      (node (ref "U19") (pin "54") (pinfunction "DVDD_54") (pintype "passive"))
      (node (ref "U19") (pin "55") (pinfunction "DVDD_55") (pintype "passive"))
      (node (ref "U19") (pin "58") (pinfunction "DVDD_58") (pintype "passive"))
      (node (ref "U19") (pin "59") (pinfunction "DVDD_59") (pintype "passive"))
      (node (ref "U19") (pin "6") (pinfunction "DVDD_6") (pintype "passive"))
      (node (ref "U19") (pin "60") (pinfunction "DVDD_60") (pintype "passive"))
      (node (ref "U19") (pin "62") (pinfunction "DVDD_62") (pintype "passive"))
      (node (ref "U19") (pin "63") (pinfunction "DVDD_63") (pintype "passive"))
      (node (ref "U20") (pin "13") (pinfunction "DVDD_13") (pintype "passive"))
      (node (ref "U20") (pin "14") (pinfunction "DVDD_14") (pintype "passive"))
      (node (ref "U20") (pin "19") (pinfunction "DVDD_19") (pintype "passive"))
      (node (ref "U20") (pin "20") (pinfunction "DVDD_20") (pintype "passive"))
      (node (ref "U20") (pin "21") (pinfunction "DVDD_21") (pintype "passive"))
      (node (ref "U20") (pin "22") (pinfunction "DVDD_22") (pintype "passive"))
      (node (ref "U20") (pin "26") (pinfunction "DVDD_26") (pintype "passive"))
      (node (ref "U20") (pin "27") (pinfunction "DVDD_27") (pintype "passive"))
      (node (ref "U20") (pin "29") (pinfunction "DVDD_29") (pintype "passive"))
      (node (ref "U20") (pin "3") (pinfunction "DVDD_3") (pintype "passive"))
      (node (ref "U20") (pin "30") (pinfunction "DVDD_30") (pintype "passive"))
      (node (ref "U20") (pin "34") (pinfunction "DVDD_34") (pintype "passive"))
      (node (ref "U20") (pin "35") (pinfunction "DVDD_35") (pintype "passive"))
      (node (ref "U20") (pin "37") (pinfunction "DVDD_37") (pintype "passive"))
      (node (ref "U20") (pin "38") (pinfunction "DVDD_38") (pintype "passive"))
      (node (ref "U20") (pin "39") (pinfunction "DVDD_39") (pintype "passive"))
      (node (ref "U20") (pin "4") (pinfunction "DVDD_4") (pintype "passive"))
      (node (ref "U20") (pin "41") (pinfunction "DVDD_41") (pintype "passive"))
      (node (ref "U20") (pin "42") (pinfunction "DVDD_42") (pintype "passive"))
      (node (ref "U20") (pin "43") (pinfunction "DVDD_43") (pintype "passive"))
      (node (ref "U20") (pin "45") (pinfunction "DVDD_45") (pintype "passive"))
      (node (ref "U20") (pin "46") (pinfunction "DVDD_46") (pintype "passive"))
      (node (ref "U20") (pin "5") (pinfunction "DVDD_5") (pintype "passive"))
      (node (ref "U20") (pin "51") (pinfunction "DVDD_51") (pintype "passive"))
      (node (ref "U20") (pin "52") (pinfunction "DVDD_52") (pintype "passive"))
      (node (ref "U20") (pin "54") (pinfunction "DVDD_54") (pintype "passive"))
      (node (ref "U20") (pin "55") (pinfunction "DVDD_55") (pintype "passive"))
      (node (ref "U20") (pin "58") (pinfunction "DVDD_58") (pintype "passive"))
      (node (ref "U20") (pin "59") (pinfunction "DVDD_59") (pintype "passive"))
      (node (ref "U20") (pin "6") (pinfunction "DVDD_6") (pintype "passive"))
      (node (ref "U20") (pin "60") (pinfunction "DVDD_60") (pintype "passive"))
      (node (ref "U20") (pin "62") (pinfunction "DVDD_62") (pintype "passive"))
      (node (ref "U20") (pin "63") (pinfunction "DVDD_63") (pintype "passive"))
      (node (ref "U21") (pin "13") (pinfunction "DVDD_13") (pintype "passive"))
      (node (ref "U21") (pin "14") (pinfunction "DVDD_14") (pintype "passive"))
      (node (ref "U21") (pin "19") (pinfunction "DVDD_19") (pintype "passive"))
      (node (ref "U21") (pin "20") (pinfunction "DVDD_20") (pintype "passive"))
      (node (ref "U21") (pin "21") (pinfunction "DVDD_21") (pintype "passive"))
      (node (ref "U21") (pin "22") (pinfunction "DVDD_22") (pintype "passive"))
      (node (ref "U21") (pin "26") (pinfunction "DVDD_26") (pintype "passive"))
      (node (ref "U21") (pin "27") (pinfunction "DVDD_27") (pintype "passive"))
      (node (ref "U21") (pin "29") (pinfunction "DVDD_29") (pintype "passive"))
      (node (ref "U21") (pin "3") (pinfunction "DVDD_3") (pintype "passive"))
      (node (ref "U21") (pin "30") (pinfunction "DVDD_30") (pintype "passive"))
      (node (ref "U21") (pin "34") (pinfunction "DVDD_34") (pintype "passive"))
      (node (ref "U21") (pin "35") (pinfunction "DVDD_35") (pintype "passive"))
      (node (ref "U21") (pin "37") (pinfunction "DVDD_37") (pintype "passive"))
      (node (ref "U21") (pin "38") (pinfunction "DVDD_38") (pintype "passive"))
      (node (ref "U21") (pin "39") (pinfunction "DVDD_39") (pintype "passive"))
      (node (ref "U21") (pin "4") (pinfunction "DVDD_4") (pintype "passive"))
      (node (ref "U21") (pin "41") (pinfunction "DVDD_41") (pintype "passive"))
      (node (ref "U21") (pin "42") (pinfunction "DVDD_42") (pintype "passive"))
      (node (ref "U21") (pin "43") (pinfunction "DVDD_43") (pintype "passive"))
      (node (ref "U21") (pin "45") (pinfunction "DVDD_45") (pintype "passive"))
      (node (ref "U21") (pin "46") (pinfunction "DVDD_46") (pintype "passive"))
      (node (ref "U21") (pin "5") (pinfunction "DVDD_5") (pintype "passive"))
      (node (ref "U21") (pin "51") (pinfunction "DVDD_51") (pintype "passive"))
      (node (ref "U21") (pin "52") (pinfunction "DVDD_52") (pintype "passive"))
      (node (ref "U21") (pin "54") (pinfunction "DVDD_54") (pintype "passive"))
      (node (ref "U21") (pin "55") (pinfunction "DVDD_55") (pintype "passive"))
      (node (ref "U21") (pin "58") (pinfunction "DVDD_58") (pintype "passive"))
      (node (ref "U21") (pin "59") (pinfunction "DVDD_59") (pintype "passive"))
      (node (ref "U21") (pin "6") (pinfunction "DVDD_6") (pintype "passive"))
      (node (ref "U21") (pin "60") (pinfunction "DVDD_60") (pintype "passive"))
      (node (ref "U21") (pin "62") (pinfunction "DVDD_62") (pintype "passive"))
      (node (ref "U21") (pin "63") (pinfunction "DVDD_63") (pintype "passive"))
      (node (ref "U24") (pin "13") (pinfunction "DVDD_13") (pintype "passive"))
      (node (ref "U24") (pin "14") (pinfunction "DVDD_14") (pintype "passive"))
      (node (ref "U24") (pin "19") (pinfunction "DVDD_19") (pintype "passive"))
      (node (ref "U24") (pin "20") (pinfunction "DVDD_20") (pintype "passive"))
      (node (ref "U24") (pin "21") (pinfunction "DVDD_21") (pintype "passive"))
      (node (ref "U24") (pin "22") (pinfunction "DVDD_22") (pintype "passive"))
      (node (ref "U24") (pin "26") (pinfunction "DVDD_26") (pintype "passive"))
      (node (ref "U24") (pin "27") (pinfunction "DVDD_27") (pintype "passive"))
      (node (ref "U24") (pin "29") (pinfunction "DVDD_29") (pintype "passive"))
      (node (ref "U24") (pin "3") (pinfunction "DVDD_3") (pintype "passive"))
      (node (ref "U24") (pin "30") (pinfunction "DVDD_30") (pintype "passive"))
      (node (ref "U24") (pin "34") (pinfunction "DVDD_34") (pintype "passive"))
      (node (ref "U24") (pin "35") (pinfunction "DVDD_35") (pintype "passive"))
      (node (ref "U24") (pin "37") (pinfunction "DVDD_37") (pintype "passive"))
      (node (ref "U24") (pin "38") (pinfunction "DVDD_38") (pintype "passive"))
      (node (ref "U24") (pin "39") (pinfunction "DVDD_39") (pintype "passive"))
      (node (ref "U24") (pin "4") (pinfunction "DVDD_4") (pintype "passive"))
      (node (ref "U24") (pin "41") (pinfunction "DVDD_41") (pintype "passive"))
      (node (ref "U24") (pin "42") (pinfunction "DVDD_42") (pintype "passive"))
      (node (ref "U24") (pin "43") (pinfunction "DVDD_43") (pintype "passive"))
      (node (ref "U24") (pin "45") (pinfunction "DVDD_45") (pintype "passive"))
      (node (ref "U24") (pin "46") (pinfunction "DVDD_46") (pintype "passive"))
      (node (ref "U24") (pin "5") (pinfunction "DVDD_5") (pintype "passive"))
      (node (ref "U24") (pin "51") (pinfunction "DVDD_51") (pintype "passive"))
      (node (ref "U24") (pin "52") (pinfunction "DVDD_52") (pintype "passive"))
      (node (ref "U24") (pin "54") (pinfunction "DVDD_54") (pintype "passive"))
      (node (ref "U24") (pin "55") (pinfunction "DVDD_55") (pintype "passive"))
      (node (ref "U24") (pin "58") (pinfunction "DVDD_58") (pintype "passive"))
      (node (ref "U24") (pin "59") (pinfunction "DVDD_59") (pintype "passive"))
      (node (ref "U24") (pin "6") (pinfunction "DVDD_6") (pintype "passive"))
      (node (ref "U24") (pin "60") (pinfunction "DVDD_60") (pintype "passive"))
      (node (ref "U24") (pin "62") (pinfunction "DVDD_62") (pintype "passive"))
      (node (ref "U24") (pin "63") (pinfunction "DVDD_63") (pintype "passive"))
      (node (ref "U25") (pin "13") (pinfunction "DVDD_13") (pintype "passive"))
      (node (ref "U25") (pin "14") (pinfunction "DVDD_14") (pintype "passive"))
      (node (ref "U25") (pin "19") (pinfunction "DVDD_19") (pintype "passive"))
      (node (ref "U25") (pin "20") (pinfunction "DVDD_20") (pintype "passive"))
      (node (ref "U25") (pin "21") (pinfunction "DVDD_21") (pintype "passive"))
      (node (ref "U25") (pin "22") (pinfunction "DVDD_22") (pintype "passive"))
      (node (ref "U25") (pin "26") (pinfunction "DVDD_26") (pintype "passive"))
      (node (ref "U25") (pin "27") (pinfunction "DVDD_27") (pintype "passive"))
      (node (ref "U25") (pin "29") (pinfunction "DVDD_29") (pintype "passive"))
      (node (ref "U25") (pin "3") (pinfunction "DVDD_3") (pintype "passive"))
      (node (ref "U25") (pin "30") (pinfunction "DVDD_30") (pintype "passive"))
      (node (ref "U25") (pin "34") (pinfunction "DVDD_34") (pintype "passive"))
      (node (ref "U25") (pin "35") (pinfunction "DVDD_35") (pintype "passive"))
      (node (ref "U25") (pin "37") (pinfunction "DVDD_37") (pintype "passive"))
      (node (ref "U25") (pin "38") (pinfunction "DVDD_38") (pintype "passive"))
      (node (ref "U25") (pin "39") (pinfunction "DVDD_39") (pintype "passive"))
      (node (ref "U25") (pin "4") (pinfunction "DVDD_4") (pintype "passive"))
      (node (ref "U25") (pin "41") (pinfunction "DVDD_41") (pintype "passive"))
      (node (ref "U25") (pin "42") (pinfunction "DVDD_42") (pintype "passive"))
      (node (ref "U25") (pin "43") (pinfunction "DVDD_43") (pintype "passive"))
      (node (ref "U25") (pin "45") (pinfunction "DVDD_45") (pintype "passive"))
      (node (ref "U25") (pin "46") (pinfunction "DVDD_46") (pintype "passive"))
      (node (ref "U25") (pin "5") (pinfunction "DVDD_5") (pintype "passive"))
      (node (ref "U25") (pin "51") (pinfunction "DVDD_51") (pintype "passive"))
      (node (ref "U25") (pin "52") (pinfunction "DVDD_52") (pintype "passive"))
      (node (ref "U25") (pin "54") (pinfunction "DVDD_54") (pintype "passive"))
      (node (ref "U25") (pin "55") (pinfunction "DVDD_55") (pintype "passive"))
      (node (ref "U25") (pin "58") (pinfunction "DVDD_58") (pintype "passive"))
      (node (ref "U25") (pin "59") (pinfunction "DVDD_59") (pintype "passive"))
      (node (ref "U25") (pin "6") (pinfunction "DVDD_6") (pintype "passive"))
      (node (ref "U25") (pin "60") (pinfunction "DVDD_60") (pintype "passive"))
      (node (ref "U25") (pin "62") (pinfunction "DVDD_62") (pintype "passive"))
      (node (ref "U25") (pin "63") (pinfunction "DVDD_63") (pintype "passive"))
      (node (ref "U26") (pin "13") (pinfunction "DVDD_13") (pintype "passive"))
      (node (ref "U26") (pin "14") (pinfunction "DVDD_14") (pintype "passive"))
      (node (ref "U26") (pin "19") (pinfunction "DVDD_19") (pintype "passive"))
      (node (ref "U26") (pin "20") (pinfunction "DVDD_20") (pintype "passive"))
      (node (ref "U26") (pin "21") (pinfunction "DVDD_21") (pintype "passive"))
      (node (ref "U26") (pin "22") (pinfunction "DVDD_22") (pintype "passive"))
      (node (ref "U26") (pin "26") (pinfunction "DVDD_26") (pintype "passive"))
      (node (ref "U26") (pin "27") (pinfunction "DVDD_27") (pintype "passive"))
      (node (ref "U26") (pin "29") (pinfunction "DVDD_29") (pintype "passive"))
      (node (ref "U26") (pin "3") (pinfunction "DVDD_3") (pintype "passive"))
      (node (ref "U26") (pin "30") (pinfunction "DVDD_30") (pintype "passive"))
      (node (ref "U26") (pin "34") (pinfunction "DVDD_34") (pintype "passive"))
      (node (ref "U26") (pin "35") (pinfunction "DVDD_35") (pintype "passive"))
      (node (ref "U26") (pin "37") (pinfunction "DVDD_37") (pintype "passive"))
      (node (ref "U26") (pin "38") (pinfunction "DVDD_38") (pintype "passive"))
      (node (ref "U26") (pin "39") (pinfunction "DVDD_39") (pintype "passive"))
      (node (ref "U26") (pin "4") (pinfunction "DVDD_4") (pintype "passive"))
      (node (ref "U26") (pin "41") (pinfunction "DVDD_41") (pintype "passive"))
      (node (ref "U26") (pin "42") (pinfunction "DVDD_42") (pintype "passive"))
      (node (ref "U26") (pin "43") (pinfunction "DVDD_43") (pintype "passive"))
      (node (ref "U26") (pin "45") (pinfunction "DVDD_45") (pintype "passive"))
      (node (ref "U26") (pin "46") (pinfunction "DVDD_46") (pintype "passive"))
      (node (ref "U26") (pin "5") (pinfunction "DVDD_5") (pintype "passive"))
      (node (ref "U26") (pin "51") (pinfunction "DVDD_51") (pintype "passive"))
      (node (ref "U26") (pin "52") (pinfunction "DVDD_52") (pintype "passive"))
      (node (ref "U26") (pin "54") (pinfunction "DVDD_54") (pintype "passive"))
      (node (ref "U26") (pin "55") (pinfunction "DVDD_55") (pintype "passive"))
      (node (ref "U26") (pin "58") (pinfunction "DVDD_58") (pintype "passive"))
      (node (ref "U26") (pin "59") (pinfunction "DVDD_59") (pintype "passive"))
      (node (ref "U26") (pin "6") (pinfunction "DVDD_6") (pintype "passive"))
      (node (ref "U26") (pin "60") (pinfunction "DVDD_60") (pintype "passive"))
      (node (ref "U26") (pin "62") (pinfunction "DVDD_62") (pintype "passive"))
      (node (ref "U26") (pin "63") (pinfunction "DVDD_63") (pintype "passive"))
      (node (ref "U27") (pin "13") (pinfunction "DVDD_13") (pintype "passive"))
      (node (ref "U27") (pin "14") (pinfunction "DVDD_14") (pintype "passive"))
      (node (ref "U27") (pin "19") (pinfunction "DVDD_19") (pintype "passive"))
      (node (ref "U27") (pin "20") (pinfunction "DVDD_20") (pintype "passive"))
      (node (ref "U27") (pin "21") (pinfunction "DVDD_21") (pintype "passive"))
      (node (ref "U27") (pin "22") (pinfunction "DVDD_22") (pintype "passive"))
      (node (ref "U27") (pin "26") (pinfunction "DVDD_26") (pintype "passive"))
      (node (ref "U27") (pin "27") (pinfunction "DVDD_27") (pintype "passive"))
      (node (ref "U27") (pin "29") (pinfunction "DVDD_29") (pintype "passive"))
      (node (ref "U27") (pin "3") (pinfunction "DVDD_3") (pintype "passive"))
      (node (ref "U27") (pin "30") (pinfunction "DVDD_30") (pintype "passive"))
      (node (ref "U27") (pin "34") (pinfunction "DVDD_34") (pintype "passive"))
      (node (ref "U27") (pin "35") (pinfunction "DVDD_35") (pintype "passive"))
      (node (ref "U27") (pin "37") (pinfunction "DVDD_37") (pintype "passive"))
      (node (ref "U27") (pin "38") (pinfunction "DVDD_38") (pintype "passive"))
      (node (ref "U27") (pin "39") (pinfunction "DVDD_39") (pintype "passive"))
      (node (ref "U27") (pin "4") (pinfunction "DVDD_4") (pintype "passive"))
      (node (ref "U27") (pin "41") (pinfunction "DVDD_41") (pintype "passive"))
      (node (ref "U27") (pin "42") (pinfunction "DVDD_42") (pintype "passive"))
      (node (ref "U27") (pin "43") (pinfunction "DVDD_43") (pintype "passive"))
      (node (ref "U27") (pin "45") (pinfunction "DVDD_45") (pintype "passive"))
      (node (ref "U27") (pin "46") (pinfunction "DVDD_46") (pintype "passive"))
      (node (ref "U27") (pin "5") (pinfunction "DVDD_5") (pintype "passive"))
      (node (ref "U27") (pin "51") (pinfunction "DVDD_51") (pintype "passive"))
      (node (ref "U27") (pin "52") (pinfunction "DVDD_52") (pintype "passive"))
      (node (ref "U27") (pin "54") (pinfunction "DVDD_54") (pintype "passive"))
      (node (ref "U27") (pin "55") (pinfunction "DVDD_55") (pintype "passive"))
      (node (ref "U27") (pin "58") (pinfunction "DVDD_58") (pintype "passive"))
      (node (ref "U27") (pin "59") (pinfunction "DVDD_59") (pintype "passive"))
      (node (ref "U27") (pin "6") (pinfunction "DVDD_6") (pintype "passive"))
      (node (ref "U27") (pin "60") (pinfunction "DVDD_60") (pintype "passive"))
      (node (ref "U27") (pin "62") (pinfunction "DVDD_62") (pintype "passive"))
      (node (ref "U27") (pin "63") (pinfunction "DVDD_63") (pintype "passive"))
      (node (ref "U4") (pin "13") (pinfunction "DVDD_13") (pintype "passive"))
      (node (ref "U4") (pin "14") (pinfunction "DVDD_14") (pintype "passive"))
      (node (ref "U4") (pin "19") (pinfunction "DVDD_19") (pintype "passive"))
      (node (ref "U4") (pin "20") (pinfunction "DVDD_20") (pintype "passive"))
      (node (ref "U4") (pin "21") (pinfunction "DVDD_21") (pintype "passive"))
      (node (ref "U4") (pin "22") (pinfunction "DVDD_22") (pintype "passive"))
      (node (ref "U4") (pin "26") (pinfunction "DVDD_26") (pintype "passive"))
      (node (ref "U4") (pin "27") (pinfunction "DVDD_27") (pintype "passive"))
      (node (ref "U4") (pin "29") (pinfunction "DVDD_29") (pintype "passive"))
      (node (ref "U4") (pin "3") (pinfunction "DVDD_3") (pintype "passive"))
      (node (ref "U4") (pin "30") (pinfunction "DVDD_30") (pintype "passive"))
      (node (ref "U4") (pin "34") (pinfunction "DVDD_34") (pintype "passive"))
      (node (ref "U4") (pin "35") (pinfunction "DVDD_35") (pintype "passive"))
      (node (ref "U4") (pin "37") (pinfunction "DVDD_37") (pintype "passive"))
      (node (ref "U4") (pin "38") (pinfunction "DVDD_38") (pintype "passive"))
      (node (ref "U4") (pin "39") (pinfunction "DVDD_39") (pintype "passive"))
      (node (ref "U4") (pin "4") (pinfunction "DVDD_4") (pintype "passive"))
      (node (ref "U4") (pin "41") (pinfunction "DVDD_41") (pintype "passive"))
      (node (ref "U4") (pin "42") (pinfunction "DVDD_42") (pintype "passive"))
      (node (ref "U4") (pin "43") (pinfunction "DVDD_43") (pintype "passive"))
      (node (ref "U4") (pin "45") (pinfunction "DVDD_45") (pintype "passive"))
      (node (ref "U4") (pin "46") (pinfunction "DVDD_46") (pintype "passive"))
      (node (ref "U4") (pin "5") (pinfunction "DVDD_5") (pintype "passive"))
      (node (ref "U4") (pin "51") (pinfunction "DVDD_51") (pintype "passive"))
      (node (ref "U4") (pin "52") (pinfunction "DVDD_52") (pintype "passive"))
      (node (ref "U4") (pin "54") (pinfunction "DVDD_54") (pintype "passive"))
      (node (ref "U4") (pin "55") (pinfunction "DVDD_55") (pintype "passive"))
      (node (ref "U4") (pin "58") (pinfunction "DVDD_58") (pintype "passive"))
      (node (ref "U4") (pin "59") (pinfunction "DVDD_59") (pintype "passive"))
      (node (ref "U4") (pin "6") (pinfunction "DVDD_6") (pintype "passive"))
      (node (ref "U4") (pin "60") (pinfunction "DVDD_60") (pintype "passive"))
      (node (ref "U4") (pin "62") (pinfunction "DVDD_62") (pintype "passive"))
      (node (ref "U4") (pin "63") (pinfunction "DVDD_63") (pintype "passive"))
      (node (ref "U5") (pin "13") (pinfunction "DVDD_13") (pintype "passive"))
      (node (ref "U5") (pin "14") (pinfunction "DVDD_14") (pintype "passive"))
      (node (ref "U5") (pin "19") (pinfunction "DVDD_19") (pintype "passive"))
      (node (ref "U5") (pin "20") (pinfunction "DVDD_20") (pintype "passive"))
      (node (ref "U5") (pin "21") (pinfunction "DVDD_21") (pintype "passive"))
      (node (ref "U5") (pin "22") (pinfunction "DVDD_22") (pintype "passive"))
      (node (ref "U5") (pin "26") (pinfunction "DVDD_26") (pintype "passive"))
      (node (ref "U5") (pin "27") (pinfunction "DVDD_27") (pintype "passive"))
      (node (ref "U5") (pin "29") (pinfunction "DVDD_29") (pintype "passive"))
      (node (ref "U5") (pin "3") (pinfunction "DVDD_3") (pintype "passive"))
      (node (ref "U5") (pin "30") (pinfunction "DVDD_30") (pintype "passive"))
      (node (ref "U5") (pin "34") (pinfunction "DVDD_34") (pintype "passive"))
      (node (ref "U5") (pin "35") (pinfunction "DVDD_35") (pintype "passive"))
      (node (ref "U5") (pin "37") (pinfunction "DVDD_37") (pintype "passive"))
      (node (ref "U5") (pin "38") (pinfunction "DVDD_38") (pintype "passive"))
      (node (ref "U5") (pin "39") (pinfunction "DVDD_39") (pintype "passive"))
      (node (ref "U5") (pin "4") (pinfunction "DVDD_4") (pintype "passive"))
      (node (ref "U5") (pin "41") (pinfunction "DVDD_41") (pintype "passive"))
      (node (ref "U5") (pin "42") (pinfunction "DVDD_42") (pintype "passive"))
      (node (ref "U5") (pin "43") (pinfunction "DVDD_43") (pintype "passive"))
      (node (ref "U5") (pin "45") (pinfunction "DVDD_45") (pintype "passive"))
      (node (ref "U5") (pin "46") (pinfunction "DVDD_46") (pintype "passive"))
      (node (ref "U5") (pin "5") (pinfunction "DVDD_5") (pintype "passive"))
      (node (ref "U5") (pin "51") (pinfunction "DVDD_51") (pintype "passive"))
      (node (ref "U5") (pin "52") (pinfunction "DVDD_52") (pintype "passive"))
      (node (ref "U5") (pin "54") (pinfunction "DVDD_54") (pintype "passive"))
      (node (ref "U5") (pin "55") (pinfunction "DVDD_55") (pintype "passive"))
      (node (ref "U5") (pin "58") (pinfunction "DVDD_58") (pintype "passive"))
      (node (ref "U5") (pin "59") (pinfunction "DVDD_59") (pintype "passive"))
      (node (ref "U5") (pin "6") (pinfunction "DVDD_6") (pintype "passive"))
      (node (ref "U5") (pin "60") (pinfunction "DVDD_60") (pintype "passive"))
      (node (ref "U5") (pin "62") (pinfunction "DVDD_62") (pintype "passive"))
      (node (ref "U5") (pin "63") (pinfunction "DVDD_63") (pintype "passive"))
      (node (ref "U6") (pin "13") (pinfunction "DVDD_13") (pintype "passive"))
      (node (ref "U6") (pin "14") (pinfunction "DVDD_14") (pintype "passive"))
      (node (ref "U6") (pin "19") (pinfunction "DVDD_19") (pintype "passive"))
      (node (ref "U6") (pin "20") (pinfunction "DVDD_20") (pintype "passive"))
      (node (ref "U6") (pin "21") (pinfunction "DVDD_21") (pintype "passive"))
      (node (ref "U6") (pin "22") (pinfunction "DVDD_22") (pintype "passive"))
      (node (ref "U6") (pin "26") (pinfunction "DVDD_26") (pintype "passive"))
      (node (ref "U6") (pin "27") (pinfunction "DVDD_27") (pintype "passive"))
      (node (ref "U6") (pin "29") (pinfunction "DVDD_29") (pintype "passive"))
      (node (ref "U6") (pin "3") (pinfunction "DVDD_3") (pintype "passive"))
      (node (ref "U6") (pin "30") (pinfunction "DVDD_30") (pintype "passive"))
      (node (ref "U6") (pin "34") (pinfunction "DVDD_34") (pintype "passive"))
      (node (ref "U6") (pin "35") (pinfunction "DVDD_35") (pintype "passive"))
      (node (ref "U6") (pin "37") (pinfunction "DVDD_37") (pintype "passive"))
      (node (ref "U6") (pin "38") (pinfunction "DVDD_38") (pintype "passive"))
      (node (ref "U6") (pin "39") (pinfunction "DVDD_39") (pintype "passive"))
      (node (ref "U6") (pin "4") (pinfunction "DVDD_4") (pintype "passive"))
      (node (ref "U6") (pin "41") (pinfunction "DVDD_41") (pintype "passive"))
      (node (ref "U6") (pin "42") (pinfunction "DVDD_42") (pintype "passive"))
      (node (ref "U6") (pin "43") (pinfunction "DVDD_43") (pintype "passive"))
      (node (ref "U6") (pin "45") (pinfunction "DVDD_45") (pintype "passive"))
      (node (ref "U6") (pin "46") (pinfunction "DVDD_46") (pintype "passive"))
      (node (ref "U6") (pin "5") (pinfunction "DVDD_5") (pintype "passive"))
      (node (ref "U6") (pin "51") (pinfunction "DVDD_51") (pintype "passive"))
      (node (ref "U6") (pin "52") (pinfunction "DVDD_52") (pintype "passive"))
      (node (ref "U6") (pin "54") (pinfunction "DVDD_54") (pintype "passive"))
      (node (ref "U6") (pin "55") (pinfunction "DVDD_55") (pintype "passive"))
      (node (ref "U6") (pin "58") (pinfunction "DVDD_58") (pintype "passive"))
      (node (ref "U6") (pin "59") (pinfunction "DVDD_59") (pintype "passive"))
      (node (ref "U6") (pin "6") (pinfunction "DVDD_6") (pintype "passive"))
      (node (ref "U6") (pin "60") (pinfunction "DVDD_60") (pintype "passive"))
      (node (ref "U6") (pin "62") (pinfunction "DVDD_62") (pintype "passive"))
      (node (ref "U6") (pin "63") (pinfunction "DVDD_63") (pintype "passive"))
      (node (ref "U7") (pin "13") (pinfunction "DVDD_13") (pintype "passive"))
      (node (ref "U7") (pin "14") (pinfunction "DVDD_14") (pintype "passive"))
      (node (ref "U7") (pin "19") (pinfunction "DVDD_19") (pintype "passive"))
      (node (ref "U7") (pin "20") (pinfunction "DVDD_20") (pintype "passive"))
      (node (ref "U7") (pin "21") (pinfunction "DVDD_21") (pintype "passive"))
      (node (ref "U7") (pin "22") (pinfunction "DVDD_22") (pintype "passive"))
      (node (ref "U7") (pin "26") (pinfunction "DVDD_26") (pintype "passive"))
      (node (ref "U7") (pin "27") (pinfunction "DVDD_27") (pintype "passive"))
      (node (ref "U7") (pin "29") (pinfunction "DVDD_29") (pintype "passive"))
      (node (ref "U7") (pin "3") (pinfunction "DVDD_3") (pintype "passive"))
      (node (ref "U7") (pin "30") (pinfunction "DVDD_30") (pintype "passive"))
      (node (ref "U7") (pin "34") (pinfunction "DVDD_34") (pintype "passive"))
      (node (ref "U7") (pin "35") (pinfunction "DVDD_35") (pintype "passive"))
      (node (ref "U7") (pin "37") (pinfunction "DVDD_37") (pintype "passive"))
      (node (ref "U7") (pin "38") (pinfunction "DVDD_38") (pintype "passive"))
      (node (ref "U7") (pin "39") (pinfunction "DVDD_39") (pintype "passive"))
      (node (ref "U7") (pin "4") (pinfunction "DVDD_4") (pintype "passive"))
      (node (ref "U7") (pin "41") (pinfunction "DVDD_41") (pintype "passive"))
      (node (ref "U7") (pin "42") (pinfunction "DVDD_42") (pintype "passive"))
      (node (ref "U7") (pin "43") (pinfunction "DVDD_43") (pintype "passive"))
      (node (ref "U7") (pin "45") (pinfunction "DVDD_45") (pintype "passive"))
      (node (ref "U7") (pin "46") (pinfunction "DVDD_46") (pintype "passive"))
      (node (ref "U7") (pin "5") (pinfunction "DVDD_5") (pintype "passive"))
      (node (ref "U7") (pin "51") (pinfunction "DVDD_51") (pintype "passive"))
      (node (ref "U7") (pin "52") (pinfunction "DVDD_52") (pintype "passive"))
      (node (ref "U7") (pin "54") (pinfunction "DVDD_54") (pintype "passive"))
      (node (ref "U7") (pin "55") (pinfunction "DVDD_55") (pintype "passive"))
      (node (ref "U7") (pin "58") (pinfunction "DVDD_58") (pintype "passive"))
      (node (ref "U7") (pin "59") (pinfunction "DVDD_59") (pintype "passive"))
      (node (ref "U7") (pin "6") (pinfunction "DVDD_6") (pintype "passive"))
      (node (ref "U7") (pin "60") (pinfunction "DVDD_60") (pintype "passive"))
      (node (ref "U7") (pin "62") (pinfunction "DVDD_62") (pintype "passive"))
      (node (ref "U7") (pin "63") (pinfunction "DVDD_63") (pintype "passive"))
      (node (ref "U9") (pin "13") (pinfunction "DVDD_13") (pintype "passive"))
      (node (ref "U9") (pin "14") (pinfunction "DVDD_14") (pintype "passive"))
      (node (ref "U9") (pin "19") (pinfunction "DVDD_19") (pintype "passive"))
      (node (ref "U9") (pin "20") (pinfunction "DVDD_20") (pintype "passive"))
      (node (ref "U9") (pin "21") (pinfunction "DVDD_21") (pintype "passive"))
      (node (ref "U9") (pin "22") (pinfunction "DVDD_22") (pintype "passive"))
      (node (ref "U9") (pin "26") (pinfunction "DVDD_26") (pintype "passive"))
      (node (ref "U9") (pin "27") (pinfunction "DVDD_27") (pintype "passive"))
      (node (ref "U9") (pin "29") (pinfunction "DVDD_29") (pintype "passive"))
      (node (ref "U9") (pin "3") (pinfunction "DVDD_3") (pintype "passive"))
      (node (ref "U9") (pin "30") (pinfunction "DVDD_30") (pintype "passive"))
      (node (ref "U9") (pin "34") (pinfunction "DVDD_34") (pintype "passive"))
      (node (ref "U9") (pin "35") (pinfunction "DVDD_35") (pintype "passive"))
      (node (ref "U9") (pin "37") (pinfunction "DVDD_37") (pintype "passive"))
      (node (ref "U9") (pin "38") (pinfunction "DVDD_38") (pintype "passive"))
      (node (ref "U9") (pin "39") (pinfunction "DVDD_39") (pintype "passive"))
      (node (ref "U9") (pin "4") (pinfunction "DVDD_4") (pintype "passive"))
      (node (ref "U9") (pin "41") (pinfunction "DVDD_41") (pintype "passive"))
      (node (ref "U9") (pin "42") (pinfunction "DVDD_42") (pintype "passive"))
      (node (ref "U9") (pin "43") (pinfunction "DVDD_43") (pintype "passive"))
      (node (ref "U9") (pin "45") (pinfunction "DVDD_45") (pintype "passive"))
      (node (ref "U9") (pin "46") (pinfunction "DVDD_46") (pintype "passive"))
      (node (ref "U9") (pin "5") (pinfunction "DVDD_5") (pintype "passive"))
      (node (ref "U9") (pin "51") (pinfunction "DVDD_51") (pintype "passive"))
      (node (ref "U9") (pin "52") (pinfunction "DVDD_52") (pintype "passive"))
      (node (ref "U9") (pin "54") (pinfunction "DVDD_54") (pintype "passive"))
      (node (ref "U9") (pin "55") (pinfunction "DVDD_55") (pintype "passive"))
      (node (ref "U9") (pin "58") (pinfunction "DVDD_58") (pintype "passive"))
      (node (ref "U9") (pin "59") (pinfunction "DVDD_59") (pintype "passive"))
      (node (ref "U9") (pin "6") (pinfunction "DVDD_6") (pintype "passive"))
      (node (ref "U9") (pin "60") (pinfunction "DVDD_60") (pintype "passive"))
      (node (ref "U9") (pin "62") (pinfunction "DVDD_62") (pintype "passive"))
      (node (ref "U9") (pin "63") (pinfunction "DVDD_63") (pintype "passive"))
    )
    (net (code "2") (name "/3.3V") (class "Default")
      (node (ref "C122") (pin "2") (pinfunction "2_2") (pintype "passive"))
      (node (ref "C127") (pin "2") (pinfunction "2_2") (pintype "passive"))
      (node (ref "C132") (pin "2") (pinfunction "2_2") (pintype "passive"))
      (node (ref "C137") (pin "2") (pinfunction "2_2") (pintype "passive"))
      (node (ref "C167") (pin "1") (pinfunction "1_1") (pintype "passive"))
      (node (ref "C169") (pin "1") (pinfunction "1_1") (pintype "passive"))
      (node (ref "C170") (pin "1") (pinfunction "1_1") (pintype "passive"))
      (node (ref "C171") (pin "1") (pinfunction "1_1") (pintype "passive"))
      (node (ref "C172") (pin "1") (pinfunction "1_1") (pintype "passive"))
      (node (ref "C178") (pin "2") (pinfunction "2_2") (pintype "passive"))
      (node (ref "C182") (pin "2") (pinfunction "2_2") (pintype "passive"))
      (node (ref "C186") (pin "2") (pinfunction "2_2") (pintype "passive"))
      (node (ref "C190") (pin "2") (pinfunction "2_2") (pintype "passive"))
      (node (ref "C224") (pin "2") (pinfunction "2_2") (pintype "passive"))
      (node (ref "C225") (pin "1") (pinfunction "1_1") (pintype "passive"))
      (node (ref "C231") (pin "2") (pinfunction "2_2") (pintype "passive"))
      (node (ref "C236") (pin "2") (pinfunction "2_2") (pintype "passive"))
      (node (ref "C241") (pin "2") (pinfunction "2_2") (pintype "passive"))
      (node (ref "C246") (pin "2") (pinfunction "2_2") (pintype "passive"))
      (node (ref "C275") (pin "1") (pinfunction "1_1") (pintype "passive"))
      (node (ref "C279") (pin "2") (pinfunction "2_2") (pintype "passive"))
      (node (ref "C283") (pin "2") (pinfunction "2_2") (pintype "passive"))
      (node (ref "C287") (pin "2") (pinfunction "2_2") (pintype "passive"))
      (node (ref "C29") (pin "2") (pinfunction "2_2") (pintype "passive"))
      (node (ref "C291") (pin "2") (pinfunction "2_2") (pintype "passive"))
      (node (ref "C328") (pin "2") (pinfunction "2_2") (pintype "passive"))
      (node (ref "C333") (pin "2") (pinfunction "2_2") (pintype "passive"))
      (node (ref "C338") (pin "2") (pinfunction "2_2") (pintype "passive"))
      (node (ref "C34") (pin "2") (pinfunction "2_2") (pintype "passive"))
      (node (ref "C343") (pin "2") (pinfunction "2_2") (pintype "passive"))
      (node (ref "C371") (pin "2") (pinfunction "2_2") (pintype "passive"))
      (node (ref "C375") (pin "2") (pinfunction "2_2") (pintype "passive"))
      (node (ref "C379") (pin "2") (pinfunction "2_2") (pintype "passive"))
      (node (ref "C383") (pin "2") (pinfunction "2_2") (pintype "passive"))
      (node (ref "C39") (pin "2") (pinfunction "2_2") (pintype "passive"))
      (node (ref "C44") (pin "2") (pinfunction "2_2") (pintype "passive"))
      (node (ref "C69") (pin "1") (pinfunction "1_1") (pintype "passive"))
      (node (ref "C73") (pin "2") (pinfunction "2_2") (pintype "passive"))
      (node (ref "C77") (pin "2") (pinfunction "2_2") (pintype "passive"))
      (node (ref "C81") (pin "2") (pinfunction "2_2") (pintype "passive"))
      (node (ref "C85") (pin "2") (pinfunction "2_2") (pintype "passive"))
      (node (ref "J1") (pin "2") (pinfunction "2_2") (pintype "passive"))
      (node (ref "R31") (pin "2") (pinfunction "2_2") (pintype "passive"))
      (node (ref "R48") (pin "2") (pinfunction "2_2") (pintype "passive"))
      (node (ref "R5") (pin "2") (pinfunction "2_2") (pintype "passive"))
      (node (ref "R53") (pin "2") (pinfunction "2_2") (pintype "passive"))
      (node (ref "R54") (pin "1") (pinfunction "1_1") (pintype "passive"))
      (node (ref "R6") (pin "2") (pinfunction "2_2") (pintype "passive"))
      (node (ref "R7") (pin "2") (pinfunction "2_2") (pintype "passive"))
      (node (ref "R8") (pin "1") (pinfunction "1_1") (pintype "passive"))
      (node (ref "U10") (pin "16") (pinfunction "CHIP_ID0_16") (pintype "passive"))
      (node (ref "U10") (pin "18") (pinfunction "CHIP_ID2_18") (pintype "passive"))
      (node (ref "U10") (pin "32") (pinfunction "OVDD1_32") (pintype "passive"))
      (node (ref "U10") (pin "49") (pinfunction "OVDD0_49") (pintype "passive"))
      (node (ref "U11") (pin "17") (pinfunction "CHIP_ID1_17") (pintype "passive"))
      (node (ref "U11") (pin "18") (pinfunction "CHIP_ID2_18") (pintype "passive"))
      (node (ref "U11") (pin "32") (pinfunction "OVDD1_32") (pintype "passive"))
      (node (ref "U11") (pin "49") (pinfunction "OVDD0_49") (pintype "passive"))
      (node (ref "U12") (pin "16") (pinfunction "CHIP_ID0_16") (pintype "passive"))
      (node (ref "U12") (pin "17") (pinfunction "CHIP_ID1_17") (pintype "passive"))
      (node (ref "U12") (pin "18") (pinfunction "CHIP_ID2_18") (pintype "passive"))
      (node (ref "U12") (pin "32") (pinfunction "OVDD1_32") (pintype "passive"))
      (node (ref "U12") (pin "49") (pinfunction "OVDD0_49") (pintype "passive"))
      (node (ref "U14") (pin "5") (pinfunction "OUT_5") (pintype "passive"))
      (node (ref "U15") (pin "1") (pinfunction "OUT_1") (pintype "passive"))
      (node (ref "U18") (pin "32") (pinfunction "OVDD1_32") (pintype "passive"))
      (node (ref "U18") (pin "49") (pinfunction "OVDD0_49") (pintype "passive"))
      (node (ref "U19") (pin "16") (pinfunction "CHIP_ID0_16") (pintype "passive"))
      (node (ref "U19") (pin "32") (pinfunction "OVDD1_32") (pintype "passive"))
      (node (ref "U19") (pin "49") (pinfunction "OVDD0_49") (pintype "passive"))
      (node (ref "U20") (pin "17") (pinfunction "CHIP_ID1_17") (pintype "passive"))
      (node (ref "U20") (pin "32") (pinfunction "OVDD1_32") (pintype "passive"))
      (node (ref "U20") (pin "49") (pinfunction "OVDD0_49") (pintype "passive"))
      (node (ref "U21") (pin "17") (pinfunction "CHIP_ID1_17") (pintype "passive"))
      (node (ref "U21") (pin "18") (pinfunction "CHIP_ID2_18") (pintype "passive"))
      (node (ref "U21") (pin "32") (pinfunction "OVDD1_32") (pintype "passive"))
      (node (ref "U21") (pin "49") (pinfunction "OVDD0_49") (pintype "passive"))
      (node (ref "U24") (pin "18") (pinfunction "CHIP_ID2_18") (pintype "passive"))
      (node (ref "U24") (pin "32") (pinfunction "OVDD1_32") (pintype "passive"))
      (node (ref "U24") (pin "49") (pinfunction "OVDD0_49") (pintype "passive"))
      (node (ref "U25") (pin "16") (pinfunction "CHIP_ID0_16") (pintype "passive"))
      (node (ref "U25") (pin "18") (pinfunction "CHIP_ID2_18") (pintype "passive"))
      (node (ref "U25") (pin "32") (pinfunction "OVDD1_32") (pintype "passive"))
      (node (ref "U25") (pin "49") (pinfunction "OVDD0_49") (pintype "passive"))
      (node (ref "U26") (pin "17") (pinfunction "CHIP_ID1_17") (pintype "passive"))
      (node (ref "U26") (pin "18") (pinfunction "CHIP_ID2_18") (pintype "passive"))
      (node (ref "U26") (pin "32") (pinfunction "OVDD1_32") (pintype "passive"))
      (node (ref "U26") (pin "49") (pinfunction "OVDD0_49") (pintype "passive"))
      (node (ref "U27") (pin "16") (pinfunction "CHIP_ID0_16") (pintype "passive"))
      (node (ref "U27") (pin "17") (pinfunction "CHIP_ID1_17") (pintype "passive"))
      (node (ref "U27") (pin "18") (pinfunction "CHIP_ID2_18") (pintype "passive"))
      (node (ref "U27") (pin "32") (pinfunction "OVDD1_32") (pintype "passive"))
      (node (ref "U27") (pin "49") (pinfunction "OVDD0_49") (pintype "passive"))
      (node (ref "U4") (pin "32") (pinfunction "OVDD1_32") (pintype "passive"))
      (node (ref "U4") (pin "49") (pinfunction "OVDD0_49") (pintype "passive"))
      (node (ref "U5") (pin "16") (pinfunction "CHIP_ID0_16") (pintype "passive"))
      (node (ref "U5") (pin "32") (pinfunction "OVDD1_32") (pintype "passive"))
      (node (ref "U5") (pin "49") (pinfunction "OVDD0_49") (pintype "passive"))
      (node (ref "U6") (pin "17") (pinfunction "CHIP_ID1_17") (pintype "passive"))
      (node (ref "U6") (pin "32") (pinfunction "OVDD1_32") (pintype "passive"))
      (node (ref "U6") (pin "49") (pinfunction "OVDD0_49") (pintype "passive"))
      (node (ref "U7") (pin "16") (pinfunction "CHIP_ID0_16") (pintype "passive"))
      (node (ref "U7") (pin "17") (pinfunction "CHIP_ID1_17") (pintype "passive"))
      (node (ref "U7") (pin "32") (pinfunction "OVDD1_32") (pintype "passive"))
      (node (ref "U7") (pin "49") (pinfunction "OVDD0_49") (pintype "passive"))
      (node (ref "U8") (pin "10") (pinfunction "VDD_10") (pintype "passive"))
      (node (ref "U8") (pin "19") (pinfunction "AVDD_19") (pintype "passive"))
      (node (ref "U8") (pin "26") (pinfunction "VDD_26") (pintype "passive"))
      (node (ref "U8") (pin "35") (pinfunction "VUSB3V3_35") (pintype "passive"))
      (node (ref "U8") (pin "38") (pinfunction "VDD_38") (pintype "passive"))
      (node (ref "U8") (pin "57") (pinfunction "VDD_57") (pintype "passive"))
      (node (ref "U9") (pin "18") (pinfunction "CHIP_ID2_18") (pintype "passive"))
      (node (ref "U9") (pin "32") (pinfunction "OVDD1_32") (pintype "passive"))
      (node (ref "U9") (pin "49") (pinfunction "OVDD0_49") (pintype "passive"))
    )
    (net (code "3") (name "/5.0V") (class "Default")
      (node (ref "C1") (pin "2") (pinfunction "2_2") (pintype "passive"))
      (node (ref "C191") (pin "1") (pinfunction "1_1") (pintype "passive"))
      (node (ref "C2") (pin "2") (pinfunction "2_2") (pintype "passive"))
      (node (ref "C3") (pin "2") (pinfunction "2_2") (pintype "passive"))
      (node (ref "D1") (pin "1") (pinfunction "A1_1") (pintype "passive"))
      (node (ref "D1") (pin "2") (pinfunction "A2_2") (pintype "passive"))
      (node (ref "D10") (pin "1") (pinfunction "C_1") (pintype "passive"))
      (node (ref "D2") (pin "1") (pinfunction "A1_1") (pintype "passive"))
      (node (ref "D2") (pin "2") (pinfunction "A2_2") (pintype "passive"))
      (node (ref "D3") (pin "1") (pinfunction "A1_1") (pintype "passive"))
      (node (ref "D3") (pin "2") (pinfunction "A2_2") (pintype "passive"))
      (node (ref "D8") (pin "2") (pinfunction "A_2") (pintype "passive"))
      (node (ref "J3") (pin "1") (pinfunction "1_1") (pintype "passive"))
      (node (ref "R42") (pin "1") (pinfunction "1_1") (pintype "passive"))
      (node (ref "U1") (pin "7") (pinfunction "VCC_7") (pintype "passive"))
      (node (ref "U13") (pin "1") (pinfunction "OUTPUT_1") (pintype "passive"))
      (node (ref "U16") (pin "3") (pinfunction "Vout_3") (pintype "passive"))
      (node (ref "U17") (pin "3") (pinfunction "Vout_3") (pintype "passive"))
      (node (ref "U2") (pin "7") (pinfunction "VCC_7") (pintype "passive"))
      (node (ref "U3") (pin "7") (pinfunction "VCC_7") (pintype "passive"))
    )
    (net (code "4") (name "/12V") (class "Default")
      (node (ref "C10") (pin "2") (pinfunction "2_2") (pintype "passive"))
      (node (ref "C11") (pin "2") (pinfunction "2_2") (pintype "passive"))
      (node (ref "C15") (pin "2") (pinfunction "2_2") (pintype "passive"))
      (node (ref "C16") (pin "2") (pinfunction "2_2") (pintype "passive"))
      (node (ref "C20") (pin "1") (pinfunction "1_1") (pintype "passive"))
      (node (ref "C21") (pin "1") (pinfunction "1_1") (pintype "passive"))
      (node (ref "D11") (pin "2") (pinfunction "A_2") (pintype "passive"))
      (node (ref "D12") (pin "1") (pinfunction "C_1") (pintype "passive"))
      (node (ref "J3") (pin "3") (pinfunction "3_3") (pintype "passive"))
      (node (ref "J4") (pin "1") (pinfunction "1_1") (pintype "passive"))
      (node (ref "J4") (pin "2") (pinfunction "2_2") (pintype "passive"))
      (node (ref "J4") (pin "3") (pinfunction "3_3") (pintype "passive"))
      (node (ref "Q1") (pin "5") (pinfunction "D_5") (pintype "passive"))
      (node (ref "Q1") (pin "6") (pinfunction "D_6") (pintype "passive"))
      (node (ref "Q1") (pin "7") (pinfunction "D_7") (pintype "passive"))
      (node (ref "Q1") (pin "8") (pinfunction "D_8") (pintype "passive"))
      (node (ref "Q2") (pin "5") (pinfunction "D_5") (pintype "passive"))
      (node (ref "Q2") (pin "6") (pinfunction "D_6") (pintype "passive"))
      (node (ref "Q2") (pin "7") (pinfunction "D_7") (pintype "passive"))
      (node (ref "Q2") (pin "8") (pinfunction "D_8") (pintype "passive"))
      (node (ref "Q3") (pin "5") (pinfunction "D_5") (pintype "passive"))
      (node (ref "Q3") (pin "6") (pinfunction "D_6") (pintype "passive"))
      (node (ref "Q3") (pin "7") (pinfunction "D_7") (pintype "passive"))
      (node (ref "Q3") (pin "8") (pinfunction "D_8") (pintype "passive"))
      (node (ref "R23") (pin "1") (pinfunction "1_1") (pintype "passive"))
      (node (ref "R47") (pin "2") (pinfunction "2_2") (pintype "passive"))
    )
    (net (code "5") (name "/ASIC_RESET_MCU") (class "Default")
      (node (ref "C120") (pin "2") (pinfunction "2_2") (pintype "passive"))
      (node (ref "C125") (pin "2") (pinfunction "2_2") (pintype "passive"))
      (node (ref "C130") (pin "2") (pinfunction "2_2") (pintype "passive"))
      (node (ref "C135") (pin "2") (pinfunction "2_2") (pintype "passive"))
      (node (ref "C229") (pin "2") (pinfunction "2_2") (pintype "passive"))
      (node (ref "C234") (pin "2") (pinfunction "2_2") (pintype "passive"))
      (node (ref "C239") (pin "2") (pinfunction "2_2") (pintype "passive"))
      (node (ref "C244") (pin "2") (pinfunction "2_2") (pintype "passive"))
      (node (ref "C27") (pin "2") (pinfunction "2_2") (pintype "passive"))
      (node (ref "C32") (pin "2") (pinfunction "2_2") (pintype "passive"))
      (node (ref "C326") (pin "2") (pinfunction "2_2") (pintype "passive"))
      (node (ref "C331") (pin "2") (pinfunction "2_2") (pintype "passive"))
      (node (ref "C336") (pin "2") (pinfunction "2_2") (pintype "passive"))
      (node (ref "C341") (pin "2") (pinfunction "2_2") (pintype "passive"))
      (node (ref "C37") (pin "2") (pinfunction "2_2") (pintype "passive"))
      (node (ref "C42") (pin "2") (pinfunction "2_2") (pintype "passive"))
      (node (ref "R5") (pin "1") (pinfunction "1_1") (pintype "passive"))
      (node (ref "U10") (pin "57") (pinfunction "RSTN_57") (pintype "passive"))
      (node (ref "U11") (pin "57") (pinfunction "RSTN_57") (pintype "passive"))
      (node (ref "U12") (pin "57") (pinfunction "RSTN_57") (pintype "passive"))
      (node (ref "U18") (pin "57") (pinfunction "RSTN_57") (pintype "passive"))
      (node (ref "U19") (pin "57") (pinfunction "RSTN_57") (pintype "passive"))
      (node (ref "U20") (pin "57") (pinfunction "RSTN_57") (pintype "passive"))
      (node (ref "U21") (pin "57") (pinfunction "RSTN_57") (pintype "passive"))
      (node (ref "U24") (pin "57") (pinfunction "RSTN_57") (pintype "passive"))
      (node (ref "U25") (pin "57") (pinfunction "RSTN_57") (pintype "passive"))
      (node (ref "U26") (pin "57") (pinfunction "RSTN_57") (pintype "passive"))
      (node (ref "U27") (pin "57") (pinfunction "RSTN_57") (pintype "passive"))
      (node (ref "U4") (pin "57") (pinfunction "RSTN_57") (pintype "passive"))
      (node (ref "U5") (pin "57") (pinfunction "RSTN_57") (pintype "passive"))
      (node (ref "U6") (pin "57") (pinfunction "RSTN_57") (pintype "passive"))
      (node (ref "U7") (pin "57") (pinfunction "RSTN_57") (pintype "passive"))
      (node (ref "U8") (pin "5") (pinfunction "C1IN1-/SDI2/PMA4/RPI119/RG7_5") (pintype "passive"))
      (node (ref "U9") (pin "57") (pinfunction "RSTN_57") (pintype "passive"))
    )
    (net (code "6") (name "/BOOT1") (class "Default")
      (node (ref "C7") (pin "1") (pinfunction "1_1") (pintype "passive"))
      (node (ref "D1") (pin "3") (pinfunction "CC_3") (pintype "passive"))
      (node (ref "U1") (pin "8") (pinfunction "BOOST_8") (pintype "passive"))
    )
    (net (code "7") (name "/BOOT2") (class "Default")
      (node (ref "C8") (pin "1") (pinfunction "1_1") (pintype "passive"))
      (node (ref "D2") (pin "3") (pinfunction "CC_3") (pintype "passive"))
      (node (ref "U2") (pin "8") (pinfunction "BOOST_8") (pintype "passive"))
    )
    (net (code "8") (name "/BOOT3") (class "Default")
      (node (ref "C9") (pin "1") (pinfunction "1_1") (pintype "passive"))
      (node (ref "D3") (pin "3") (pinfunction "CC_3") (pintype "passive"))
      (node (ref "U3") (pin "8") (pinfunction "BOOST_8") (pintype "passive"))
    )
    (net (code "9") (name "/CORE_CLKOUT_1") (class "Default")
      (node (ref "R1") (pin "2") (pinfunction "2_2") (pintype "passive"))
      (node (ref "U4") (pin "56") (pinfunction "CORE_CLKOUT_56") (pintype "passive"))
    )
    (net (code "10") (name "/CORE_CLKOUT_2") (class "Default")
      (node (ref "R2") (pin "2") (pinfunction "2_2") (pintype "passive"))
      (node (ref "U5") (pin "56") (pinfunction "CORE_CLKOUT_56") (pintype "passive"))
    )
    (net (code "11") (name "/CORE_CLKOUT_3") (class "Default")
      (node (ref "R3") (pin "2") (pinfunction "2_2") (pintype "passive"))
      (node (ref "U6") (pin "56") (pinfunction "CORE_CLKOUT_56") (pintype "passive"))
    )
    (net (code "12") (name "/CORE_CLKOUT_4") (class "Default")
      (node (ref "R4") (pin "2") (pinfunction "2_2") (pintype "passive"))
      (node (ref "U7") (pin "56") (pinfunction "CORE_CLKOUT_56") (pintype "passive"))
    )
    (net (code "13") (name "/CORE_CLKOUT_5") (class "Default")
      (node (ref "R17") (pin "1") (pinfunction "1_1") (pintype "passive"))
      (node (ref "U9") (pin "56") (pinfunction "CORE_CLKOUT_56") (pintype "passive"))
    )
    (net (code "14") (name "/CORE_CLKOUT_6") (class "Default")
      (node (ref "R18") (pin "2") (pinfunction "2_2") (pintype "passive"))
      (node (ref "U10") (pin "56") (pinfunction "CORE_CLKOUT_56") (pintype "passive"))
    )
    (net (code "15") (name "/CORE_CLKOUT_7") (class "Default")
      (node (ref "R19") (pin "2") (pinfunction "2_2") (pintype "passive"))
      (node (ref "U11") (pin "56") (pinfunction "CORE_CLKOUT_56") (pintype "passive"))
    )
    (net (code "16") (name "/CORE_CLKOUT_8") (class "Default")
      (node (ref "R20") (pin "2") (pinfunction "2_2") (pintype "passive"))
      (node (ref "U12") (pin "56") (pinfunction "CORE_CLKOUT_56") (pintype "passive"))
    )
    (net (code "17") (name "/CORE_CLKOUT_9") (class "Default")
      (node (ref "R43") (pin "2") (pinfunction "2_2") (pintype "passive"))
      (node (ref "U18") (pin "56") (pinfunction "CORE_CLKOUT_56") (pintype "passive"))
    )
    (net (code "18") (name "/CORE_CLKOUT_10") (class "Default")
      (node (ref "R44") (pin "2") (pinfunction "2_2") (pintype "passive"))
      (node (ref "U19") (pin "56") (pinfunction "CORE_CLKOUT_56") (pintype "passive"))
    )
    (net (code "19") (name "/CORE_CLKOUT_11") (class "Default")
      (node (ref "R45") (pin "2") (pinfunction "2_2") (pintype "passive"))
      (node (ref "U20") (pin "56") (pinfunction "CORE_CLKOUT_56") (pintype "passive"))
    )
    (net (code "20") (name "/CORE_CLKOUT_12") (class "Default")
      (node (ref "R46") (pin "2") (pinfunction "2_2") (pintype "passive"))
      (node (ref "U21") (pin "56") (pinfunction "CORE_CLKOUT_56") (pintype "passive"))
    )
    (net (code "21") (name "/CORE_CLKOUT_13") (class "Default")
      (node (ref "R64") (pin "2") (pinfunction "2_2") (pintype "passive"))
      (node (ref "U24") (pin "56") (pinfunction "CORE_CLKOUT_56") (pintype "passive"))
    )
    (net (code "22") (name "/CORE_CLKOUT_14") (class "Default")
      (node (ref "R65") (pin "2") (pinfunction "2_2") (pintype "passive"))
      (node (ref "U25") (pin "56") (pinfunction "CORE_CLKOUT_56") (pintype "passive"))
    )
    (net (code "23") (name "/CORE_CLKOUT_15") (class "Default")
      (node (ref "R66") (pin "2") (pinfunction "2_2") (pintype "passive"))
      (node (ref "U26") (pin "56") (pinfunction "CORE_CLKOUT_56") (pintype "passive"))
    )
    (net (code "24") (name "/CORE_CLKOUT_16") (class "Default")
      (node (ref "R67") (pin "2") (pinfunction "2_2") (pintype "passive"))
      (node (ref "U27") (pin "56") (pinfunction "CORE_CLKOUT_56") (pintype "passive"))
    )
    (net (code "25") (name "/D+") (class "Default")
      (node (ref "D9") (pin "1") (pinfunction "1_1") (pintype "passive"))
      (node (ref "J2") (pin "3") (pinfunction "3_3") (pintype "passive"))
      (node (ref "U8") (pin "37") (pinfunction "D+/RG2_37") (pintype "passive"))
    )
    (net (code "26") (name "/D-") (class "Default")
      (node (ref "D9") (pin "3") (pinfunction "3_3") (pintype "passive"))
      (node (ref "J2") (pin "2") (pinfunction "2_2") (pintype "passive"))
      (node (ref "U8") (pin "36") (pinfunction "D-/RG3_36") (pintype "passive"))
    )
    (net (code "27") (name "/DRVLogic") (class "Default")
      (node (ref "C4") (pin "1") (pinfunction "1_1") (pintype "passive"))
      (node (ref "C5") (pin "1") (pinfunction "1_1") (pintype "passive"))
      (node (ref "C6") (pin "1") (pinfunction "1_1") (pintype "passive"))
      (node (ref "U1") (pin "6") (pinfunction "VLOGIC_6") (pintype "passive"))
      (node (ref "U2") (pin "6") (pinfunction "VLOGIC_6") (pintype "passive"))
      (node (ref "U3") (pin "6") (pinfunction "VLOGIC_6") (pintype "passive"))
      (node (ref "U8") (pin "55") (pinfunction "C3IN1+/VCMPST3/RP71/RD7_55") (pintype "passive"))
    )
    (net (code "28") (name "/FB") (class "Default")
      (node (ref "C166") (pin "1") (pinfunction "1_1") (pintype "passive"))
      (node (ref "R26") (pin "1") (pinfunction "1_1") (pintype "passive"))
      (node (ref "U8") (pin "17") (pinfunction "PGEC1/AN6/RPI38/RB6_17") (pintype "passive"))
    )
    (net (code "29") (name "/GREEN") (class "Default")
      (node (ref "D5") (pin "2") (pinfunction "A_2") (pintype "passive"))
      (node (ref "U8") (pin "47") (pinfunction "PGED2/SOSCI/C3IN3-/RPI61/RC13_47") (pintype "passive"))
    )
    (net (code "30") (name "/HO1") (class "Default")
      (node (ref "Q2") (pin "4") (pinfunction "G_4") (pintype "passive"))
      (node (ref "U1") (pin "1") (pinfunction "TG_1") (pintype "passive"))
    )
    (net (code "31") (name "/HO2") (class "Default")
      (node (ref "Q3") (pin "4") (pinfunction "G_4") (pintype "passive"))
      (node (ref "U2") (pin "1") (pinfunction "TG_1") (pintype "passive"))
    )
    (net (code "32") (name "/HO3") (class "Default")
      (node (ref "Q1") (pin "4") (pinfunction "G_4") (pintype "passive"))
      (node (ref "U3") (pin "1") (pinfunction "TG_1") (pintype "passive"))
    )
    (net (code "33") (name "/LDO3.3V-5.0V") (class "Default")
      (node (ref "R48") (pin "1") (pinfunction "1_1") (pintype "passive"))
      (node (ref "R49") (pin "1") (pinfunction "1_1") (pintype "passive"))
      (node (ref "U22") (pin "5") (pinfunction "CTL_5") (pintype "passive"))
      (node (ref "U22") (pin "8") (pinfunction "VCC_8") (pintype "passive"))
      (node (ref "U23") (pin "5") (pinfunction "CTL_5") (pintype "passive"))
      (node (ref "U23") (pin "8") (pinfunction "VCC_8") (pintype "passive"))
    )
    (net (code "34") (name "/LDO5.0V") (class "Default")
      (node (ref "C226") (pin "1") (pinfunction "1_1") (pintype "passive"))
      (node (ref "D10") (pin "2") (pinfunction "A_2") (pintype "passive"))
      (node (ref "D8") (pin "1") (pinfunction "C_1") (pintype "passive"))
      (node (ref "R33") (pin "1") (pinfunction "1_1") (pintype "passive"))
      (node (ref "R42") (pin "2") (pinfunction "2_2") (pintype "passive"))
      (node (ref "R49") (pin "2") (pinfunction "2_2") (pintype "passive"))
      (node (ref "U14") (pin "1") (pinfunction "IN_1") (pintype "passive"))
      (node (ref "U14") (pin "3") (pinfunction "EN_3") (pintype "passive"))
      (node (ref "U15") (pin "5") (pinfunction "CTL_5") (pintype "passive"))
      (node (ref "U15") (pin "8") (pinfunction "VCC_8") (pintype "passive"))
    )
    (net (code "35") (name "/LM12V") (class "Default")
      (node (ref "D11") (pin "1") (pinfunction "C_1") (pintype "passive"))
      (node (ref "R47") (pin "1") (pinfunction "1_1") (pintype "passive"))
      (node (ref "U13") (pin "8") (pinfunction "INPUT_8") (pintype "passive"))
      (node (ref "U16") (pin "1") (pinfunction "Vin_1") (pintype "passive"))
      (node (ref "U17") (pin "1") (pinfunction "Vin_1") (pintype "passive"))
    )
    (net (code "36") (name "/LO1") (class "Default")
      (node (ref "Q6") (pin "4") (pinfunction "G_4") (pintype "passive"))
      (node (ref "Q7") (pin "4") (pinfunction "G_4") (pintype "passive"))
      (node (ref "U1") (pin "3") (pinfunction "BG_3") (pintype "passive"))
    )
    (net (code "37") (name "/LO2") (class "Default")
      (node (ref "Q8") (pin "4") (pinfunction "G_4") (pintype "passive"))
      (node (ref "Q9") (pin "4") (pinfunction "G_4") (pintype "passive"))
      (node (ref "U2") (pin "3") (pinfunction "BG_3") (pintype "passive"))
    )
    (net (code "38") (name "/LO3") (class "Default")
      (node (ref "Q4") (pin "4") (pinfunction "G_4") (pintype "passive"))
      (node (ref "Q5") (pin "4") (pinfunction "G_4") (pintype "passive"))
      (node (ref "U3") (pin "3") (pinfunction "BG_3") (pintype "passive"))
    )
    (net (code "39") (name "/LTC_EN") (class "Default")
      (node (ref "R6") (pin "1") (pinfunction "1_1") (pintype "passive"))
      (node (ref "U10") (pin "47") (pinfunction "LTC_EN_47") (pintype "passive"))
      (node (ref "U11") (pin "47") (pinfunction "LTC_EN_47") (pintype "passive"))
      (node (ref "U12") (pin "47") (pinfunction "LTC_EN_47") (pintype "passive"))
      (node (ref "U18") (pin "47") (pinfunction "LTC_EN_47") (pintype "passive"))
      (node (ref "U19") (pin "47") (pinfunction "LTC_EN_47") (pintype "passive"))
      (node (ref "U20") (pin "47") (pinfunction "LTC_EN_47") (pintype "passive"))
      (node (ref "U21") (pin "47") (pinfunction "LTC_EN_47") (pintype "passive"))
      (node (ref "U24") (pin "47") (pinfunction "LTC_EN_47") (pintype "passive"))
      (node (ref "U25") (pin "47") (pinfunction "LTC_EN_47") (pintype "passive"))
      (node (ref "U26") (pin "47") (pinfunction "LTC_EN_47") (pintype "passive"))
      (node (ref "U27") (pin "47") (pinfunction "LTC_EN_47") (pintype "passive"))
      (node (ref "U4") (pin "47") (pinfunction "LTC_EN_47") (pintype "passive"))
      (node (ref "U5") (pin "47") (pinfunction "LTC_EN_47") (pintype "passive"))
      (node (ref "U6") (pin "47") (pinfunction "LTC_EN_47") (pintype "passive"))
      (node (ref "U7") (pin "47") (pinfunction "LTC_EN_47") (pintype "passive"))
      (node (ref "U8") (pin "23") (pinfunction "TMS/AN10/CVREF/PMA13/RPI42/RB10_23") (pintype "passive"))
      (node (ref "U9") (pin "47") (pinfunction "LTC_EN_47") (pintype "passive"))
    )
    (net (code "40") (name "/MCLR") (class "Default")
      (node (ref "C168") (pin "1") (pinfunction "1_1") (pintype "passive"))
      (node (ref "J1") (pin "1") (pinfunction "1_1") (pintype "passive"))
      (node (ref "R31") (pin "1") (pinfunction "1_1") (pintype "passive"))
      (node (ref "U8") (pin "7") (pinfunction "~{MCLR}_7") (pintype "passive"))
    )
    (net (code "41") (name "/MCU5.0V") (class "Default")
      (node (ref "R32") (pin "2") (pinfunction "2_2") (pintype "passive"))
      (node (ref "U8") (pin "34") (pinfunction "VBUS_34") (pintype "passive"))
    )
    (net (code "42") (name "/MEAS12") (class "Default")
      (node (ref "C138") (pin "1") (pinfunction "1_1") (pintype "passive"))
      (node (ref "R23") (pin "2") (pinfunction "2_2") (pintype "passive"))
      (node (ref "R25") (pin "2") (pinfunction "2_2") (pintype "passive"))
      (node (ref "U8") (pin "18") (pinfunction "PGED1/AN7/RCV/RPI39/RB7_18") (pintype "passive"))
    )
    (net (code "43") (name "/Main OSC In") (class "Default")
      (node (ref "C173") (pin "1") (pinfunction "1_1") (pintype "passive"))
      (node (ref "U8") (pin "39") (pinfunction "OSC1/RPI60/RC12_39") (pintype "passive"))
      (node (ref "Y1") (pin "1") (pinfunction "1_1") (pintype "passive"))
    )
    (net (code "44") (name "/Main OSC Out") (class "Default")
      (node (ref "C174") (pin "1") (pinfunction "1_1") (pintype "passive"))
      (node (ref "U8") (pin "40") (pinfunction "OSC2/CLKO/RC15_40") (pintype "passive"))
      (node (ref "Y1") (pin "2") (pinfunction "2_2") (pintype "passive"))
    )
    (net (code "45") (name "/ORANGE") (class "Default")
      (node (ref "D7") (pin "2") (pinfunction "A_2") (pintype "passive"))
      (node (ref "U8") (pin "45") (pinfunction "PMCS1/RPI75/RD11_45") (pintype "passive"))
    )
    (net (code "46") (name "/PGC") (class "Default")
      (node (ref "J1") (pin "5") (pinfunction "5_5") (pintype "passive"))
      (node (ref "U8") (pin "15") (pinfunction "PGEC3/AN1/VREF-/RPI33/RB1_15") (pintype "passive"))
    )
    (net (code "47") (name "/PGD") (class "Default")
      (node (ref "J1") (pin "4") (pinfunction "4_4") (pintype "passive"))
      (node (ref "U8") (pin "16") (pinfunction "PGED3/AN0/VREF+/RPI32/RB0_16") (pintype "passive"))
    )
    (net (code "48") (name "/PLL_SUP") (class "Default")
      (node (ref "C259") (pin "1") (pinfunction "1_1") (pintype "passive"))
      (node (ref "C260") (pin "1") (pinfunction "1_1") (pintype "passive"))
      (node (ref "C274") (pin "1") (pinfunction "1_1") (pintype "passive"))
      (node (ref "FB1") (pin "1") (pinfunction "1_1") (pintype "passive"))
      (node (ref "R50") (pin "1") (pinfunction "1_1") (pintype "passive"))
      (node (ref "R52") (pin "1") (pinfunction "1_1") (pintype "passive"))
      (node (ref "U22") (pin "1") (pinfunction "OUT_1") (pintype "passive"))
      (node (ref "U23") (pin "1") (pinfunction "OUT_1") (pintype "passive"))
    )
    (net (code "49") (name "/PWM2H") (class "Default")
      (node (ref "R22") (pin "1") (pinfunction "1_1") (pintype "passive"))
      (node (ref "U2") (pin "5") (pinfunction "IN_5") (pintype "passive"))
      (node (ref "U8") (pin "63") (pinfunction "AN27/PWM2H/PMD3/RPI83/RE3_63") (pintype "passive"))
    )
    (net (code "50") (name "/PWM2L") (class "Default")
      (node (ref "R24") (pin "1") (pinfunction "1_1") (pintype "passive"))
      (node (ref "U1") (pin "5") (pinfunction "IN_5") (pintype "passive"))
      (node (ref "U8") (pin "62") (pinfunction "AN26/PWM2L/PMD2/RP82/RE2_62") (pintype "passive"))
    )
    (net (code "51") (name "/PWM3L") (class "Default")
      (node (ref "R21") (pin "1") (pinfunction "1_1") (pintype "passive"))
      (node (ref "U3") (pin "5") (pinfunction "IN_5") (pintype "passive"))
      (node (ref "U8") (pin "64") (pinfunction "AN28/PWM3L/PMD4/RP84/RE4_64") (pintype "passive"))
    )
    (net (code "52") (name "/RED") (class "Default")
      (node (ref "D4") (pin "2") (pinfunction "A_2") (pintype "passive"))
      (node (ref "U8") (pin "48") (pinfunction "PGEC2/SOSCO/C3IN1-/T1CK/RPI62/RC14_48") (pintype "passive"))
    )
    (net (code "53") (name "/RX_BTC_0") (class "Default")
      (node (ref "U10") (pin "1") (pinfunction "CFG_P_1") (pintype "passive"))
      (node (ref "U11") (pin "1") (pinfunction "CFG_P_1") (pintype "passive"))
      (node (ref "U12") (pin "1") (pinfunction "CFG_P_1") (pintype "passive"))
      (node (ref "U4") (pin "1") (pinfunction "CFG_P_1") (pintype "passive"))
      (node (ref "U5") (pin "1") (pinfunction "CFG_P_1") (pintype "passive"))
      (node (ref "U6") (pin "1") (pinfunction "CFG_P_1") (pintype "passive"))
      (node (ref "U7") (pin "1") (pinfunction "CFG_P_1") (pintype "passive"))
      (node (ref "U8") (pin "59") (pinfunction "VCMPST2/RP97/RF1_59") (pintype "passive"))
      (node (ref "U9") (pin "1") (pinfunction "CFG_P_1") (pintype "passive"))
    )
    (net (code "54") (name "/RX_BTC_1") (class "Default")
      (node (ref "U18") (pin "1") (pinfunction "CFG_P_1") (pintype "passive"))
      (node (ref "U19") (pin "1") (pinfunction "CFG_P_1") (pintype "passive"))
      (node (ref "U20") (pin "1") (pinfunction "CFG_P_1") (pintype "passive"))
      (node (ref "U21") (pin "1") (pinfunction "CFG_P_1") (pintype "passive"))
      (node (ref "U24") (pin "1") (pinfunction "CFG_P_1") (pintype "passive"))
      (node (ref "U25") (pin "1") (pinfunction "CFG_P_1") (pintype "passive"))
      (node (ref "U26") (pin "1") (pinfunction "CFG_P_1") (pintype "passive"))
      (node (ref "U27") (pin "1") (pinfunction "CFG_P_1") (pintype "passive"))
      (node (ref "U8") (pin "3") (pinfunction "AN31/PWM4H/PMD7/RP87/RE7_3") (pintype "passive"))
    )
    (net (code "55") (name "/RX_LTC_0") (class "Default")
      (node (ref "U10") (pin "2") (pinfunction "CFG_N_2") (pintype "passive"))
      (node (ref "U11") (pin "2") (pinfunction "CFG_N_2") (pintype "passive"))
      (node (ref "U12") (pin "2") (pinfunction "CFG_N_2") (pintype "passive"))
      (node (ref "U4") (pin "2") (pinfunction "CFG_N_2") (pintype "passive"))
      (node (ref "U5") (pin "2") (pinfunction "CFG_N_2") (pintype "passive"))
      (node (ref "U6") (pin "2") (pinfunction "CFG_N_2") (pintype "passive"))
      (node (ref "U7") (pin "2") (pinfunction "CFG_N_2") (pintype "passive"))
      (node (ref "U8") (pin "58") (pinfunction "VCMPST1/RP96/RF0_58") (pintype "passive"))
      (node (ref "U9") (pin "2") (pinfunction "CFG_N_2") (pintype "passive"))
    )
    (net (code "56") (name "/RX_LTC_1") (class "Default")
      (node (ref "U18") (pin "2") (pinfunction "CFG_N_2") (pintype "passive"))
      (node (ref "U19") (pin "2") (pinfunction "CFG_N_2") (pintype "passive"))
      (node (ref "U20") (pin "2") (pinfunction "CFG_N_2") (pintype "passive"))
      (node (ref "U21") (pin "2") (pinfunction "CFG_N_2") (pintype "passive"))
      (node (ref "U24") (pin "2") (pinfunction "CFG_N_2") (pintype "passive"))
      (node (ref "U25") (pin "2") (pinfunction "CFG_N_2") (pintype "passive"))
      (node (ref "U26") (pin "2") (pinfunction "CFG_N_2") (pintype "passive"))
      (node (ref "U27") (pin "2") (pinfunction "CFG_N_2") (pintype "passive"))
      (node (ref "U8") (pin "4") (pinfunction "C1IN3-/SCK2/PMA5/RP118/RG6_4") (pintype "passive"))
    )
    (net (code "57") (name "/SWN1") (class "Default")
      (node (ref "C7") (pin "2") (pinfunction "2_2") (pintype "passive"))
      (node (ref "L1") (pin "1") (pinfunction "1_1") (pintype "passive"))
      (node (ref "Q2") (pin "1") (pinfunction "S_1") (pintype "passive"))
      (node (ref "Q2") (pin "2") (pinfunction "S_2") (pintype "passive"))
      (node (ref "Q2") (pin "3") (pinfunction "S_3") (pintype "passive"))
      (node (ref "Q6") (pin "5") (pinfunction "D_5") (pintype "passive"))
      (node (ref "Q6") (pin "6") (pinfunction "D_6") (pintype "passive"))
      (node (ref "Q6") (pin "7") (pinfunction "D_7") (pintype "passive"))
      (node (ref "Q6") (pin "8") (pinfunction "D_8") (pintype "passive"))
      (node (ref "Q7") (pin "5") (pinfunction "D_5") (pintype "passive"))
      (node (ref "Q7") (pin "6") (pinfunction "D_6") (pintype "passive"))
      (node (ref "Q7") (pin "7") (pinfunction "D_7") (pintype "passive"))
      (node (ref "Q7") (pin "8") (pinfunction "D_8") (pintype "passive"))
      (node (ref "U1") (pin "2") (pinfunction "TS_2") (pintype "passive"))
    )
    (net (code "58") (name "/SWN2") (class "Default")
      (node (ref "C8") (pin "2") (pinfunction "2_2") (pintype "passive"))
      (node (ref "L2") (pin "1") (pinfunction "1_1") (pintype "passive"))
      (node (ref "Q3") (pin "1") (pinfunction "S_1") (pintype "passive"))
      (node (ref "Q3") (pin "2") (pinfunction "S_2") (pintype "passive"))
      (node (ref "Q3") (pin "3") (pinfunction "S_3") (pintype "passive"))
      (node (ref "Q8") (pin "5") (pinfunction "D_5") (pintype "passive"))
      (node (ref "Q8") (pin "6") (pinfunction "D_6") (pintype "passive"))
      (node (ref "Q8") (pin "7") (pinfunction "D_7") (pintype "passive"))
      (node (ref "Q8") (pin "8") (pinfunction "D_8") (pintype "passive"))
      (node (ref "Q9") (pin "5") (pinfunction "D_5") (pintype "passive"))
      (node (ref "Q9") (pin "6") (pinfunction "D_6") (pintype "passive"))
      (node (ref "Q9") (pin "7") (pinfunction "D_7") (pintype "passive"))
      (node (ref "Q9") (pin "8") (pinfunction "D_8") (pintype "passive"))
      (node (ref "U2") (pin "2") (pinfunction "TS_2") (pintype "passive"))
    )
    (net (code "59") (name "/SWN3") (class "Default")
      (node (ref "C9") (pin "2") (pinfunction "2_2") (pintype "passive"))
      (node (ref "L3") (pin "1") (pinfunction "1_1") (pintype "passive"))
      (node (ref "Q1") (pin "1") (pinfunction "S_1") (pintype "passive"))
      (node (ref "Q1") (pin "2") (pinfunction "S_2") (pintype "passive"))
      (node (ref "Q1") (pin "3") (pinfunction "S_3") (pintype "passive"))
      (node (ref "Q4") (pin "5") (pinfunction "D_5") (pintype "passive"))
      (node (ref "Q4") (pin "6") (pinfunction "D_6") (pintype "passive"))
      (node (ref "Q4") (pin "7") (pinfunction "D_7") (pintype "passive"))
      (node (ref "Q4") (pin "8") (pinfunction "D_8") (pintype "passive"))
      (node (ref "Q5") (pin "5") (pinfunction "D_5") (pintype "passive"))
      (node (ref "Q5") (pin "6") (pinfunction "D_6") (pintype "passive"))
      (node (ref "Q5") (pin "7") (pinfunction "D_7") (pintype "passive"))
      (node (ref "Q5") (pin "8") (pinfunction "D_8") (pintype "passive"))
      (node (ref "U3") (pin "2") (pinfunction "TS_2") (pintype "passive"))
    )
    (net (code "60") (name "/TP1011") (class "Default")
      (node (ref "TP5") (pin "1") (pinfunction "1_1") (pintype "passive"))
      (node (ref "U4") (pin "25") (pinfunction "RPT_BUSYN_25") (pintype "passive"))
    )
    (net (code "61") (name "/TP1012") (class "Default")
      (node (ref "TP6") (pin "1") (pinfunction "1_1") (pintype "passive"))
      (node (ref "U5") (pin "25") (pinfunction "RPT_BUSYN_25") (pintype "passive"))
    )
    (net (code "62") (name "/TP1013") (class "Default")
      (node (ref "TP7") (pin "1") (pinfunction "1_1") (pintype "passive"))
      (node (ref "U6") (pin "25") (pinfunction "RPT_BUSYN_25") (pintype "passive"))
    )
    (net (code "63") (name "/TP1014") (class "Default")
      (node (ref "TP8") (pin "1") (pinfunction "1_1") (pintype "passive"))
      (node (ref "U7") (pin "25") (pinfunction "RPT_BUSYN_25") (pintype "passive"))
    )
    (net (code "64") (name "/TP1015") (class "Default")
      (node (ref "TP32") (pin "1") (pinfunction "1_1") (pintype "passive"))
      (node (ref "U9") (pin "25") (pinfunction "RPT_BUSYN_25") (pintype "passive"))
    )
    (net (code "65") (name "/TP1016") (class "Default")
      (node (ref "TP33") (pin "1") (pinfunction "1_1") (pintype "passive"))
      (node (ref "U10") (pin "25") (pinfunction "RPT_BUSYN_25") (pintype "passive"))
    )
    (net (code "66") (name "/TP1017") (class "Default")
      (node (ref "TP34") (pin "1") (pinfunction "1_1") (pintype "passive"))
      (node (ref "U11") (pin "25") (pinfunction "RPT_BUSYN_25") (pintype "passive"))
    )
    (net (code "67") (name "/TP1018") (class "Default")
      (node (ref "TP35") (pin "1") (pinfunction "1_1") (pintype "passive"))
      (node (ref "U12") (pin "25") (pinfunction "RPT_BUSYN_25") (pintype "passive"))
    )
    (net (code "68") (name "/TP1019") (class "Default")
      (node (ref "TP40") (pin "1") (pinfunction "1_1") (pintype "passive"))
      (node (ref "U18") (pin "25") (pinfunction "RPT_BUSYN_25") (pintype "passive"))
    )
    (net (code "69") (name "/TP10110") (class "Default")
      (node (ref "TP41") (pin "1") (pinfunction "1_1") (pintype "passive"))
      (node (ref "U19") (pin "25") (pinfunction "RPT_BUSYN_25") (pintype "passive"))
    )
    (net (code "70") (name "/TP10111") (class "Default")
      (node (ref "TP42") (pin "1") (pinfunction "1_1") (pintype "passive"))
      (node (ref "U20") (pin "25") (pinfunction "RPT_BUSYN_25") (pintype "passive"))
    )
    (net (code "71") (name "/TP10112") (class "Default")
      (node (ref "TP43") (pin "1") (pinfunction "1_1") (pintype "passive"))
      (node (ref "U21") (pin "25") (pinfunction "RPT_BUSYN_25") (pintype "passive"))
    )
    (net (code "72") (name "/TP10113") (class "Default")
      (node (ref "TP49") (pin "1") (pinfunction "1_1") (pintype "passive"))
      (node (ref "U24") (pin "25") (pinfunction "RPT_BUSYN_25") (pintype "passive"))
    )
    (net (code "73") (name "/TP10114") (class "Default")
      (node (ref "TP50") (pin "1") (pinfunction "1_1") (pintype "passive"))
      (node (ref "U25") (pin "25") (pinfunction "RPT_BUSYN_25") (pintype "passive"))
    )
    (net (code "74") (name "/TP10115") (class "Default")
      (node (ref "TP51") (pin "1") (pinfunction "1_1") (pintype "passive"))
      (node (ref "U26") (pin "25") (pinfunction "RPT_BUSYN_25") (pintype "passive"))
    )
    (net (code "75") (name "/TP10116") (class "Default")
      (node (ref "TP52") (pin "1") (pinfunction "1_1") (pintype "passive"))
      (node (ref "U27") (pin "25") (pinfunction "RPT_BUSYN_25") (pintype "passive"))
    )
    (net (code "76") (name "/TP_1001") (class "Default")
      (node (ref "TP1") (pin "1") (pinfunction "1_1") (pintype "passive"))
      (node (ref "U4") (pin "48") (pinfunction "LTC_BUSYN_48") (pintype "passive"))
    )
    (net (code "77") (name "/TP_1002") (class "Default")
      (node (ref "TP2") (pin "1") (pinfunction "1_1") (pintype "passive"))
      (node (ref "U5") (pin "48") (pinfunction "LTC_BUSYN_48") (pintype "passive"))
    )
    (net (code "78") (name "/TP_1003") (class "Default")
      (node (ref "TP3") (pin "1") (pinfunction "1_1") (pintype "passive"))
      (node (ref "U6") (pin "48") (pinfunction "LTC_BUSYN_48") (pintype "passive"))
    )
    (net (code "79") (name "/TP_1004") (class "Default")
      (node (ref "TP4") (pin "1") (pinfunction "1_1") (pintype "passive"))
      (node (ref "U7") (pin "48") (pinfunction "LTC_BUSYN_48") (pintype "passive"))
    )
    (net (code "80") (name "/TP_1005") (class "Default")
      (node (ref "TP13") (pin "1") (pinfunction "1_1") (pintype "passive"))
      (node (ref "U9") (pin "48") (pinfunction "LTC_BUSYN_48") (pintype "passive"))
    )
    (net (code "81") (name "/TP_1006") (class "Default")
      (node (ref "TP14") (pin "1") (pinfunction "1_1") (pintype "passive"))
      (node (ref "U10") (pin "48") (pinfunction "LTC_BUSYN_48") (pintype "passive"))
    )
    (net (code "82") (name "/TP_1007") (class "Default")
      (node (ref "TP15") (pin "1") (pinfunction "1_1") (pintype "passive"))
      (node (ref "U11") (pin "48") (pinfunction "LTC_BUSYN_48") (pintype "passive"))
    )
    (net (code "83") (name "/TP_1008") (class "Default")
      (node (ref "TP16") (pin "1") (pinfunction "1_1") (pintype "passive"))
      (node (ref "U12") (pin "48") (pinfunction "LTC_BUSYN_48") (pintype "passive"))
    )
    (net (code "84") (name "/TP_1009") (class "Default")
      (node (ref "TP36") (pin "1") (pinfunction "1_1") (pintype "passive"))
      (node (ref "U18") (pin "48") (pinfunction "LTC_BUSYN_48") (pintype "passive"))
    )
    (net (code "85") (name "/TP_10010") (class "Default")
      (node (ref "TP37") (pin "1") (pinfunction "1_1") (pintype "passive"))
      (node (ref "U19") (pin "48") (pinfunction "LTC_BUSYN_48") (pintype "passive"))
    )
    (net (code "86") (name "/TP_10011") (class "Default")
      (node (ref "TP38") (pin "1") (pinfunction "1_1") (pintype "passive"))
      (node (ref "U20") (pin "48") (pinfunction "LTC_BUSYN_48") (pintype "passive"))
    )
    (net (code "87") (name "/TP_10012") (class "Default")
      (node (ref "TP39") (pin "1") (pinfunction "1_1") (pintype "passive"))
      (node (ref "U21") (pin "48") (pinfunction "LTC_BUSYN_48") (pintype "passive"))
    )
    (net (code "88") (name "/TP_10013") (class "Default")
      (node (ref "TP44") (pin "1") (pinfunction "1_1") (pintype "passive"))
      (node (ref "U24") (pin "48") (pinfunction "LTC_BUSYN_48") (pintype "passive"))
    )
    (net (code "89") (name "/TP_10014") (class "Default")
      (node (ref "TP45") (pin "1") (pinfunction "1_1") (pintype "passive"))
      (node (ref "U25") (pin "48") (pinfunction "LTC_BUSYN_48") (pintype "passive"))
    )
    (net (code "90") (name "/TP_10015") (class "Default")
      (node (ref "TP46") (pin "1") (pinfunction "1_1") (pintype "passive"))
      (node (ref "U26") (pin "48") (pinfunction "LTC_BUSYN_48") (pintype "passive"))
    )
    (net (code "91") (name "/TP_10016") (class "Default")
      (node (ref "TP47") (pin "1") (pinfunction "1_1") (pintype "passive"))
      (node (ref "U27") (pin "48") (pinfunction "LTC_BUSYN_48") (pintype "passive"))
    )
    (net (code "92") (name "/TX_BTC_0") (class "Default")
      (node (ref "R7") (pin "1") (pinfunction "1_1") (pintype "passive"))
      (node (ref "U10") (pin "24") (pinfunction "RPT_P_24") (pintype "passive"))
      (node (ref "U11") (pin "24") (pinfunction "RPT_P_24") (pintype "passive"))
      (node (ref "U12") (pin "24") (pinfunction "RPT_P_24") (pintype "passive"))
      (node (ref "U4") (pin "24") (pinfunction "RPT_P_24") (pintype "passive"))
      (node (ref "U5") (pin "24") (pinfunction "RPT_P_24") (pintype "passive"))
      (node (ref "U6") (pin "24") (pinfunction "RPT_P_24") (pintype "passive"))
      (node (ref "U7") (pin "24") (pinfunction "RPT_P_24") (pintype "passive"))
      (node (ref "U8") (pin "61") (pinfunction "AN25/PWM1H/PMD1/RPI81/RE1_61") (pintype "passive"))
      (node (ref "U9") (pin "24") (pinfunction "RPT_P_24") (pintype "passive"))
    )
    (net (code "93") (name "/TX_BTC_1") (class "Default")
      (node (ref "R53") (pin "1") (pinfunction "1_1") (pintype "passive"))
      (node (ref "U18") (pin "24") (pinfunction "RPT_P_24") (pintype "passive"))
      (node (ref "U19") (pin "24") (pinfunction "RPT_P_24") (pintype "passive"))
      (node (ref "U20") (pin "24") (pinfunction "RPT_P_24") (pintype "passive"))
      (node (ref "U21") (pin "24") (pinfunction "RPT_P_24") (pintype "passive"))
      (node (ref "U24") (pin "24") (pinfunction "RPT_P_24") (pintype "passive"))
      (node (ref "U25") (pin "24") (pinfunction "RPT_P_24") (pintype "passive"))
      (node (ref "U26") (pin "24") (pinfunction "RPT_P_24") (pintype "passive"))
      (node (ref "U27") (pin "24") (pinfunction "RPT_P_24") (pintype "passive"))
      (node (ref "U8") (pin "1") (pinfunction "AN29/PWM3H/PMD5/RP85/RE5_1") (pintype "passive"))
    )
    (net (code "94") (name "/TX_LTC_0") (class "Default")
      (node (ref "R8") (pin "2") (pinfunction "2_2") (pintype "passive"))
      (node (ref "U10") (pin "23") (pinfunction "RPT_N_23") (pintype "passive"))
      (node (ref "U11") (pin "23") (pinfunction "RPT_N_23") (pintype "passive"))
      (node (ref "U12") (pin "23") (pinfunction "RPT_N_23") (pintype "passive"))
      (node (ref "U4") (pin "23") (pinfunction "RPT_N_23") (pintype "passive"))
      (node (ref "U5") (pin "23") (pinfunction "RPT_N_23") (pintype "passive"))
      (node (ref "U6") (pin "23") (pinfunction "RPT_N_23") (pintype "passive"))
      (node (ref "U7") (pin "23") (pinfunction "RPT_N_23") (pintype "passive"))
      (node (ref "U8") (pin "60") (pinfunction "AN24/PWM1L/PMD0/RP80/RE0_60") (pintype "passive"))
      (node (ref "U9") (pin "23") (pinfunction "RPT_N_23") (pintype "passive"))
    )
    (net (code "95") (name "/TX_LTC_1") (class "Default")
      (node (ref "R54") (pin "2") (pinfunction "2_2") (pintype "passive"))
      (node (ref "U18") (pin "23") (pinfunction "RPT_N_23") (pintype "passive"))
      (node (ref "U19") (pin "23") (pinfunction "RPT_N_23") (pintype "passive"))
      (node (ref "U20") (pin "23") (pinfunction "RPT_N_23") (pintype "passive"))
      (node (ref "U21") (pin "23") (pinfunction "RPT_N_23") (pintype "passive"))
      (node (ref "U24") (pin "23") (pinfunction "RPT_N_23") (pintype "passive"))
      (node (ref "U25") (pin "23") (pinfunction "RPT_N_23") (pintype "passive"))
      (node (ref "U26") (pin "23") (pinfunction "RPT_N_23") (pintype "passive"))
      (node (ref "U27") (pin "23") (pinfunction "RPT_N_23") (pintype "passive"))
      (node (ref "U8") (pin "2") (pinfunction "AN30/PWM4L/PMD6/RPI86/RE6_2") (pintype "passive"))
    )
    (net (code "96") (name "/USB5.0V") (class "Default")
      (node (ref "D9") (pin "4") (pinfunction "4_4") (pintype "passive"))
      (node (ref "D9") (pin "6") (pinfunction "6_6") (pintype "passive"))
      (node (ref "J2") (pin "1") (pinfunction "1_1") (pintype "passive"))
      (node (ref "R32") (pin "1") (pinfunction "1_1") (pintype "passive"))
      (node (ref "R33") (pin "2") (pinfunction "2_2") (pintype "passive"))
    )
    (net (code "97") (name "/VCAP") (class "Default")
      (node (ref "C139") (pin "1") (pinfunction "1_1") (pintype "passive"))
      (node (ref "U8") (pin "56") (pinfunction "VCAP_56") (pintype "passive"))
    )
    (net (code "98") (name "/VDD_PLL") (class "Default")
      (node (ref "C261") (pin "1") (pinfunction "1_1") (pintype "passive"))
      (node (ref "FB1") (pin "2") (pinfunction "2_2") (pintype "passive"))
      (node (ref "U10") (pin "8") (pinfunction "VDDA_PLL_8") (pintype "passive"))
      (node (ref "U10") (pin "9") (pinfunction "VDD_PLL_9") (pintype "passive"))
      (node (ref "U11") (pin "8") (pinfunction "VDDA_PLL_8") (pintype "passive"))
      (node (ref "U11") (pin "9") (pinfunction "VDD_PLL_9") (pintype "passive"))
      (node (ref "U12") (pin "8") (pinfunction "VDDA_PLL_8") (pintype "passive"))
      (node (ref "U12") (pin "9") (pinfunction "VDD_PLL_9") (pintype "passive"))
      (node (ref "U18") (pin "8") (pinfunction "VDDA_PLL_8") (pintype "passive"))
      (node (ref "U18") (pin "9") (pinfunction "VDD_PLL_9") (pintype "passive"))
      (node (ref "U19") (pin "8") (pinfunction "VDDA_PLL_8") (pintype "passive"))
      (node (ref "U19") (pin "9") (pinfunction "VDD_PLL_9") (pintype "passive"))
      (node (ref "U20") (pin "8") (pinfunction "VDDA_PLL_8") (pintype "passive"))
      (node (ref "U20") (pin "9") (pinfunction "VDD_PLL_9") (pintype "passive"))
      (node (ref "U21") (pin "8") (pinfunction "VDDA_PLL_8") (pintype "passive"))
      (node (ref "U21") (pin "9") (pinfunction "VDD_PLL_9") (pintype "passive"))
      (node (ref "U24") (pin "8") (pinfunction "VDDA_PLL_8") (pintype "passive"))
      (node (ref "U24") (pin "9") (pinfunction "VDD_PLL_9") (pintype "passive"))
      (node (ref "U25") (pin "8") (pinfunction "VDDA_PLL_8") (pintype "passive"))
      (node (ref "U25") (pin "9") (pinfunction "VDD_PLL_9") (pintype "passive"))
      (node (ref "U26") (pin "8") (pinfunction "VDDA_PLL_8") (pintype "passive"))
      (node (ref "U26") (pin "9") (pinfunction "VDD_PLL_9") (pintype "passive"))
      (node (ref "U27") (pin "8") (pinfunction "VDDA_PLL_8") (pintype "passive"))
      (node (ref "U27") (pin "9") (pinfunction "VDD_PLL_9") (pintype "passive"))
      (node (ref "U4") (pin "8") (pinfunction "VDDA_PLL_8") (pintype "passive"))
      (node (ref "U4") (pin "9") (pinfunction "VDD_PLL_9") (pintype "passive"))
      (node (ref "U5") (pin "8") (pinfunction "VDDA_PLL_8") (pintype "passive"))
      (node (ref "U5") (pin "9") (pinfunction "VDD_PLL_9") (pintype "passive"))
      (node (ref "U6") (pin "8") (pinfunction "VDDA_PLL_8") (pintype "passive"))
      (node (ref "U6") (pin "9") (pinfunction "VDD_PLL_9") (pintype "passive"))
      (node (ref "U7") (pin "8") (pinfunction "VDDA_PLL_8") (pintype "passive"))
      (node (ref "U7") (pin "9") (pinfunction "VDD_PLL_9") (pintype "passive"))
      (node (ref "U9") (pin "8") (pinfunction "VDDA_PLL_8") (pintype "passive"))
      (node (ref "U9") (pin "9") (pinfunction "VDD_PLL_9") (pintype "passive"))
    )
    (net (code "99") (name "/XCLK1") (class "Default")
      (node (ref "R27") (pin "2") (pinfunction "2_2") (pintype "passive"))
      (node (ref "U8") (pin "46") (pinfunction "INT0/DMH/RP64/RD0_46") (pintype "passive"))
      (node (ref "U8") (pin "49") (pinfunction "VCPCON/RP65/RD1_49") (pintype "passive"))
      (node (ref "U8") (pin "52") (pinfunction "PMWR/RP68/RD4_52") (pintype "passive"))
      (node (ref "U8") (pin "53") (pinfunction "PMRD/RP69/RD5_53") (pintype "passive"))
    )
    (net (code "100") (name "/XCLKIN") (class "Default")
      (node (ref "R27") (pin "1") (pinfunction "1_1") (pintype "passive"))
      (node (ref "R30") (pin "1") (pinfunction "1_1") (pintype "passive"))
      (node (ref "U4") (pin "11") (pinfunction "XCLKIN_11") (pintype "passive"))
    )
    (net (code "101") (name "/XCLKOUT_1") (class "Default")
      (node (ref "U4") (pin "12") (pinfunction "XCLKOUT_12") (pintype "passive"))
      (node (ref "U5") (pin "11") (pinfunction "XCLKIN_11") (pintype "passive"))
    )
    (net (code "102") (name "/XCLKOUT_2") (class "Default")
      (node (ref "U5") (pin "12") (pinfunction "XCLKOUT_12") (pintype "passive"))
      (node (ref "U6") (pin "11") (pinfunction "XCLKIN_11") (pintype "passive"))
    )
    (net (code "103") (name "/XCLKOUT_3") (class "Default")
      (node (ref "U6") (pin "12") (pinfunction "XCLKOUT_12") (pintype "passive"))
      (node (ref "U7") (pin "11") (pinfunction "XCLKIN_11") (pintype "passive"))
    )
    (net (code "104") (name "/XCLKOUT_4") (class "Default")
      (node (ref "U7") (pin "12") (pinfunction "XCLKOUT_12") (pintype "passive"))
      (node (ref "U9") (pin "11") (pinfunction "XCLKIN_11") (pintype "passive"))
    )
    (net (code "105") (name "/XCLKOUT_5") (class "Default")
      (node (ref "U10") (pin "11") (pinfunction "XCLKIN_11") (pintype "passive"))
      (node (ref "U9") (pin "12") (pinfunction "XCLKOUT_12") (pintype "passive"))
    )
    (net (code "106") (name "/XCLKOUT_6") (class "Default")
      (node (ref "U10") (pin "12") (pinfunction "XCLKOUT_12") (pintype "passive"))
      (node (ref "U11") (pin "11") (pinfunction "XCLKIN_11") (pintype "passive"))
    )
    (net (code "107") (name "/XCLKOUT_7") (class "Default")
      (node (ref "U11") (pin "12") (pinfunction "XCLKOUT_12") (pintype "passive"))
      (node (ref "U12") (pin "11") (pinfunction "XCLKIN_11") (pintype "passive"))
    )
    (net (code "108") (name "/XCLKOUT_8") (class "Default")
      (node (ref "U12") (pin "12") (pinfunction "XCLKOUT_12") (pintype "passive"))
      (node (ref "U18") (pin "11") (pinfunction "XCLKIN_11") (pintype "passive"))
    )
    (net (code "109") (name "/XCLKOUT_9") (class "Default")
      (node (ref "U18") (pin "12") (pinfunction "XCLKOUT_12") (pintype "passive"))
      (node (ref "U19") (pin "11") (pinfunction "XCLKIN_11") (pintype "passive"))
    )
    (net (code "110") (name "/XCLKOUT_10") (class "Default")
      (node (ref "U19") (pin "12") (pinfunction "XCLKOUT_12") (pintype "passive"))
      (node (ref "U20") (pin "11") (pinfunction "XCLKIN_11") (pintype "passive"))
    )
    (net (code "111") (name "/XCLKOUT_11") (class "Default")
      (node (ref "U20") (pin "12") (pinfunction "XCLKOUT_12") (pintype "passive"))
      (node (ref "U21") (pin "11") (pinfunction "XCLKIN_11") (pintype "passive"))
    )
    (net (code "112") (name "/XCLKOUT_12") (class "Default")
      (node (ref "U21") (pin "12") (pinfunction "XCLKOUT_12") (pintype "passive"))
      (node (ref "U24") (pin "11") (pinfunction "XCLKIN_11") (pintype "passive"))
    )
    (net (code "113") (name "/XCLKOUT_13") (class "Default")
      (node (ref "U24") (pin "12") (pinfunction "XCLKOUT_12") (pintype "passive"))
      (node (ref "U25") (pin "11") (pinfunction "XCLKIN_11") (pintype "passive"))
    )
    (net (code "114") (name "/XCLKOUT_14") (class "Default")
      (node (ref "U25") (pin "12") (pinfunction "XCLKOUT_12") (pintype "passive"))
      (node (ref "U26") (pin "11") (pinfunction "XCLKIN_11") (pintype "passive"))
    )
    (net (code "115") (name "/XCLKOUT_15") (class "Default")
      (node (ref "U26") (pin "12") (pinfunction "XCLKOUT_12") (pintype "passive"))
      (node (ref "U27") (pin "11") (pinfunction "XCLKIN_11") (pintype "passive"))
    )
    (net (code "116") (name "/XCLKOUT_16") (class "Default")
      (node (ref "TP48") (pin "1") (pinfunction "1_1") (pintype "passive"))
      (node (ref "U27") (pin "12") (pinfunction "XCLKOUT_12") (pintype "passive"))
    )
    (net (code "117") (name "/YELLOW") (class "Default")
      (node (ref "D6") (pin "2") (pinfunction "A_2") (pintype "passive"))
      (node (ref "U8") (pin "44") (pinfunction "ASCL1/PMCS2/RPI74/RD10_44") (pintype "passive"))
    )
    (net (code "118") (name "GND") (class "Default")
      (node (ref "C1") (pin "1") (pinfunction "1_1") (pintype "passive"))
      (node (ref "C10") (pin "1") (pinfunction "1_1") (pintype "passive"))
      (node (ref "C11") (pin "1") (pinfunction "1_1") (pintype "passive"))
      (node (ref "C118") (pin "1") (pinfunction "1_1") (pintype "passive"))
      (node (ref "C119") (pin "1") (pinfunction "1_1") (pintype "passive"))
      (node (ref "C12") (pin "1") (pinfunction "1_1") (pintype "passive"))
      (node (ref "C120") (pin "1") (pinfunction "1_1") (pintype "passive"))
      (node (ref "C121") (pin "1") (pinfunction "1_1") (pintype "passive"))
      (node (ref "C122") (pin "1") (pinfunction "1_1") (pintype "passive"))
      (node (ref "C123") (pin "1") (pinfunction "1_1") (pintype "passive"))
      (node (ref "C124") (pin "1") (pinfunction "1_1") (pintype "passive"))
      (node (ref "C125") (pin "1") (pinfunction "1_1") (pintype "passive"))
      (node (ref "C126") (pin "1") (pinfunction "1_1") (pintype "passive"))
      (node (ref "C127") (pin "1") (pinfunction "1_1") (pintype "passive"))
      (node (ref "C128") (pin "1") (pinfunction "1_1") (pintype "passive"))
      (node (ref "C129") (pin "1") (pinfunction "1_1") (pintype "passive"))
      (node (ref "C13") (pin "1") (pinfunction "1_1") (pintype "passive"))
      (node (ref "C130") (pin "1") (pinfunction "1_1") (pintype "passive"))
      (node (ref "C131") (pin "1") (pinfunction "1_1") (pintype "passive"))
      (node (ref "C132") (pin "1") (pinfunction "1_1") (pintype "passive"))
      (node (ref "C133") (pin "1") (pinfunction "1_1") (pintype "passive"))
      (node (ref "C134") (pin "1") (pinfunction "1_1") (pintype "passive"))
      (node (ref "C135") (pin "1") (pinfunction "1_1") (pintype "passive"))
      (node (ref "C136") (pin "1") (pinfunction "1_1") (pintype "passive"))
      (node (ref "C137") (pin "1") (pinfunction "1_1") (pintype "passive"))
      (node (ref "C138") (pin "2") (pinfunction "2_2") (pintype "passive"))
      (node (ref "C139") (pin "2") (pinfunction "2_2") (pintype "passive"))
      (node (ref "C14") (pin "1") (pinfunction "1_1") (pintype "passive"))
      (node (ref "C140") (pin "1") (pinfunction "1_1") (pintype "passive"))
      (node (ref "C141") (pin "1") (pinfunction "1_1") (pintype "passive"))
      (node (ref "C142") (pin "1") (pinfunction "1_1") (pintype "passive"))
      (node (ref "C143") (pin "1") (pinfunction "1_1") (pintype "passive"))
      (node (ref "C144") (pin "1") (pinfunction "1_1") (pintype "passive"))
      (node (ref "C145") (pin "1") (pinfunction "1_1") (pintype "passive"))
      (node (ref "C146") (pin "1") (pinfunction "1_1") (pintype "passive"))
      (node (ref "C147") (pin "1") (pinfunction "1_1") (pintype "passive"))
      (node (ref "C148") (pin "1") (pinfunction "1_1") (pintype "passive"))
      (node (ref "C149") (pin "1") (pinfunction "1_1") (pintype "passive"))
      (node (ref "C15") (pin "1") (pinfunction "1_1") (pintype "passive"))
      (node (ref "C150") (pin "1") (pinfunction "1_1") (pintype "passive"))
      (node (ref "C151") (pin "1") (pinfunction "1_1") (pintype "passive"))
      (node (ref "C152") (pin "1") (pinfunction "1_1") (pintype "passive"))
      (node (ref "C153") (pin "1") (pinfunction "1_1") (pintype "passive"))
      (node (ref "C154") (pin "1") (pinfunction "1_1") (pintype "passive"))
      (node (ref "C155") (pin "1") (pinfunction "1_1") (pintype "passive"))
      (node (ref "C156") (pin "1") (pinfunction "1_1") (pintype "passive"))
      (node (ref "C157") (pin "1") (pinfunction "1_1") (pintype "passive"))
      (node (ref "C158") (pin "1") (pinfunction "1_1") (pintype "passive"))
      (node (ref "C159") (pin "1") (pinfunction "1_1") (pintype "passive"))
      (node (ref "C16") (pin "1") (pinfunction "1_1") (pintype "passive"))
      (node (ref "C160") (pin "1") (pinfunction "1_1") (pintype "passive"))
      (node (ref "C161") (pin "1") (pinfunction "1_1") (pintype "passive"))
      (node (ref "C162") (pin "1") (pinfunction "1_1") (pintype "passive"))
      (node (ref "C163") (pin "1") (pinfunction "1_1") (pintype "passive"))
      (node (ref "C166") (pin "2") (pinfunction "2_2") (pintype "passive"))
      (node (ref "C167") (pin "2") (pinfunction "2_2") (pintype "passive"))
      (node (ref "C168") (pin "2") (pinfunction "2_2") (pintype "passive"))
      (node (ref "C169") (pin "2") (pinfunction "2_2") (pintype "passive"))
      (node (ref "C17") (pin "1") (pinfunction "1_1") (pintype "passive"))
      (node (ref "C170") (pin "2") (pinfunction "2_2") (pintype "passive"))
      (node (ref "C171") (pin "2") (pinfunction "2_2") (pintype "passive"))
      (node (ref "C172") (pin "2") (pinfunction "2_2") (pintype "passive"))
      (node (ref "C173") (pin "2") (pinfunction "2_2") (pintype "passive"))
      (node (ref "C174") (pin "2") (pinfunction "2_2") (pintype "passive"))
      (node (ref "C175") (pin "1") (pinfunction "1_1") (pintype "passive"))
      (node (ref "C176") (pin "1") (pinfunction "1_1") (pintype "passive"))
      (node (ref "C177") (pin "1") (pinfunction "1_1") (pintype "passive"))
      (node (ref "C178") (pin "1") (pinfunction "1_1") (pintype "passive"))
      (node (ref "C179") (pin "1") (pinfunction "1_1") (pintype "passive"))
      (node (ref "C18") (pin "1") (pinfunction "1_1") (pintype "passive"))
      (node (ref "C180") (pin "1") (pinfunction "1_1") (pintype "passive"))
      (node (ref "C181") (pin "1") (pinfunction "1_1") (pintype "passive"))
      (node (ref "C182") (pin "1") (pinfunction "1_1") (pintype "passive"))
      (node (ref "C183") (pin "1") (pinfunction "1_1") (pintype "passive"))
      (node (ref "C184") (pin "1") (pinfunction "1_1") (pintype "passive"))
      (node (ref "C185") (pin "1") (pinfunction "1_1") (pintype "passive"))
      (node (ref "C186") (pin "1") (pinfunction "1_1") (pintype "passive"))
      (node (ref "C187") (pin "1") (pinfunction "1_1") (pintype "passive"))
      (node (ref "C188") (pin "1") (pinfunction "1_1") (pintype "passive"))
      (node (ref "C189") (pin "1") (pinfunction "1_1") (pintype "passive"))
      (node (ref "C19") (pin "1") (pinfunction "1_1") (pintype "passive"))
      (node (ref "C190") (pin "1") (pinfunction "1_1") (pintype "passive"))
      (node (ref "C191") (pin "2") (pinfunction "2_2") (pintype "passive"))
      (node (ref "C2") (pin "1") (pinfunction "1_1") (pintype "passive"))
      (node (ref "C20") (pin "2") (pinfunction "2_2") (pintype "passive"))
      (node (ref "C21") (pin "2") (pinfunction "2_2") (pintype "passive"))
      (node (ref "C22") (pin "1") (pinfunction "1_1") (pintype "passive"))
      (node (ref "C224") (pin "1") (pinfunction "1_1") (pintype "passive"))
      (node (ref "C225") (pin "2") (pinfunction "2_2") (pintype "passive"))
      (node (ref "C226") (pin "2") (pinfunction "2_2") (pintype "passive"))
      (node (ref "C227") (pin "1") (pinfunction "1_1") (pintype "passive"))
      (node (ref "C228") (pin "1") (pinfunction "1_1") (pintype "passive"))
      (node (ref "C229") (pin "1") (pinfunction "1_1") (pintype "passive"))
      (node (ref "C23") (pin "1") (pinfunction "1_1") (pintype "passive"))
      (node (ref "C230") (pin "1") (pinfunction "1_1") (pintype "passive"))
      (node (ref "C231") (pin "1") (pinfunction "1_1") (pintype "passive"))
      (node (ref "C232") (pin "1") (pinfunction "1_1") (pintype "passive"))
      (node (ref "C233") (pin "1") (pinfunction "1_1") (pintype "passive"))
      (node (ref "C234") (pin "1") (pinfunction "1_1") (pintype "passive"))
      (node (ref "C235") (pin "1") (pinfunction "1_1") (pintype "passive"))
      (node (ref "C236") (pin "1") (pinfunction "1_1") (pintype "passive"))
      (node (ref "C237") (pin "1") (pinfunction "1_1") (pintype "passive"))
      (node (ref "C238") (pin "1") (pinfunction "1_1") (pintype "passive"))
      (node (ref "C239") (pin "1") (pinfunction "1_1") (pintype "passive"))
      (node (ref "C24") (pin "1") (pinfunction "1_1") (pintype "passive"))
      (node (ref "C240") (pin "1") (pinfunction "1_1") (pintype "passive"))
      (node (ref "C241") (pin "1") (pinfunction "1_1") (pintype "passive"))
      (node (ref "C242") (pin "1") (pinfunction "1_1") (pintype "passive"))
      (node (ref "C243") (pin "1") (pinfunction "1_1") (pintype "passive"))
      (node (ref "C244") (pin "1") (pinfunction "1_1") (pintype "passive"))
      (node (ref "C245") (pin "1") (pinfunction "1_1") (pintype "passive"))
      (node (ref "C246") (pin "1") (pinfunction "1_1") (pintype "passive"))
      (node (ref "C247") (pin "1") (pinfunction "1_1") (pintype "passive"))
      (node (ref "C248") (pin "1") (pinfunction "1_1") (pintype "passive"))
      (node (ref "C249") (pin "1") (pinfunction "1_1") (pintype "passive"))
      (node (ref "C25") (pin "1") (pinfunction "1_1") (pintype "passive"))
      (node (ref "C250") (pin "1") (pinfunction "1_1") (pintype "passive"))
      (node (ref "C251") (pin "1") (pinfunction "1_1") (pintype "passive"))
      (node (ref "C252") (pin "1") (pinfunction "1_1") (pintype "passive"))
      (node (ref "C253") (pin "1") (pinfunction "1_1") (pintype "passive"))
      (node (ref "C254") (pin "1") (pinfunction "1_1") (pintype "passive"))
      (node (ref "C255") (pin "1") (pinfunction "1_1") (pintype "passive"))
      (node (ref "C256") (pin "1") (pinfunction "1_1") (pintype "passive"))
      (node (ref "C257") (pin "1") (pinfunction "1_1") (pintype "passive"))
      (node (ref "C258") (pin "1") (pinfunction "1_1") (pintype "passive"))
      (node (ref "C259") (pin "2") (pinfunction "2_2") (pintype "passive"))
      (node (ref "C26") (pin "1") (pinfunction "1_1") (pintype "passive"))
      (node (ref "C260") (pin "2") (pinfunction "2_2") (pintype "passive"))
      (node (ref "C261") (pin "2") (pinfunction "2_2") (pintype "passive"))
      (node (ref "C262") (pin "1") (pinfunction "1_1") (pintype "passive"))
      (node (ref "C263") (pin "1") (pinfunction "1_1") (pintype "passive"))
      (node (ref "C264") (pin "1") (pinfunction "1_1") (pintype "passive"))
      (node (ref "C265") (pin "1") (pinfunction "1_1") (pintype "passive"))
      (node (ref "C266") (pin "1") (pinfunction "1_1") (pintype "passive"))
      (node (ref "C267") (pin "1") (pinfunction "1_1") (pintype "passive"))
      (node (ref "C268") (pin "1") (pinfunction "1_1") (pintype "passive"))
      (node (ref "C269") (pin "1") (pinfunction "1_1") (pintype "passive"))
      (node (ref "C27") (pin "1") (pinfunction "1_1") (pintype "passive"))
      (node (ref "C270") (pin "1") (pinfunction "1_1") (pintype "passive"))
      (node (ref "C271") (pin "1") (pinfunction "1_1") (pintype "passive"))
      (node (ref "C272") (pin "1") (pinfunction "1_1") (pintype "passive"))
      (node (ref "C273") (pin "1") (pinfunction "1_1") (pintype "passive"))
      (node (ref "C274") (pin "2") (pinfunction "2_2") (pintype "passive"))
      (node (ref "C275") (pin "2") (pinfunction "2_2") (pintype "passive"))
      (node (ref "C276") (pin "1") (pinfunction "1_1") (pintype "passive"))
      (node (ref "C277") (pin "1") (pinfunction "1_1") (pintype "passive"))
      (node (ref "C278") (pin "1") (pinfunction "1_1") (pintype "passive"))
      (node (ref "C279") (pin "1") (pinfunction "1_1") (pintype "passive"))
      (node (ref "C28") (pin "1") (pinfunction "1_1") (pintype "passive"))
      (node (ref "C280") (pin "1") (pinfunction "1_1") (pintype "passive"))
      (node (ref "C281") (pin "1") (pinfunction "1_1") (pintype "passive"))
      (node (ref "C282") (pin "1") (pinfunction "1_1") (pintype "passive"))
      (node (ref "C283") (pin "1") (pinfunction "1_1") (pintype "passive"))
      (node (ref "C284") (pin "1") (pinfunction "1_1") (pintype "passive"))
      (node (ref "C285") (pin "1") (pinfunction "1_1") (pintype "passive"))
      (node (ref "C286") (pin "1") (pinfunction "1_1") (pintype "passive"))
      (node (ref "C287") (pin "1") (pinfunction "1_1") (pintype "passive"))
      (node (ref "C288") (pin "1") (pinfunction "1_1") (pintype "passive"))
      (node (ref "C289") (pin "1") (pinfunction "1_1") (pintype "passive"))
      (node (ref "C29") (pin "1") (pinfunction "1_1") (pintype "passive"))
      (node (ref "C290") (pin "1") (pinfunction "1_1") (pintype "passive"))
      (node (ref "C291") (pin "1") (pinfunction "1_1") (pintype "passive"))
      (node (ref "C3") (pin "1") (pinfunction "1_1") (pintype "passive"))
      (node (ref "C30") (pin "1") (pinfunction "1_1") (pintype "passive"))
      (node (ref "C31") (pin "1") (pinfunction "1_1") (pintype "passive"))
      (node (ref "C32") (pin "1") (pinfunction "1_1") (pintype "passive"))
      (node (ref "C324") (pin "1") (pinfunction "1_1") (pintype "passive"))
      (node (ref "C325") (pin "1") (pinfunction "1_1") (pintype "passive"))
      (node (ref "C326") (pin "1") (pinfunction "1_1") (pintype "passive"))
      (node (ref "C327") (pin "1") (pinfunction "1_1") (pintype "passive"))
      (node (ref "C328") (pin "1") (pinfunction "1_1") (pintype "passive"))
      (node (ref "C329") (pin "1") (pinfunction "1_1") (pintype "passive"))
      (node (ref "C33") (pin "1") (pinfunction "1_1") (pintype "passive"))
      (node (ref "C330") (pin "1") (pinfunction "1_1") (pintype "passive"))
      (node (ref "C331") (pin "1") (pinfunction "1_1") (pintype "passive"))
      (node (ref "C332") (pin "1") (pinfunction "1_1") (pintype "passive"))
      (node (ref "C333") (pin "1") (pinfunction "1_1") (pintype "passive"))
      (node (ref "C334") (pin "1") (pinfunction "1_1") (pintype "passive"))
      (node (ref "C335") (pin "1") (pinfunction "1_1") (pintype "passive"))
      (node (ref "C336") (pin "1") (pinfunction "1_1") (pintype "passive"))
      (node (ref "C337") (pin "1") (pinfunction "1_1") (pintype "passive"))
      (node (ref "C338") (pin "1") (pinfunction "1_1") (pintype "passive"))
      (node (ref "C339") (pin "1") (pinfunction "1_1") (pintype "passive"))
      (node (ref "C34") (pin "1") (pinfunction "1_1") (pintype "passive"))
      (node (ref "C340") (pin "1") (pinfunction "1_1") (pintype "passive"))
      (node (ref "C341") (pin "1") (pinfunction "1_1") (pintype "passive"))
      (node (ref "C342") (pin "1") (pinfunction "1_1") (pintype "passive"))
      (node (ref "C343") (pin "1") (pinfunction "1_1") (pintype "passive"))
      (node (ref "C344") (pin "1") (pinfunction "1_1") (pintype "passive"))
      (node (ref "C345") (pin "1") (pinfunction "1_1") (pintype "passive"))
      (node (ref "C346") (pin "1") (pinfunction "1_1") (pintype "passive"))
      (node (ref "C347") (pin "1") (pinfunction "1_1") (pintype "passive"))
      (node (ref "C348") (pin "1") (pinfunction "1_1") (pintype "passive"))
      (node (ref "C349") (pin "1") (pinfunction "1_1") (pintype "passive"))
      (node (ref "C35") (pin "1") (pinfunction "1_1") (pintype "passive"))
      (node (ref "C350") (pin "1") (pinfunction "1_1") (pintype "passive"))
      (node (ref "C351") (pin "1") (pinfunction "1_1") (pintype "passive"))
      (node (ref "C352") (pin "1") (pinfunction "1_1") (pintype "passive"))
      (node (ref "C353") (pin "1") (pinfunction "1_1") (pintype "passive"))
      (node (ref "C354") (pin "1") (pinfunction "1_1") (pintype "passive"))
      (node (ref "C355") (pin "1") (pinfunction "1_1") (pintype "passive"))
      (node (ref "C356") (pin "1") (pinfunction "1_1") (pintype "passive"))
      (node (ref "C357") (pin "1") (pinfunction "1_1") (pintype "passive"))
      (node (ref "C358") (pin "1") (pinfunction "1_1") (pintype "passive"))
      (node (ref "C359") (pin "1") (pinfunction "1_1") (pintype "passive"))
      (node (ref "C36") (pin "1") (pinfunction "1_1") (pintype "passive"))
      (node (ref "C360") (pin "1") (pinfunction "1_1") (pintype "passive"))
      (node (ref "C361") (pin "1") (pinfunction "1_1") (pintype "passive"))
      (node (ref "C362") (pin "1") (pinfunction "1_1") (pintype "passive"))
      (node (ref "C363") (pin "1") (pinfunction "1_1") (pintype "passive"))
      (node (ref "C364") (pin "1") (pinfunction "1_1") (pintype "passive"))
      (node (ref "C365") (pin "1") (pinfunction "1_1") (pintype "passive"))
      (node (ref "C366") (pin "1") (pinfunction "1_1") (pintype "passive"))
      (node (ref "C367") (pin "1") (pinfunction "1_1") (pintype "passive"))
      (node (ref "C368") (pin "1") (pinfunction "1_1") (pintype "passive"))
      (node (ref "C369") (pin "1") (pinfunction "1_1") (pintype "passive"))
      (node (ref "C37") (pin "1") (pinfunction "1_1") (pintype "passive"))
      (node (ref "C370") (pin "1") (pinfunction "1_1") (pintype "passive"))
      (node (ref "C371") (pin "1") (pinfunction "1_1") (pintype "passive"))
      (node (ref "C372") (pin "1") (pinfunction "1_1") (pintype "passive"))
      (node (ref "C373") (pin "1") (pinfunction "1_1") (pintype "passive"))
      (node (ref "C374") (pin "1") (pinfunction "1_1") (pintype "passive"))
      (node (ref "C375") (pin "1") (pinfunction "1_1") (pintype "passive"))
      (node (ref "C376") (pin "1") (pinfunction "1_1") (pintype "passive"))
      (node (ref "C377") (pin "1") (pinfunction "1_1") (pintype "passive"))
      (node (ref "C378") (pin "1") (pinfunction "1_1") (pintype "passive"))
      (node (ref "C379") (pin "1") (pinfunction "1_1") (pintype "passive"))
      (node (ref "C38") (pin "1") (pinfunction "1_1") (pintype "passive"))
      (node (ref "C380") (pin "1") (pinfunction "1_1") (pintype "passive"))
      (node (ref "C381") (pin "1") (pinfunction "1_1") (pintype "passive"))
      (node (ref "C382") (pin "1") (pinfunction "1_1") (pintype "passive"))
      (node (ref "C383") (pin "1") (pinfunction "1_1") (pintype "passive"))
      (node (ref "C39") (pin "1") (pinfunction "1_1") (pintype "passive"))
      (node (ref "C4") (pin "2") (pinfunction "2_2") (pintype "passive"))
      (node (ref "C40") (pin "1") (pinfunction "1_1") (pintype "passive"))
      (node (ref "C41") (pin "1") (pinfunction "1_1") (pintype "passive"))
      (node (ref "C42") (pin "1") (pinfunction "1_1") (pintype "passive"))
      (node (ref "C43") (pin "1") (pinfunction "1_1") (pintype "passive"))
      (node (ref "C44") (pin "1") (pinfunction "1_1") (pintype "passive"))
      (node (ref "C45") (pin "1") (pinfunction "1_1") (pintype "passive"))
      (node (ref "C46") (pin "1") (pinfunction "1_1") (pintype "passive"))
      (node (ref "C47") (pin "1") (pinfunction "1_1") (pintype "passive"))
      (node (ref "C48") (pin "1") (pinfunction "1_1") (pintype "passive"))
      (node (ref "C49") (pin "1") (pinfunction "1_1") (pintype "passive"))
      (node (ref "C5") (pin "2") (pinfunction "2_2") (pintype "passive"))
      (node (ref "C50") (pin "1") (pinfunction "1_1") (pintype "passive"))
      (node (ref "C51") (pin "1") (pinfunction "1_1") (pintype "passive"))
      (node (ref "C52") (pin "1") (pinfunction "1_1") (pintype "passive"))
      (node (ref "C53") (pin "1") (pinfunction "1_1") (pintype "passive"))
      (node (ref "C54") (pin "1") (pinfunction "1_1") (pintype "passive"))
      (node (ref "C55") (pin "1") (pinfunction "1_1") (pintype "passive"))
      (node (ref "C56") (pin "1") (pinfunction "1_1") (pintype "passive"))
      (node (ref "C57") (pin "1") (pinfunction "1_1") (pintype "passive"))
      (node (ref "C58") (pin "1") (pinfunction "1_1") (pintype "passive"))
      (node (ref "C59") (pin "1") (pinfunction "1_1") (pintype "passive"))
      (node (ref "C6") (pin "2") (pinfunction "2_2") (pintype "passive"))
      (node (ref "C60") (pin "1") (pinfunction "1_1") (pintype "passive"))
      (node (ref "C61") (pin "1") (pinfunction "1_1") (pintype "passive"))
      (node (ref "C62") (pin "1") (pinfunction "1_1") (pintype "passive"))
      (node (ref "C63") (pin "1") (pinfunction "1_1") (pintype "passive"))
      (node (ref "C64") (pin "1") (pinfunction "1_1") (pintype "passive"))
      (node (ref "C65") (pin "1") (pinfunction "1_1") (pintype "passive"))
      (node (ref "C66") (pin "1") (pinfunction "1_1") (pintype "passive"))
      (node (ref "C67") (pin "1") (pinfunction "1_1") (pintype "passive"))
      (node (ref "C68") (pin "1") (pinfunction "1_1") (pintype "passive"))
      (node (ref "C69") (pin "2") (pinfunction "2_2") (pintype "passive"))
      (node (ref "C70") (pin "1") (pinfunction "1_1") (pintype "passive"))
      (node (ref "C71") (pin "1") (pinfunction "1_1") (pintype "passive"))
      (node (ref "C72") (pin "1") (pinfunction "1_1") (pintype "passive"))
      (node (ref "C73") (pin "1") (pinfunction "1_1") (pintype "passive"))
      (node (ref "C74") (pin "1") (pinfunction "1_1") (pintype "passive"))
      (node (ref "C75") (pin "1") (pinfunction "1_1") (pintype "passive"))
      (node (ref "C76") (pin "1") (pinfunction "1_1") (pintype "passive"))
      (node (ref "C77") (pin "1") (pinfunction "1_1") (pintype "passive"))
      (node (ref "C78") (pin "1") (pinfunction "1_1") (pintype "passive"))
      (node (ref "C79") (pin "1") (pinfunction "1_1") (pintype "passive"))
      (node (ref "C80") (pin "1") (pinfunction "1_1") (pintype "passive"))
      (node (ref "C81") (pin "1") (pinfunction "1_1") (pintype "passive"))
      (node (ref "C82") (pin "1") (pinfunction "1_1") (pintype "passive"))
      (node (ref "C83") (pin "1") (pinfunction "1_1") (pintype "passive"))
      (node (ref "C84") (pin "1") (pinfunction "1_1") (pintype "passive"))
      (node (ref "C85") (pin "1") (pinfunction "1_1") (pintype "passive"))
      (node (ref "C_1") (pin "2") (pinfunction "2_2") (pintype "passive"))
      (node (ref "C_10") (pin "2") (pinfunction "2_2") (pintype "passive"))
      (node (ref "C_11") (pin "2") (pinfunction "2_2") (pintype "passive"))
      (node (ref "C_12") (pin "2") (pinfunction "2_2") (pintype "passive"))
      (node (ref "C_13") (pin "2") (pinfunction "2_2") (pintype "passive"))
      (node (ref "C_14") (pin "2") (pinfunction "2_2") (pintype "passive"))
      (node (ref "C_15") (pin "2") (pinfunction "2_2") (pintype "passive"))
      (node (ref "C_16") (pin "2") (pinfunction "2_2") (pintype "passive"))
      (node (ref "C_17") (pin "2") (pinfunction "2_2") (pintype "passive"))
      (node (ref "C_18") (pin "2") (pinfunction "2_2") (pintype "passive"))
      (node (ref "C_19") (pin "2") (pinfunction "2_2") (pintype "passive"))
      (node (ref "C_2") (pin "2") (pinfunction "2_2") (pintype "passive"))
      (node (ref "C_20") (pin "2") (pinfunction "2_2") (pintype "passive"))
      (node (ref "C_21") (pin "2") (pinfunction "2_2") (pintype "passive"))
      (node (ref "C_22") (pin "2") (pinfunction "2_2") (pintype "passive"))
      (node (ref "C_23") (pin "2") (pinfunction "2_2") (pintype "passive"))
      (node (ref "C_24") (pin "2") (pinfunction "2_2") (pintype "passive"))
      (node (ref "C_25") (pin "2") (pinfunction "2_2") (pintype "passive"))
      (node (ref "C_26") (pin "2") (pinfunction "2_2") (pintype "passive"))
      (node (ref "C_27") (pin "2") (pinfunction "2_2") (pintype "passive"))
      (node (ref "C_28") (pin "2") (pinfunction "2_2") (pintype "passive"))
      (node (ref "C_29") (pin "2") (pinfunction "2_2") (pintype "passive"))
      (node (ref "C_3") (pin "2") (pinfunction "2_2") (pintype "passive"))
      (node (ref "C_30") (pin "2") (pinfunction "2_2") (pintype "passive"))
      (node (ref "C_33") (pin "2") (pinfunction "2_2") (pintype "passive"))
      (node (ref "C_34") (pin "2") (pinfunction "2_2") (pintype "passive"))
      (node (ref "C_35") (pin "2") (pinfunction "2_2") (pintype "passive"))
      (node (ref "C_36") (pin "2") (pinfunction "2_2") (pintype "passive"))
      (node (ref "C_37") (pin "2") (pinfunction "2_2") (pintype "passive"))
      (node (ref "C_38") (pin "2") (pinfunction "2_2") (pintype "passive"))
      (node (ref "C_39") (pin "2") (pinfunction "2_2") (pintype "passive"))
      (node (ref "C_4") (pin "2") (pinfunction "2_2") (pintype "passive"))
      (node (ref "C_40") (pin "2") (pinfunction "2_2") (pintype "passive"))
      (node (ref "C_41") (pin "2") (pinfunction "2_2") (pintype "passive"))
      (node (ref "C_42") (pin "2") (pinfunction "2_2") (pintype "passive"))
      (node (ref "C_43") (pin "2") (pinfunction "2_2") (pintype "passive"))
      (node (ref "C_44") (pin "2") (pinfunction "2_2") (pintype "passive"))
      (node (ref "C_45") (pin "2") (pinfunction "2_2") (pintype "passive"))
      (node (ref "C_46") (pin "2") (pinfunction "2_2") (pintype "passive"))
      (node (ref "C_47") (pin "2") (pinfunction "2_2") (pintype "passive"))
      (node (ref "C_48") (pin "2") (pinfunction "2_2") (pintype "passive"))
      (node (ref "C_49") (pin "2") (pinfunction "2_2") (pintype "passive"))
      (node (ref "C_5") (pin "2") (pinfunction "2_2") (pintype "passive"))
      (node (ref "C_50") (pin "2") (pinfunction "2_2") (pintype "passive"))
      (node (ref "C_51") (pin "2") (pinfunction "2_2") (pintype "passive"))
      (node (ref "C_52") (pin "2") (pinfunction "2_2") (pintype "passive"))
      (node (ref "C_53") (pin "2") (pinfunction "2_2") (pintype "passive"))
      (node (ref "C_54") (pin "2") (pinfunction "2_2") (pintype "passive"))
      (node (ref "C_55") (pin "2") (pinfunction "2_2") (pintype "passive"))
      (node (ref "C_56") (pin "2") (pinfunction "2_2") (pintype "passive"))
      (node (ref "C_57") (pin "2") (pinfunction "2_2") (pintype "passive"))
      (node (ref "C_58") (pin "2") (pinfunction "2_2") (pintype "passive"))
      (node (ref "C_59") (pin "2") (pinfunction "2_2") (pintype "passive"))
      (node (ref "C_6") (pin "2") (pinfunction "2_2") (pintype "passive"))
      (node (ref "C_60") (pin "2") (pinfunction "2_2") (pintype "passive"))
      (node (ref "C_61") (pin "2") (pinfunction "2_2") (pintype "passive"))
      (node (ref "C_62") (pin "2") (pinfunction "2_2") (pintype "passive"))
      (node (ref "C_63") (pin "2") (pinfunction "2_2") (pintype "passive"))
      (node (ref "C_64") (pin "2") (pinfunction "2_2") (pintype "passive"))
      (node (ref "C_65") (pin "2") (pinfunction "2_2") (pintype "passive"))
      (node (ref "C_66") (pin "2") (pinfunction "2_2") (pintype "passive"))
      (node (ref "C_67") (pin "2") (pinfunction "2_2") (pintype "passive"))
      (node (ref "C_68") (pin "2") (pinfunction "2_2") (pintype "passive"))
      (node (ref "C_69") (pin "2") (pinfunction "2_2") (pintype "passive"))
      (node (ref "C_70") (pin "2") (pinfunction "2_2") (pintype "passive"))
      (node (ref "C_71") (pin "2") (pinfunction "2_2") (pintype "passive"))
      (node (ref "C_72") (pin "2") (pinfunction "2_2") (pintype "passive"))
      (node (ref "C_8") (pin "2") (pinfunction "2_2") (pintype "passive"))
      (node (ref "C_9") (pin "2") (pinfunction "2_2") (pintype "passive"))
      (node (ref "D12") (pin "2") (pinfunction "A_2") (pintype "passive"))
      (node (ref "D4") (pin "1") (pinfunction "C_1") (pintype "passive"))
      (node (ref "D5") (pin "1") (pinfunction "C_1") (pintype "passive"))
      (node (ref "D6") (pin "1") (pinfunction "C_1") (pintype "passive"))
      (node (ref "D7") (pin "1") (pinfunction "C_1") (pintype "passive"))
      (node (ref "D9") (pin "2") (pinfunction "2_2") (pintype "passive"))
      (node (ref "D9") (pin "5") (pinfunction "5_5") (pintype "passive"))
      (node (ref "J1") (pin "3") (pinfunction "3_3") (pintype "passive"))
      (node (ref "J10") (pin "1") (pinfunction "1_1") (pintype "passive"))
      (node (ref "J11") (pin "1") (pinfunction "1_1") (pintype "passive"))
      (node (ref "J12") (pin "1") (pinfunction "1_1") (pintype "passive"))
      (node (ref "J13") (pin "1") (pinfunction "1_1") (pintype "passive"))
      (node (ref "J14") (pin "1") (pinfunction "1_1") (pintype "passive"))
      (node (ref "J15") (pin "1") (pinfunction "1_1") (pintype "passive"))
      (node (ref "J2") (pin "5") (pinfunction "5_5") (pintype "passive"))
      (node (ref "J2") (pin "6") (pinfunction "6_6") (pintype "passive"))
      (node (ref "J2") (pin "7") (pinfunction "7_7") (pintype "passive"))
      (node (ref "J2") (pin "8") (pinfunction "8_8") (pintype "passive"))
      (node (ref "J2") (pin "9") (pinfunction "9_9") (pintype "passive"))
      (node (ref "J3") (pin "2") (pinfunction "2_2") (pintype "passive"))
      (node (ref "J4") (pin "4") (pinfunction "4_4") (pintype "passive"))
      (node (ref "J4") (pin "5") (pinfunction "5_5") (pintype "passive"))
      (node (ref "J4") (pin "6") (pinfunction "6_6") (pintype "passive"))
      (node (ref "J5") (pin "1") (pinfunction "1_1") (pintype "passive"))
      (node (ref "J6") (pin "1") (pinfunction "1_1") (pintype "passive"))
      (node (ref "J7") (pin "1") (pinfunction "1_1") (pintype "passive"))
      (node (ref "J8") (pin "1") (pinfunction "1_1") (pintype "passive"))
      (node (ref "J9") (pin "1") (pinfunction "1_1") (pintype "passive"))
      (node (ref "Q4") (pin "1") (pinfunction "S_1") (pintype "passive"))
      (node (ref "Q4") (pin "2") (pinfunction "S_2") (pintype "passive"))
      (node (ref "Q4") (pin "3") (pinfunction "S_3") (pintype "passive"))
      (node (ref "Q5") (pin "1") (pinfunction "S_1") (pintype "passive"))
      (node (ref "Q5") (pin "2") (pinfunction "S_2") (pintype "passive"))
      (node (ref "Q5") (pin "3") (pinfunction "S_3") (pintype "passive"))
      (node (ref "Q6") (pin "1") (pinfunction "S_1") (pintype "passive"))
      (node (ref "Q6") (pin "2") (pinfunction "S_2") (pintype "passive"))
      (node (ref "Q6") (pin "3") (pinfunction "S_3") (pintype "passive"))
      (node (ref "Q7") (pin "1") (pinfunction "S_1") (pintype "passive"))
      (node (ref "Q7") (pin "2") (pinfunction "S_2") (pintype "passive"))
      (node (ref "Q7") (pin "3") (pinfunction "S_3") (pintype "passive"))
      (node (ref "Q8") (pin "1") (pinfunction "S_1") (pintype "passive"))
      (node (ref "Q8") (pin "2") (pinfunction "S_2") (pintype "passive"))
      (node (ref "Q8") (pin "3") (pinfunction "S_3") (pintype "passive"))
      (node (ref "Q9") (pin "1") (pinfunction "S_1") (pintype "passive"))
      (node (ref "Q9") (pin "2") (pinfunction "S_2") (pintype "passive"))
      (node (ref "Q9") (pin "3") (pinfunction "S_3") (pintype "passive"))
      (node (ref "R1") (pin "1") (pinfunction "1_1") (pintype "passive"))
      (node (ref "R17") (pin "2") (pinfunction "2_2") (pintype "passive"))
      (node (ref "R18") (pin "1") (pinfunction "1_1") (pintype "passive"))
      (node (ref "R19") (pin "1") (pinfunction "1_1") (pintype "passive"))
      (node (ref "R2") (pin "1") (pinfunction "1_1") (pintype "passive"))
      (node (ref "R20") (pin "1") (pinfunction "1_1") (pintype "passive"))
      (node (ref "R21") (pin "2") (pinfunction "2_2") (pintype "passive"))
      (node (ref "R22") (pin "2") (pinfunction "2_2") (pintype "passive"))
      (node (ref "R24") (pin "2") (pinfunction "2_2") (pintype "passive"))
      (node (ref "R25") (pin "1") (pinfunction "1_1") (pintype "passive"))
      (node (ref "R3") (pin "1") (pinfunction "1_1") (pintype "passive"))
      (node (ref "R30") (pin "2") (pinfunction "2_2") (pintype "passive"))
      (node (ref "R4") (pin "1") (pinfunction "1_1") (pintype "passive"))
      (node (ref "R43") (pin "1") (pinfunction "1_1") (pintype "passive"))
      (node (ref "R44") (pin "1") (pinfunction "1_1") (pintype "passive"))
      (node (ref "R45") (pin "1") (pinfunction "1_1") (pintype "passive"))
      (node (ref "R46") (pin "1") (pinfunction "1_1") (pintype "passive"))
      (node (ref "R51") (pin "2") (pinfunction "2_2") (pintype "passive"))
      (node (ref "R55") (pin "2") (pinfunction "2_2") (pintype "passive"))
      (node (ref "R64") (pin "1") (pinfunction "1_1") (pintype "passive"))
      (node (ref "R65") (pin "1") (pinfunction "1_1") (pintype "passive"))
      (node (ref "R66") (pin "1") (pinfunction "1_1") (pintype "passive"))
      (node (ref "R67") (pin "1") (pinfunction "1_1") (pintype "passive"))
      (node (ref "U1") (pin "4") (pinfunction "GND_4") (pintype "passive"))
      (node (ref "U1") (pin "9") (pinfunction "EP_9") (pintype "passive"))
      (node (ref "U10") (pin "10") (pinfunction "VSS_PLL_10") (pintype "passive"))
      (node (ref "U10") (pin "15") (pinfunction "DVSS_15") (pintype "passive"))
      (node (ref "U10") (pin "17") (pinfunction "CHIP_ID1_17") (pintype "passive"))
      (node (ref "U10") (pin "28") (pinfunction "DVSS_28") (pintype "passive"))
      (node (ref "U10") (pin "31") (pinfunction "OVSS1_31") (pintype "passive"))
      (node (ref "U10") (pin "33") (pinfunction "DVSS_33") (pintype "passive"))
      (node (ref "U10") (pin "36") (pinfunction "DVSS_36") (pintype "passive"))
      (node (ref "U10") (pin "40") (pinfunction "DVSS_40") (pintype "passive"))
      (node (ref "U10") (pin "44") (pinfunction "DVSS_44") (pintype "passive"))
      (node (ref "U10") (pin "50") (pinfunction "OVSS0_50") (pintype "passive"))
      (node (ref "U10") (pin "53") (pinfunction "DVSS_53") (pintype "passive"))
      (node (ref "U10") (pin "61") (pinfunction "DVSS_61") (pintype "passive"))
      (node (ref "U10") (pin "64") (pinfunction "DVSS_64") (pintype "passive"))
      (node (ref "U10") (pin "65") (pinfunction "DVSS_EP_65") (pintype "passive"))
      (node (ref "U10") (pin "7") (pinfunction "VSSA_PLL_7") (pintype "passive"))
      (node (ref "U11") (pin "10") (pinfunction "VSS_PLL_10") (pintype "passive"))
      (node (ref "U11") (pin "15") (pinfunction "DVSS_15") (pintype "passive"))
      (node (ref "U11") (pin "16") (pinfunction "CHIP_ID0_16") (pintype "passive"))
      (node (ref "U11") (pin "28") (pinfunction "DVSS_28") (pintype "passive"))
      (node (ref "U11") (pin "31") (pinfunction "OVSS1_31") (pintype "passive"))
      (node (ref "U11") (pin "33") (pinfunction "DVSS_33") (pintype "passive"))
      (node (ref "U11") (pin "36") (pinfunction "DVSS_36") (pintype "passive"))
      (node (ref "U11") (pin "40") (pinfunction "DVSS_40") (pintype "passive"))
      (node (ref "U11") (pin "44") (pinfunction "DVSS_44") (pintype "passive"))
      (node (ref "U11") (pin "50") (pinfunction "OVSS0_50") (pintype "passive"))
      (node (ref "U11") (pin "53") (pinfunction "DVSS_53") (pintype "passive"))
      (node (ref "U11") (pin "61") (pinfunction "DVSS_61") (pintype "passive"))
      (node (ref "U11") (pin "64") (pinfunction "DVSS_64") (pintype "passive"))
      (node (ref "U11") (pin "65") (pinfunction "DVSS_EP_65") (pintype "passive"))
      (node (ref "U11") (pin "7") (pinfunction "VSSA_PLL_7") (pintype "passive"))
      (node (ref "U12") (pin "10") (pinfunction "VSS_PLL_10") (pintype "passive"))
      (node (ref "U12") (pin "15") (pinfunction "DVSS_15") (pintype "passive"))
      (node (ref "U12") (pin "28") (pinfunction "DVSS_28") (pintype "passive"))
      (node (ref "U12") (pin "31") (pinfunction "OVSS1_31") (pintype "passive"))
      (node (ref "U12") (pin "33") (pinfunction "DVSS_33") (pintype "passive"))
      (node (ref "U12") (pin "36") (pinfunction "DVSS_36") (pintype "passive"))
      (node (ref "U12") (pin "40") (pinfunction "DVSS_40") (pintype "passive"))
      (node (ref "U12") (pin "44") (pinfunction "DVSS_44") (pintype "passive"))
      (node (ref "U12") (pin "50") (pinfunction "OVSS0_50") (pintype "passive"))
      (node (ref "U12") (pin "53") (pinfunction "DVSS_53") (pintype "passive"))
      (node (ref "U12") (pin "61") (pinfunction "DVSS_61") (pintype "passive"))
      (node (ref "U12") (pin "64") (pinfunction "DVSS_64") (pintype "passive"))
      (node (ref "U12") (pin "65") (pinfunction "DVSS_EP_65") (pintype "passive"))
      (node (ref "U12") (pin "7") (pinfunction "VSSA_PLL_7") (pintype "passive"))
      (node (ref "U13") (pin "2") (pinfunction "GND_2") (pintype "passive"))
      (node (ref "U13") (pin "3") (pinfunction "GND_3") (pintype "passive"))
      (node (ref "U13") (pin "4") (pinfunction "N.C._4") (pintype "passive"))
      (node (ref "U13") (pin "5") (pinfunction "N.C._5") (pintype "passive"))
      (node (ref "U13") (pin "6") (pinfunction "GND_6") (pintype "passive"))
      (node (ref "U13") (pin "7") (pinfunction "GND_7") (pintype "passive"))
      (node (ref "U14") (pin "2") (pinfunction "GND_2") (pintype "passive"))
      (node (ref "U15") (pin "6") (pinfunction "GND_6") (pintype "passive"))
      (node (ref "U15") (pin "7") (pinfunction "GND_7") (pintype "passive"))
      (node (ref "U16") (pin "4") (pinfunction "GND_4") (pintype "passive"))
      (node (ref "U17") (pin "4") (pinfunction "GND_4") (pintype "passive"))
      (node (ref "U18") (pin "10") (pinfunction "VSS_PLL_10") (pintype "passive"))
      (node (ref "U18") (pin "15") (pinfunction "DVSS_15") (pintype "passive"))
      (node (ref "U18") (pin "16") (pinfunction "CHIP_ID0_16") (pintype "passive"))
      (node (ref "U18") (pin "17") (pinfunction "CHIP_ID1_17") (pintype "passive"))
      (node (ref "U18") (pin "18") (pinfunction "CHIP_ID2_18") (pintype "passive"))
      (node (ref "U18") (pin "28") (pinfunction "DVSS_28") (pintype "passive"))
      (node (ref "U18") (pin "31") (pinfunction "OVSS1_31") (pintype "passive"))
      (node (ref "U18") (pin "33") (pinfunction "DVSS_33") (pintype "passive"))
      (node (ref "U18") (pin "36") (pinfunction "DVSS_36") (pintype "passive"))
      (node (ref "U18") (pin "40") (pinfunction "DVSS_40") (pintype "passive"))
      (node (ref "U18") (pin "44") (pinfunction "DVSS_44") (pintype "passive"))
      (node (ref "U18") (pin "50") (pinfunction "OVSS0_50") (pintype "passive"))
      (node (ref "U18") (pin "53") (pinfunction "DVSS_53") (pintype "passive"))
      (node (ref "U18") (pin "61") (pinfunction "DVSS_61") (pintype "passive"))
      (node (ref "U18") (pin "64") (pinfunction "DVSS_64") (pintype "passive"))
      (node (ref "U18") (pin "65") (pinfunction "DVSS_EP_65") (pintype "passive"))
      (node (ref "U18") (pin "7") (pinfunction "VSSA_PLL_7") (pintype "passive"))
      (node (ref "U19") (pin "10") (pinfunction "VSS_PLL_10") (pintype "passive"))
      (node (ref "U19") (pin "15") (pinfunction "DVSS_15") (pintype "passive"))
      (node (ref "U19") (pin "17") (pinfunction "CHIP_ID1_17") (pintype "passive"))
      (node (ref "U19") (pin "18") (pinfunction "CHIP_ID2_18") (pintype "passive"))
      (node (ref "U19") (pin "28") (pinfunction "DVSS_28") (pintype "passive"))
      (node (ref "U19") (pin "31") (pinfunction "OVSS1_31") (pintype "passive"))
      (node (ref "U19") (pin "33") (pinfunction "DVSS_33") (pintype "passive"))
      (node (ref "U19") (pin "36") (pinfunction "DVSS_36") (pintype "passive"))
      (node (ref "U19") (pin "40") (pinfunction "DVSS_40") (pintype "passive"))
      (node (ref "U19") (pin "44") (pinfunction "DVSS_44") (pintype "passive"))
      (node (ref "U19") (pin "50") (pinfunction "OVSS0_50") (pintype "passive"))
      (node (ref "U19") (pin "53") (pinfunction "DVSS_53") (pintype "passive"))
      (node (ref "U19") (pin "61") (pinfunction "DVSS_61") (pintype "passive"))
      (node (ref "U19") (pin "64") (pinfunction "DVSS_64") (pintype "passive"))
      (node (ref "U19") (pin "65") (pinfunction "DVSS_EP_65") (pintype "passive"))
      (node (ref "U19") (pin "7") (pinfunction "VSSA_PLL_7") (pintype "passive"))
      (node (ref "U2") (pin "4") (pinfunction "GND_4") (pintype "passive"))
      (node (ref "U2") (pin "9") (pinfunction "EP_9") (pintype "passive"))
      (node (ref "U20") (pin "10") (pinfunction "VSS_PLL_10") (pintype "passive"))
      (node (ref "U20") (pin "15") (pinfunction "DVSS_15") (pintype "passive"))
      (node (ref "U20") (pin "16") (pinfunction "CHIP_ID0_16") (pintype "passive"))
      (node (ref "U20") (pin "18") (pinfunction "CHIP_ID2_18") (pintype "passive"))
      (node (ref "U20") (pin "28") (pinfunction "DVSS_28") (pintype "passive"))
      (node (ref "U20") (pin "31") (pinfunction "OVSS1_31") (pintype "passive"))
      (node (ref "U20") (pin "33") (pinfunction "DVSS_33") (pintype "passive"))
      (node (ref "U20") (pin "36") (pinfunction "DVSS_36") (pintype "passive"))
      (node (ref "U20") (pin "40") (pinfunction "DVSS_40") (pintype "passive"))
      (node (ref "U20") (pin "44") (pinfunction "DVSS_44") (pintype "passive"))
      (node (ref "U20") (pin "50") (pinfunction "OVSS0_50") (pintype "passive"))
      (node (ref "U20") (pin "53") (pinfunction "DVSS_53") (pintype "passive"))
      (node (ref "U20") (pin "61") (pinfunction "DVSS_61") (pintype "passive"))
      (node (ref "U20") (pin "64") (pinfunction "DVSS_64") (pintype "passive"))
      (node (ref "U20") (pin "65") (pinfunction "DVSS_EP_65") (pintype "passive"))
      (node (ref "U20") (pin "7") (pinfunction "VSSA_PLL_7") (pintype "passive"))
      (node (ref "U21") (pin "10") (pinfunction "VSS_PLL_10") (pintype "passive"))
      (node (ref "U21") (pin "15") (pinfunction "DVSS_15") (pintype "passive"))
      (node (ref "U21") (pin "16") (pinfunction "CHIP_ID0_16") (pintype "passive"))
      (node (ref "U21") (pin "28") (pinfunction "DVSS_28") (pintype "passive"))
      (node (ref "U21") (pin "31") (pinfunction "OVSS1_31") (pintype "passive"))
      (node (ref "U21") (pin "33") (pinfunction "DVSS_33") (pintype "passive"))
      (node (ref "U21") (pin "36") (pinfunction "DVSS_36") (pintype "passive"))
      (node (ref "U21") (pin "40") (pinfunction "DVSS_40") (pintype "passive"))
      (node (ref "U21") (pin "44") (pinfunction "DVSS_44") (pintype "passive"))
      (node (ref "U21") (pin "50") (pinfunction "OVSS0_50") (pintype "passive"))
      (node (ref "U21") (pin "53") (pinfunction "DVSS_53") (pintype "passive"))
      (node (ref "U21") (pin "61") (pinfunction "DVSS_61") (pintype "passive"))
      (node (ref "U21") (pin "64") (pinfunction "DVSS_64") (pintype "passive"))
      (node (ref "U21") (pin "65") (pinfunction "DVSS_EP_65") (pintype "passive"))
      (node (ref "U21") (pin "7") (pinfunction "VSSA_PLL_7") (pintype "passive"))
      (node (ref "U22") (pin "6") (pinfunction "GND_6") (pintype "passive"))
      (node (ref "U22") (pin "7") (pinfunction "GND_7") (pintype "passive"))
      (node (ref "U23") (pin "6") (pinfunction "GND_6") (pintype "passive"))
      (node (ref "U23") (pin "7") (pinfunction "GND_7") (pintype "passive"))
      (node (ref "U24") (pin "10") (pinfunction "VSS_PLL_10") (pintype "passive"))
      (node (ref "U24") (pin "15") (pinfunction "DVSS_15") (pintype "passive"))
      (node (ref "U24") (pin "16") (pinfunction "CHIP_ID0_16") (pintype "passive"))
      (node (ref "U24") (pin "17") (pinfunction "CHIP_ID1_17") (pintype "passive"))
      (node (ref "U24") (pin "28") (pinfunction "DVSS_28") (pintype "passive"))
      (node (ref "U24") (pin "31") (pinfunction "OVSS1_31") (pintype "passive"))
      (node (ref "U24") (pin "33") (pinfunction "DVSS_33") (pintype "passive"))
      (node (ref "U24") (pin "36") (pinfunction "DVSS_36") (pintype "passive"))
      (node (ref "U24") (pin "40") (pinfunction "DVSS_40") (pintype "passive"))
      (node (ref "U24") (pin "44") (pinfunction "DVSS_44") (pintype "passive"))
      (node (ref "U24") (pin "50") (pinfunction "OVSS0_50") (pintype "passive"))
      (node (ref "U24") (pin "53") (pinfunction "DVSS_53") (pintype "passive"))
      (node (ref "U24") (pin "61") (pinfunction "DVSS_61") (pintype "passive"))
      (node (ref "U24") (pin "64") (pinfunction "DVSS_64") (pintype "passive"))
      (node (ref "U24") (pin "65") (pinfunction "DVSS_EP_65") (pintype "passive"))
      (node (ref "U24") (pin "7") (pinfunction "VSSA_PLL_7") (pintype "passive"))
      (node (ref "U25") (pin "10") (pinfunction "VSS_PLL_10") (pintype "passive"))
      (node (ref "U25") (pin "15") (pinfunction "DVSS_15") (pintype "passive"))
      (node (ref "U25") (pin "17") (pinfunction "CHIP_ID1_17") (pintype "passive"))
      (node (ref "U25") (pin "28") (pinfunction "DVSS_28") (pintype "passive"))
      (node (ref "U25") (pin "31") (pinfunction "OVSS1_31") (pintype "passive"))
      (node (ref "U25") (pin "33") (pinfunction "DVSS_33") (pintype "passive"))
      (node (ref "U25") (pin "36") (pinfunction "DVSS_36") (pintype "passive"))
      (node (ref "U25") (pin "40") (pinfunction "DVSS_40") (pintype "passive"))
      (node (ref "U25") (pin "44") (pinfunction "DVSS_44") (pintype "passive"))
      (node (ref "U25") (pin "50") (pinfunction "OVSS0_50") (pintype "passive"))
      (node (ref "U25") (pin "53") (pinfunction "DVSS_53") (pintype "passive"))
      (node (ref "U25") (pin "61") (pinfunction "DVSS_61") (pintype "passive"))
      (node (ref "U25") (pin "64") (pinfunction "DVSS_64") (pintype "passive"))
      (node (ref "U25") (pin "65") (pinfunction "DVSS_EP_65") (pintype "passive"))
      (node (ref "U25") (pin "7") (pinfunction "VSSA_PLL_7") (pintype "passive"))
      (node (ref "U26") (pin "10") (pinfunction "VSS_PLL_10") (pintype "passive"))
      (node (ref "U26") (pin "15") (pinfunction "DVSS_15") (pintype "passive"))
      (node (ref "U26") (pin "16") (pinfunction "CHIP_ID0_16") (pintype "passive"))
      (node (ref "U26") (pin "28") (pinfunction "DVSS_28") (pintype "passive"))
      (node (ref "U26") (pin "31") (pinfunction "OVSS1_31") (pintype "passive"))
      (node (ref "U26") (pin "33") (pinfunction "DVSS_33") (pintype "passive"))
      (node (ref "U26") (pin "36") (pinfunction "DVSS_36") (pintype "passive"))
      (node (ref "U26") (pin "40") (pinfunction "DVSS_40") (pintype "passive"))
      (node (ref "U26") (pin "44") (pinfunction "DVSS_44") (pintype "passive"))
      (node (ref "U26") (pin "50") (pinfunction "OVSS0_50") (pintype "passive"))
      (node (ref "U26") (pin "53") (pinfunction "DVSS_53") (pintype "passive"))
      (node (ref "U26") (pin "61") (pinfunction "DVSS_61") (pintype "passive"))
      (node (ref "U26") (pin "64") (pinfunction "DVSS_64") (pintype "passive"))
      (node (ref "U26") (pin "65") (pinfunction "DVSS_EP_65") (pintype "passive"))
      (node (ref "U26") (pin "7") (pinfunction "VSSA_PLL_7") (pintype "passive"))
      (node (ref "U27") (pin "10") (pinfunction "VSS_PLL_10") (pintype "passive"))
      (node (ref "U27") (pin "15") (pinfunction "DVSS_15") (pintype "passive"))
      (node (ref "U27") (pin "28") (pinfunction "DVSS_28") (pintype "passive"))
      (node (ref "U27") (pin "31") (pinfunction "OVSS1_31") (pintype "passive"))
      (node (ref "U27") (pin "33") (pinfunction "DVSS_33") (pintype "passive"))
      (node (ref "U27") (pin "36") (pinfunction "DVSS_36") (pintype "passive"))
      (node (ref "U27") (pin "40") (pinfunction "DVSS_40") (pintype "passive"))
      (node (ref "U27") (pin "44") (pinfunction "DVSS_44") (pintype "passive"))
      (node (ref "U27") (pin "50") (pinfunction "OVSS0_50") (pintype "passive"))
      (node (ref "U27") (pin "53") (pinfunction "DVSS_53") (pintype "passive"))
      (node (ref "U27") (pin "61") (pinfunction "DVSS_61") (pintype "passive"))
      (node (ref "U27") (pin "64") (pinfunction "DVSS_64") (pintype "passive"))
      (node (ref "U27") (pin "65") (pinfunction "DVSS_EP_65") (pintype "passive"))
      (node (ref "U27") (pin "7") (pinfunction "VSSA_PLL_7") (pintype "passive"))
      (node (ref "U3") (pin "4") (pinfunction "GND_4") (pintype "passive"))
      (node (ref "U3") (pin "9") (pinfunction "EP_9") (pintype "passive"))
      (node (ref "U4") (pin "10") (pinfunction "VSS_PLL_10") (pintype "passive"))
      (node (ref "U4") (pin "15") (pinfunction "DVSS_15") (pintype "passive"))
      (node (ref "U4") (pin "16") (pinfunction "CHIP_ID0_16") (pintype "passive"))
      (node (ref "U4") (pin "17") (pinfunction "CHIP_ID1_17") (pintype "passive"))
      (node (ref "U4") (pin "18") (pinfunction "CHIP_ID2_18") (pintype "passive"))
      (node (ref "U4") (pin "28") (pinfunction "DVSS_28") (pintype "passive"))
      (node (ref "U4") (pin "31") (pinfunction "OVSS1_31") (pintype "passive"))
      (node (ref "U4") (pin "33") (pinfunction "DVSS_33") (pintype "passive"))
      (node (ref "U4") (pin "36") (pinfunction "DVSS_36") (pintype "passive"))
      (node (ref "U4") (pin "40") (pinfunction "DVSS_40") (pintype "passive"))
      (node (ref "U4") (pin "44") (pinfunction "DVSS_44") (pintype "passive"))
      (node (ref "U4") (pin "50") (pinfunction "OVSS0_50") (pintype "passive"))
      (node (ref "U4") (pin "53") (pinfunction "DVSS_53") (pintype "passive"))
      (node (ref "U4") (pin "61") (pinfunction "DVSS_61") (pintype "passive"))
      (node (ref "U4") (pin "64") (pinfunction "DVSS_64") (pintype "passive"))
      (node (ref "U4") (pin "65") (pinfunction "DVSS_EP_65") (pintype "passive"))
      (node (ref "U4") (pin "7") (pinfunction "VSSA_PLL_7") (pintype "passive"))
      (node (ref "U5") (pin "10") (pinfunction "VSS_PLL_10") (pintype "passive"))
      (node (ref "U5") (pin "15") (pinfunction "DVSS_15") (pintype "passive"))
      (node (ref "U5") (pin "17") (pinfunction "CHIP_ID1_17") (pintype "passive"))
      (node (ref "U5") (pin "18") (pinfunction "CHIP_ID2_18") (pintype "passive"))
      (node (ref "U5") (pin "28") (pinfunction "DVSS_28") (pintype "passive"))
      (node (ref "U5") (pin "31") (pinfunction "OVSS1_31") (pintype "passive"))
      (node (ref "U5") (pin "33") (pinfunction "DVSS_33") (pintype "passive"))
      (node (ref "U5") (pin "36") (pinfunction "DVSS_36") (pintype "passive"))
      (node (ref "U5") (pin "40") (pinfunction "DVSS_40") (pintype "passive"))
      (node (ref "U5") (pin "44") (pinfunction "DVSS_44") (pintype "passive"))
      (node (ref "U5") (pin "50") (pinfunction "OVSS0_50") (pintype "passive"))
      (node (ref "U5") (pin "53") (pinfunction "DVSS_53") (pintype "passive"))
      (node (ref "U5") (pin "61") (pinfunction "DVSS_61") (pintype "passive"))
      (node (ref "U5") (pin "64") (pinfunction "DVSS_64") (pintype "passive"))
      (node (ref "U5") (pin "65") (pinfunction "DVSS_EP_65") (pintype "passive"))
      (node (ref "U5") (pin "7") (pinfunction "VSSA_PLL_7") (pintype "passive"))
      (node (ref "U6") (pin "10") (pinfunction "VSS_PLL_10") (pintype "passive"))
      (node (ref "U6") (pin "15") (pinfunction "DVSS_15") (pintype "passive"))
      (node (ref "U6") (pin "16") (pinfunction "CHIP_ID0_16") (pintype "passive"))
      (node (ref "U6") (pin "18") (pinfunction "CHIP_ID2_18") (pintype "passive"))
      (node (ref "U6") (pin "28") (pinfunction "DVSS_28") (pintype "passive"))
      (node (ref "U6") (pin "31") (pinfunction "OVSS1_31") (pintype "passive"))
      (node (ref "U6") (pin "33") (pinfunction "DVSS_33") (pintype "passive"))
      (node (ref "U6") (pin "36") (pinfunction "DVSS_36") (pintype "passive"))
      (node (ref "U6") (pin "40") (pinfunction "DVSS_40") (pintype "passive"))
      (node (ref "U6") (pin "44") (pinfunction "DVSS_44") (pintype "passive"))
      (node (ref "U6") (pin "50") (pinfunction "OVSS0_50") (pintype "passive"))
      (node (ref "U6") (pin "53") (pinfunction "DVSS_53") (pintype "passive"))
      (node (ref "U6") (pin "61") (pinfunction "DVSS_61") (pintype "passive"))
      (node (ref "U6") (pin "64") (pinfunction "DVSS_64") (pintype "passive"))
      (node (ref "U6") (pin "65") (pinfunction "DVSS_EP_65") (pintype "passive"))
      (node (ref "U6") (pin "7") (pinfunction "VSSA_PLL_7") (pintype "passive"))
      (node (ref "U7") (pin "10") (pinfunction "VSS_PLL_10") (pintype "passive"))
      (node (ref "U7") (pin "15") (pinfunction "DVSS_15") (pintype "passive"))
      (node (ref "U7") (pin "18") (pinfunction "CHIP_ID2_18") (pintype "passive"))
      (node (ref "U7") (pin "28") (pinfunction "DVSS_28") (pintype "passive"))
      (node (ref "U7") (pin "31") (pinfunction "OVSS1_31") (pintype "passive"))
      (node (ref "U7") (pin "33") (pinfunction "DVSS_33") (pintype "passive"))
      (node (ref "U7") (pin "36") (pinfunction "DVSS_36") (pintype "passive"))
      (node (ref "U7") (pin "40") (pinfunction "DVSS_40") (pintype "passive"))
      (node (ref "U7") (pin "44") (pinfunction "DVSS_44") (pintype "passive"))
      (node (ref "U7") (pin "50") (pinfunction "OVSS0_50") (pintype "passive"))
      (node (ref "U7") (pin "53") (pinfunction "DVSS_53") (pintype "passive"))
      (node (ref "U7") (pin "61") (pinfunction "DVSS_61") (pintype "passive"))
      (node (ref "U7") (pin "64") (pinfunction "DVSS_64") (pintype "passive"))
      (node (ref "U7") (pin "65") (pinfunction "DVSS_EP_65") (pintype "passive"))
      (node (ref "U7") (pin "7") (pinfunction "VSSA_PLL_7") (pintype "passive"))
      (node (ref "U8") (pin "20") (pinfunction "AVSS_20") (pintype "passive"))
      (node (ref "U8") (pin "25") (pinfunction "VSS_25") (pintype "passive"))
      (node (ref "U8") (pin "41") (pinfunction "VSS_41") (pintype "passive"))
      (node (ref "U8") (pin "9") (pinfunction "VSS_9") (pintype "passive"))
      (node (ref "U9") (pin "10") (pinfunction "VSS_PLL_10") (pintype "passive"))
      (node (ref "U9") (pin "15") (pinfunction "DVSS_15") (pintype "passive"))
      (node (ref "U9") (pin "16") (pinfunction "CHIP_ID0_16") (pintype "passive"))
      (node (ref "U9") (pin "17") (pinfunction "CHIP_ID1_17") (pintype "passive"))
      (node (ref "U9") (pin "28") (pinfunction "DVSS_28") (pintype "passive"))
      (node (ref "U9") (pin "31") (pinfunction "OVSS1_31") (pintype "passive"))
      (node (ref "U9") (pin "33") (pinfunction "DVSS_33") (pintype "passive"))
      (node (ref "U9") (pin "36") (pinfunction "DVSS_36") (pintype "passive"))
      (node (ref "U9") (pin "40") (pinfunction "DVSS_40") (pintype "passive"))
      (node (ref "U9") (pin "44") (pinfunction "DVSS_44") (pintype "passive"))
      (node (ref "U9") (pin "50") (pinfunction "OVSS0_50") (pintype "passive"))
      (node (ref "U9") (pin "53") (pinfunction "DVSS_53") (pintype "passive"))
      (node (ref "U9") (pin "61") (pinfunction "DVSS_61") (pintype "passive"))
      (node (ref "U9") (pin "64") (pinfunction "DVSS_64") (pintype "passive"))
      (node (ref "U9") (pin "65") (pinfunction "DVSS_EP_65") (pintype "passive"))
      (node (ref "U9") (pin "7") (pinfunction "VSSA_PLL_7") (pintype "passive"))
    )
    (net (code "119") (name "Net-(U8-AN2{slash}C2IN2-{slash}VMIO{slash}RPI34{slash}RB2)") (class "Default")
      (node (ref "TP17") (pin "1") (pinfunction "1_1") (pintype "passive"))
      (node (ref "U8") (pin "14") (pinfunction "AN2/C2IN2-/VMIO/RPI34/RB2_14") (pintype "passive"))
    )
    (net (code "120") (name "Net-(U8-AN3{slash}C2IN1+{slash}VPIO{slash}RPI35{slash}RB3)") (class "Default")
      (node (ref "TP12") (pin "1") (pinfunction "1_1") (pintype "passive"))
      (node (ref "U8") (pin "13") (pinfunction "AN3/C2IN1+/VPIO/RPI35/RB3_13") (pintype "passive"))
    )
    (net (code "121") (name "Net-(U8-AN4{slash}C1IN2-{slash}USBOEN{slash}RPI36{slash}RB4)") (class "Default")
      (node (ref "TP54") (pin "1") (pinfunction "1_1") (pintype "passive"))
      (node (ref "U8") (pin "12") (pinfunction "AN4/C1IN2-/USBOEN/RPI36/RB4_12") (pintype "passive"))
    )
    (net (code "122") (name "Net-(U8-AN5{slash}C1IN1+{slash}VBUSON{slash}VBUSST{slash}RPI37{slash}RB5)") (class "Default")
      (node (ref "TP53") (pin "1") (pinfunction "1_1") (pintype "passive"))
      (node (ref "U8") (pin "11") (pinfunction "AN5/C1IN1+/VBUSON/VBUSST/RPI37/RB5_11") (pintype "passive"))
    )
    (net (code "123") (name "Net-(U8-AN8{slash}PMA6{slash}RPI40{slash}RB8)") (class "Default")
      (node (ref "TP20") (pin "1") (pinfunction "1_1") (pintype "passive"))
      (node (ref "U8") (pin "21") (pinfunction "AN8/PMA6/RPI40/RB8_21") (pintype "passive"))
    )
    (net (code "124") (name "Net-(U8-AN9{slash}PMA7{slash}{slash}RPI41{slash}RB9)") (class "Default")
      (node (ref "TP21") (pin "1") (pinfunction "1_1") (pintype "passive"))
      (node (ref "U8") (pin "22") (pinfunction "AN9/PMA7//RPI41/RB9_22") (pintype "passive"))
    )
    (net (code "125") (name "Net-(U8-AN14{slash}PMA1{slash}RPI46{slash}RB14)") (class "Default")
      (node (ref "TP27") (pin "1") (pinfunction "1_1") (pintype "passive"))
      (node (ref "U8") (pin "29") (pinfunction "AN14/PMA1/RPI46/RB14_29") (pintype "passive"))
    )
    (net (code "126") (name "Net-(U8-AN15{slash}PMA0{slash}RPI47{slash}RB15)") (class "Default")
      (node (ref "TP28") (pin "1") (pinfunction "1_1") (pintype "passive"))
      (node (ref "U8") (pin "30") (pinfunction "AN15/PMA0/RPI47/RB15_30") (pintype "passive"))
    )
    (net (code "127") (name "Net-(U8-ASDA1{slash}DPLN{slash}RPI73{slash}RD9)") (class "Default")
      (node (ref "TP22") (pin "1") (pinfunction "1_1") (pintype "passive"))
      (node (ref "U8") (pin "43") (pinfunction "ASDA1/DPLN/RPI73/RD9_43") (pintype "passive"))
    )
    (net (code "128") (name "Net-(U8-C2IN1-{slash}PMA2{slash}RPI121{slash}RG9)") (class "Default")
      (node (ref "TP10") (pin "1") (pinfunction "1_1") (pintype "passive"))
      (node (ref "U8") (pin "8") (pinfunction "C2IN1-/PMA2/RPI121/RG9_8") (pintype "passive"))
    )
    (net (code "129") (name "Net-(U8-C2IN3-{slash}SDO2{slash}PMA3{slash}RP120{slash}RG8)") (class "Default")
      (node (ref "TP9") (pin "1") (pinfunction "1_1") (pintype "passive"))
      (node (ref "U8") (pin "6") (pinfunction "C2IN3-/SDO2/PMA3/RP120/RG8_6") (pintype "passive"))
    )
    (net (code "130") (name "Net-(U8-C3IN2-{slash}RP70{slash}RD6)") (class "Default")
      (node (ref "TP11") (pin "1") (pinfunction "1_1") (pintype "passive"))
      (node (ref "U8") (pin "54") (pinfunction "C3IN2-/RP70/RD6_54") (pintype "passive"))
    )
    (net (code "131") (name "Net-(U8-DPH{slash}RP66{slash}RD2)") (class "Default")
      (node (ref "TP19") (pin "1") (pinfunction "1_1") (pintype "passive"))
      (node (ref "U8") (pin "50") (pinfunction "DPH/RP66/RD2_50") (pintype "passive"))
    )
    (net (code "132") (name "Net-(U8-PMBE{slash}RP67{slash}RD3)") (class "Default")
      (node (ref "TP18") (pin "1") (pinfunction "1_1") (pintype "passive"))
      (node (ref "U8") (pin "51") (pinfunction "PMBE/RP67/RD3_51") (pintype "passive"))
    )
    (net (code "133") (name "Net-(U8-RTCC{slash}DMLN{slash}RPI72{slash}RD8)") (class "Default")
      (node (ref "TP23") (pin "1") (pinfunction "1_1") (pintype "passive"))
      (node (ref "U8") (pin "42") (pinfunction "RTCC/DMLN/RPI72/RD8_42") (pintype "passive"))
    )
    (net (code "134") (name "Net-(U8-SCL2{slash}PMA8{slash}RP101{slash}RF5)") (class "Default")
      (node (ref "TP30") (pin "1") (pinfunction "1_1") (pintype "passive"))
      (node (ref "U8") (pin "32") (pinfunction "SCL2/PMA8/RP101/RF5_32") (pintype "passive"))
    )
    (net (code "135") (name "Net-(U8-SDA2{slash}PMA9{slash}RP100{slash}RF4)") (class "Default")
      (node (ref "TP29") (pin "1") (pinfunction "1_1") (pintype "passive"))
      (node (ref "U8") (pin "31") (pinfunction "SDA2/PMA9/RP100/RF4_31") (pintype "passive"))
    )
    (net (code "136") (name "Net-(U8-TCK{slash}AN12{slash}PMA11{slash}RPI44{slash}RB12)") (class "Default")
      (node (ref "TP25") (pin "1") (pinfunction "1_1") (pintype "passive"))
      (node (ref "U8") (pin "27") (pinfunction "TCK/AN12/PMA11/RPI44/RB12_27") (pintype "passive"))
    )
    (net (code "137") (name "Net-(U8-TDI{slash}AN13{slash}PMA10{slash}RPI45{slash}RB13)") (class "Default")
      (node (ref "TP26") (pin "1") (pinfunction "1_1") (pintype "passive"))
      (node (ref "U8") (pin "28") (pinfunction "TDI/AN13/PMA10/RPI45/RB13_28") (pintype "passive"))
    )
    (net (code "138") (name "Net-(U8-TDO{slash}AN11{slash}PMA12{slash}RPI43{slash}RB11)") (class "Default")
      (node (ref "TP24") (pin "1") (pinfunction "1_1") (pintype "passive"))
      (node (ref "U8") (pin "24") (pinfunction "TDO/AN11/PMA12/RPI43/RB11_24") (pintype "passive"))
    )
    (net (code "139") (name "Net-(U8-USBID{slash}RP99{slash}RF3)") (class "Default")
      (node (ref "TP31") (pin "1") (pinfunction "1_1") (pintype "passive"))
      (node (ref "U8") (pin "33") (pinfunction "USBID/RP99/RF3_33") (pintype "passive"))
    )
    (net (code "140") (name "Net-(U22-ADJ)") (class "Default")
      (node (ref "R50") (pin "2") (pinfunction "2_2") (pintype "passive"))
      (node (ref "R51") (pin "1") (pinfunction "1_1") (pintype "passive"))
      (node (ref "U22") (pin "2") (pinfunction "ADJ_2") (pintype "passive"))
    )
    (net (code "141") (name "Net-(U23-ADJ)") (class "Default")
      (node (ref "R52") (pin "2") (pinfunction "2_2") (pintype "passive"))
      (node (ref "R55") (pin "1") (pinfunction "1_1") (pintype "passive"))
      (node (ref "U23") (pin "2") (pinfunction "ADJ_2") (pintype "passive"))
    )
    (net (code "142") (name "unconnected-(J2-Pad4)") (class "Default")
      (node (ref "J2") (pin "4") (pinfunction "4_4") (pintype "passive"))
    )
    (net (code "143") (name "unconnected-(U14-N.C.-Pad4)") (class "Default")
      (node (ref "U14") (pin "4") (pinfunction "N.C._4") (pintype "passive+no_connect"))
    )
    (net (code "144") (name "unconnected-(U15-NC-Pad2)") (class "Default")
      (node (ref "U15") (pin "2") (pinfunction "NC_2") (pintype "passive+no_connect"))
    )
    (net (code "145") (name "unconnected-(U15-NC-Pad3)") (class "Default")
      (node (ref "U15") (pin "3") (pinfunction "NC_3") (pintype "passive+no_connect"))
    )
    (net (code "146") (name "unconnected-(U15-NC-Pad4)") (class "Default")
      (node (ref "U15") (pin "4") (pinfunction "NC_4") (pintype "passive+no_connect"))
    )
    (net (code "147") (name "unconnected-(U22-NC-Pad3)") (class "Default")
      (node (ref "U22") (pin "3") (pinfunction "NC_3") (pintype "passive+no_connect"))
    )
    (net (code "148") (name "unconnected-(U22-NC-Pad4)") (class "Default")
      (node (ref "U22") (pin "4") (pinfunction "NC_4") (pintype "passive+no_connect"))
    )
    (net (code "149") (name "unconnected-(U23-NC-Pad3)") (class "Default")
      (node (ref "U23") (pin "3") (pinfunction "NC_3") (pintype "passive+no_connect"))
    )
    (net (code "150") (name "unconnected-(U23-NC-Pad4)") (class "Default")
      (node (ref "U23") (pin "4") (pinfunction "NC_4") (pintype "passive+no_connect"))
    )
  )
)
